# SMPS.net
KiCad netlist of a schematic drawn in Altium Designer
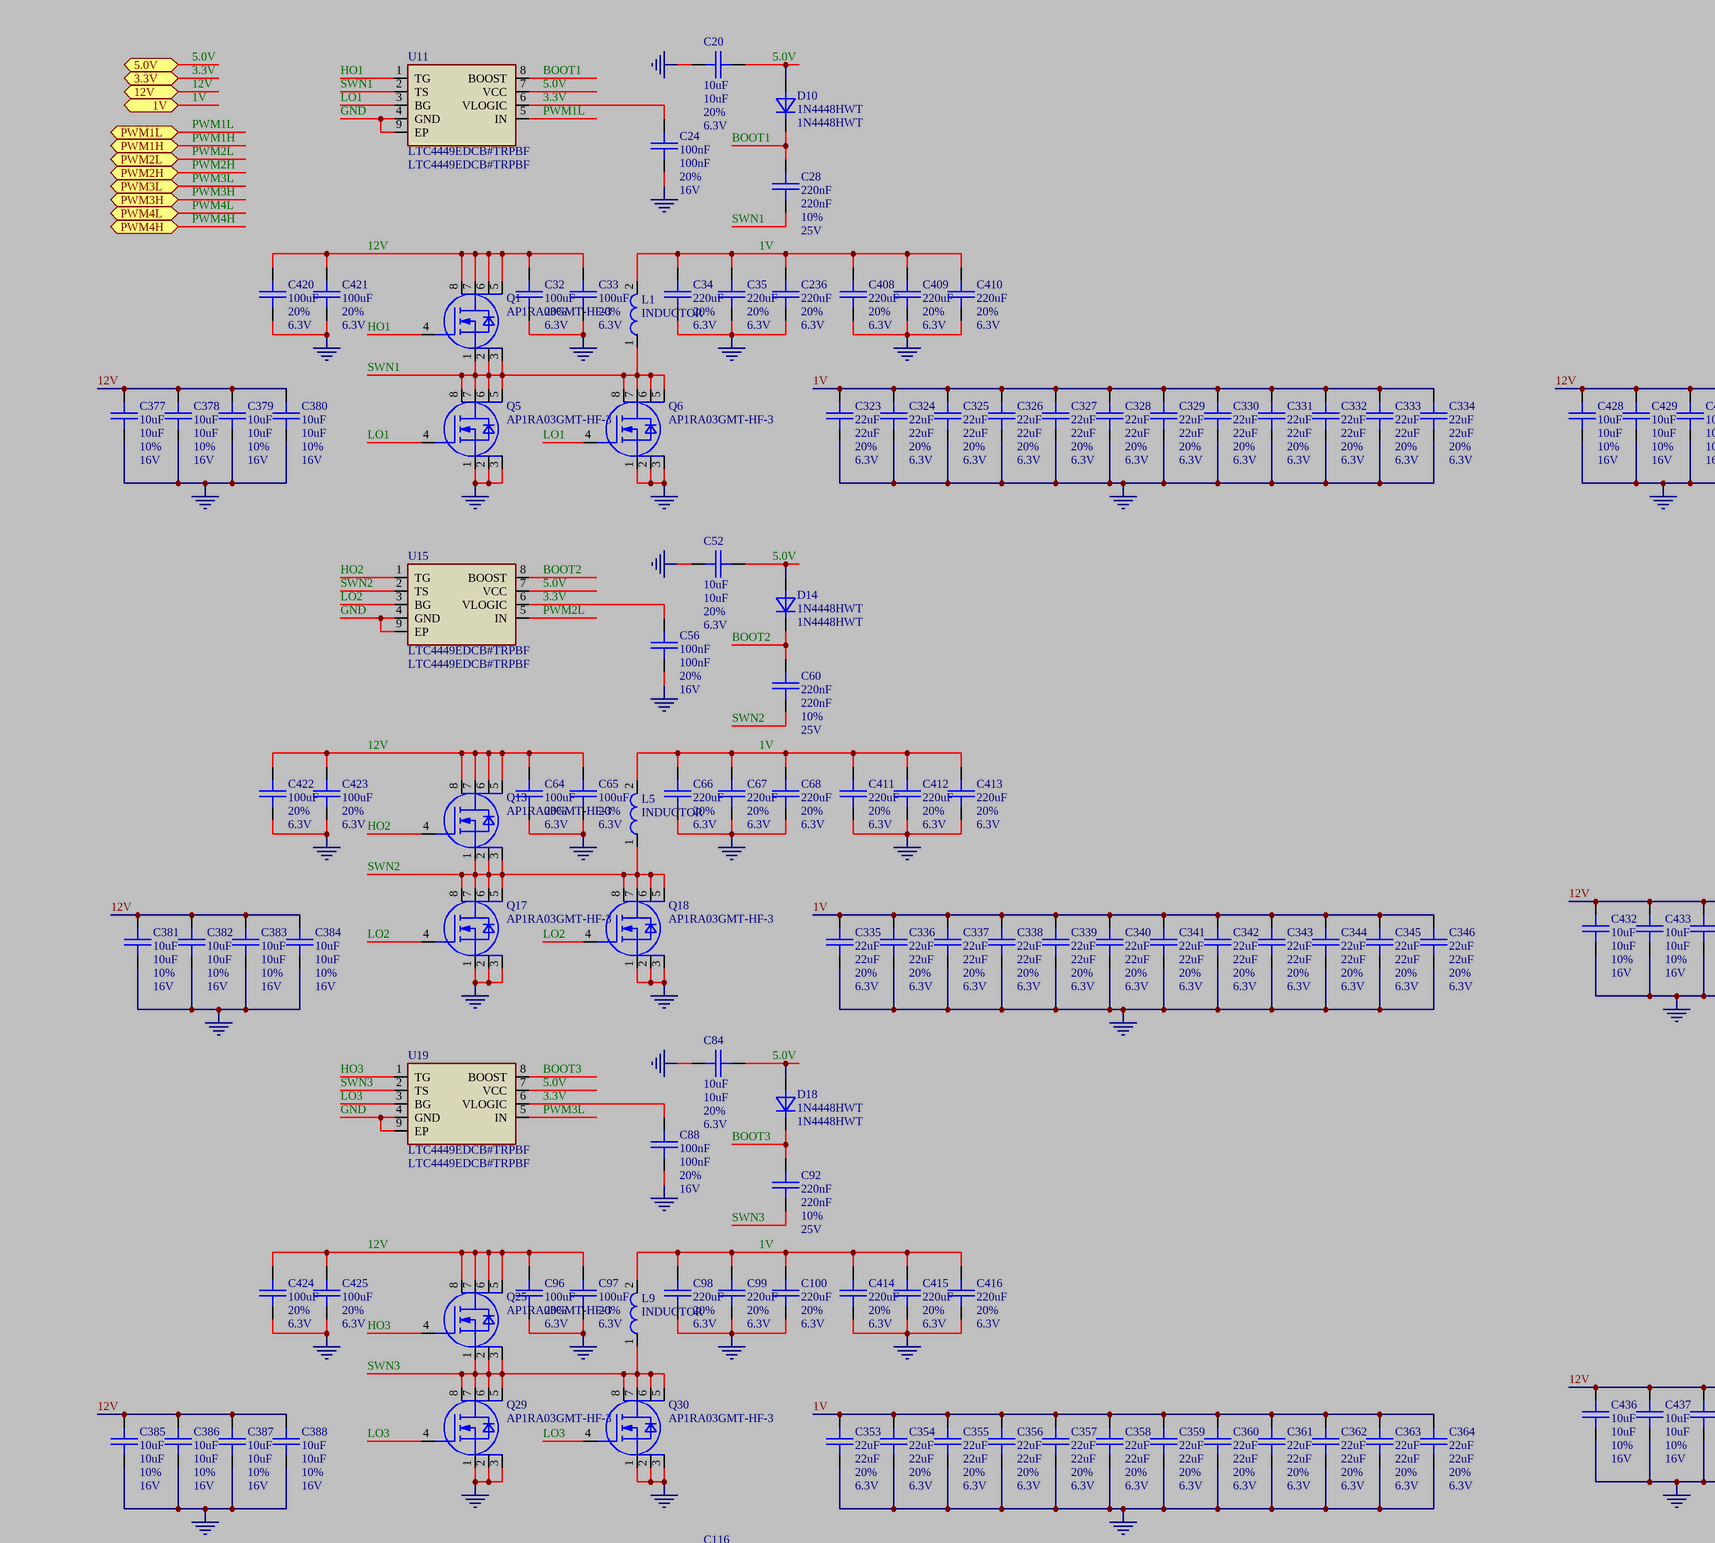
[diagram p0: SMPS.SchDoc, top left]
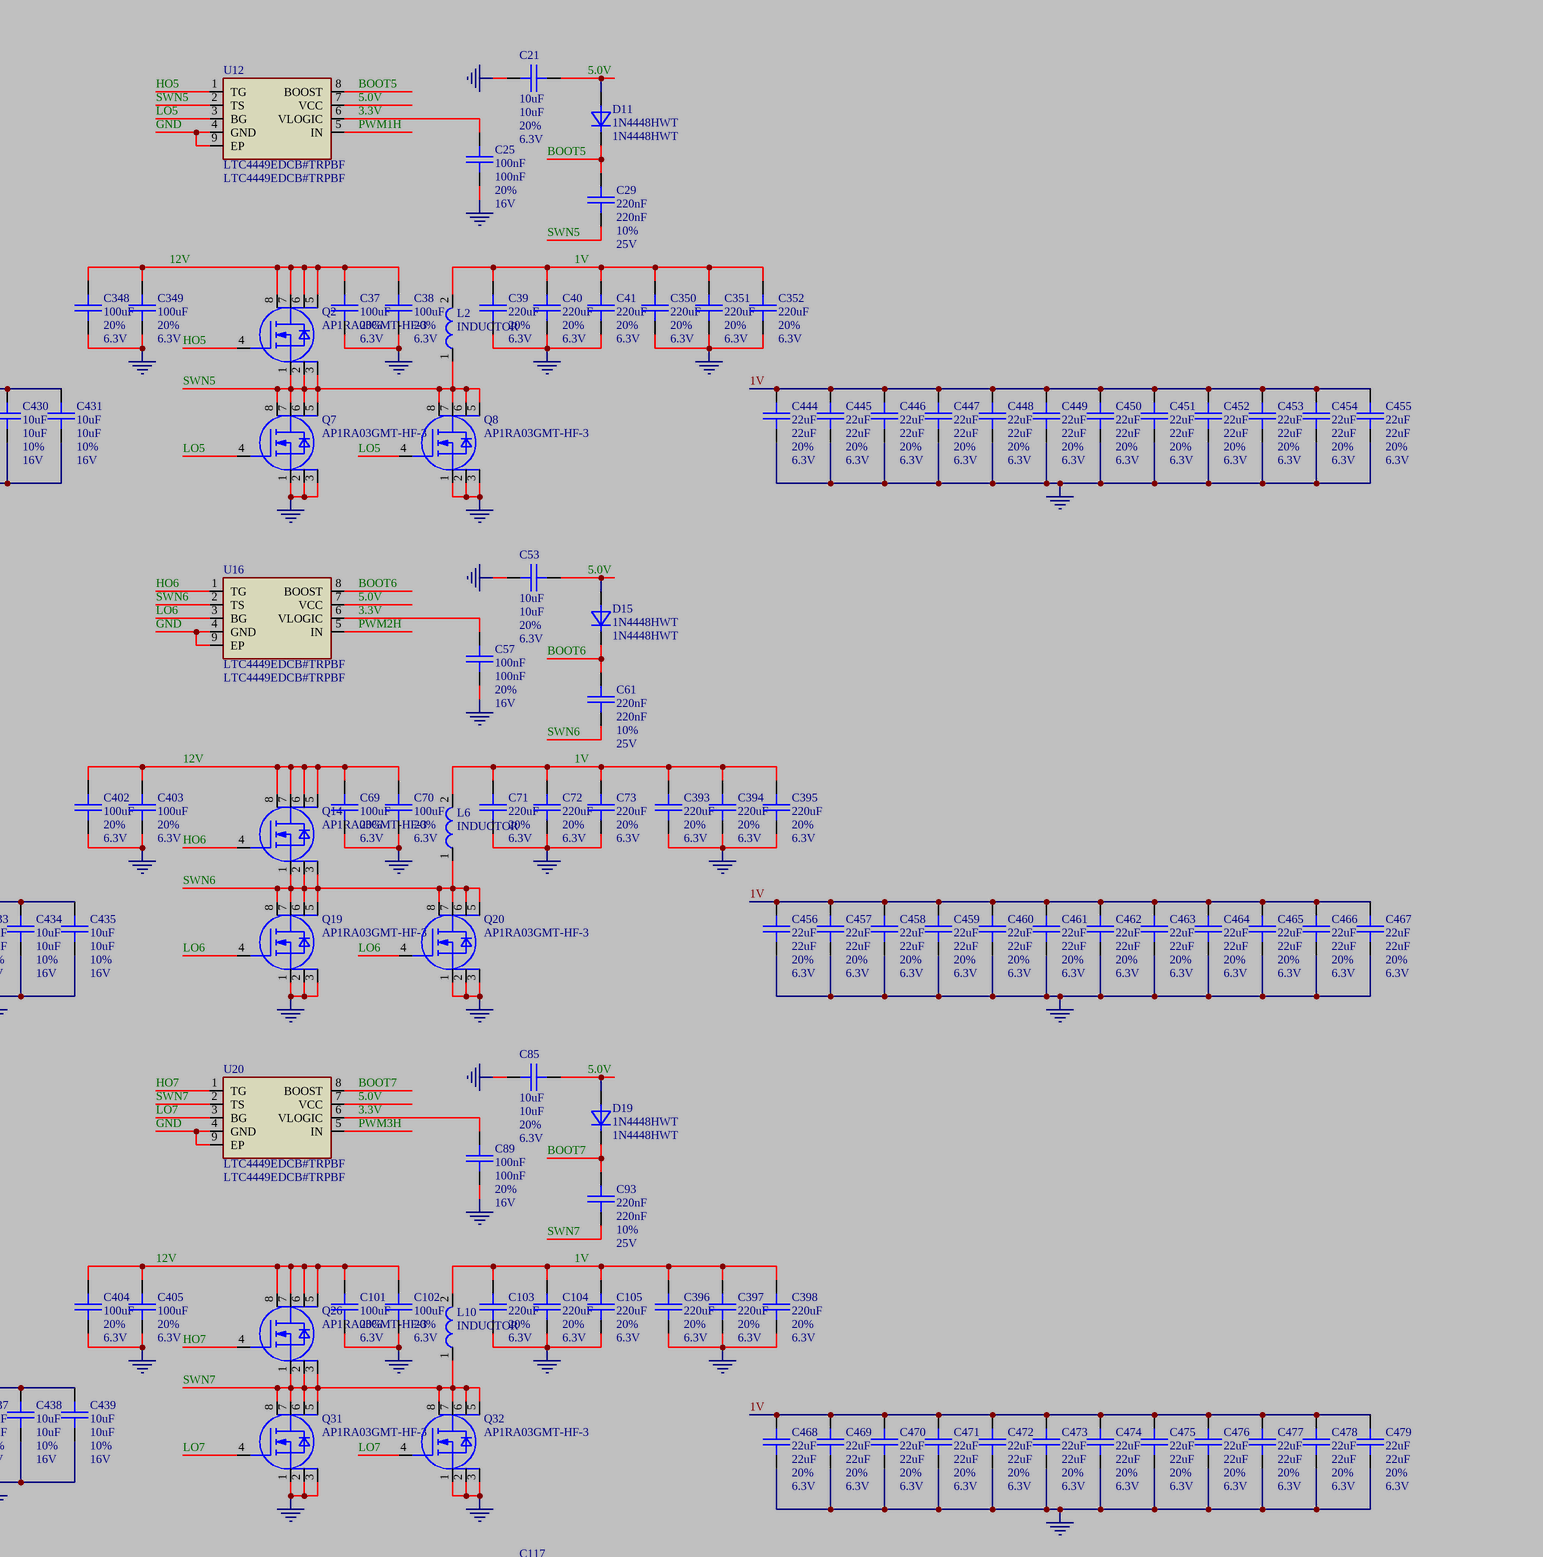
[diagram p1: SMPS.SchDoc, top right]
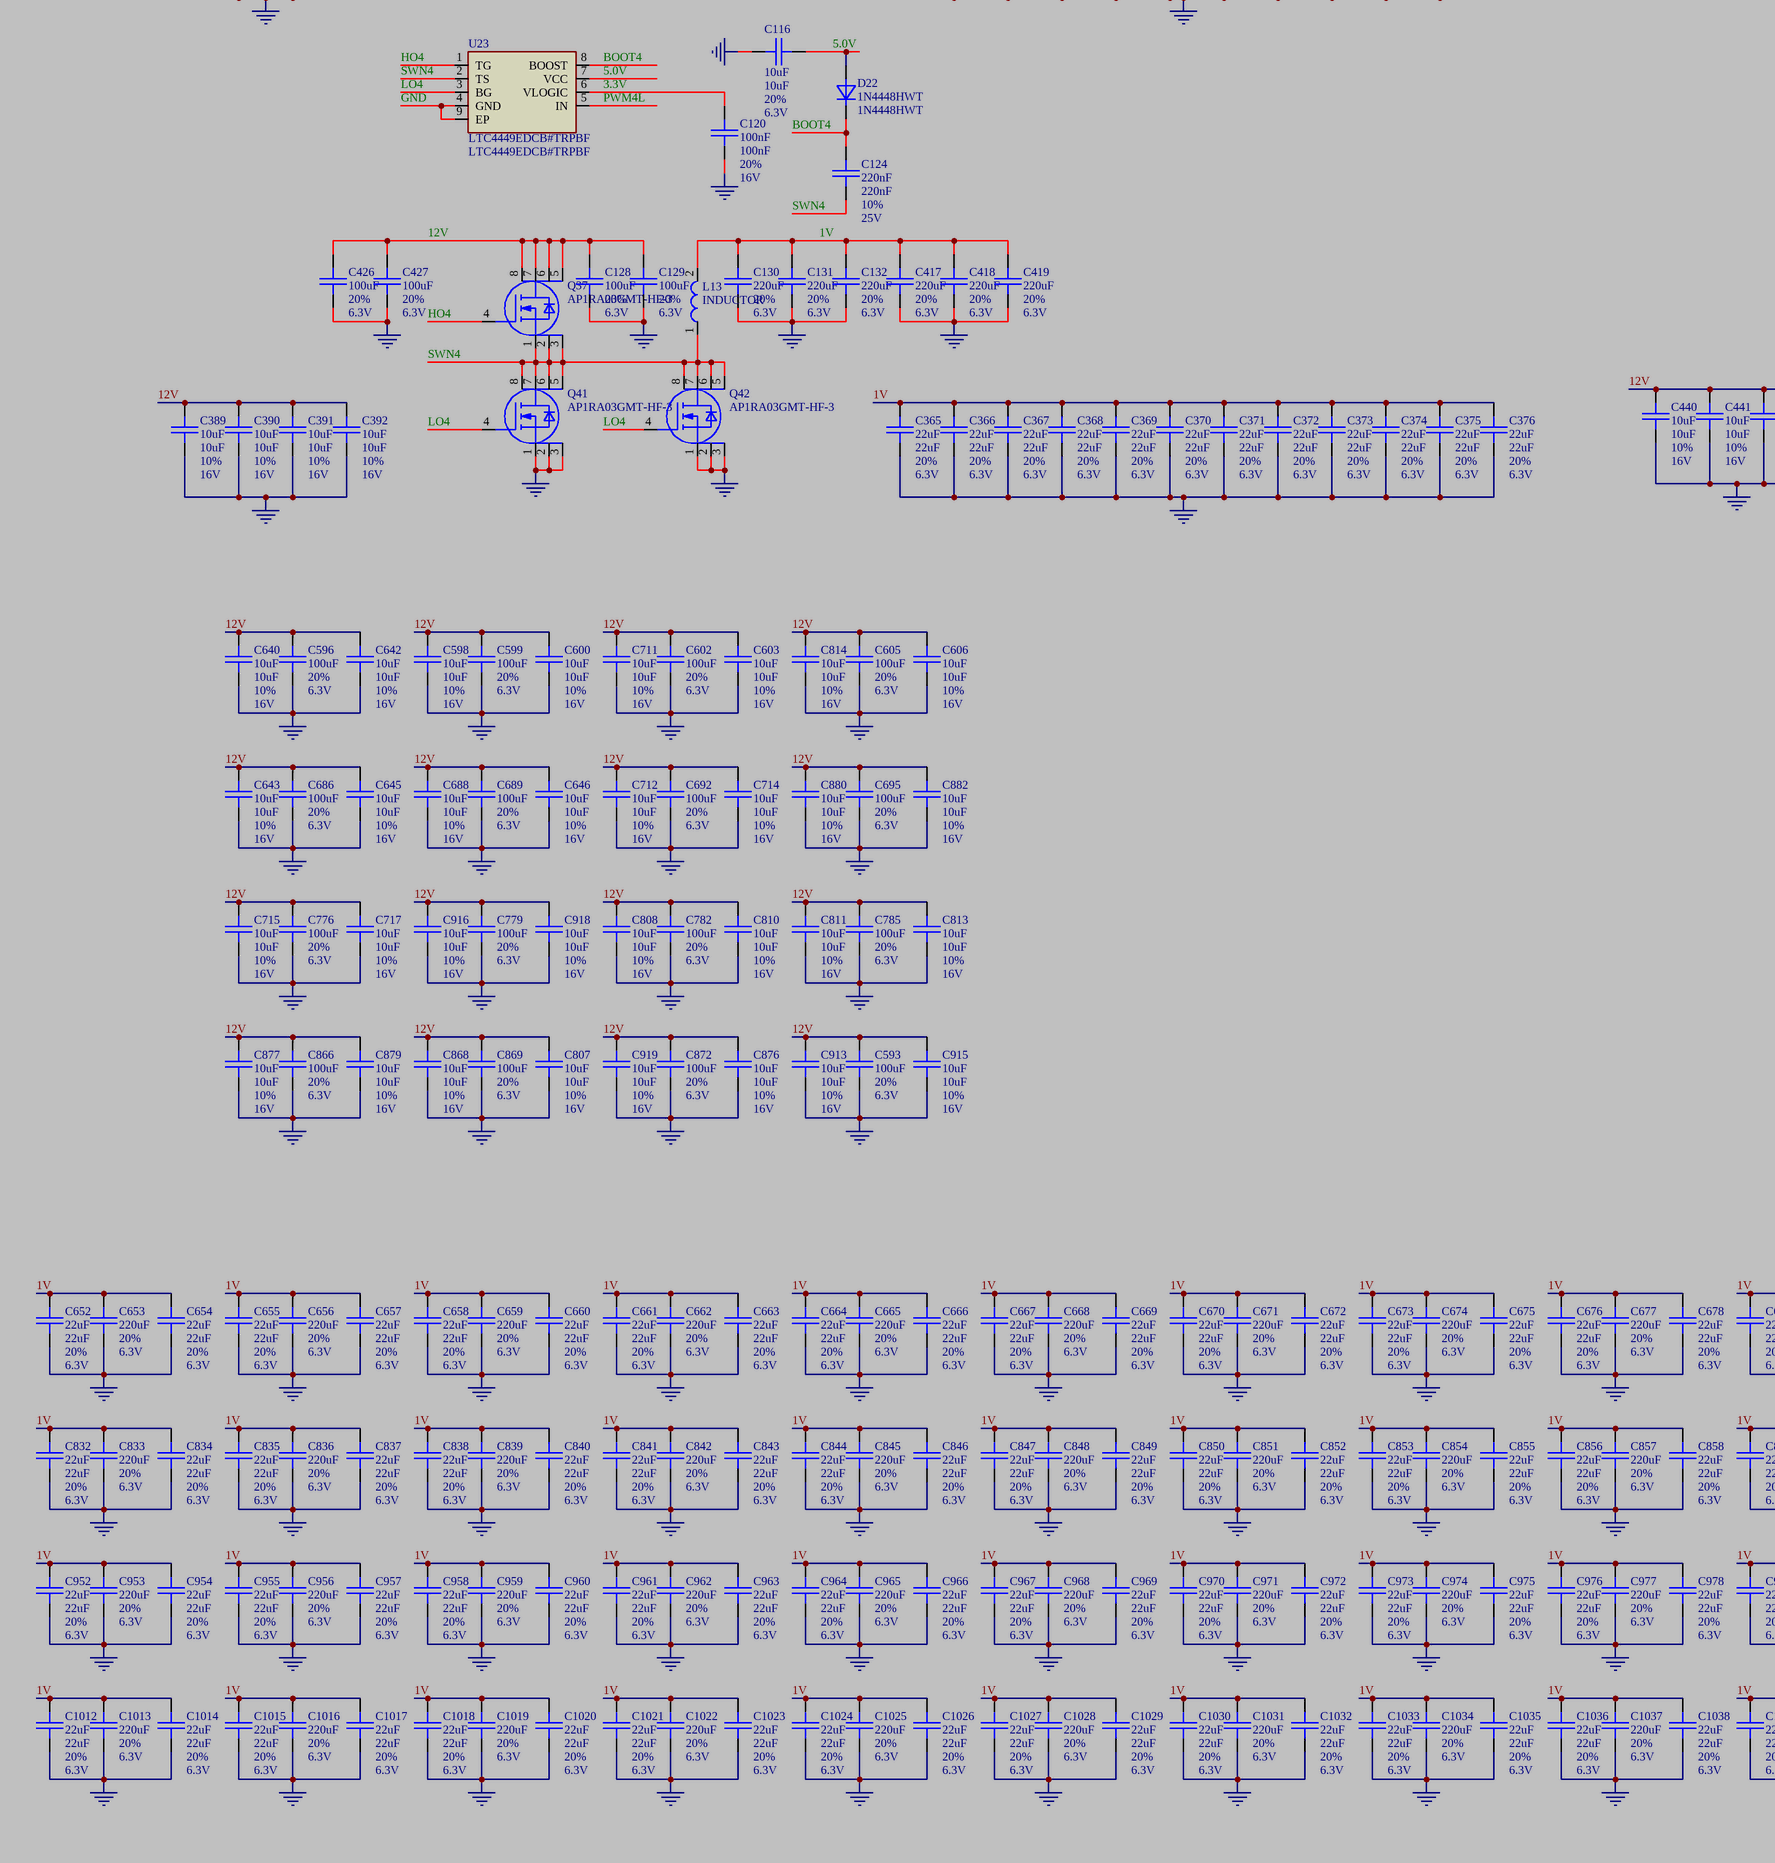
[diagram p2: SMPS.SchDoc, bottom left]
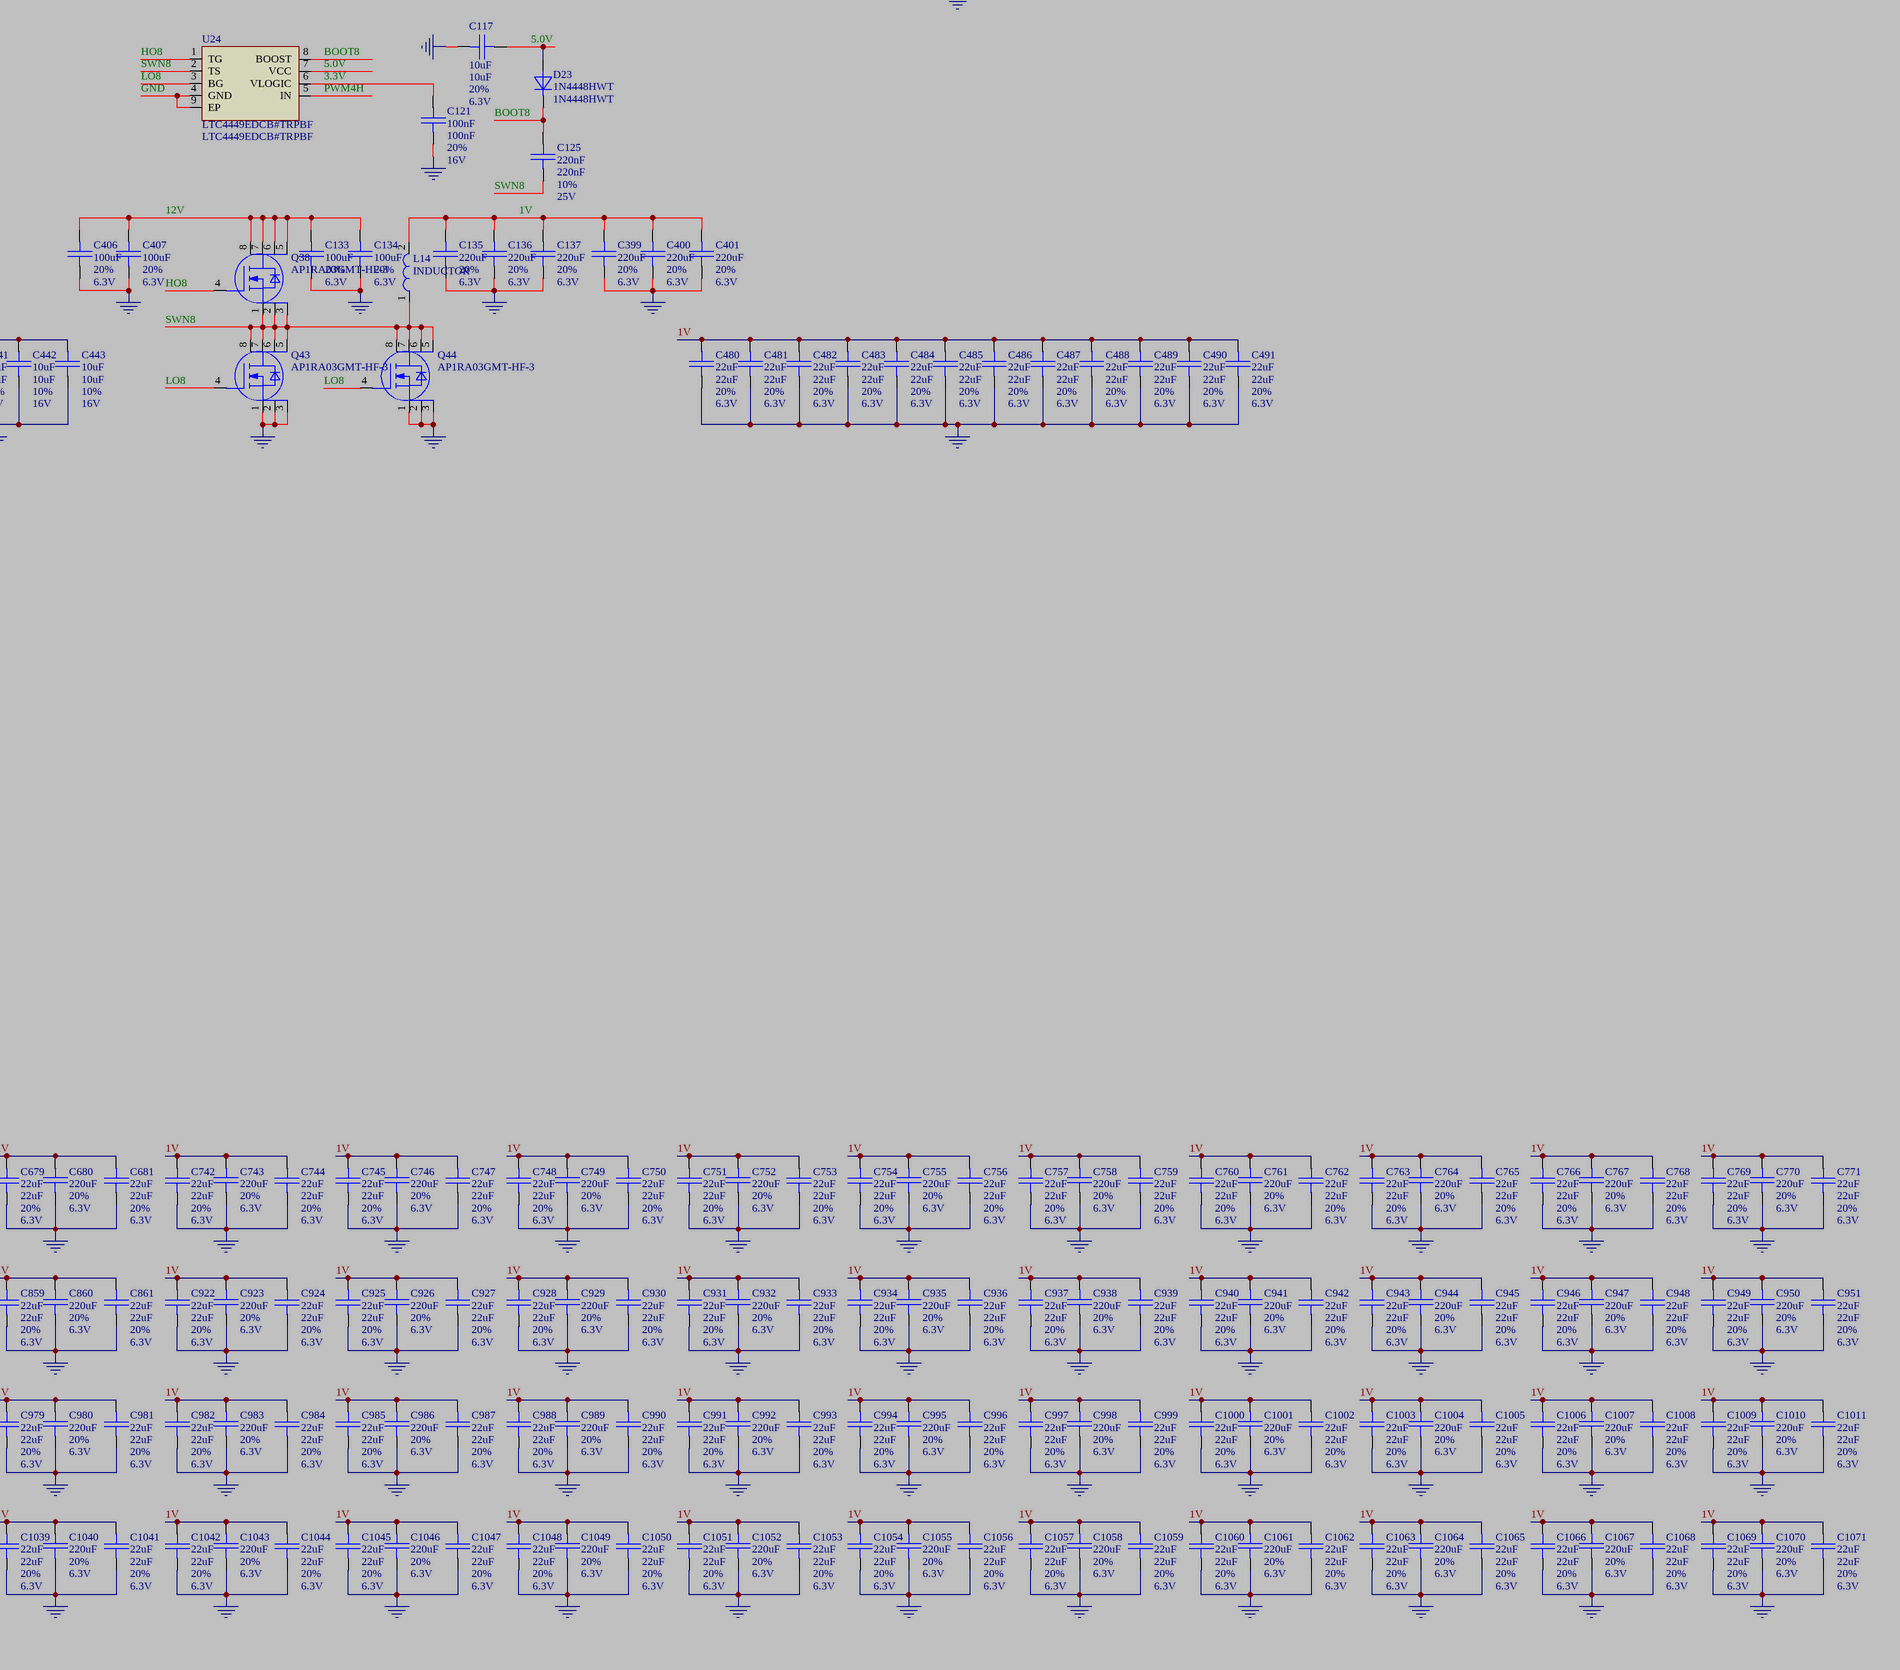
[diagram p3: SMPS.SchDoc, bottom right]

(export (version "E")
  (design (tool "Eeschema 10.0.6"))
  (components
    (comp (ref "C20")
      (value "10uF")
      (footprint "SMD_0603_CAPC1608X95N")
      (fields
        (field (name "DB_PART_NUMBER") "CAP000043646")
        (field (name "DB_VALUE") "10uF")
        (field (name "DB_TOLERANCE") "20%")
        (field (name "DB_VOLTAGE") "6.3V")
        (field (name "DB_MANUFACTURER_PART") "KEMET    C0603C106M9PAC")
        (field (name "DB_APPROVED_BY") "ISHIDDEN=T")
      )
      (libsource (lib "Database_Libs1") (part "C"))
    )
    (comp (ref "C21")
      (value "10uF")
      (footprint "SMD_0603_CAPC1608X95N")
      (fields
        (field (name "DB_PART_NUMBER") "CAP000043646")
        (field (name "DB_VALUE") "10uF")
        (field (name "DB_TOLERANCE") "20%")
        (field (name "DB_VOLTAGE") "6.3V")
        (field (name "DB_MANUFACTURER_PART") "KEMET    C0603C106M9PAC")
        (field (name "DB_APPROVED_BY") "ISHIDDEN=T")
      )
      (libsource (lib "Database_Libs1") (part "C"))
    )
    (comp (ref "C24")
      (value "100nF")
      (footprint "SMD_0402_CAPC1005X55N")
      (fields
        (field (name "DB_PART_NUMBER") "CAP000022751")
        (field (name "DB_VALUE") "100nF")
        (field (name "DB_TOLERANCE") "20%")
        (field (name "DB_VOLTAGE") "16V")
        (field (name "DB_MANUFACTURER_PART") "KEMET    C0402F104M4RAC")
        (field (name "DB_APPROVED_BY") "ISHIDDEN=T")
      )
      (libsource (lib "Database_Libs1") (part "C"))
    )
    (comp (ref "C25")
      (value "100nF")
      (footprint "SMD_0402_CAPC1005X55N")
      (fields
        (field (name "DB_PART_NUMBER") "CAP000022751")
        (field (name "DB_VALUE") "100nF")
        (field (name "DB_TOLERANCE") "20%")
        (field (name "DB_VOLTAGE") "16V")
        (field (name "DB_MANUFACTURER_PART") "KEMET    C0402F104M4RAC")
        (field (name "DB_APPROVED_BY") "ISHIDDEN=T")
      )
      (libsource (lib "Database_Libs1") (part "C"))
    )
    (comp (ref "C28")
      (value "220nF")
      (footprint "SMD_0603_CAPC1608X95N")
      (fields
        (field (name "DB_PART_NUMBER") "CAP000022968")
        (field (name "DB_VALUE") "220nF")
        (field (name "DB_TOLERANCE") "10%")
        (field (name "DB_VOLTAGE") "25V")
        (field (name "DB_MANUFACTURER_PART") "KEMET    C0603F224K3RAC")
        (field (name "DB_APPROVED_BY") "ISHIDDEN=T")
      )
      (libsource (lib "Database_Libs1") (part "C"))
    )
    (comp (ref "C29")
      (value "220nF")
      (footprint "SMD_0603_CAPC1608X95N")
      (fields
        (field (name "DB_PART_NUMBER") "CAP000022968")
        (field (name "DB_VALUE") "220nF")
        (field (name "DB_TOLERANCE") "10%")
        (field (name "DB_VOLTAGE") "25V")
        (field (name "DB_MANUFACTURER_PART") "KEMET    C0603F224K3RAC")
        (field (name "DB_APPROVED_BY") "ISHIDDEN=T")
      )
      (libsource (lib "Database_Libs1") (part "C"))
    )
    (comp (ref "C32")
      (value "100uF")
      (footprint "SMD_1210_CAPC3225X270N")
      (fields
        (field (name "DB_PART_NUMBER") "CAP000043701")
        (field (name "DB_VALUE") "100uF")
        (field (name "DB_TOLERANCE") "20%")
        (field (name "DB_VOLTAGE") "6.3V")
        (field (name "DB_MANUFACTURER_PART") "KEMET    C1210C107M9PAC")
        (field (name "DB_APPROVED_BY") "ISHIDDEN=T")
      )
      (libsource (lib "Database_Libs1") (part "C"))
    )
    (comp (ref "C33")
      (value "100uF")
      (footprint "SMD_1210_CAPC3225X270N")
      (fields
        (field (name "DB_PART_NUMBER") "CAP000043701")
        (field (name "DB_VALUE") "100uF")
        (field (name "DB_TOLERANCE") "20%")
        (field (name "DB_VOLTAGE") "6.3V")
        (field (name "DB_MANUFACTURER_PART") "KEMET    C1210C107M9PAC")
        (field (name "DB_APPROVED_BY") "ISHIDDEN=T")
      )
      (libsource (lib "Database_Libs1") (part "C"))
    )
    (comp (ref "C34")
      (value "220uF")
      (footprint "SMD_1210_CAPC3225X279N")
      (fields
        (field (name "DB_PART_NUMBER") "CAP000047355")
        (field (name "DB_VALUE") "220uF")
        (field (name "DB_TOLERANCE") "20%")
        (field (name "DB_VOLTAGE") "6.3V")
        (field (name "DB_MANUFACTURER_PART") "SAMSUNG    CL32A227MQVNNNE")
        (field (name "DB_APPROVED_BY") "VSN")
      )
      (libsource (lib "Database_Libs1") (part "C"))
    )
    (comp (ref "C35")
      (value "220uF")
      (footprint "SMD_1210_CAPC3225X279N")
      (fields
        (field (name "DB_PART_NUMBER") "CAP000047355")
        (field (name "DB_VALUE") "220uF")
        (field (name "DB_TOLERANCE") "20%")
        (field (name "DB_VOLTAGE") "6.3V")
        (field (name "DB_MANUFACTURER_PART") "SAMSUNG    CL32A227MQVNNNE")
        (field (name "DB_APPROVED_BY") "VSN")
      )
      (libsource (lib "Database_Libs1") (part "C"))
    )
    (comp (ref "C37")
      (value "100uF")
      (footprint "SMD_1210_CAPC3225X270N")
      (fields
        (field (name "DB_PART_NUMBER") "CAP000043701")
        (field (name "DB_VALUE") "100uF")
        (field (name "DB_TOLERANCE") "20%")
        (field (name "DB_VOLTAGE") "6.3V")
        (field (name "DB_MANUFACTURER_PART") "KEMET    C1210C107M9PAC")
        (field (name "DB_APPROVED_BY") "ISHIDDEN=T")
      )
      (libsource (lib "Database_Libs1") (part "C"))
    )
    (comp (ref "C38")
      (value "100uF")
      (footprint "SMD_1210_CAPC3225X270N")
      (fields
        (field (name "DB_PART_NUMBER") "CAP000043701")
        (field (name "DB_VALUE") "100uF")
        (field (name "DB_TOLERANCE") "20%")
        (field (name "DB_VOLTAGE") "6.3V")
        (field (name "DB_MANUFACTURER_PART") "KEMET    C1210C107M9PAC")
        (field (name "DB_APPROVED_BY") "ISHIDDEN=T")
      )
      (libsource (lib "Database_Libs1") (part "C"))
    )
    (comp (ref "C39")
      (value "220uF")
      (footprint "SMD_1210_CAPC3225X279N")
      (fields
        (field (name "DB_PART_NUMBER") "CAP000047355")
        (field (name "DB_VALUE") "220uF")
        (field (name "DB_TOLERANCE") "20%")
        (field (name "DB_VOLTAGE") "6.3V")
        (field (name "DB_MANUFACTURER_PART") "SAMSUNG    CL32A227MQVNNNE")
        (field (name "DB_APPROVED_BY") "VSN")
      )
      (libsource (lib "Database_Libs1") (part "C"))
    )
    (comp (ref "C40")
      (value "220uF")
      (footprint "SMD_1210_CAPC3225X279N")
      (fields
        (field (name "DB_PART_NUMBER") "CAP000047355")
        (field (name "DB_VALUE") "220uF")
        (field (name "DB_TOLERANCE") "20%")
        (field (name "DB_VOLTAGE") "6.3V")
        (field (name "DB_MANUFACTURER_PART") "SAMSUNG    CL32A227MQVNNNE")
        (field (name "DB_APPROVED_BY") "VSN")
      )
      (libsource (lib "Database_Libs1") (part "C"))
    )
    (comp (ref "C41")
      (value "220uF")
      (footprint "SMD_1210_CAPC3225X279N")
      (fields
        (field (name "DB_PART_NUMBER") "CAP000047355")
        (field (name "DB_VALUE") "220uF")
        (field (name "DB_TOLERANCE") "20%")
        (field (name "DB_VOLTAGE") "6.3V")
        (field (name "DB_MANUFACTURER_PART") "SAMSUNG    CL32A227MQVNNNE")
        (field (name "DB_APPROVED_BY") "VSN")
      )
      (libsource (lib "Database_Libs1") (part "C"))
    )
    (comp (ref "C52")
      (value "10uF")
      (footprint "SMD_0603_CAPC1608X95N")
      (fields
        (field (name "DB_PART_NUMBER") "CAP000043646")
        (field (name "DB_VALUE") "10uF")
        (field (name "DB_TOLERANCE") "20%")
        (field (name "DB_VOLTAGE") "6.3V")
        (field (name "DB_MANUFACTURER_PART") "KEMET    C0603C106M9PAC")
        (field (name "DB_APPROVED_BY") "ISHIDDEN=T")
      )
      (libsource (lib "Database_Libs1") (part "C"))
    )
    (comp (ref "C53")
      (value "10uF")
      (footprint "SMD_0603_CAPC1608X95N")
      (fields
        (field (name "DB_PART_NUMBER") "CAP000043646")
        (field (name "DB_VALUE") "10uF")
        (field (name "DB_TOLERANCE") "20%")
        (field (name "DB_VOLTAGE") "6.3V")
        (field (name "DB_MANUFACTURER_PART") "KEMET    C0603C106M9PAC")
        (field (name "DB_APPROVED_BY") "ISHIDDEN=T")
      )
      (libsource (lib "Database_Libs1") (part "C"))
    )
    (comp (ref "C56")
      (value "100nF")
      (footprint "SMD_0402_CAPC1005X55N")
      (fields
        (field (name "DB_PART_NUMBER") "CAP000022751")
        (field (name "DB_VALUE") "100nF")
        (field (name "DB_TOLERANCE") "20%")
        (field (name "DB_VOLTAGE") "16V")
        (field (name "DB_MANUFACTURER_PART") "KEMET    C0402F104M4RAC")
        (field (name "DB_APPROVED_BY") "ISHIDDEN=T")
      )
      (libsource (lib "Database_Libs1") (part "C"))
    )
    (comp (ref "C57")
      (value "100nF")
      (footprint "SMD_0402_CAPC1005X55N")
      (fields
        (field (name "DB_PART_NUMBER") "CAP000022751")
        (field (name "DB_VALUE") "100nF")
        (field (name "DB_TOLERANCE") "20%")
        (field (name "DB_VOLTAGE") "16V")
        (field (name "DB_MANUFACTURER_PART") "KEMET    C0402F104M4RAC")
        (field (name "DB_APPROVED_BY") "ISHIDDEN=T")
      )
      (libsource (lib "Database_Libs1") (part "C"))
    )
    (comp (ref "C60")
      (value "220nF")
      (footprint "SMD_0603_CAPC1608X95N")
      (fields
        (field (name "DB_PART_NUMBER") "CAP000022968")
        (field (name "DB_VALUE") "220nF")
        (field (name "DB_TOLERANCE") "10%")
        (field (name "DB_VOLTAGE") "25V")
        (field (name "DB_MANUFACTURER_PART") "KEMET    C0603F224K3RAC")
        (field (name "DB_APPROVED_BY") "ISHIDDEN=T")
      )
      (libsource (lib "Database_Libs1") (part "C"))
    )
    (comp (ref "C61")
      (value "220nF")
      (footprint "SMD_0603_CAPC1608X95N")
      (fields
        (field (name "DB_PART_NUMBER") "CAP000022968")
        (field (name "DB_VALUE") "220nF")
        (field (name "DB_TOLERANCE") "10%")
        (field (name "DB_VOLTAGE") "25V")
        (field (name "DB_MANUFACTURER_PART") "KEMET    C0603F224K3RAC")
        (field (name "DB_APPROVED_BY") "ISHIDDEN=T")
      )
      (libsource (lib "Database_Libs1") (part "C"))
    )
    (comp (ref "C64")
      (value "100uF")
      (footprint "SMD_1210_CAPC3225X270N")
      (fields
        (field (name "DB_PART_NUMBER") "CAP000043701")
        (field (name "DB_VALUE") "100uF")
        (field (name "DB_TOLERANCE") "20%")
        (field (name "DB_VOLTAGE") "6.3V")
        (field (name "DB_MANUFACTURER_PART") "KEMET    C1210C107M9PAC")
        (field (name "DB_APPROVED_BY") "ISHIDDEN=T")
      )
      (libsource (lib "Database_Libs1") (part "C"))
    )
    (comp (ref "C65")
      (value "100uF")
      (footprint "SMD_1210_CAPC3225X270N")
      (fields
        (field (name "DB_PART_NUMBER") "CAP000043701")
        (field (name "DB_VALUE") "100uF")
        (field (name "DB_TOLERANCE") "20%")
        (field (name "DB_VOLTAGE") "6.3V")
        (field (name "DB_MANUFACTURER_PART") "KEMET    C1210C107M9PAC")
        (field (name "DB_APPROVED_BY") "ISHIDDEN=T")
      )
      (libsource (lib "Database_Libs1") (part "C"))
    )
    (comp (ref "C66")
      (value "220uF")
      (footprint "SMD_1210_CAPC3225X279N")
      (fields
        (field (name "DB_PART_NUMBER") "CAP000047355")
        (field (name "DB_VALUE") "220uF")
        (field (name "DB_TOLERANCE") "20%")
        (field (name "DB_VOLTAGE") "6.3V")
        (field (name "DB_MANUFACTURER_PART") "SAMSUNG    CL32A227MQVNNNE")
        (field (name "DB_APPROVED_BY") "VSN")
      )
      (libsource (lib "Database_Libs1") (part "C"))
    )
    (comp (ref "C67")
      (value "220uF")
      (footprint "SMD_1210_CAPC3225X279N")
      (fields
        (field (name "DB_PART_NUMBER") "CAP000047355")
        (field (name "DB_VALUE") "220uF")
        (field (name "DB_TOLERANCE") "20%")
        (field (name "DB_VOLTAGE") "6.3V")
        (field (name "DB_MANUFACTURER_PART") "SAMSUNG    CL32A227MQVNNNE")
        (field (name "DB_APPROVED_BY") "VSN")
      )
      (libsource (lib "Database_Libs1") (part "C"))
    )
    (comp (ref "C68")
      (value "220uF")
      (footprint "SMD_1210_CAPC3225X279N")
      (fields
        (field (name "DB_PART_NUMBER") "CAP000047355")
        (field (name "DB_VALUE") "220uF")
        (field (name "DB_TOLERANCE") "20%")
        (field (name "DB_VOLTAGE") "6.3V")
        (field (name "DB_MANUFACTURER_PART") "SAMSUNG    CL32A227MQVNNNE")
        (field (name "DB_APPROVED_BY") "VSN")
      )
      (libsource (lib "Database_Libs1") (part "C"))
    )
    (comp (ref "C69")
      (value "100uF")
      (footprint "SMD_1210_CAPC3225X270N")
      (fields
        (field (name "DB_PART_NUMBER") "CAP000043701")
        (field (name "DB_VALUE") "100uF")
        (field (name "DB_TOLERANCE") "20%")
        (field (name "DB_VOLTAGE") "6.3V")
        (field (name "DB_MANUFACTURER_PART") "KEMET    C1210C107M9PAC")
        (field (name "DB_APPROVED_BY") "ISHIDDEN=T")
      )
      (libsource (lib "Database_Libs1") (part "C"))
    )
    (comp (ref "C70")
      (value "100uF")
      (footprint "SMD_1210_CAPC3225X270N")
      (fields
        (field (name "DB_PART_NUMBER") "CAP000043701")
        (field (name "DB_VALUE") "100uF")
        (field (name "DB_TOLERANCE") "20%")
        (field (name "DB_VOLTAGE") "6.3V")
        (field (name "DB_MANUFACTURER_PART") "KEMET    C1210C107M9PAC")
        (field (name "DB_APPROVED_BY") "ISHIDDEN=T")
      )
      (libsource (lib "Database_Libs1") (part "C"))
    )
    (comp (ref "C71")
      (value "220uF")
      (footprint "SMD_1210_CAPC3225X279N")
      (fields
        (field (name "DB_PART_NUMBER") "CAP000047355")
        (field (name "DB_VALUE") "220uF")
        (field (name "DB_TOLERANCE") "20%")
        (field (name "DB_VOLTAGE") "6.3V")
        (field (name "DB_MANUFACTURER_PART") "SAMSUNG    CL32A227MQVNNNE")
        (field (name "DB_APPROVED_BY") "VSN")
      )
      (libsource (lib "Database_Libs1") (part "C"))
    )
    (comp (ref "C72")
      (value "220uF")
      (footprint "SMD_1210_CAPC3225X279N")
      (fields
        (field (name "DB_PART_NUMBER") "CAP000047355")
        (field (name "DB_VALUE") "220uF")
        (field (name "DB_TOLERANCE") "20%")
        (field (name "DB_VOLTAGE") "6.3V")
        (field (name "DB_MANUFACTURER_PART") "SAMSUNG    CL32A227MQVNNNE")
        (field (name "DB_APPROVED_BY") "VSN")
      )
      (libsource (lib "Database_Libs1") (part "C"))
    )
    (comp (ref "C73")
      (value "220uF")
      (footprint "SMD_1210_CAPC3225X279N")
      (fields
        (field (name "DB_PART_NUMBER") "CAP000047355")
        (field (name "DB_VALUE") "220uF")
        (field (name "DB_TOLERANCE") "20%")
        (field (name "DB_VOLTAGE") "6.3V")
        (field (name "DB_MANUFACTURER_PART") "SAMSUNG    CL32A227MQVNNNE")
        (field (name "DB_APPROVED_BY") "VSN")
      )
      (libsource (lib "Database_Libs1") (part "C"))
    )
    (comp (ref "C84")
      (value "10uF")
      (footprint "SMD_0603_CAPC1608X95N")
      (fields
        (field (name "DB_PART_NUMBER") "CAP000043646")
        (field (name "DB_VALUE") "10uF")
        (field (name "DB_TOLERANCE") "20%")
        (field (name "DB_VOLTAGE") "6.3V")
        (field (name "DB_MANUFACTURER_PART") "KEMET    C0603C106M9PAC")
        (field (name "DB_APPROVED_BY") "ISHIDDEN=T")
      )
      (libsource (lib "Database_Libs1") (part "C"))
    )
    (comp (ref "C85")
      (value "10uF")
      (footprint "SMD_0603_CAPC1608X95N")
      (fields
        (field (name "DB_PART_NUMBER") "CAP000043646")
        (field (name "DB_VALUE") "10uF")
        (field (name "DB_TOLERANCE") "20%")
        (field (name "DB_VOLTAGE") "6.3V")
        (field (name "DB_MANUFACTURER_PART") "KEMET    C0603C106M9PAC")
        (field (name "DB_APPROVED_BY") "ISHIDDEN=T")
      )
      (libsource (lib "Database_Libs1") (part "C"))
    )
    (comp (ref "C88")
      (value "100nF")
      (footprint "SMD_0402_CAPC1005X55N")
      (fields
        (field (name "DB_PART_NUMBER") "CAP000022751")
        (field (name "DB_VALUE") "100nF")
        (field (name "DB_TOLERANCE") "20%")
        (field (name "DB_VOLTAGE") "16V")
        (field (name "DB_MANUFACTURER_PART") "KEMET    C0402F104M4RAC")
        (field (name "DB_APPROVED_BY") "ISHIDDEN=T")
      )
      (libsource (lib "Database_Libs1") (part "C"))
    )
    (comp (ref "C89")
      (value "100nF")
      (footprint "SMD_0402_CAPC1005X55N")
      (fields
        (field (name "DB_PART_NUMBER") "CAP000022751")
        (field (name "DB_VALUE") "100nF")
        (field (name "DB_TOLERANCE") "20%")
        (field (name "DB_VOLTAGE") "16V")
        (field (name "DB_MANUFACTURER_PART") "KEMET    C0402F104M4RAC")
        (field (name "DB_APPROVED_BY") "ISHIDDEN=T")
      )
      (libsource (lib "Database_Libs1") (part "C"))
    )
    (comp (ref "C92")
      (value "220nF")
      (footprint "SMD_0603_CAPC1608X95N")
      (fields
        (field (name "DB_PART_NUMBER") "CAP000022968")
        (field (name "DB_VALUE") "220nF")
        (field (name "DB_TOLERANCE") "10%")
        (field (name "DB_VOLTAGE") "25V")
        (field (name "DB_MANUFACTURER_PART") "KEMET    C0603F224K3RAC")
        (field (name "DB_APPROVED_BY") "ISHIDDEN=T")
      )
      (libsource (lib "Database_Libs1") (part "C"))
    )
    (comp (ref "C93")
      (value "220nF")
      (footprint "SMD_0603_CAPC1608X95N")
      (fields
        (field (name "DB_PART_NUMBER") "CAP000022968")
        (field (name "DB_VALUE") "220nF")
        (field (name "DB_TOLERANCE") "10%")
        (field (name "DB_VOLTAGE") "25V")
        (field (name "DB_MANUFACTURER_PART") "KEMET    C0603F224K3RAC")
        (field (name "DB_APPROVED_BY") "ISHIDDEN=T")
      )
      (libsource (lib "Database_Libs1") (part "C"))
    )
    (comp (ref "C96")
      (value "100uF")
      (footprint "SMD_1210_CAPC3225X270N")
      (fields
        (field (name "DB_PART_NUMBER") "CAP000043701")
        (field (name "DB_VALUE") "100uF")
        (field (name "DB_TOLERANCE") "20%")
        (field (name "DB_VOLTAGE") "6.3V")
        (field (name "DB_MANUFACTURER_PART") "KEMET    C1210C107M9PAC")
        (field (name "DB_APPROVED_BY") "ISHIDDEN=T")
      )
      (libsource (lib "Database_Libs1") (part "C"))
    )
    (comp (ref "C97")
      (value "100uF")
      (footprint "SMD_1210_CAPC3225X270N")
      (fields
        (field (name "DB_PART_NUMBER") "CAP000043701")
        (field (name "DB_VALUE") "100uF")
        (field (name "DB_TOLERANCE") "20%")
        (field (name "DB_VOLTAGE") "6.3V")
        (field (name "DB_MANUFACTURER_PART") "KEMET    C1210C107M9PAC")
        (field (name "DB_APPROVED_BY") "ISHIDDEN=T")
      )
      (libsource (lib "Database_Libs1") (part "C"))
    )
    (comp (ref "C98")
      (value "220uF")
      (footprint "SMD_1210_CAPC3225X279N")
      (fields
        (field (name "DB_PART_NUMBER") "CAP000047355")
        (field (name "DB_VALUE") "220uF")
        (field (name "DB_TOLERANCE") "20%")
        (field (name "DB_VOLTAGE") "6.3V")
        (field (name "DB_MANUFACTURER_PART") "SAMSUNG    CL32A227MQVNNNE")
        (field (name "DB_APPROVED_BY") "VSN")
      )
      (libsource (lib "Database_Libs1") (part "C"))
    )
    (comp (ref "C99")
      (value "220uF")
      (footprint "SMD_1210_CAPC3225X279N")
      (fields
        (field (name "DB_PART_NUMBER") "CAP000047355")
        (field (name "DB_VALUE") "220uF")
        (field (name "DB_TOLERANCE") "20%")
        (field (name "DB_VOLTAGE") "6.3V")
        (field (name "DB_MANUFACTURER_PART") "SAMSUNG    CL32A227MQVNNNE")
        (field (name "DB_APPROVED_BY") "VSN")
      )
      (libsource (lib "Database_Libs1") (part "C"))
    )
    (comp (ref "C100")
      (value "220uF")
      (footprint "SMD_1210_CAPC3225X279N")
      (fields
        (field (name "DB_PART_NUMBER") "CAP000047355")
        (field (name "DB_VALUE") "220uF")
        (field (name "DB_TOLERANCE") "20%")
        (field (name "DB_VOLTAGE") "6.3V")
        (field (name "DB_MANUFACTURER_PART") "SAMSUNG    CL32A227MQVNNNE")
        (field (name "DB_APPROVED_BY") "VSN")
      )
      (libsource (lib "Database_Libs1") (part "C"))
    )
    (comp (ref "C101")
      (value "100uF")
      (footprint "SMD_1210_CAPC3225X270N")
      (fields
        (field (name "DB_PART_NUMBER") "CAP000043701")
        (field (name "DB_VALUE") "100uF")
        (field (name "DB_TOLERANCE") "20%")
        (field (name "DB_VOLTAGE") "6.3V")
        (field (name "DB_MANUFACTURER_PART") "KEMET    C1210C107M9PAC")
        (field (name "DB_APPROVED_BY") "ISHIDDEN=T")
      )
      (libsource (lib "Database_Libs1") (part "C"))
    )
    (comp (ref "C102")
      (value "100uF")
      (footprint "SMD_1210_CAPC3225X270N")
      (fields
        (field (name "DB_PART_NUMBER") "CAP000043701")
        (field (name "DB_VALUE") "100uF")
        (field (name "DB_TOLERANCE") "20%")
        (field (name "DB_VOLTAGE") "6.3V")
        (field (name "DB_MANUFACTURER_PART") "KEMET    C1210C107M9PAC")
        (field (name "DB_APPROVED_BY") "ISHIDDEN=T")
      )
      (libsource (lib "Database_Libs1") (part "C"))
    )
    (comp (ref "C103")
      (value "220uF")
      (footprint "SMD_1210_CAPC3225X279N")
      (fields
        (field (name "DB_PART_NUMBER") "CAP000047355")
        (field (name "DB_VALUE") "220uF")
        (field (name "DB_TOLERANCE") "20%")
        (field (name "DB_VOLTAGE") "6.3V")
        (field (name "DB_MANUFACTURER_PART") "SAMSUNG    CL32A227MQVNNNE")
        (field (name "DB_APPROVED_BY") "VSN")
      )
      (libsource (lib "Database_Libs1") (part "C"))
    )
    (comp (ref "C104")
      (value "220uF")
      (footprint "SMD_1210_CAPC3225X279N")
      (fields
        (field (name "DB_PART_NUMBER") "CAP000047355")
        (field (name "DB_VALUE") "220uF")
        (field (name "DB_TOLERANCE") "20%")
        (field (name "DB_VOLTAGE") "6.3V")
        (field (name "DB_MANUFACTURER_PART") "SAMSUNG    CL32A227MQVNNNE")
        (field (name "DB_APPROVED_BY") "VSN")
      )
      (libsource (lib "Database_Libs1") (part "C"))
    )
    (comp (ref "C105")
      (value "220uF")
      (footprint "SMD_1210_CAPC3225X279N")
      (fields
        (field (name "DB_PART_NUMBER") "CAP000047355")
        (field (name "DB_VALUE") "220uF")
        (field (name "DB_TOLERANCE") "20%")
        (field (name "DB_VOLTAGE") "6.3V")
        (field (name "DB_MANUFACTURER_PART") "SAMSUNG    CL32A227MQVNNNE")
        (field (name "DB_APPROVED_BY") "VSN")
      )
      (libsource (lib "Database_Libs1") (part "C"))
    )
    (comp (ref "C116")
      (value "10uF")
      (footprint "SMD_0603_CAPC1608X95N")
      (fields
        (field (name "DB_PART_NUMBER") "CAP000043646")
        (field (name "DB_VALUE") "10uF")
        (field (name "DB_TOLERANCE") "20%")
        (field (name "DB_VOLTAGE") "6.3V")
        (field (name "DB_MANUFACTURER_PART") "KEMET    C0603C106M9PAC")
        (field (name "DB_APPROVED_BY") "ISHIDDEN=T")
      )
      (libsource (lib "Database_Libs1") (part "C"))
    )
    (comp (ref "C117")
      (value "10uF")
      (footprint "SMD_0603_CAPC1608X95N")
      (fields
        (field (name "DB_PART_NUMBER") "CAP000043646")
        (field (name "DB_VALUE") "10uF")
        (field (name "DB_TOLERANCE") "20%")
        (field (name "DB_VOLTAGE") "6.3V")
        (field (name "DB_MANUFACTURER_PART") "KEMET    C0603C106M9PAC")
        (field (name "DB_APPROVED_BY") "ISHIDDEN=T")
      )
      (libsource (lib "Database_Libs1") (part "C"))
    )
    (comp (ref "C120")
      (value "100nF")
      (footprint "SMD_0402_CAPC1005X55N")
      (fields
        (field (name "DB_PART_NUMBER") "CAP000022751")
        (field (name "DB_VALUE") "100nF")
        (field (name "DB_TOLERANCE") "20%")
        (field (name "DB_VOLTAGE") "16V")
        (field (name "DB_MANUFACTURER_PART") "KEMET    C0402F104M4RAC")
        (field (name "DB_APPROVED_BY") "ISHIDDEN=T")
      )
      (libsource (lib "Database_Libs1") (part "C"))
    )
    (comp (ref "C121")
      (value "100nF")
      (footprint "SMD_0402_CAPC1005X55N")
      (fields
        (field (name "DB_PART_NUMBER") "CAP000022751")
        (field (name "DB_VALUE") "100nF")
        (field (name "DB_TOLERANCE") "20%")
        (field (name "DB_VOLTAGE") "16V")
        (field (name "DB_MANUFACTURER_PART") "KEMET    C0402F104M4RAC")
        (field (name "DB_APPROVED_BY") "ISHIDDEN=T")
      )
      (libsource (lib "Database_Libs1") (part "C"))
    )
    (comp (ref "C124")
      (value "220nF")
      (footprint "SMD_0603_CAPC1608X95N")
      (fields
        (field (name "DB_PART_NUMBER") "CAP000022968")
        (field (name "DB_VALUE") "220nF")
        (field (name "DB_TOLERANCE") "10%")
        (field (name "DB_VOLTAGE") "25V")
        (field (name "DB_MANUFACTURER_PART") "KEMET    C0603F224K3RAC")
        (field (name "DB_APPROVED_BY") "ISHIDDEN=T")
      )
      (libsource (lib "Database_Libs1") (part "C"))
    )
    (comp (ref "C125")
      (value "220nF")
      (footprint "SMD_0603_CAPC1608X95N")
      (fields
        (field (name "DB_PART_NUMBER") "CAP000022968")
        (field (name "DB_VALUE") "220nF")
        (field (name "DB_TOLERANCE") "10%")
        (field (name "DB_VOLTAGE") "25V")
        (field (name "DB_MANUFACTURER_PART") "KEMET    C0603F224K3RAC")
        (field (name "DB_APPROVED_BY") "ISHIDDEN=T")
      )
      (libsource (lib "Database_Libs1") (part "C"))
    )
    (comp (ref "C128")
      (value "100uF")
      (footprint "SMD_1210_CAPC3225X270N")
      (fields
        (field (name "DB_PART_NUMBER") "CAP000043701")
        (field (name "DB_VALUE") "100uF")
        (field (name "DB_TOLERANCE") "20%")
        (field (name "DB_VOLTAGE") "6.3V")
        (field (name "DB_MANUFACTURER_PART") "KEMET    C1210C107M9PAC")
        (field (name "DB_APPROVED_BY") "ISHIDDEN=T")
      )
      (libsource (lib "Database_Libs1") (part "C"))
    )
    (comp (ref "C129")
      (value "100uF")
      (footprint "SMD_1210_CAPC3225X270N")
      (fields
        (field (name "DB_PART_NUMBER") "CAP000043701")
        (field (name "DB_VALUE") "100uF")
        (field (name "DB_TOLERANCE") "20%")
        (field (name "DB_VOLTAGE") "6.3V")
        (field (name "DB_MANUFACTURER_PART") "KEMET    C1210C107M9PAC")
        (field (name "DB_APPROVED_BY") "ISHIDDEN=T")
      )
      (libsource (lib "Database_Libs1") (part "C"))
    )
    (comp (ref "C130")
      (value "220uF")
      (footprint "SMD_1210_CAPC3225X279N")
      (fields
        (field (name "DB_PART_NUMBER") "CAP000047355")
        (field (name "DB_VALUE") "220uF")
        (field (name "DB_TOLERANCE") "20%")
        (field (name "DB_VOLTAGE") "6.3V")
        (field (name "DB_MANUFACTURER_PART") "SAMSUNG    CL32A227MQVNNNE")
        (field (name "DB_APPROVED_BY") "VSN")
      )
      (libsource (lib "Database_Libs1") (part "C"))
    )
    (comp (ref "C131")
      (value "220uF")
      (footprint "SMD_1210_CAPC3225X279N")
      (fields
        (field (name "DB_PART_NUMBER") "CAP000047355")
        (field (name "DB_VALUE") "220uF")
        (field (name "DB_TOLERANCE") "20%")
        (field (name "DB_VOLTAGE") "6.3V")
        (field (name "DB_MANUFACTURER_PART") "SAMSUNG    CL32A227MQVNNNE")
        (field (name "DB_APPROVED_BY") "VSN")
      )
      (libsource (lib "Database_Libs1") (part "C"))
    )
    (comp (ref "C132")
      (value "220uF")
      (footprint "SMD_1210_CAPC3225X279N")
      (fields
        (field (name "DB_PART_NUMBER") "CAP000047355")
        (field (name "DB_VALUE") "220uF")
        (field (name "DB_TOLERANCE") "20%")
        (field (name "DB_VOLTAGE") "6.3V")
        (field (name "DB_MANUFACTURER_PART") "SAMSUNG    CL32A227MQVNNNE")
        (field (name "DB_APPROVED_BY") "VSN")
      )
      (libsource (lib "Database_Libs1") (part "C"))
    )
    (comp (ref "C133")
      (value "100uF")
      (footprint "SMD_1210_CAPC3225X270N")
      (fields
        (field (name "DB_PART_NUMBER") "CAP000043701")
        (field (name "DB_VALUE") "100uF")
        (field (name "DB_TOLERANCE") "20%")
        (field (name "DB_VOLTAGE") "6.3V")
        (field (name "DB_MANUFACTURER_PART") "KEMET    C1210C107M9PAC")
        (field (name "DB_APPROVED_BY") "ISHIDDEN=T")
      )
      (libsource (lib "Database_Libs1") (part "C"))
    )
    (comp (ref "C134")
      (value "100uF")
      (footprint "SMD_1210_CAPC3225X270N")
      (fields
        (field (name "DB_PART_NUMBER") "CAP000043701")
        (field (name "DB_VALUE") "100uF")
        (field (name "DB_TOLERANCE") "20%")
        (field (name "DB_VOLTAGE") "6.3V")
        (field (name "DB_MANUFACTURER_PART") "KEMET    C1210C107M9PAC")
        (field (name "DB_APPROVED_BY") "ISHIDDEN=T")
      )
      (libsource (lib "Database_Libs1") (part "C"))
    )
    (comp (ref "C135")
      (value "220uF")
      (footprint "SMD_1210_CAPC3225X279N")
      (fields
        (field (name "DB_PART_NUMBER") "CAP000047355")
        (field (name "DB_VALUE") "220uF")
        (field (name "DB_TOLERANCE") "20%")
        (field (name "DB_VOLTAGE") "6.3V")
        (field (name "DB_MANUFACTURER_PART") "SAMSUNG    CL32A227MQVNNNE")
        (field (name "DB_APPROVED_BY") "VSN")
      )
      (libsource (lib "Database_Libs1") (part "C"))
    )
    (comp (ref "C136")
      (value "220uF")
      (footprint "SMD_1210_CAPC3225X279N")
      (fields
        (field (name "DB_PART_NUMBER") "CAP000047355")
        (field (name "DB_VALUE") "220uF")
        (field (name "DB_TOLERANCE") "20%")
        (field (name "DB_VOLTAGE") "6.3V")
        (field (name "DB_MANUFACTURER_PART") "SAMSUNG    CL32A227MQVNNNE")
        (field (name "DB_APPROVED_BY") "VSN")
      )
      (libsource (lib "Database_Libs1") (part "C"))
    )
    (comp (ref "C137")
      (value "220uF")
      (footprint "SMD_1210_CAPC3225X279N")
      (fields
        (field (name "DB_PART_NUMBER") "CAP000047355")
        (field (name "DB_VALUE") "220uF")
        (field (name "DB_TOLERANCE") "20%")
        (field (name "DB_VOLTAGE") "6.3V")
        (field (name "DB_MANUFACTURER_PART") "SAMSUNG    CL32A227MQVNNNE")
        (field (name "DB_APPROVED_BY") "VSN")
      )
      (libsource (lib "Database_Libs1") (part "C"))
    )
    (comp (ref "C236")
      (value "220uF")
      (footprint "SMD_1210_CAPC3225X279N")
      (fields
        (field (name "DB_PART_NUMBER") "CAP000047355")
        (field (name "DB_VALUE") "220uF")
        (field (name "DB_TOLERANCE") "20%")
        (field (name "DB_VOLTAGE") "6.3V")
        (field (name "DB_MANUFACTURER_PART") "SAMSUNG    CL32A227MQVNNNE")
        (field (name "DB_APPROVED_BY") "VSN")
      )
      (libsource (lib "Database_Libs1") (part "C"))
    )
    (comp (ref "C323")
      (value "22uF")
      (footprint "SMD_0805_CAPC2012X145N")
      (fields
        (field (name "DB_PART_NUMBER") "CAP000043686")
        (field (name "DB_VALUE") "22uF")
        (field (name "DB_TOLERANCE") "20%")
        (field (name "DB_VOLTAGE") "6.3V")
        (field (name "DB_MANUFACTURER_PART") "KEMET    C0805C226M9PAC")
        (field (name "DB_APPROVED_BY") "ISHIDDEN=T")
      )
      (libsource (lib "Database_Libs1") (part "C"))
    )
    (comp (ref "C324")
      (value "22uF")
      (footprint "SMD_0805_CAPC2012X145N")
      (fields
        (field (name "DB_PART_NUMBER") "CAP000043686")
        (field (name "DB_VALUE") "22uF")
        (field (name "DB_TOLERANCE") "20%")
        (field (name "DB_VOLTAGE") "6.3V")
        (field (name "DB_MANUFACTURER_PART") "KEMET    C0805C226M9PAC")
        (field (name "DB_APPROVED_BY") "ISHIDDEN=T")
      )
      (libsource (lib "Database_Libs1") (part "C"))
    )
    (comp (ref "C325")
      (value "22uF")
      (footprint "SMD_0805_CAPC2012X145N")
      (fields
        (field (name "DB_PART_NUMBER") "CAP000043686")
        (field (name "DB_VALUE") "22uF")
        (field (name "DB_TOLERANCE") "20%")
        (field (name "DB_VOLTAGE") "6.3V")
        (field (name "DB_MANUFACTURER_PART") "KEMET    C0805C226M9PAC")
        (field (name "DB_APPROVED_BY") "ISHIDDEN=T")
      )
      (libsource (lib "Database_Libs1") (part "C"))
    )
    (comp (ref "C326")
      (value "22uF")
      (footprint "SMD_0805_CAPC2012X145N")
      (fields
        (field (name "DB_PART_NUMBER") "CAP000043686")
        (field (name "DB_VALUE") "22uF")
        (field (name "DB_TOLERANCE") "20%")
        (field (name "DB_VOLTAGE") "6.3V")
        (field (name "DB_MANUFACTURER_PART") "KEMET    C0805C226M9PAC")
        (field (name "DB_APPROVED_BY") "ISHIDDEN=T")
      )
      (libsource (lib "Database_Libs1") (part "C"))
    )
    (comp (ref "C327")
      (value "22uF")
      (footprint "SMD_0805_CAPC2012X145N")
      (fields
        (field (name "DB_PART_NUMBER") "CAP000043686")
        (field (name "DB_VALUE") "22uF")
        (field (name "DB_TOLERANCE") "20%")
        (field (name "DB_VOLTAGE") "6.3V")
        (field (name "DB_MANUFACTURER_PART") "KEMET    C0805C226M9PAC")
        (field (name "DB_APPROVED_BY") "ISHIDDEN=T")
      )
      (libsource (lib "Database_Libs1") (part "C"))
    )
    (comp (ref "C328")
      (value "22uF")
      (footprint "SMD_0805_CAPC2012X145N")
      (fields
        (field (name "DB_PART_NUMBER") "CAP000043686")
        (field (name "DB_VALUE") "22uF")
        (field (name "DB_TOLERANCE") "20%")
        (field (name "DB_VOLTAGE") "6.3V")
        (field (name "DB_MANUFACTURER_PART") "KEMET    C0805C226M9PAC")
        (field (name "DB_APPROVED_BY") "ISHIDDEN=T")
      )
      (libsource (lib "Database_Libs1") (part "C"))
    )
    (comp (ref "C329")
      (value "22uF")
      (footprint "SMD_0805_CAPC2012X145N")
      (fields
        (field (name "DB_PART_NUMBER") "CAP000043686")
        (field (name "DB_VALUE") "22uF")
        (field (name "DB_TOLERANCE") "20%")
        (field (name "DB_VOLTAGE") "6.3V")
        (field (name "DB_MANUFACTURER_PART") "KEMET    C0805C226M9PAC")
        (field (name "DB_APPROVED_BY") "ISHIDDEN=T")
      )
      (libsource (lib "Database_Libs1") (part "C"))
    )
    (comp (ref "C330")
      (value "22uF")
      (footprint "SMD_0805_CAPC2012X145N")
      (fields
        (field (name "DB_PART_NUMBER") "CAP000043686")
        (field (name "DB_VALUE") "22uF")
        (field (name "DB_TOLERANCE") "20%")
        (field (name "DB_VOLTAGE") "6.3V")
        (field (name "DB_MANUFACTURER_PART") "KEMET    C0805C226M9PAC")
        (field (name "DB_APPROVED_BY") "ISHIDDEN=T")
      )
      (libsource (lib "Database_Libs1") (part "C"))
    )
    (comp (ref "C331")
      (value "22uF")
      (footprint "SMD_0805_CAPC2012X145N")
      (fields
        (field (name "DB_PART_NUMBER") "CAP000043686")
        (field (name "DB_VALUE") "22uF")
        (field (name "DB_TOLERANCE") "20%")
        (field (name "DB_VOLTAGE") "6.3V")
        (field (name "DB_MANUFACTURER_PART") "KEMET    C0805C226M9PAC")
        (field (name "DB_APPROVED_BY") "ISHIDDEN=T")
      )
      (libsource (lib "Database_Libs1") (part "C"))
    )
    (comp (ref "C332")
      (value "22uF")
      (footprint "SMD_0805_CAPC2012X145N")
      (fields
        (field (name "DB_PART_NUMBER") "CAP000043686")
        (field (name "DB_VALUE") "22uF")
        (field (name "DB_TOLERANCE") "20%")
        (field (name "DB_VOLTAGE") "6.3V")
        (field (name "DB_MANUFACTURER_PART") "KEMET    C0805C226M9PAC")
        (field (name "DB_APPROVED_BY") "ISHIDDEN=T")
      )
      (libsource (lib "Database_Libs1") (part "C"))
    )
    (comp (ref "C333")
      (value "22uF")
      (footprint "SMD_0805_CAPC2012X145N")
      (fields
        (field (name "DB_PART_NUMBER") "CAP000043686")
        (field (name "DB_VALUE") "22uF")
        (field (name "DB_TOLERANCE") "20%")
        (field (name "DB_VOLTAGE") "6.3V")
        (field (name "DB_MANUFACTURER_PART") "KEMET    C0805C226M9PAC")
        (field (name "DB_APPROVED_BY") "ISHIDDEN=T")
      )
      (libsource (lib "Database_Libs1") (part "C"))
    )
    (comp (ref "C334")
      (value "22uF")
      (footprint "SMD_0805_CAPC2012X145N")
      (fields
        (field (name "DB_PART_NUMBER") "CAP000043686")
        (field (name "DB_VALUE") "22uF")
        (field (name "DB_TOLERANCE") "20%")
        (field (name "DB_VOLTAGE") "6.3V")
        (field (name "DB_MANUFACTURER_PART") "KEMET    C0805C226M9PAC")
        (field (name "DB_APPROVED_BY") "ISHIDDEN=T")
      )
      (libsource (lib "Database_Libs1") (part "C"))
    )
    (comp (ref "C335")
      (value "22uF")
      (footprint "SMD_0805_CAPC2012X145N")
      (fields
        (field (name "DB_PART_NUMBER") "CAP000043686")
        (field (name "DB_VALUE") "22uF")
        (field (name "DB_TOLERANCE") "20%")
        (field (name "DB_VOLTAGE") "6.3V")
        (field (name "DB_MANUFACTURER_PART") "KEMET    C0805C226M9PAC")
        (field (name "DB_APPROVED_BY") "ISHIDDEN=T")
      )
      (libsource (lib "Database_Libs1") (part "C"))
    )
    (comp (ref "C336")
      (value "22uF")
      (footprint "SMD_0805_CAPC2012X145N")
      (fields
        (field (name "DB_PART_NUMBER") "CAP000043686")
        (field (name "DB_VALUE") "22uF")
        (field (name "DB_TOLERANCE") "20%")
        (field (name "DB_VOLTAGE") "6.3V")
        (field (name "DB_MANUFACTURER_PART") "KEMET    C0805C226M9PAC")
        (field (name "DB_APPROVED_BY") "ISHIDDEN=T")
      )
      (libsource (lib "Database_Libs1") (part "C"))
    )
    (comp (ref "C337")
      (value "22uF")
      (footprint "SMD_0805_CAPC2012X145N")
      (fields
        (field (name "DB_PART_NUMBER") "CAP000043686")
        (field (name "DB_VALUE") "22uF")
        (field (name "DB_TOLERANCE") "20%")
        (field (name "DB_VOLTAGE") "6.3V")
        (field (name "DB_MANUFACTURER_PART") "KEMET    C0805C226M9PAC")
        (field (name "DB_APPROVED_BY") "ISHIDDEN=T")
      )
      (libsource (lib "Database_Libs1") (part "C"))
    )
    (comp (ref "C338")
      (value "22uF")
      (footprint "SMD_0805_CAPC2012X145N")
      (fields
        (field (name "DB_PART_NUMBER") "CAP000043686")
        (field (name "DB_VALUE") "22uF")
        (field (name "DB_TOLERANCE") "20%")
        (field (name "DB_VOLTAGE") "6.3V")
        (field (name "DB_MANUFACTURER_PART") "KEMET    C0805C226M9PAC")
        (field (name "DB_APPROVED_BY") "ISHIDDEN=T")
      )
      (libsource (lib "Database_Libs1") (part "C"))
    )
    (comp (ref "C339")
      (value "22uF")
      (footprint "SMD_0805_CAPC2012X145N")
      (fields
        (field (name "DB_PART_NUMBER") "CAP000043686")
        (field (name "DB_VALUE") "22uF")
        (field (name "DB_TOLERANCE") "20%")
        (field (name "DB_VOLTAGE") "6.3V")
        (field (name "DB_MANUFACTURER_PART") "KEMET    C0805C226M9PAC")
        (field (name "DB_APPROVED_BY") "ISHIDDEN=T")
      )
      (libsource (lib "Database_Libs1") (part "C"))
    )
    (comp (ref "C340")
      (value "22uF")
      (footprint "SMD_0805_CAPC2012X145N")
      (fields
        (field (name "DB_PART_NUMBER") "CAP000043686")
        (field (name "DB_VALUE") "22uF")
        (field (name "DB_TOLERANCE") "20%")
        (field (name "DB_VOLTAGE") "6.3V")
        (field (name "DB_MANUFACTURER_PART") "KEMET    C0805C226M9PAC")
        (field (name "DB_APPROVED_BY") "ISHIDDEN=T")
      )
      (libsource (lib "Database_Libs1") (part "C"))
    )
    (comp (ref "C341")
      (value "22uF")
      (footprint "SMD_0805_CAPC2012X145N")
      (fields
        (field (name "DB_PART_NUMBER") "CAP000043686")
        (field (name "DB_VALUE") "22uF")
        (field (name "DB_TOLERANCE") "20%")
        (field (name "DB_VOLTAGE") "6.3V")
        (field (name "DB_MANUFACTURER_PART") "KEMET    C0805C226M9PAC")
        (field (name "DB_APPROVED_BY") "ISHIDDEN=T")
      )
      (libsource (lib "Database_Libs1") (part "C"))
    )
    (comp (ref "C342")
      (value "22uF")
      (footprint "SMD_0805_CAPC2012X145N")
      (fields
        (field (name "DB_PART_NUMBER") "CAP000043686")
        (field (name "DB_VALUE") "22uF")
        (field (name "DB_TOLERANCE") "20%")
        (field (name "DB_VOLTAGE") "6.3V")
        (field (name "DB_MANUFACTURER_PART") "KEMET    C0805C226M9PAC")
        (field (name "DB_APPROVED_BY") "ISHIDDEN=T")
      )
      (libsource (lib "Database_Libs1") (part "C"))
    )
    (comp (ref "C343")
      (value "22uF")
      (footprint "SMD_0805_CAPC2012X145N")
      (fields
        (field (name "DB_PART_NUMBER") "CAP000043686")
        (field (name "DB_VALUE") "22uF")
        (field (name "DB_TOLERANCE") "20%")
        (field (name "DB_VOLTAGE") "6.3V")
        (field (name "DB_MANUFACTURER_PART") "KEMET    C0805C226M9PAC")
        (field (name "DB_APPROVED_BY") "ISHIDDEN=T")
      )
      (libsource (lib "Database_Libs1") (part "C"))
    )
    (comp (ref "C344")
      (value "22uF")
      (footprint "SMD_0805_CAPC2012X145N")
      (fields
        (field (name "DB_PART_NUMBER") "CAP000043686")
        (field (name "DB_VALUE") "22uF")
        (field (name "DB_TOLERANCE") "20%")
        (field (name "DB_VOLTAGE") "6.3V")
        (field (name "DB_MANUFACTURER_PART") "KEMET    C0805C226M9PAC")
        (field (name "DB_APPROVED_BY") "ISHIDDEN=T")
      )
      (libsource (lib "Database_Libs1") (part "C"))
    )
    (comp (ref "C345")
      (value "22uF")
      (footprint "SMD_0805_CAPC2012X145N")
      (fields
        (field (name "DB_PART_NUMBER") "CAP000043686")
        (field (name "DB_VALUE") "22uF")
        (field (name "DB_TOLERANCE") "20%")
        (field (name "DB_VOLTAGE") "6.3V")
        (field (name "DB_MANUFACTURER_PART") "KEMET    C0805C226M9PAC")
        (field (name "DB_APPROVED_BY") "ISHIDDEN=T")
      )
      (libsource (lib "Database_Libs1") (part "C"))
    )
    (comp (ref "C346")
      (value "22uF")
      (footprint "SMD_0805_CAPC2012X145N")
      (fields
        (field (name "DB_PART_NUMBER") "CAP000043686")
        (field (name "DB_VALUE") "22uF")
        (field (name "DB_TOLERANCE") "20%")
        (field (name "DB_VOLTAGE") "6.3V")
        (field (name "DB_MANUFACTURER_PART") "KEMET    C0805C226M9PAC")
        (field (name "DB_APPROVED_BY") "ISHIDDEN=T")
      )
      (libsource (lib "Database_Libs1") (part "C"))
    )
    (comp (ref "C348")
      (value "100uF")
      (footprint "SMD_1210_CAPC3225X270N")
      (fields
        (field (name "DB_PART_NUMBER") "CAP000043701")
        (field (name "DB_VALUE") "100uF")
        (field (name "DB_TOLERANCE") "20%")
        (field (name "DB_VOLTAGE") "6.3V")
        (field (name "DB_MANUFACTURER_PART") "KEMET    C1210C107M9PAC")
        (field (name "DB_APPROVED_BY") "ISHIDDEN=T")
      )
      (libsource (lib "Database_Libs1") (part "C"))
    )
    (comp (ref "C349")
      (value "100uF")
      (footprint "SMD_1210_CAPC3225X270N")
      (fields
        (field (name "DB_PART_NUMBER") "CAP000043701")
        (field (name "DB_VALUE") "100uF")
        (field (name "DB_TOLERANCE") "20%")
        (field (name "DB_VOLTAGE") "6.3V")
        (field (name "DB_MANUFACTURER_PART") "KEMET    C1210C107M9PAC")
        (field (name "DB_APPROVED_BY") "ISHIDDEN=T")
      )
      (libsource (lib "Database_Libs1") (part "C"))
    )
    (comp (ref "C350")
      (value "220uF")
      (footprint "SMD_1210_CAPC3225X279N")
      (fields
        (field (name "DB_PART_NUMBER") "CAP000047355")
        (field (name "DB_VALUE") "220uF")
        (field (name "DB_TOLERANCE") "20%")
        (field (name "DB_VOLTAGE") "6.3V")
        (field (name "DB_MANUFACTURER_PART") "SAMSUNG    CL32A227MQVNNNE")
        (field (name "DB_APPROVED_BY") "VSN")
      )
      (libsource (lib "Database_Libs1") (part "C"))
    )
    (comp (ref "C351")
      (value "220uF")
      (footprint "SMD_1210_CAPC3225X279N")
      (fields
        (field (name "DB_PART_NUMBER") "CAP000047355")
        (field (name "DB_VALUE") "220uF")
        (field (name "DB_TOLERANCE") "20%")
        (field (name "DB_VOLTAGE") "6.3V")
        (field (name "DB_MANUFACTURER_PART") "SAMSUNG    CL32A227MQVNNNE")
        (field (name "DB_APPROVED_BY") "VSN")
      )
      (libsource (lib "Database_Libs1") (part "C"))
    )
    (comp (ref "C352")
      (value "220uF")
      (footprint "SMD_1210_CAPC3225X279N")
      (fields
        (field (name "DB_PART_NUMBER") "CAP000047355")
        (field (name "DB_VALUE") "220uF")
        (field (name "DB_TOLERANCE") "20%")
        (field (name "DB_VOLTAGE") "6.3V")
        (field (name "DB_MANUFACTURER_PART") "SAMSUNG    CL32A227MQVNNNE")
        (field (name "DB_APPROVED_BY") "VSN")
      )
      (libsource (lib "Database_Libs1") (part "C"))
    )
    (comp (ref "C353")
      (value "22uF")
      (footprint "SMD_0805_CAPC2012X145N")
      (fields
        (field (name "DB_PART_NUMBER") "CAP000043686")
        (field (name "DB_VALUE") "22uF")
        (field (name "DB_TOLERANCE") "20%")
        (field (name "DB_VOLTAGE") "6.3V")
        (field (name "DB_MANUFACTURER_PART") "KEMET    C0805C226M9PAC")
        (field (name "DB_APPROVED_BY") "ISHIDDEN=T")
      )
      (libsource (lib "Database_Libs1") (part "C"))
    )
    (comp (ref "C354")
      (value "22uF")
      (footprint "SMD_0805_CAPC2012X145N")
      (fields
        (field (name "DB_PART_NUMBER") "CAP000043686")
        (field (name "DB_VALUE") "22uF")
        (field (name "DB_TOLERANCE") "20%")
        (field (name "DB_VOLTAGE") "6.3V")
        (field (name "DB_MANUFACTURER_PART") "KEMET    C0805C226M9PAC")
        (field (name "DB_APPROVED_BY") "ISHIDDEN=T")
      )
      (libsource (lib "Database_Libs1") (part "C"))
    )
    (comp (ref "C355")
      (value "22uF")
      (footprint "SMD_0805_CAPC2012X145N")
      (fields
        (field (name "DB_PART_NUMBER") "CAP000043686")
        (field (name "DB_VALUE") "22uF")
        (field (name "DB_TOLERANCE") "20%")
        (field (name "DB_VOLTAGE") "6.3V")
        (field (name "DB_MANUFACTURER_PART") "KEMET    C0805C226M9PAC")
        (field (name "DB_APPROVED_BY") "ISHIDDEN=T")
      )
      (libsource (lib "Database_Libs1") (part "C"))
    )
    (comp (ref "C356")
      (value "22uF")
      (footprint "SMD_0805_CAPC2012X145N")
      (fields
        (field (name "DB_PART_NUMBER") "CAP000043686")
        (field (name "DB_VALUE") "22uF")
        (field (name "DB_TOLERANCE") "20%")
        (field (name "DB_VOLTAGE") "6.3V")
        (field (name "DB_MANUFACTURER_PART") "KEMET    C0805C226M9PAC")
        (field (name "DB_APPROVED_BY") "ISHIDDEN=T")
      )
      (libsource (lib "Database_Libs1") (part "C"))
    )
    (comp (ref "C357")
      (value "22uF")
      (footprint "SMD_0805_CAPC2012X145N")
      (fields
        (field (name "DB_PART_NUMBER") "CAP000043686")
        (field (name "DB_VALUE") "22uF")
        (field (name "DB_TOLERANCE") "20%")
        (field (name "DB_VOLTAGE") "6.3V")
        (field (name "DB_MANUFACTURER_PART") "KEMET    C0805C226M9PAC")
        (field (name "DB_APPROVED_BY") "ISHIDDEN=T")
      )
      (libsource (lib "Database_Libs1") (part "C"))
    )
    (comp (ref "C358")
      (value "22uF")
      (footprint "SMD_0805_CAPC2012X145N")
      (fields
        (field (name "DB_PART_NUMBER") "CAP000043686")
        (field (name "DB_VALUE") "22uF")
        (field (name "DB_TOLERANCE") "20%")
        (field (name "DB_VOLTAGE") "6.3V")
        (field (name "DB_MANUFACTURER_PART") "KEMET    C0805C226M9PAC")
        (field (name "DB_APPROVED_BY") "ISHIDDEN=T")
      )
      (libsource (lib "Database_Libs1") (part "C"))
    )
    (comp (ref "C359")
      (value "22uF")
      (footprint "SMD_0805_CAPC2012X145N")
      (fields
        (field (name "DB_PART_NUMBER") "CAP000043686")
        (field (name "DB_VALUE") "22uF")
        (field (name "DB_TOLERANCE") "20%")
        (field (name "DB_VOLTAGE") "6.3V")
        (field (name "DB_MANUFACTURER_PART") "KEMET    C0805C226M9PAC")
        (field (name "DB_APPROVED_BY") "ISHIDDEN=T")
      )
      (libsource (lib "Database_Libs1") (part "C"))
    )
    (comp (ref "C360")
      (value "22uF")
      (footprint "SMD_0805_CAPC2012X145N")
      (fields
        (field (name "DB_PART_NUMBER") "CAP000043686")
        (field (name "DB_VALUE") "22uF")
        (field (name "DB_TOLERANCE") "20%")
        (field (name "DB_VOLTAGE") "6.3V")
        (field (name "DB_MANUFACTURER_PART") "KEMET    C0805C226M9PAC")
        (field (name "DB_APPROVED_BY") "ISHIDDEN=T")
      )
      (libsource (lib "Database_Libs1") (part "C"))
    )
    (comp (ref "C361")
      (value "22uF")
      (footprint "SMD_0805_CAPC2012X145N")
      (fields
        (field (name "DB_PART_NUMBER") "CAP000043686")
        (field (name "DB_VALUE") "22uF")
        (field (name "DB_TOLERANCE") "20%")
        (field (name "DB_VOLTAGE") "6.3V")
        (field (name "DB_MANUFACTURER_PART") "KEMET    C0805C226M9PAC")
        (field (name "DB_APPROVED_BY") "ISHIDDEN=T")
      )
      (libsource (lib "Database_Libs1") (part "C"))
    )
    (comp (ref "C362")
      (value "22uF")
      (footprint "SMD_0805_CAPC2012X145N")
      (fields
        (field (name "DB_PART_NUMBER") "CAP000043686")
        (field (name "DB_VALUE") "22uF")
        (field (name "DB_TOLERANCE") "20%")
        (field (name "DB_VOLTAGE") "6.3V")
        (field (name "DB_MANUFACTURER_PART") "KEMET    C0805C226M9PAC")
        (field (name "DB_APPROVED_BY") "ISHIDDEN=T")
      )
      (libsource (lib "Database_Libs1") (part "C"))
    )
    (comp (ref "C363")
      (value "22uF")
      (footprint "SMD_0805_CAPC2012X145N")
      (fields
        (field (name "DB_PART_NUMBER") "CAP000043686")
        (field (name "DB_VALUE") "22uF")
        (field (name "DB_TOLERANCE") "20%")
        (field (name "DB_VOLTAGE") "6.3V")
        (field (name "DB_MANUFACTURER_PART") "KEMET    C0805C226M9PAC")
        (field (name "DB_APPROVED_BY") "ISHIDDEN=T")
      )
      (libsource (lib "Database_Libs1") (part "C"))
    )
    (comp (ref "C364")
      (value "22uF")
      (footprint "SMD_0805_CAPC2012X145N")
      (fields
        (field (name "DB_PART_NUMBER") "CAP000043686")
        (field (name "DB_VALUE") "22uF")
        (field (name "DB_TOLERANCE") "20%")
        (field (name "DB_VOLTAGE") "6.3V")
        (field (name "DB_MANUFACTURER_PART") "KEMET    C0805C226M9PAC")
        (field (name "DB_APPROVED_BY") "ISHIDDEN=T")
      )
      (libsource (lib "Database_Libs1") (part "C"))
    )
    (comp (ref "C365")
      (value "22uF")
      (footprint "SMD_0805_CAPC2012X145N")
      (fields
        (field (name "DB_PART_NUMBER") "CAP000043686")
        (field (name "DB_VALUE") "22uF")
        (field (name "DB_TOLERANCE") "20%")
        (field (name "DB_VOLTAGE") "6.3V")
        (field (name "DB_MANUFACTURER_PART") "KEMET    C0805C226M9PAC")
        (field (name "DB_APPROVED_BY") "ISHIDDEN=T")
      )
      (libsource (lib "Database_Libs1") (part "C"))
    )
    (comp (ref "C366")
      (value "22uF")
      (footprint "SMD_0805_CAPC2012X145N")
      (fields
        (field (name "DB_PART_NUMBER") "CAP000043686")
        (field (name "DB_VALUE") "22uF")
        (field (name "DB_TOLERANCE") "20%")
        (field (name "DB_VOLTAGE") "6.3V")
        (field (name "DB_MANUFACTURER_PART") "KEMET    C0805C226M9PAC")
        (field (name "DB_APPROVED_BY") "ISHIDDEN=T")
      )
      (libsource (lib "Database_Libs1") (part "C"))
    )
    (comp (ref "C367")
      (value "22uF")
      (footprint "SMD_0805_CAPC2012X145N")
      (fields
        (field (name "DB_PART_NUMBER") "CAP000043686")
        (field (name "DB_VALUE") "22uF")
        (field (name "DB_TOLERANCE") "20%")
        (field (name "DB_VOLTAGE") "6.3V")
        (field (name "DB_MANUFACTURER_PART") "KEMET    C0805C226M9PAC")
        (field (name "DB_APPROVED_BY") "ISHIDDEN=T")
      )
      (libsource (lib "Database_Libs1") (part "C"))
    )
    (comp (ref "C368")
      (value "22uF")
      (footprint "SMD_0805_CAPC2012X145N")
      (fields
        (field (name "DB_PART_NUMBER") "CAP000043686")
        (field (name "DB_VALUE") "22uF")
        (field (name "DB_TOLERANCE") "20%")
        (field (name "DB_VOLTAGE") "6.3V")
        (field (name "DB_MANUFACTURER_PART") "KEMET    C0805C226M9PAC")
        (field (name "DB_APPROVED_BY") "ISHIDDEN=T")
      )
      (libsource (lib "Database_Libs1") (part "C"))
    )
    (comp (ref "C369")
      (value "22uF")
      (footprint "SMD_0805_CAPC2012X145N")
      (fields
        (field (name "DB_PART_NUMBER") "CAP000043686")
        (field (name "DB_VALUE") "22uF")
        (field (name "DB_TOLERANCE") "20%")
        (field (name "DB_VOLTAGE") "6.3V")
        (field (name "DB_MANUFACTURER_PART") "KEMET    C0805C226M9PAC")
        (field (name "DB_APPROVED_BY") "ISHIDDEN=T")
      )
      (libsource (lib "Database_Libs1") (part "C"))
    )
    (comp (ref "C370")
      (value "22uF")
      (footprint "SMD_0805_CAPC2012X145N")
      (fields
        (field (name "DB_PART_NUMBER") "CAP000043686")
        (field (name "DB_VALUE") "22uF")
        (field (name "DB_TOLERANCE") "20%")
        (field (name "DB_VOLTAGE") "6.3V")
        (field (name "DB_MANUFACTURER_PART") "KEMET    C0805C226M9PAC")
        (field (name "DB_APPROVED_BY") "ISHIDDEN=T")
      )
      (libsource (lib "Database_Libs1") (part "C"))
    )
    (comp (ref "C371")
      (value "22uF")
      (footprint "SMD_0805_CAPC2012X145N")
      (fields
        (field (name "DB_PART_NUMBER") "CAP000043686")
        (field (name "DB_VALUE") "22uF")
        (field (name "DB_TOLERANCE") "20%")
        (field (name "DB_VOLTAGE") "6.3V")
        (field (name "DB_MANUFACTURER_PART") "KEMET    C0805C226M9PAC")
        (field (name "DB_APPROVED_BY") "ISHIDDEN=T")
      )
      (libsource (lib "Database_Libs1") (part "C"))
    )
    (comp (ref "C372")
      (value "22uF")
      (footprint "SMD_0805_CAPC2012X145N")
      (fields
        (field (name "DB_PART_NUMBER") "CAP000043686")
        (field (name "DB_VALUE") "22uF")
        (field (name "DB_TOLERANCE") "20%")
        (field (name "DB_VOLTAGE") "6.3V")
        (field (name "DB_MANUFACTURER_PART") "KEMET    C0805C226M9PAC")
        (field (name "DB_APPROVED_BY") "ISHIDDEN=T")
      )
      (libsource (lib "Database_Libs1") (part "C"))
    )
    (comp (ref "C373")
      (value "22uF")
      (footprint "SMD_0805_CAPC2012X145N")
      (fields
        (field (name "DB_PART_NUMBER") "CAP000043686")
        (field (name "DB_VALUE") "22uF")
        (field (name "DB_TOLERANCE") "20%")
        (field (name "DB_VOLTAGE") "6.3V")
        (field (name "DB_MANUFACTURER_PART") "KEMET    C0805C226M9PAC")
        (field (name "DB_APPROVED_BY") "ISHIDDEN=T")
      )
      (libsource (lib "Database_Libs1") (part "C"))
    )
    (comp (ref "C374")
      (value "22uF")
      (footprint "SMD_0805_CAPC2012X145N")
      (fields
        (field (name "DB_PART_NUMBER") "CAP000043686")
        (field (name "DB_VALUE") "22uF")
        (field (name "DB_TOLERANCE") "20%")
        (field (name "DB_VOLTAGE") "6.3V")
        (field (name "DB_MANUFACTURER_PART") "KEMET    C0805C226M9PAC")
        (field (name "DB_APPROVED_BY") "ISHIDDEN=T")
      )
      (libsource (lib "Database_Libs1") (part "C"))
    )
    (comp (ref "C375")
      (value "22uF")
      (footprint "SMD_0805_CAPC2012X145N")
      (fields
        (field (name "DB_PART_NUMBER") "CAP000043686")
        (field (name "DB_VALUE") "22uF")
        (field (name "DB_TOLERANCE") "20%")
        (field (name "DB_VOLTAGE") "6.3V")
        (field (name "DB_MANUFACTURER_PART") "KEMET    C0805C226M9PAC")
        (field (name "DB_APPROVED_BY") "ISHIDDEN=T")
      )
      (libsource (lib "Database_Libs1") (part "C"))
    )
    (comp (ref "C376")
      (value "22uF")
      (footprint "SMD_0805_CAPC2012X145N")
      (fields
        (field (name "DB_PART_NUMBER") "CAP000043686")
        (field (name "DB_VALUE") "22uF")
        (field (name "DB_TOLERANCE") "20%")
        (field (name "DB_VOLTAGE") "6.3V")
        (field (name "DB_MANUFACTURER_PART") "KEMET    C0805C226M9PAC")
        (field (name "DB_APPROVED_BY") "ISHIDDEN=T")
      )
      (libsource (lib "Database_Libs1") (part "C"))
    )
    (comp (ref "C377")
      (value "10uF")
      (footprint "SMD_0805_CAPC2012X145N")
      (fields
        (field (name "DB_PART_NUMBER") "CAP000043636")
        (field (name "DB_VALUE") "10uF")
        (field (name "DB_TOLERANCE") "10%")
        (field (name "DB_VOLTAGE") "16V")
        (field (name "DB_MANUFACTURER_PART") "KEMET    C0805C106K4PAC")
        (field (name "DB_APPROVED_BY") "ISHIDDEN=T")
      )
      (libsource (lib "Database_Libs1") (part "C"))
    )
    (comp (ref "C378")
      (value "10uF")
      (footprint "SMD_0805_CAPC2012X145N")
      (fields
        (field (name "DB_PART_NUMBER") "CAP000043636")
        (field (name "DB_VALUE") "10uF")
        (field (name "DB_TOLERANCE") "10%")
        (field (name "DB_VOLTAGE") "16V")
        (field (name "DB_MANUFACTURER_PART") "KEMET    C0805C106K4PAC")
        (field (name "DB_APPROVED_BY") "ISHIDDEN=T")
      )
      (libsource (lib "Database_Libs1") (part "C"))
    )
    (comp (ref "C379")
      (value "10uF")
      (footprint "SMD_0805_CAPC2012X145N")
      (fields
        (field (name "DB_PART_NUMBER") "CAP000043636")
        (field (name "DB_VALUE") "10uF")
        (field (name "DB_TOLERANCE") "10%")
        (field (name "DB_VOLTAGE") "16V")
        (field (name "DB_MANUFACTURER_PART") "KEMET    C0805C106K4PAC")
        (field (name "DB_APPROVED_BY") "ISHIDDEN=T")
      )
      (libsource (lib "Database_Libs1") (part "C"))
    )
    (comp (ref "C380")
      (value "10uF")
      (footprint "SMD_0805_CAPC2012X145N")
      (fields
        (field (name "DB_PART_NUMBER") "CAP000043636")
        (field (name "DB_VALUE") "10uF")
        (field (name "DB_TOLERANCE") "10%")
        (field (name "DB_VOLTAGE") "16V")
        (field (name "DB_MANUFACTURER_PART") "KEMET    C0805C106K4PAC")
        (field (name "DB_APPROVED_BY") "ISHIDDEN=T")
      )
      (libsource (lib "Database_Libs1") (part "C"))
    )
    (comp (ref "C381")
      (value "10uF")
      (footprint "SMD_0805_CAPC2012X145N")
      (fields
        (field (name "DB_PART_NUMBER") "CAP000043636")
        (field (name "DB_VALUE") "10uF")
        (field (name "DB_TOLERANCE") "10%")
        (field (name "DB_VOLTAGE") "16V")
        (field (name "DB_MANUFACTURER_PART") "KEMET    C0805C106K4PAC")
        (field (name "DB_APPROVED_BY") "ISHIDDEN=T")
      )
      (libsource (lib "Database_Libs1") (part "C"))
    )
    (comp (ref "C382")
      (value "10uF")
      (footprint "SMD_0805_CAPC2012X145N")
      (fields
        (field (name "DB_PART_NUMBER") "CAP000043636")
        (field (name "DB_VALUE") "10uF")
        (field (name "DB_TOLERANCE") "10%")
        (field (name "DB_VOLTAGE") "16V")
        (field (name "DB_MANUFACTURER_PART") "KEMET    C0805C106K4PAC")
        (field (name "DB_APPROVED_BY") "ISHIDDEN=T")
      )
      (libsource (lib "Database_Libs1") (part "C"))
    )
    (comp (ref "C383")
      (value "10uF")
      (footprint "SMD_0805_CAPC2012X145N")
      (fields
        (field (name "DB_PART_NUMBER") "CAP000043636")
        (field (name "DB_VALUE") "10uF")
        (field (name "DB_TOLERANCE") "10%")
        (field (name "DB_VOLTAGE") "16V")
        (field (name "DB_MANUFACTURER_PART") "KEMET    C0805C106K4PAC")
        (field (name "DB_APPROVED_BY") "ISHIDDEN=T")
      )
      (libsource (lib "Database_Libs1") (part "C"))
    )
    (comp (ref "C384")
      (value "10uF")
      (footprint "SMD_0805_CAPC2012X145N")
      (fields
        (field (name "DB_PART_NUMBER") "CAP000043636")
        (field (name "DB_VALUE") "10uF")
        (field (name "DB_TOLERANCE") "10%")
        (field (name "DB_VOLTAGE") "16V")
        (field (name "DB_MANUFACTURER_PART") "KEMET    C0805C106K4PAC")
        (field (name "DB_APPROVED_BY") "ISHIDDEN=T")
      )
      (libsource (lib "Database_Libs1") (part "C"))
    )
    (comp (ref "C385")
      (value "10uF")
      (footprint "SMD_0805_CAPC2012X145N")
      (fields
        (field (name "DB_PART_NUMBER") "CAP000043636")
        (field (name "DB_VALUE") "10uF")
        (field (name "DB_TOLERANCE") "10%")
        (field (name "DB_VOLTAGE") "16V")
        (field (name "DB_MANUFACTURER_PART") "KEMET    C0805C106K4PAC")
        (field (name "DB_APPROVED_BY") "ISHIDDEN=T")
      )
      (libsource (lib "Database_Libs1") (part "C"))
    )
    (comp (ref "C386")
      (value "10uF")
      (footprint "SMD_0805_CAPC2012X145N")
      (fields
        (field (name "DB_PART_NUMBER") "CAP000043636")
        (field (name "DB_VALUE") "10uF")
        (field (name "DB_TOLERANCE") "10%")
        (field (name "DB_VOLTAGE") "16V")
        (field (name "DB_MANUFACTURER_PART") "KEMET    C0805C106K4PAC")
        (field (name "DB_APPROVED_BY") "ISHIDDEN=T")
      )
      (libsource (lib "Database_Libs1") (part "C"))
    )
    (comp (ref "C387")
      (value "10uF")
      (footprint "SMD_0805_CAPC2012X145N")
      (fields
        (field (name "DB_PART_NUMBER") "CAP000043636")
        (field (name "DB_VALUE") "10uF")
        (field (name "DB_TOLERANCE") "10%")
        (field (name "DB_VOLTAGE") "16V")
        (field (name "DB_MANUFACTURER_PART") "KEMET    C0805C106K4PAC")
        (field (name "DB_APPROVED_BY") "ISHIDDEN=T")
      )
      (libsource (lib "Database_Libs1") (part "C"))
    )
    (comp (ref "C388")
      (value "10uF")
      (footprint "SMD_0805_CAPC2012X145N")
      (fields
        (field (name "DB_PART_NUMBER") "CAP000043636")
        (field (name "DB_VALUE") "10uF")
        (field (name "DB_TOLERANCE") "10%")
        (field (name "DB_VOLTAGE") "16V")
        (field (name "DB_MANUFACTURER_PART") "KEMET    C0805C106K4PAC")
        (field (name "DB_APPROVED_BY") "ISHIDDEN=T")
      )
      (libsource (lib "Database_Libs1") (part "C"))
    )
    (comp (ref "C389")
      (value "10uF")
      (footprint "SMD_0805_CAPC2012X145N")
      (fields
        (field (name "DB_PART_NUMBER") "CAP000043636")
        (field (name "DB_VALUE") "10uF")
        (field (name "DB_TOLERANCE") "10%")
        (field (name "DB_VOLTAGE") "16V")
        (field (name "DB_MANUFACTURER_PART") "KEMET    C0805C106K4PAC")
        (field (name "DB_APPROVED_BY") "ISHIDDEN=T")
      )
      (libsource (lib "Database_Libs1") (part "C"))
    )
    (comp (ref "C390")
      (value "10uF")
      (footprint "SMD_0805_CAPC2012X145N")
      (fields
        (field (name "DB_PART_NUMBER") "CAP000043636")
        (field (name "DB_VALUE") "10uF")
        (field (name "DB_TOLERANCE") "10%")
        (field (name "DB_VOLTAGE") "16V")
        (field (name "DB_MANUFACTURER_PART") "KEMET    C0805C106K4PAC")
        (field (name "DB_APPROVED_BY") "ISHIDDEN=T")
      )
      (libsource (lib "Database_Libs1") (part "C"))
    )
    (comp (ref "C391")
      (value "10uF")
      (footprint "SMD_0805_CAPC2012X145N")
      (fields
        (field (name "DB_PART_NUMBER") "CAP000043636")
        (field (name "DB_VALUE") "10uF")
        (field (name "DB_TOLERANCE") "10%")
        (field (name "DB_VOLTAGE") "16V")
        (field (name "DB_MANUFACTURER_PART") "KEMET    C0805C106K4PAC")
        (field (name "DB_APPROVED_BY") "ISHIDDEN=T")
      )
      (libsource (lib "Database_Libs1") (part "C"))
    )
    (comp (ref "C392")
      (value "10uF")
      (footprint "SMD_0805_CAPC2012X145N")
      (fields
        (field (name "DB_PART_NUMBER") "CAP000043636")
        (field (name "DB_VALUE") "10uF")
        (field (name "DB_TOLERANCE") "10%")
        (field (name "DB_VOLTAGE") "16V")
        (field (name "DB_MANUFACTURER_PART") "KEMET    C0805C106K4PAC")
        (field (name "DB_APPROVED_BY") "ISHIDDEN=T")
      )
      (libsource (lib "Database_Libs1") (part "C"))
    )
    (comp (ref "C393")
      (value "220uF")
      (footprint "SMD_1210_CAPC3225X279N")
      (fields
        (field (name "DB_PART_NUMBER") "CAP000047355")
        (field (name "DB_VALUE") "220uF")
        (field (name "DB_TOLERANCE") "20%")
        (field (name "DB_VOLTAGE") "6.3V")
        (field (name "DB_MANUFACTURER_PART") "SAMSUNG    CL32A227MQVNNNE")
        (field (name "DB_APPROVED_BY") "VSN")
      )
      (libsource (lib "Database_Libs1") (part "C"))
    )
    (comp (ref "C394")
      (value "220uF")
      (footprint "SMD_1210_CAPC3225X279N")
      (fields
        (field (name "DB_PART_NUMBER") "CAP000047355")
        (field (name "DB_VALUE") "220uF")
        (field (name "DB_TOLERANCE") "20%")
        (field (name "DB_VOLTAGE") "6.3V")
        (field (name "DB_MANUFACTURER_PART") "SAMSUNG    CL32A227MQVNNNE")
        (field (name "DB_APPROVED_BY") "VSN")
      )
      (libsource (lib "Database_Libs1") (part "C"))
    )
    (comp (ref "C395")
      (value "220uF")
      (footprint "SMD_1210_CAPC3225X279N")
      (fields
        (field (name "DB_PART_NUMBER") "CAP000047355")
        (field (name "DB_VALUE") "220uF")
        (field (name "DB_TOLERANCE") "20%")
        (field (name "DB_VOLTAGE") "6.3V")
        (field (name "DB_MANUFACTURER_PART") "SAMSUNG    CL32A227MQVNNNE")
        (field (name "DB_APPROVED_BY") "VSN")
      )
      (libsource (lib "Database_Libs1") (part "C"))
    )
    (comp (ref "C396")
      (value "220uF")
      (footprint "SMD_1210_CAPC3225X279N")
      (fields
        (field (name "DB_PART_NUMBER") "CAP000047355")
        (field (name "DB_VALUE") "220uF")
        (field (name "DB_TOLERANCE") "20%")
        (field (name "DB_VOLTAGE") "6.3V")
        (field (name "DB_MANUFACTURER_PART") "SAMSUNG    CL32A227MQVNNNE")
        (field (name "DB_APPROVED_BY") "VSN")
      )
      (libsource (lib "Database_Libs1") (part "C"))
    )
    (comp (ref "C397")
      (value "220uF")
      (footprint "SMD_1210_CAPC3225X279N")
      (fields
        (field (name "DB_PART_NUMBER") "CAP000047355")
        (field (name "DB_VALUE") "220uF")
        (field (name "DB_TOLERANCE") "20%")
        (field (name "DB_VOLTAGE") "6.3V")
        (field (name "DB_MANUFACTURER_PART") "SAMSUNG    CL32A227MQVNNNE")
        (field (name "DB_APPROVED_BY") "VSN")
      )
      (libsource (lib "Database_Libs1") (part "C"))
    )
    (comp (ref "C398")
      (value "220uF")
      (footprint "SMD_1210_CAPC3225X279N")
      (fields
        (field (name "DB_PART_NUMBER") "CAP000047355")
        (field (name "DB_VALUE") "220uF")
        (field (name "DB_TOLERANCE") "20%")
        (field (name "DB_VOLTAGE") "6.3V")
        (field (name "DB_MANUFACTURER_PART") "SAMSUNG    CL32A227MQVNNNE")
        (field (name "DB_APPROVED_BY") "VSN")
      )
      (libsource (lib "Database_Libs1") (part "C"))
    )
    (comp (ref "C399")
      (value "220uF")
      (footprint "SMD_1210_CAPC3225X279N")
      (fields
        (field (name "DB_PART_NUMBER") "CAP000047355")
        (field (name "DB_VALUE") "220uF")
        (field (name "DB_TOLERANCE") "20%")
        (field (name "DB_VOLTAGE") "6.3V")
        (field (name "DB_MANUFACTURER_PART") "SAMSUNG    CL32A227MQVNNNE")
        (field (name "DB_APPROVED_BY") "VSN")
      )
      (libsource (lib "Database_Libs1") (part "C"))
    )
    (comp (ref "C400")
      (value "220uF")
      (footprint "SMD_1210_CAPC3225X279N")
      (fields
        (field (name "DB_PART_NUMBER") "CAP000047355")
        (field (name "DB_VALUE") "220uF")
        (field (name "DB_TOLERANCE") "20%")
        (field (name "DB_VOLTAGE") "6.3V")
        (field (name "DB_MANUFACTURER_PART") "SAMSUNG    CL32A227MQVNNNE")
        (field (name "DB_APPROVED_BY") "VSN")
      )
      (libsource (lib "Database_Libs1") (part "C"))
    )
    (comp (ref "C401")
      (value "220uF")
      (footprint "SMD_1210_CAPC3225X279N")
      (fields
        (field (name "DB_PART_NUMBER") "CAP000047355")
        (field (name "DB_VALUE") "220uF")
        (field (name "DB_TOLERANCE") "20%")
        (field (name "DB_VOLTAGE") "6.3V")
        (field (name "DB_MANUFACTURER_PART") "SAMSUNG    CL32A227MQVNNNE")
        (field (name "DB_APPROVED_BY") "VSN")
      )
      (libsource (lib "Database_Libs1") (part "C"))
    )
    (comp (ref "C402")
      (value "100uF")
      (footprint "SMD_1210_CAPC3225X270N")
      (fields
        (field (name "DB_PART_NUMBER") "CAP000043701")
        (field (name "DB_VALUE") "100uF")
        (field (name "DB_TOLERANCE") "20%")
        (field (name "DB_VOLTAGE") "6.3V")
        (field (name "DB_MANUFACTURER_PART") "KEMET    C1210C107M9PAC")
        (field (name "DB_APPROVED_BY") "ISHIDDEN=T")
      )
      (libsource (lib "Database_Libs1") (part "C"))
    )
    (comp (ref "C403")
      (value "100uF")
      (footprint "SMD_1210_CAPC3225X270N")
      (fields
        (field (name "DB_PART_NUMBER") "CAP000043701")
        (field (name "DB_VALUE") "100uF")
        (field (name "DB_TOLERANCE") "20%")
        (field (name "DB_VOLTAGE") "6.3V")
        (field (name "DB_MANUFACTURER_PART") "KEMET    C1210C107M9PAC")
        (field (name "DB_APPROVED_BY") "ISHIDDEN=T")
      )
      (libsource (lib "Database_Libs1") (part "C"))
    )
    (comp (ref "C404")
      (value "100uF")
      (footprint "SMD_1210_CAPC3225X270N")
      (fields
        (field (name "DB_PART_NUMBER") "CAP000043701")
        (field (name "DB_VALUE") "100uF")
        (field (name "DB_TOLERANCE") "20%")
        (field (name "DB_VOLTAGE") "6.3V")
        (field (name "DB_MANUFACTURER_PART") "KEMET    C1210C107M9PAC")
        (field (name "DB_APPROVED_BY") "ISHIDDEN=T")
      )
      (libsource (lib "Database_Libs1") (part "C"))
    )
    (comp (ref "C405")
      (value "100uF")
      (footprint "SMD_1210_CAPC3225X270N")
      (fields
        (field (name "DB_PART_NUMBER") "CAP000043701")
        (field (name "DB_VALUE") "100uF")
        (field (name "DB_TOLERANCE") "20%")
        (field (name "DB_VOLTAGE") "6.3V")
        (field (name "DB_MANUFACTURER_PART") "KEMET    C1210C107M9PAC")
        (field (name "DB_APPROVED_BY") "ISHIDDEN=T")
      )
      (libsource (lib "Database_Libs1") (part "C"))
    )
    (comp (ref "C406")
      (value "100uF")
      (footprint "SMD_1210_CAPC3225X270N")
      (fields
        (field (name "DB_PART_NUMBER") "CAP000043701")
        (field (name "DB_VALUE") "100uF")
        (field (name "DB_TOLERANCE") "20%")
        (field (name "DB_VOLTAGE") "6.3V")
        (field (name "DB_MANUFACTURER_PART") "KEMET    C1210C107M9PAC")
        (field (name "DB_APPROVED_BY") "ISHIDDEN=T")
      )
      (libsource (lib "Database_Libs1") (part "C"))
    )
    (comp (ref "C407")
      (value "100uF")
      (footprint "SMD_1210_CAPC3225X270N")
      (fields
        (field (name "DB_PART_NUMBER") "CAP000043701")
        (field (name "DB_VALUE") "100uF")
        (field (name "DB_TOLERANCE") "20%")
        (field (name "DB_VOLTAGE") "6.3V")
        (field (name "DB_MANUFACTURER_PART") "KEMET    C1210C107M9PAC")
        (field (name "DB_APPROVED_BY") "ISHIDDEN=T")
      )
      (libsource (lib "Database_Libs1") (part "C"))
    )
    (comp (ref "C408")
      (value "220uF")
      (footprint "SMD_1210_CAPC3225X279N")
      (fields
        (field (name "DB_PART_NUMBER") "CAP000047355")
        (field (name "DB_VALUE") "220uF")
        (field (name "DB_TOLERANCE") "20%")
        (field (name "DB_VOLTAGE") "6.3V")
        (field (name "DB_MANUFACTURER_PART") "SAMSUNG    CL32A227MQVNNNE")
        (field (name "DB_APPROVED_BY") "VSN")
      )
      (libsource (lib "Database_Libs1") (part "C"))
    )
    (comp (ref "C409")
      (value "220uF")
      (footprint "SMD_1210_CAPC3225X279N")
      (fields
        (field (name "DB_PART_NUMBER") "CAP000047355")
        (field (name "DB_VALUE") "220uF")
        (field (name "DB_TOLERANCE") "20%")
        (field (name "DB_VOLTAGE") "6.3V")
        (field (name "DB_MANUFACTURER_PART") "SAMSUNG    CL32A227MQVNNNE")
        (field (name "DB_APPROVED_BY") "VSN")
      )
      (libsource (lib "Database_Libs1") (part "C"))
    )
    (comp (ref "C410")
      (value "220uF")
      (footprint "SMD_1210_CAPC3225X279N")
      (fields
        (field (name "DB_PART_NUMBER") "CAP000047355")
        (field (name "DB_VALUE") "220uF")
        (field (name "DB_TOLERANCE") "20%")
        (field (name "DB_VOLTAGE") "6.3V")
        (field (name "DB_MANUFACTURER_PART") "SAMSUNG    CL32A227MQVNNNE")
        (field (name "DB_APPROVED_BY") "VSN")
      )
      (libsource (lib "Database_Libs1") (part "C"))
    )
    (comp (ref "C411")
      (value "220uF")
      (footprint "SMD_1210_CAPC3225X279N")
      (fields
        (field (name "DB_PART_NUMBER") "CAP000047355")
        (field (name "DB_VALUE") "220uF")
        (field (name "DB_TOLERANCE") "20%")
        (field (name "DB_VOLTAGE") "6.3V")
        (field (name "DB_MANUFACTURER_PART") "SAMSUNG    CL32A227MQVNNNE")
        (field (name "DB_APPROVED_BY") "VSN")
      )
      (libsource (lib "Database_Libs1") (part "C"))
    )
    (comp (ref "C412")
      (value "220uF")
      (footprint "SMD_1210_CAPC3225X279N")
      (fields
        (field (name "DB_PART_NUMBER") "CAP000047355")
        (field (name "DB_VALUE") "220uF")
        (field (name "DB_TOLERANCE") "20%")
        (field (name "DB_VOLTAGE") "6.3V")
        (field (name "DB_MANUFACTURER_PART") "SAMSUNG    CL32A227MQVNNNE")
        (field (name "DB_APPROVED_BY") "VSN")
      )
      (libsource (lib "Database_Libs1") (part "C"))
    )
    (comp (ref "C413")
      (value "220uF")
      (footprint "SMD_1210_CAPC3225X279N")
      (fields
        (field (name "DB_PART_NUMBER") "CAP000047355")
        (field (name "DB_VALUE") "220uF")
        (field (name "DB_TOLERANCE") "20%")
        (field (name "DB_VOLTAGE") "6.3V")
        (field (name "DB_MANUFACTURER_PART") "SAMSUNG    CL32A227MQVNNNE")
        (field (name "DB_APPROVED_BY") "VSN")
      )
      (libsource (lib "Database_Libs1") (part "C"))
    )
    (comp (ref "C414")
      (value "220uF")
      (footprint "SMD_1210_CAPC3225X279N")
      (fields
        (field (name "DB_PART_NUMBER") "CAP000047355")
        (field (name "DB_VALUE") "220uF")
        (field (name "DB_TOLERANCE") "20%")
        (field (name "DB_VOLTAGE") "6.3V")
        (field (name "DB_MANUFACTURER_PART") "SAMSUNG    CL32A227MQVNNNE")
        (field (name "DB_APPROVED_BY") "VSN")
      )
      (libsource (lib "Database_Libs1") (part "C"))
    )
    (comp (ref "C415")
      (value "220uF")
      (footprint "SMD_1210_CAPC3225X279N")
      (fields
        (field (name "DB_PART_NUMBER") "CAP000047355")
        (field (name "DB_VALUE") "220uF")
        (field (name "DB_TOLERANCE") "20%")
        (field (name "DB_VOLTAGE") "6.3V")
        (field (name "DB_MANUFACTURER_PART") "SAMSUNG    CL32A227MQVNNNE")
        (field (name "DB_APPROVED_BY") "VSN")
      )
      (libsource (lib "Database_Libs1") (part "C"))
    )
    (comp (ref "C416")
      (value "220uF")
      (footprint "SMD_1210_CAPC3225X279N")
      (fields
        (field (name "DB_PART_NUMBER") "CAP000047355")
        (field (name "DB_VALUE") "220uF")
        (field (name "DB_TOLERANCE") "20%")
        (field (name "DB_VOLTAGE") "6.3V")
        (field (name "DB_MANUFACTURER_PART") "SAMSUNG    CL32A227MQVNNNE")
        (field (name "DB_APPROVED_BY") "VSN")
      )
      (libsource (lib "Database_Libs1") (part "C"))
    )
    (comp (ref "C417")
      (value "220uF")
      (footprint "SMD_1210_CAPC3225X279N")
      (fields
        (field (name "DB_PART_NUMBER") "CAP000047355")
        (field (name "DB_VALUE") "220uF")
        (field (name "DB_TOLERANCE") "20%")
        (field (name "DB_VOLTAGE") "6.3V")
        (field (name "DB_MANUFACTURER_PART") "SAMSUNG    CL32A227MQVNNNE")
        (field (name "DB_APPROVED_BY") "VSN")
      )
      (libsource (lib "Database_Libs1") (part "C"))
    )
    (comp (ref "C418")
      (value "220uF")
      (footprint "SMD_1210_CAPC3225X279N")
      (fields
        (field (name "DB_PART_NUMBER") "CAP000047355")
        (field (name "DB_VALUE") "220uF")
        (field (name "DB_TOLERANCE") "20%")
        (field (name "DB_VOLTAGE") "6.3V")
        (field (name "DB_MANUFACTURER_PART") "SAMSUNG    CL32A227MQVNNNE")
        (field (name "DB_APPROVED_BY") "VSN")
      )
      (libsource (lib "Database_Libs1") (part "C"))
    )
    (comp (ref "C419")
      (value "220uF")
      (footprint "SMD_1210_CAPC3225X279N")
      (fields
        (field (name "DB_PART_NUMBER") "CAP000047355")
        (field (name "DB_VALUE") "220uF")
        (field (name "DB_TOLERANCE") "20%")
        (field (name "DB_VOLTAGE") "6.3V")
        (field (name "DB_MANUFACTURER_PART") "SAMSUNG    CL32A227MQVNNNE")
        (field (name "DB_APPROVED_BY") "VSN")
      )
      (libsource (lib "Database_Libs1") (part "C"))
    )
    (comp (ref "C420")
      (value "100uF")
      (footprint "SMD_1210_CAPC3225X270N")
      (fields
        (field (name "DB_PART_NUMBER") "CAP000043701")
        (field (name "DB_VALUE") "100uF")
        (field (name "DB_TOLERANCE") "20%")
        (field (name "DB_VOLTAGE") "6.3V")
        (field (name "DB_MANUFACTURER_PART") "KEMET    C1210C107M9PAC")
        (field (name "DB_APPROVED_BY") "ISHIDDEN=T")
      )
      (libsource (lib "Database_Libs1") (part "C"))
    )
    (comp (ref "C421")
      (value "100uF")
      (footprint "SMD_1210_CAPC3225X270N")
      (fields
        (field (name "DB_PART_NUMBER") "CAP000043701")
        (field (name "DB_VALUE") "100uF")
        (field (name "DB_TOLERANCE") "20%")
        (field (name "DB_VOLTAGE") "6.3V")
        (field (name "DB_MANUFACTURER_PART") "KEMET    C1210C107M9PAC")
        (field (name "DB_APPROVED_BY") "ISHIDDEN=T")
      )
      (libsource (lib "Database_Libs1") (part "C"))
    )
    (comp (ref "C422")
      (value "100uF")
      (footprint "SMD_1210_CAPC3225X270N")
      (fields
        (field (name "DB_PART_NUMBER") "CAP000043701")
        (field (name "DB_VALUE") "100uF")
        (field (name "DB_TOLERANCE") "20%")
        (field (name "DB_VOLTAGE") "6.3V")
        (field (name "DB_MANUFACTURER_PART") "KEMET    C1210C107M9PAC")
        (field (name "DB_APPROVED_BY") "ISHIDDEN=T")
      )
      (libsource (lib "Database_Libs1") (part "C"))
    )
    (comp (ref "C423")
      (value "100uF")
      (footprint "SMD_1210_CAPC3225X270N")
      (fields
        (field (name "DB_PART_NUMBER") "CAP000043701")
        (field (name "DB_VALUE") "100uF")
        (field (name "DB_TOLERANCE") "20%")
        (field (name "DB_VOLTAGE") "6.3V")
        (field (name "DB_MANUFACTURER_PART") "KEMET    C1210C107M9PAC")
        (field (name "DB_APPROVED_BY") "ISHIDDEN=T")
      )
      (libsource (lib "Database_Libs1") (part "C"))
    )
    (comp (ref "C424")
      (value "100uF")
      (footprint "SMD_1210_CAPC3225X270N")
      (fields
        (field (name "DB_PART_NUMBER") "CAP000043701")
        (field (name "DB_VALUE") "100uF")
        (field (name "DB_TOLERANCE") "20%")
        (field (name "DB_VOLTAGE") "6.3V")
        (field (name "DB_MANUFACTURER_PART") "KEMET    C1210C107M9PAC")
        (field (name "DB_APPROVED_BY") "ISHIDDEN=T")
      )
      (libsource (lib "Database_Libs1") (part "C"))
    )
    (comp (ref "C425")
      (value "100uF")
      (footprint "SMD_1210_CAPC3225X270N")
      (fields
        (field (name "DB_PART_NUMBER") "CAP000043701")
        (field (name "DB_VALUE") "100uF")
        (field (name "DB_TOLERANCE") "20%")
        (field (name "DB_VOLTAGE") "6.3V")
        (field (name "DB_MANUFACTURER_PART") "KEMET    C1210C107M9PAC")
        (field (name "DB_APPROVED_BY") "ISHIDDEN=T")
      )
      (libsource (lib "Database_Libs1") (part "C"))
    )
    (comp (ref "C426")
      (value "100uF")
      (footprint "SMD_1210_CAPC3225X270N")
      (fields
        (field (name "DB_PART_NUMBER") "CAP000043701")
        (field (name "DB_VALUE") "100uF")
        (field (name "DB_TOLERANCE") "20%")
        (field (name "DB_VOLTAGE") "6.3V")
        (field (name "DB_MANUFACTURER_PART") "KEMET    C1210C107M9PAC")
        (field (name "DB_APPROVED_BY") "ISHIDDEN=T")
      )
      (libsource (lib "Database_Libs1") (part "C"))
    )
    (comp (ref "C427")
      (value "100uF")
      (footprint "SMD_1210_CAPC3225X270N")
      (fields
        (field (name "DB_PART_NUMBER") "CAP000043701")
        (field (name "DB_VALUE") "100uF")
        (field (name "DB_TOLERANCE") "20%")
        (field (name "DB_VOLTAGE") "6.3V")
        (field (name "DB_MANUFACTURER_PART") "KEMET    C1210C107M9PAC")
        (field (name "DB_APPROVED_BY") "ISHIDDEN=T")
      )
      (libsource (lib "Database_Libs1") (part "C"))
    )
    (comp (ref "C428")
      (value "10uF")
      (footprint "SMD_0805_CAPC2012X145N")
      (fields
        (field (name "DB_PART_NUMBER") "CAP000043636")
        (field (name "DB_VALUE") "10uF")
        (field (name "DB_TOLERANCE") "10%")
        (field (name "DB_VOLTAGE") "16V")
        (field (name "DB_MANUFACTURER_PART") "KEMET    C0805C106K4PAC")
        (field (name "DB_APPROVED_BY") "ISHIDDEN=T")
      )
      (libsource (lib "Database_Libs1") (part "C"))
    )
    (comp (ref "C429")
      (value "10uF")
      (footprint "SMD_0805_CAPC2012X145N")
      (fields
        (field (name "DB_PART_NUMBER") "CAP000043636")
        (field (name "DB_VALUE") "10uF")
        (field (name "DB_TOLERANCE") "10%")
        (field (name "DB_VOLTAGE") "16V")
        (field (name "DB_MANUFACTURER_PART") "KEMET    C0805C106K4PAC")
        (field (name "DB_APPROVED_BY") "ISHIDDEN=T")
      )
      (libsource (lib "Database_Libs1") (part "C"))
    )
    (comp (ref "C430")
      (value "10uF")
      (footprint "SMD_0805_CAPC2012X145N")
      (fields
        (field (name "DB_PART_NUMBER") "CAP000043636")
        (field (name "DB_VALUE") "10uF")
        (field (name "DB_TOLERANCE") "10%")
        (field (name "DB_VOLTAGE") "16V")
        (field (name "DB_MANUFACTURER_PART") "KEMET    C0805C106K4PAC")
        (field (name "DB_APPROVED_BY") "ISHIDDEN=T")
      )
      (libsource (lib "Database_Libs1") (part "C"))
    )
    (comp (ref "C431")
      (value "10uF")
      (footprint "SMD_0805_CAPC2012X145N")
      (fields
        (field (name "DB_PART_NUMBER") "CAP000043636")
        (field (name "DB_VALUE") "10uF")
        (field (name "DB_TOLERANCE") "10%")
        (field (name "DB_VOLTAGE") "16V")
        (field (name "DB_MANUFACTURER_PART") "KEMET    C0805C106K4PAC")
        (field (name "DB_APPROVED_BY") "ISHIDDEN=T")
      )
      (libsource (lib "Database_Libs1") (part "C"))
    )
    (comp (ref "C432")
      (value "10uF")
      (footprint "SMD_0805_CAPC2012X145N")
      (fields
        (field (name "DB_PART_NUMBER") "CAP000043636")
        (field (name "DB_VALUE") "10uF")
        (field (name "DB_TOLERANCE") "10%")
        (field (name "DB_VOLTAGE") "16V")
        (field (name "DB_MANUFACTURER_PART") "KEMET    C0805C106K4PAC")
        (field (name "DB_APPROVED_BY") "ISHIDDEN=T")
      )
      (libsource (lib "Database_Libs1") (part "C"))
    )
    (comp (ref "C433")
      (value "10uF")
      (footprint "SMD_0805_CAPC2012X145N")
      (fields
        (field (name "DB_PART_NUMBER") "CAP000043636")
        (field (name "DB_VALUE") "10uF")
        (field (name "DB_TOLERANCE") "10%")
        (field (name "DB_VOLTAGE") "16V")
        (field (name "DB_MANUFACTURER_PART") "KEMET    C0805C106K4PAC")
        (field (name "DB_APPROVED_BY") "ISHIDDEN=T")
      )
      (libsource (lib "Database_Libs1") (part "C"))
    )
    (comp (ref "C434")
      (value "10uF")
      (footprint "SMD_0805_CAPC2012X145N")
      (fields
        (field (name "DB_PART_NUMBER") "CAP000043636")
        (field (name "DB_VALUE") "10uF")
        (field (name "DB_TOLERANCE") "10%")
        (field (name "DB_VOLTAGE") "16V")
        (field (name "DB_MANUFACTURER_PART") "KEMET    C0805C106K4PAC")
        (field (name "DB_APPROVED_BY") "ISHIDDEN=T")
      )
      (libsource (lib "Database_Libs1") (part "C"))
    )
    (comp (ref "C435")
      (value "10uF")
      (footprint "SMD_0805_CAPC2012X145N")
      (fields
        (field (name "DB_PART_NUMBER") "CAP000043636")
        (field (name "DB_VALUE") "10uF")
        (field (name "DB_TOLERANCE") "10%")
        (field (name "DB_VOLTAGE") "16V")
        (field (name "DB_MANUFACTURER_PART") "KEMET    C0805C106K4PAC")
        (field (name "DB_APPROVED_BY") "ISHIDDEN=T")
      )
      (libsource (lib "Database_Libs1") (part "C"))
    )
    (comp (ref "C436")
      (value "10uF")
      (footprint "SMD_0805_CAPC2012X145N")
      (fields
        (field (name "DB_PART_NUMBER") "CAP000043636")
        (field (name "DB_VALUE") "10uF")
        (field (name "DB_TOLERANCE") "10%")
        (field (name "DB_VOLTAGE") "16V")
        (field (name "DB_MANUFACTURER_PART") "KEMET    C0805C106K4PAC")
        (field (name "DB_APPROVED_BY") "ISHIDDEN=T")
      )
      (libsource (lib "Database_Libs1") (part "C"))
    )
    (comp (ref "C437")
      (value "10uF")
      (footprint "SMD_0805_CAPC2012X145N")
      (fields
        (field (name "DB_PART_NUMBER") "CAP000043636")
        (field (name "DB_VALUE") "10uF")
        (field (name "DB_TOLERANCE") "10%")
        (field (name "DB_VOLTAGE") "16V")
        (field (name "DB_MANUFACTURER_PART") "KEMET    C0805C106K4PAC")
        (field (name "DB_APPROVED_BY") "ISHIDDEN=T")
      )
      (libsource (lib "Database_Libs1") (part "C"))
    )
    (comp (ref "C438")
      (value "10uF")
      (footprint "SMD_0805_CAPC2012X145N")
      (fields
        (field (name "DB_PART_NUMBER") "CAP000043636")
        (field (name "DB_VALUE") "10uF")
        (field (name "DB_TOLERANCE") "10%")
        (field (name "DB_VOLTAGE") "16V")
        (field (name "DB_MANUFACTURER_PART") "KEMET    C0805C106K4PAC")
        (field (name "DB_APPROVED_BY") "ISHIDDEN=T")
      )
      (libsource (lib "Database_Libs1") (part "C"))
    )
    (comp (ref "C439")
      (value "10uF")
      (footprint "SMD_0805_CAPC2012X145N")
      (fields
        (field (name "DB_PART_NUMBER") "CAP000043636")
        (field (name "DB_VALUE") "10uF")
        (field (name "DB_TOLERANCE") "10%")
        (field (name "DB_VOLTAGE") "16V")
        (field (name "DB_MANUFACTURER_PART") "KEMET    C0805C106K4PAC")
        (field (name "DB_APPROVED_BY") "ISHIDDEN=T")
      )
      (libsource (lib "Database_Libs1") (part "C"))
    )
    (comp (ref "C440")
      (value "10uF")
      (footprint "SMD_0805_CAPC2012X145N")
      (fields
        (field (name "DB_PART_NUMBER") "CAP000043636")
        (field (name "DB_VALUE") "10uF")
        (field (name "DB_TOLERANCE") "10%")
        (field (name "DB_VOLTAGE") "16V")
        (field (name "DB_MANUFACTURER_PART") "KEMET    C0805C106K4PAC")
        (field (name "DB_APPROVED_BY") "ISHIDDEN=T")
      )
      (libsource (lib "Database_Libs1") (part "C"))
    )
    (comp (ref "C441")
      (value "10uF")
      (footprint "SMD_0805_CAPC2012X145N")
      (fields
        (field (name "DB_PART_NUMBER") "CAP000043636")
        (field (name "DB_VALUE") "10uF")
        (field (name "DB_TOLERANCE") "10%")
        (field (name "DB_VOLTAGE") "16V")
        (field (name "DB_MANUFACTURER_PART") "KEMET    C0805C106K4PAC")
        (field (name "DB_APPROVED_BY") "ISHIDDEN=T")
      )
      (libsource (lib "Database_Libs1") (part "C"))
    )
    (comp (ref "C442")
      (value "10uF")
      (footprint "SMD_0805_CAPC2012X145N")
      (fields
        (field (name "DB_PART_NUMBER") "CAP000043636")
        (field (name "DB_VALUE") "10uF")
        (field (name "DB_TOLERANCE") "10%")
        (field (name "DB_VOLTAGE") "16V")
        (field (name "DB_MANUFACTURER_PART") "KEMET    C0805C106K4PAC")
        (field (name "DB_APPROVED_BY") "ISHIDDEN=T")
      )
      (libsource (lib "Database_Libs1") (part "C"))
    )
    (comp (ref "C443")
      (value "10uF")
      (footprint "SMD_0805_CAPC2012X145N")
      (fields
        (field (name "DB_PART_NUMBER") "CAP000043636")
        (field (name "DB_VALUE") "10uF")
        (field (name "DB_TOLERANCE") "10%")
        (field (name "DB_VOLTAGE") "16V")
        (field (name "DB_MANUFACTURER_PART") "KEMET    C0805C106K4PAC")
        (field (name "DB_APPROVED_BY") "ISHIDDEN=T")
      )
      (libsource (lib "Database_Libs1") (part "C"))
    )
    (comp (ref "C444")
      (value "22uF")
      (footprint "SMD_0805_CAPC2012X145N")
      (fields
        (field (name "DB_PART_NUMBER") "CAP000043686")
        (field (name "DB_VALUE") "22uF")
        (field (name "DB_TOLERANCE") "20%")
        (field (name "DB_VOLTAGE") "6.3V")
        (field (name "DB_MANUFACTURER_PART") "KEMET    C0805C226M9PAC")
        (field (name "DB_APPROVED_BY") "ISHIDDEN=T")
      )
      (libsource (lib "Database_Libs1") (part "C"))
    )
    (comp (ref "C445")
      (value "22uF")
      (footprint "SMD_0805_CAPC2012X145N")
      (fields
        (field (name "DB_PART_NUMBER") "CAP000043686")
        (field (name "DB_VALUE") "22uF")
        (field (name "DB_TOLERANCE") "20%")
        (field (name "DB_VOLTAGE") "6.3V")
        (field (name "DB_MANUFACTURER_PART") "KEMET    C0805C226M9PAC")
        (field (name "DB_APPROVED_BY") "ISHIDDEN=T")
      )
      (libsource (lib "Database_Libs1") (part "C"))
    )
    (comp (ref "C446")
      (value "22uF")
      (footprint "SMD_0805_CAPC2012X145N")
      (fields
        (field (name "DB_PART_NUMBER") "CAP000043686")
        (field (name "DB_VALUE") "22uF")
        (field (name "DB_TOLERANCE") "20%")
        (field (name "DB_VOLTAGE") "6.3V")
        (field (name "DB_MANUFACTURER_PART") "KEMET    C0805C226M9PAC")
        (field (name "DB_APPROVED_BY") "ISHIDDEN=T")
      )
      (libsource (lib "Database_Libs1") (part "C"))
    )
    (comp (ref "C447")
      (value "22uF")
      (footprint "SMD_0805_CAPC2012X145N")
      (fields
        (field (name "DB_PART_NUMBER") "CAP000043686")
        (field (name "DB_VALUE") "22uF")
        (field (name "DB_TOLERANCE") "20%")
        (field (name "DB_VOLTAGE") "6.3V")
        (field (name "DB_MANUFACTURER_PART") "KEMET    C0805C226M9PAC")
        (field (name "DB_APPROVED_BY") "ISHIDDEN=T")
      )
      (libsource (lib "Database_Libs1") (part "C"))
    )
    (comp (ref "C448")
      (value "22uF")
      (footprint "SMD_0805_CAPC2012X145N")
      (fields
        (field (name "DB_PART_NUMBER") "CAP000043686")
        (field (name "DB_VALUE") "22uF")
        (field (name "DB_TOLERANCE") "20%")
        (field (name "DB_VOLTAGE") "6.3V")
        (field (name "DB_MANUFACTURER_PART") "KEMET    C0805C226M9PAC")
        (field (name "DB_APPROVED_BY") "ISHIDDEN=T")
      )
      (libsource (lib "Database_Libs1") (part "C"))
    )
    (comp (ref "C449")
      (value "22uF")
      (footprint "SMD_0805_CAPC2012X145N")
      (fields
        (field (name "DB_PART_NUMBER") "CAP000043686")
        (field (name "DB_VALUE") "22uF")
        (field (name "DB_TOLERANCE") "20%")
        (field (name "DB_VOLTAGE") "6.3V")
        (field (name "DB_MANUFACTURER_PART") "KEMET    C0805C226M9PAC")
        (field (name "DB_APPROVED_BY") "ISHIDDEN=T")
      )
      (libsource (lib "Database_Libs1") (part "C"))
    )
    (comp (ref "C450")
      (value "22uF")
      (footprint "SMD_0805_CAPC2012X145N")
      (fields
        (field (name "DB_PART_NUMBER") "CAP000043686")
        (field (name "DB_VALUE") "22uF")
        (field (name "DB_TOLERANCE") "20%")
        (field (name "DB_VOLTAGE") "6.3V")
        (field (name "DB_MANUFACTURER_PART") "KEMET    C0805C226M9PAC")
        (field (name "DB_APPROVED_BY") "ISHIDDEN=T")
      )
      (libsource (lib "Database_Libs1") (part "C"))
    )
    (comp (ref "C451")
      (value "22uF")
      (footprint "SMD_0805_CAPC2012X145N")
      (fields
        (field (name "DB_PART_NUMBER") "CAP000043686")
        (field (name "DB_VALUE") "22uF")
        (field (name "DB_TOLERANCE") "20%")
        (field (name "DB_VOLTAGE") "6.3V")
        (field (name "DB_MANUFACTURER_PART") "KEMET    C0805C226M9PAC")
        (field (name "DB_APPROVED_BY") "ISHIDDEN=T")
      )
      (libsource (lib "Database_Libs1") (part "C"))
    )
    (comp (ref "C452")
      (value "22uF")
      (footprint "SMD_0805_CAPC2012X145N")
      (fields
        (field (name "DB_PART_NUMBER") "CAP000043686")
        (field (name "DB_VALUE") "22uF")
        (field (name "DB_TOLERANCE") "20%")
        (field (name "DB_VOLTAGE") "6.3V")
        (field (name "DB_MANUFACTURER_PART") "KEMET    C0805C226M9PAC")
        (field (name "DB_APPROVED_BY") "ISHIDDEN=T")
      )
      (libsource (lib "Database_Libs1") (part "C"))
    )
    (comp (ref "C453")
      (value "22uF")
      (footprint "SMD_0805_CAPC2012X145N")
      (fields
        (field (name "DB_PART_NUMBER") "CAP000043686")
        (field (name "DB_VALUE") "22uF")
        (field (name "DB_TOLERANCE") "20%")
        (field (name "DB_VOLTAGE") "6.3V")
        (field (name "DB_MANUFACTURER_PART") "KEMET    C0805C226M9PAC")
        (field (name "DB_APPROVED_BY") "ISHIDDEN=T")
      )
      (libsource (lib "Database_Libs1") (part "C"))
    )
    (comp (ref "C454")
      (value "22uF")
      (footprint "SMD_0805_CAPC2012X145N")
      (fields
        (field (name "DB_PART_NUMBER") "CAP000043686")
        (field (name "DB_VALUE") "22uF")
        (field (name "DB_TOLERANCE") "20%")
        (field (name "DB_VOLTAGE") "6.3V")
        (field (name "DB_MANUFACTURER_PART") "KEMET    C0805C226M9PAC")
        (field (name "DB_APPROVED_BY") "ISHIDDEN=T")
      )
      (libsource (lib "Database_Libs1") (part "C"))
    )
    (comp (ref "C455")
      (value "22uF")
      (footprint "SMD_0805_CAPC2012X145N")
      (fields
        (field (name "DB_PART_NUMBER") "CAP000043686")
        (field (name "DB_VALUE") "22uF")
        (field (name "DB_TOLERANCE") "20%")
        (field (name "DB_VOLTAGE") "6.3V")
        (field (name "DB_MANUFACTURER_PART") "KEMET    C0805C226M9PAC")
        (field (name "DB_APPROVED_BY") "ISHIDDEN=T")
      )
      (libsource (lib "Database_Libs1") (part "C"))
    )
    (comp (ref "C456")
      (value "22uF")
      (footprint "SMD_0805_CAPC2012X145N")
      (fields
        (field (name "DB_PART_NUMBER") "CAP000043686")
        (field (name "DB_VALUE") "22uF")
        (field (name "DB_TOLERANCE") "20%")
        (field (name "DB_VOLTAGE") "6.3V")
        (field (name "DB_MANUFACTURER_PART") "KEMET    C0805C226M9PAC")
        (field (name "DB_APPROVED_BY") "ISHIDDEN=T")
      )
      (libsource (lib "Database_Libs1") (part "C"))
    )
    (comp (ref "C457")
      (value "22uF")
      (footprint "SMD_0805_CAPC2012X145N")
      (fields
        (field (name "DB_PART_NUMBER") "CAP000043686")
        (field (name "DB_VALUE") "22uF")
        (field (name "DB_TOLERANCE") "20%")
        (field (name "DB_VOLTAGE") "6.3V")
        (field (name "DB_MANUFACTURER_PART") "KEMET    C0805C226M9PAC")
        (field (name "DB_APPROVED_BY") "ISHIDDEN=T")
      )
      (libsource (lib "Database_Libs1") (part "C"))
    )
    (comp (ref "C458")
      (value "22uF")
      (footprint "SMD_0805_CAPC2012X145N")
      (fields
        (field (name "DB_PART_NUMBER") "CAP000043686")
        (field (name "DB_VALUE") "22uF")
        (field (name "DB_TOLERANCE") "20%")
        (field (name "DB_VOLTAGE") "6.3V")
        (field (name "DB_MANUFACTURER_PART") "KEMET    C0805C226M9PAC")
        (field (name "DB_APPROVED_BY") "ISHIDDEN=T")
      )
      (libsource (lib "Database_Libs1") (part "C"))
    )
    (comp (ref "C459")
      (value "22uF")
      (footprint "SMD_0805_CAPC2012X145N")
      (fields
        (field (name "DB_PART_NUMBER") "CAP000043686")
        (field (name "DB_VALUE") "22uF")
        (field (name "DB_TOLERANCE") "20%")
        (field (name "DB_VOLTAGE") "6.3V")
        (field (name "DB_MANUFACTURER_PART") "KEMET    C0805C226M9PAC")
        (field (name "DB_APPROVED_BY") "ISHIDDEN=T")
      )
      (libsource (lib "Database_Libs1") (part "C"))
    )
    (comp (ref "C460")
      (value "22uF")
      (footprint "SMD_0805_CAPC2012X145N")
      (fields
        (field (name "DB_PART_NUMBER") "CAP000043686")
        (field (name "DB_VALUE") "22uF")
        (field (name "DB_TOLERANCE") "20%")
        (field (name "DB_VOLTAGE") "6.3V")
        (field (name "DB_MANUFACTURER_PART") "KEMET    C0805C226M9PAC")
        (field (name "DB_APPROVED_BY") "ISHIDDEN=T")
      )
      (libsource (lib "Database_Libs1") (part "C"))
    )
    (comp (ref "C461")
      (value "22uF")
      (footprint "SMD_0805_CAPC2012X145N")
      (fields
        (field (name "DB_PART_NUMBER") "CAP000043686")
        (field (name "DB_VALUE") "22uF")
        (field (name "DB_TOLERANCE") "20%")
        (field (name "DB_VOLTAGE") "6.3V")
        (field (name "DB_MANUFACTURER_PART") "KEMET    C0805C226M9PAC")
        (field (name "DB_APPROVED_BY") "ISHIDDEN=T")
      )
      (libsource (lib "Database_Libs1") (part "C"))
    )
    (comp (ref "C462")
      (value "22uF")
      (footprint "SMD_0805_CAPC2012X145N")
      (fields
        (field (name "DB_PART_NUMBER") "CAP000043686")
        (field (name "DB_VALUE") "22uF")
        (field (name "DB_TOLERANCE") "20%")
        (field (name "DB_VOLTAGE") "6.3V")
        (field (name "DB_MANUFACTURER_PART") "KEMET    C0805C226M9PAC")
        (field (name "DB_APPROVED_BY") "ISHIDDEN=T")
      )
      (libsource (lib "Database_Libs1") (part "C"))
    )
    (comp (ref "C463")
      (value "22uF")
      (footprint "SMD_0805_CAPC2012X145N")
      (fields
        (field (name "DB_PART_NUMBER") "CAP000043686")
        (field (name "DB_VALUE") "22uF")
        (field (name "DB_TOLERANCE") "20%")
        (field (name "DB_VOLTAGE") "6.3V")
        (field (name "DB_MANUFACTURER_PART") "KEMET    C0805C226M9PAC")
        (field (name "DB_APPROVED_BY") "ISHIDDEN=T")
      )
      (libsource (lib "Database_Libs1") (part "C"))
    )
    (comp (ref "C464")
      (value "22uF")
      (footprint "SMD_0805_CAPC2012X145N")
      (fields
        (field (name "DB_PART_NUMBER") "CAP000043686")
        (field (name "DB_VALUE") "22uF")
        (field (name "DB_TOLERANCE") "20%")
        (field (name "DB_VOLTAGE") "6.3V")
        (field (name "DB_MANUFACTURER_PART") "KEMET    C0805C226M9PAC")
        (field (name "DB_APPROVED_BY") "ISHIDDEN=T")
      )
      (libsource (lib "Database_Libs1") (part "C"))
    )
    (comp (ref "C465")
      (value "22uF")
      (footprint "SMD_0805_CAPC2012X145N")
      (fields
        (field (name "DB_PART_NUMBER") "CAP000043686")
        (field (name "DB_VALUE") "22uF")
        (field (name "DB_TOLERANCE") "20%")
        (field (name "DB_VOLTAGE") "6.3V")
        (field (name "DB_MANUFACTURER_PART") "KEMET    C0805C226M9PAC")
        (field (name "DB_APPROVED_BY") "ISHIDDEN=T")
      )
      (libsource (lib "Database_Libs1") (part "C"))
    )
    (comp (ref "C466")
      (value "22uF")
      (footprint "SMD_0805_CAPC2012X145N")
      (fields
        (field (name "DB_PART_NUMBER") "CAP000043686")
        (field (name "DB_VALUE") "22uF")
        (field (name "DB_TOLERANCE") "20%")
        (field (name "DB_VOLTAGE") "6.3V")
        (field (name "DB_MANUFACTURER_PART") "KEMET    C0805C226M9PAC")
        (field (name "DB_APPROVED_BY") "ISHIDDEN=T")
      )
      (libsource (lib "Database_Libs1") (part "C"))
    )
    (comp (ref "C467")
      (value "22uF")
      (footprint "SMD_0805_CAPC2012X145N")
      (fields
        (field (name "DB_PART_NUMBER") "CAP000043686")
        (field (name "DB_VALUE") "22uF")
        (field (name "DB_TOLERANCE") "20%")
        (field (name "DB_VOLTAGE") "6.3V")
        (field (name "DB_MANUFACTURER_PART") "KEMET    C0805C226M9PAC")
        (field (name "DB_APPROVED_BY") "ISHIDDEN=T")
      )
      (libsource (lib "Database_Libs1") (part "C"))
    )
    (comp (ref "C468")
      (value "22uF")
      (footprint "SMD_0805_CAPC2012X145N")
      (fields
        (field (name "DB_PART_NUMBER") "CAP000043686")
        (field (name "DB_VALUE") "22uF")
        (field (name "DB_TOLERANCE") "20%")
        (field (name "DB_VOLTAGE") "6.3V")
        (field (name "DB_MANUFACTURER_PART") "KEMET    C0805C226M9PAC")
        (field (name "DB_APPROVED_BY") "ISHIDDEN=T")
      )
      (libsource (lib "Database_Libs1") (part "C"))
    )
    (comp (ref "C469")
      (value "22uF")
      (footprint "SMD_0805_CAPC2012X145N")
      (fields
        (field (name "DB_PART_NUMBER") "CAP000043686")
        (field (name "DB_VALUE") "22uF")
        (field (name "DB_TOLERANCE") "20%")
        (field (name "DB_VOLTAGE") "6.3V")
        (field (name "DB_MANUFACTURER_PART") "KEMET    C0805C226M9PAC")
        (field (name "DB_APPROVED_BY") "ISHIDDEN=T")
      )
      (libsource (lib "Database_Libs1") (part "C"))
    )
    (comp (ref "C470")
      (value "22uF")
      (footprint "SMD_0805_CAPC2012X145N")
      (fields
        (field (name "DB_PART_NUMBER") "CAP000043686")
        (field (name "DB_VALUE") "22uF")
        (field (name "DB_TOLERANCE") "20%")
        (field (name "DB_VOLTAGE") "6.3V")
        (field (name "DB_MANUFACTURER_PART") "KEMET    C0805C226M9PAC")
        (field (name "DB_APPROVED_BY") "ISHIDDEN=T")
      )
      (libsource (lib "Database_Libs1") (part "C"))
    )
    (comp (ref "C471")
      (value "22uF")
      (footprint "SMD_0805_CAPC2012X145N")
      (fields
        (field (name "DB_PART_NUMBER") "CAP000043686")
        (field (name "DB_VALUE") "22uF")
        (field (name "DB_TOLERANCE") "20%")
        (field (name "DB_VOLTAGE") "6.3V")
        (field (name "DB_MANUFACTURER_PART") "KEMET    C0805C226M9PAC")
        (field (name "DB_APPROVED_BY") "ISHIDDEN=T")
      )
      (libsource (lib "Database_Libs1") (part "C"))
    )
    (comp (ref "C472")
      (value "22uF")
      (footprint "SMD_0805_CAPC2012X145N")
      (fields
        (field (name "DB_PART_NUMBER") "CAP000043686")
        (field (name "DB_VALUE") "22uF")
        (field (name "DB_TOLERANCE") "20%")
        (field (name "DB_VOLTAGE") "6.3V")
        (field (name "DB_MANUFACTURER_PART") "KEMET    C0805C226M9PAC")
        (field (name "DB_APPROVED_BY") "ISHIDDEN=T")
      )
      (libsource (lib "Database_Libs1") (part "C"))
    )
    (comp (ref "C473")
      (value "22uF")
      (footprint "SMD_0805_CAPC2012X145N")
      (fields
        (field (name "DB_PART_NUMBER") "CAP000043686")
        (field (name "DB_VALUE") "22uF")
        (field (name "DB_TOLERANCE") "20%")
        (field (name "DB_VOLTAGE") "6.3V")
        (field (name "DB_MANUFACTURER_PART") "KEMET    C0805C226M9PAC")
        (field (name "DB_APPROVED_BY") "ISHIDDEN=T")
      )
      (libsource (lib "Database_Libs1") (part "C"))
    )
    (comp (ref "C474")
      (value "22uF")
      (footprint "SMD_0805_CAPC2012X145N")
      (fields
        (field (name "DB_PART_NUMBER") "CAP000043686")
        (field (name "DB_VALUE") "22uF")
        (field (name "DB_TOLERANCE") "20%")
        (field (name "DB_VOLTAGE") "6.3V")
        (field (name "DB_MANUFACTURER_PART") "KEMET    C0805C226M9PAC")
        (field (name "DB_APPROVED_BY") "ISHIDDEN=T")
      )
      (libsource (lib "Database_Libs1") (part "C"))
    )
    (comp (ref "C475")
      (value "22uF")
      (footprint "SMD_0805_CAPC2012X145N")
      (fields
        (field (name "DB_PART_NUMBER") "CAP000043686")
        (field (name "DB_VALUE") "22uF")
        (field (name "DB_TOLERANCE") "20%")
        (field (name "DB_VOLTAGE") "6.3V")
        (field (name "DB_MANUFACTURER_PART") "KEMET    C0805C226M9PAC")
        (field (name "DB_APPROVED_BY") "ISHIDDEN=T")
      )
      (libsource (lib "Database_Libs1") (part "C"))
    )
    (comp (ref "C476")
      (value "22uF")
      (footprint "SMD_0805_CAPC2012X145N")
      (fields
        (field (name "DB_PART_NUMBER") "CAP000043686")
        (field (name "DB_VALUE") "22uF")
        (field (name "DB_TOLERANCE") "20%")
        (field (name "DB_VOLTAGE") "6.3V")
        (field (name "DB_MANUFACTURER_PART") "KEMET    C0805C226M9PAC")
        (field (name "DB_APPROVED_BY") "ISHIDDEN=T")
      )
      (libsource (lib "Database_Libs1") (part "C"))
    )
    (comp (ref "C477")
      (value "22uF")
      (footprint "SMD_0805_CAPC2012X145N")
      (fields
        (field (name "DB_PART_NUMBER") "CAP000043686")
        (field (name "DB_VALUE") "22uF")
        (field (name "DB_TOLERANCE") "20%")
        (field (name "DB_VOLTAGE") "6.3V")
        (field (name "DB_MANUFACTURER_PART") "KEMET    C0805C226M9PAC")
        (field (name "DB_APPROVED_BY") "ISHIDDEN=T")
      )
      (libsource (lib "Database_Libs1") (part "C"))
    )
    (comp (ref "C478")
      (value "22uF")
      (footprint "SMD_0805_CAPC2012X145N")
      (fields
        (field (name "DB_PART_NUMBER") "CAP000043686")
        (field (name "DB_VALUE") "22uF")
        (field (name "DB_TOLERANCE") "20%")
        (field (name "DB_VOLTAGE") "6.3V")
        (field (name "DB_MANUFACTURER_PART") "KEMET    C0805C226M9PAC")
        (field (name "DB_APPROVED_BY") "ISHIDDEN=T")
      )
      (libsource (lib "Database_Libs1") (part "C"))
    )
    (comp (ref "C479")
      (value "22uF")
      (footprint "SMD_0805_CAPC2012X145N")
      (fields
        (field (name "DB_PART_NUMBER") "CAP000043686")
        (field (name "DB_VALUE") "22uF")
        (field (name "DB_TOLERANCE") "20%")
        (field (name "DB_VOLTAGE") "6.3V")
        (field (name "DB_MANUFACTURER_PART") "KEMET    C0805C226M9PAC")
        (field (name "DB_APPROVED_BY") "ISHIDDEN=T")
      )
      (libsource (lib "Database_Libs1") (part "C"))
    )
    (comp (ref "C480")
      (value "22uF")
      (footprint "SMD_0805_CAPC2012X145N")
      (fields
        (field (name "DB_PART_NUMBER") "CAP000043686")
        (field (name "DB_VALUE") "22uF")
        (field (name "DB_TOLERANCE") "20%")
        (field (name "DB_VOLTAGE") "6.3V")
        (field (name "DB_MANUFACTURER_PART") "KEMET    C0805C226M9PAC")
        (field (name "DB_APPROVED_BY") "ISHIDDEN=T")
      )
      (libsource (lib "Database_Libs1") (part "C"))
    )
    (comp (ref "C481")
      (value "22uF")
      (footprint "SMD_0805_CAPC2012X145N")
      (fields
        (field (name "DB_PART_NUMBER") "CAP000043686")
        (field (name "DB_VALUE") "22uF")
        (field (name "DB_TOLERANCE") "20%")
        (field (name "DB_VOLTAGE") "6.3V")
        (field (name "DB_MANUFACTURER_PART") "KEMET    C0805C226M9PAC")
        (field (name "DB_APPROVED_BY") "ISHIDDEN=T")
      )
      (libsource (lib "Database_Libs1") (part "C"))
    )
    (comp (ref "C482")
      (value "22uF")
      (footprint "SMD_0805_CAPC2012X145N")
      (fields
        (field (name "DB_PART_NUMBER") "CAP000043686")
        (field (name "DB_VALUE") "22uF")
        (field (name "DB_TOLERANCE") "20%")
        (field (name "DB_VOLTAGE") "6.3V")
        (field (name "DB_MANUFACTURER_PART") "KEMET    C0805C226M9PAC")
        (field (name "DB_APPROVED_BY") "ISHIDDEN=T")
      )
      (libsource (lib "Database_Libs1") (part "C"))
    )
    (comp (ref "C483")
      (value "22uF")
      (footprint "SMD_0805_CAPC2012X145N")
      (fields
        (field (name "DB_PART_NUMBER") "CAP000043686")
        (field (name "DB_VALUE") "22uF")
        (field (name "DB_TOLERANCE") "20%")
        (field (name "DB_VOLTAGE") "6.3V")
        (field (name "DB_MANUFACTURER_PART") "KEMET    C0805C226M9PAC")
        (field (name "DB_APPROVED_BY") "ISHIDDEN=T")
      )
      (libsource (lib "Database_Libs1") (part "C"))
    )
    (comp (ref "C484")
      (value "22uF")
      (footprint "SMD_0805_CAPC2012X145N")
      (fields
        (field (name "DB_PART_NUMBER") "CAP000043686")
        (field (name "DB_VALUE") "22uF")
        (field (name "DB_TOLERANCE") "20%")
        (field (name "DB_VOLTAGE") "6.3V")
        (field (name "DB_MANUFACTURER_PART") "KEMET    C0805C226M9PAC")
        (field (name "DB_APPROVED_BY") "ISHIDDEN=T")
      )
      (libsource (lib "Database_Libs1") (part "C"))
    )
    (comp (ref "C485")
      (value "22uF")
      (footprint "SMD_0805_CAPC2012X145N")
      (fields
        (field (name "DB_PART_NUMBER") "CAP000043686")
        (field (name "DB_VALUE") "22uF")
        (field (name "DB_TOLERANCE") "20%")
        (field (name "DB_VOLTAGE") "6.3V")
        (field (name "DB_MANUFACTURER_PART") "KEMET    C0805C226M9PAC")
        (field (name "DB_APPROVED_BY") "ISHIDDEN=T")
      )
      (libsource (lib "Database_Libs1") (part "C"))
    )
    (comp (ref "C486")
      (value "22uF")
      (footprint "SMD_0805_CAPC2012X145N")
      (fields
        (field (name "DB_PART_NUMBER") "CAP000043686")
        (field (name "DB_VALUE") "22uF")
        (field (name "DB_TOLERANCE") "20%")
        (field (name "DB_VOLTAGE") "6.3V")
        (field (name "DB_MANUFACTURER_PART") "KEMET    C0805C226M9PAC")
        (field (name "DB_APPROVED_BY") "ISHIDDEN=T")
      )
      (libsource (lib "Database_Libs1") (part "C"))
    )
    (comp (ref "C487")
      (value "22uF")
      (footprint "SMD_0805_CAPC2012X145N")
      (fields
        (field (name "DB_PART_NUMBER") "CAP000043686")
        (field (name "DB_VALUE") "22uF")
        (field (name "DB_TOLERANCE") "20%")
        (field (name "DB_VOLTAGE") "6.3V")
        (field (name "DB_MANUFACTURER_PART") "KEMET    C0805C226M9PAC")
        (field (name "DB_APPROVED_BY") "ISHIDDEN=T")
      )
      (libsource (lib "Database_Libs1") (part "C"))
    )
    (comp (ref "C488")
      (value "22uF")
      (footprint "SMD_0805_CAPC2012X145N")
      (fields
        (field (name "DB_PART_NUMBER") "CAP000043686")
        (field (name "DB_VALUE") "22uF")
        (field (name "DB_TOLERANCE") "20%")
        (field (name "DB_VOLTAGE") "6.3V")
        (field (name "DB_MANUFACTURER_PART") "KEMET    C0805C226M9PAC")
        (field (name "DB_APPROVED_BY") "ISHIDDEN=T")
      )
      (libsource (lib "Database_Libs1") (part "C"))
    )
    (comp (ref "C489")
      (value "22uF")
      (footprint "SMD_0805_CAPC2012X145N")
      (fields
        (field (name "DB_PART_NUMBER") "CAP000043686")
        (field (name "DB_VALUE") "22uF")
        (field (name "DB_TOLERANCE") "20%")
        (field (name "DB_VOLTAGE") "6.3V")
        (field (name "DB_MANUFACTURER_PART") "KEMET    C0805C226M9PAC")
        (field (name "DB_APPROVED_BY") "ISHIDDEN=T")
      )
      (libsource (lib "Database_Libs1") (part "C"))
    )
    (comp (ref "C490")
      (value "22uF")
      (footprint "SMD_0805_CAPC2012X145N")
      (fields
        (field (name "DB_PART_NUMBER") "CAP000043686")
        (field (name "DB_VALUE") "22uF")
        (field (name "DB_TOLERANCE") "20%")
        (field (name "DB_VOLTAGE") "6.3V")
        (field (name "DB_MANUFACTURER_PART") "KEMET    C0805C226M9PAC")
        (field (name "DB_APPROVED_BY") "ISHIDDEN=T")
      )
      (libsource (lib "Database_Libs1") (part "C"))
    )
    (comp (ref "C491")
      (value "22uF")
      (footprint "SMD_0805_CAPC2012X145N")
      (fields
        (field (name "DB_PART_NUMBER") "CAP000043686")
        (field (name "DB_VALUE") "22uF")
        (field (name "DB_TOLERANCE") "20%")
        (field (name "DB_VOLTAGE") "6.3V")
        (field (name "DB_MANUFACTURER_PART") "KEMET    C0805C226M9PAC")
        (field (name "DB_APPROVED_BY") "ISHIDDEN=T")
      )
      (libsource (lib "Database_Libs1") (part "C"))
    )
    (comp (ref "C593")
      (value "100uF")
      (footprint "SMD_1210_CAPC3225X270N")
      (fields
        (field (name "DB_PART_NUMBER") "CAP000043701")
        (field (name "DB_VALUE") "100uF")
        (field (name "DB_TOLERANCE") "20%")
        (field (name "DB_VOLTAGE") "6.3V")
        (field (name "DB_MANUFACTURER_PART") "KEMET    C1210C107M9PAC")
        (field (name "DB_APPROVED_BY") "ISHIDDEN=T")
      )
      (libsource (lib "Database_Libs1") (part "C"))
    )
    (comp (ref "C596")
      (value "100uF")
      (footprint "SMD_1210_CAPC3225X270N")
      (fields
        (field (name "DB_PART_NUMBER") "CAP000043701")
        (field (name "DB_VALUE") "100uF")
        (field (name "DB_TOLERANCE") "20%")
        (field (name "DB_VOLTAGE") "6.3V")
        (field (name "DB_MANUFACTURER_PART") "KEMET    C1210C107M9PAC")
        (field (name "DB_APPROVED_BY") "ISHIDDEN=T")
      )
      (libsource (lib "Database_Libs1") (part "C"))
    )
    (comp (ref "C598")
      (value "10uF")
      (footprint "SMD_0805_CAPC2012X145N")
      (fields
        (field (name "DB_PART_NUMBER") "CAP000043636")
        (field (name "DB_VALUE") "10uF")
        (field (name "DB_TOLERANCE") "10%")
        (field (name "DB_VOLTAGE") "16V")
        (field (name "DB_MANUFACTURER_PART") "KEMET    C0805C106K4PAC")
        (field (name "DB_APPROVED_BY") "ISHIDDEN=T")
      )
      (libsource (lib "Database_Libs1") (part "C"))
    )
    (comp (ref "C599")
      (value "100uF")
      (footprint "SMD_1210_CAPC3225X270N")
      (fields
        (field (name "DB_PART_NUMBER") "CAP000043701")
        (field (name "DB_VALUE") "100uF")
        (field (name "DB_TOLERANCE") "20%")
        (field (name "DB_VOLTAGE") "6.3V")
        (field (name "DB_MANUFACTURER_PART") "KEMET    C1210C107M9PAC")
        (field (name "DB_APPROVED_BY") "ISHIDDEN=T")
      )
      (libsource (lib "Database_Libs1") (part "C"))
    )
    (comp (ref "C600")
      (value "10uF")
      (footprint "SMD_0805_CAPC2012X145N")
      (fields
        (field (name "DB_PART_NUMBER") "CAP000043636")
        (field (name "DB_VALUE") "10uF")
        (field (name "DB_TOLERANCE") "10%")
        (field (name "DB_VOLTAGE") "16V")
        (field (name "DB_MANUFACTURER_PART") "KEMET    C0805C106K4PAC")
        (field (name "DB_APPROVED_BY") "ISHIDDEN=T")
      )
      (libsource (lib "Database_Libs1") (part "C"))
    )
    (comp (ref "C602")
      (value "100uF")
      (footprint "SMD_1210_CAPC3225X270N")
      (fields
        (field (name "DB_PART_NUMBER") "CAP000043701")
        (field (name "DB_VALUE") "100uF")
        (field (name "DB_TOLERANCE") "20%")
        (field (name "DB_VOLTAGE") "6.3V")
        (field (name "DB_MANUFACTURER_PART") "KEMET    C1210C107M9PAC")
        (field (name "DB_APPROVED_BY") "ISHIDDEN=T")
      )
      (libsource (lib "Database_Libs1") (part "C"))
    )
    (comp (ref "C603")
      (value "10uF")
      (footprint "SMD_0805_CAPC2012X145N")
      (fields
        (field (name "DB_PART_NUMBER") "CAP000043636")
        (field (name "DB_VALUE") "10uF")
        (field (name "DB_TOLERANCE") "10%")
        (field (name "DB_VOLTAGE") "16V")
        (field (name "DB_MANUFACTURER_PART") "KEMET    C0805C106K4PAC")
        (field (name "DB_APPROVED_BY") "ISHIDDEN=T")
      )
      (libsource (lib "Database_Libs1") (part "C"))
    )
    (comp (ref "C605")
      (value "100uF")
      (footprint "SMD_1210_CAPC3225X270N")
      (fields
        (field (name "DB_PART_NUMBER") "CAP000043701")
        (field (name "DB_VALUE") "100uF")
        (field (name "DB_TOLERANCE") "20%")
        (field (name "DB_VOLTAGE") "6.3V")
        (field (name "DB_MANUFACTURER_PART") "KEMET    C1210C107M9PAC")
        (field (name "DB_APPROVED_BY") "ISHIDDEN=T")
      )
      (libsource (lib "Database_Libs1") (part "C"))
    )
    (comp (ref "C606")
      (value "10uF")
      (footprint "SMD_0805_CAPC2012X145N")
      (fields
        (field (name "DB_PART_NUMBER") "CAP000043636")
        (field (name "DB_VALUE") "10uF")
        (field (name "DB_TOLERANCE") "10%")
        (field (name "DB_VOLTAGE") "16V")
        (field (name "DB_MANUFACTURER_PART") "KEMET    C0805C106K4PAC")
        (field (name "DB_APPROVED_BY") "ISHIDDEN=T")
      )
      (libsource (lib "Database_Libs1") (part "C"))
    )
    (comp (ref "C640")
      (value "10uF")
      (footprint "SMD_0805_CAPC2012X145N")
      (fields
        (field (name "DB_PART_NUMBER") "CAP000043636")
        (field (name "DB_VALUE") "10uF")
        (field (name "DB_TOLERANCE") "10%")
        (field (name "DB_VOLTAGE") "16V")
        (field (name "DB_MANUFACTURER_PART") "KEMET    C0805C106K4PAC")
        (field (name "DB_APPROVED_BY") "ISHIDDEN=T")
      )
      (libsource (lib "Database_Libs1") (part "C"))
    )
    (comp (ref "C642")
      (value "10uF")
      (footprint "SMD_0805_CAPC2012X145N")
      (fields
        (field (name "DB_PART_NUMBER") "CAP000043636")
        (field (name "DB_VALUE") "10uF")
        (field (name "DB_TOLERANCE") "10%")
        (field (name "DB_VOLTAGE") "16V")
        (field (name "DB_MANUFACTURER_PART") "KEMET    C0805C106K4PAC")
        (field (name "DB_APPROVED_BY") "ISHIDDEN=T")
      )
      (libsource (lib "Database_Libs1") (part "C"))
    )
    (comp (ref "C643")
      (value "10uF")
      (footprint "SMD_0805_CAPC2012X145N")
      (fields
        (field (name "DB_PART_NUMBER") "CAP000043636")
        (field (name "DB_VALUE") "10uF")
        (field (name "DB_TOLERANCE") "10%")
        (field (name "DB_VOLTAGE") "16V")
        (field (name "DB_MANUFACTURER_PART") "KEMET    C0805C106K4PAC")
        (field (name "DB_APPROVED_BY") "ISHIDDEN=T")
      )
      (libsource (lib "Database_Libs1") (part "C"))
    )
    (comp (ref "C645")
      (value "10uF")
      (footprint "SMD_0805_CAPC2012X145N")
      (fields
        (field (name "DB_PART_NUMBER") "CAP000043636")
        (field (name "DB_VALUE") "10uF")
        (field (name "DB_TOLERANCE") "10%")
        (field (name "DB_VOLTAGE") "16V")
        (field (name "DB_MANUFACTURER_PART") "KEMET    C0805C106K4PAC")
        (field (name "DB_APPROVED_BY") "ISHIDDEN=T")
      )
      (libsource (lib "Database_Libs1") (part "C"))
    )
    (comp (ref "C646")
      (value "10uF")
      (footprint "SMD_0805_CAPC2012X145N")
      (fields
        (field (name "DB_PART_NUMBER") "CAP000043636")
        (field (name "DB_VALUE") "10uF")
        (field (name "DB_TOLERANCE") "10%")
        (field (name "DB_VOLTAGE") "16V")
        (field (name "DB_MANUFACTURER_PART") "KEMET    C0805C106K4PAC")
        (field (name "DB_APPROVED_BY") "ISHIDDEN=T")
      )
      (libsource (lib "Database_Libs1") (part "C"))
    )
    (comp (ref "C652")
      (value "22uF")
      (footprint "SMD_0805_CAPC2012X145N")
      (fields
        (field (name "DB_PART_NUMBER") "CAP000043686")
        (field (name "DB_VALUE") "22uF")
        (field (name "DB_TOLERANCE") "20%")
        (field (name "DB_VOLTAGE") "6.3V")
        (field (name "DB_MANUFACTURER_PART") "KEMET    C0805C226M9PAC")
        (field (name "DB_APPROVED_BY") "ISHIDDEN=T")
      )
      (libsource (lib "Database_Libs1") (part "C"))
    )
    (comp (ref "C653")
      (value "220uF")
      (footprint "SMD_1210_CAPC3225X279N")
      (fields
        (field (name "DB_PART_NUMBER") "CAP000047355")
        (field (name "DB_VALUE") "220uF")
        (field (name "DB_TOLERANCE") "20%")
        (field (name "DB_VOLTAGE") "6.3V")
        (field (name "DB_MANUFACTURER_PART") "SAMSUNG    CL32A227MQVNNNE")
        (field (name "DB_APPROVED_BY") "VSN")
      )
      (libsource (lib "Database_Libs1") (part "C"))
    )
    (comp (ref "C654")
      (value "22uF")
      (footprint "SMD_0805_CAPC2012X145N")
      (fields
        (field (name "DB_PART_NUMBER") "CAP000043686")
        (field (name "DB_VALUE") "22uF")
        (field (name "DB_TOLERANCE") "20%")
        (field (name "DB_VOLTAGE") "6.3V")
        (field (name "DB_MANUFACTURER_PART") "KEMET    C0805C226M9PAC")
        (field (name "DB_APPROVED_BY") "ISHIDDEN=T")
      )
      (libsource (lib "Database_Libs1") (part "C"))
    )
    (comp (ref "C655")
      (value "22uF")
      (footprint "SMD_0805_CAPC2012X145N")
      (fields
        (field (name "DB_PART_NUMBER") "CAP000043686")
        (field (name "DB_VALUE") "22uF")
        (field (name "DB_TOLERANCE") "20%")
        (field (name "DB_VOLTAGE") "6.3V")
        (field (name "DB_MANUFACTURER_PART") "KEMET    C0805C226M9PAC")
        (field (name "DB_APPROVED_BY") "ISHIDDEN=T")
      )
      (libsource (lib "Database_Libs1") (part "C"))
    )
    (comp (ref "C656")
      (value "220uF")
      (footprint "SMD_1210_CAPC3225X279N")
      (fields
        (field (name "DB_PART_NUMBER") "CAP000047355")
        (field (name "DB_VALUE") "220uF")
        (field (name "DB_TOLERANCE") "20%")
        (field (name "DB_VOLTAGE") "6.3V")
        (field (name "DB_MANUFACTURER_PART") "SAMSUNG    CL32A227MQVNNNE")
        (field (name "DB_APPROVED_BY") "VSN")
      )
      (libsource (lib "Database_Libs1") (part "C"))
    )
    (comp (ref "C657")
      (value "22uF")
      (footprint "SMD_0805_CAPC2012X145N")
      (fields
        (field (name "DB_PART_NUMBER") "CAP000043686")
        (field (name "DB_VALUE") "22uF")
        (field (name "DB_TOLERANCE") "20%")
        (field (name "DB_VOLTAGE") "6.3V")
        (field (name "DB_MANUFACTURER_PART") "KEMET    C0805C226M9PAC")
        (field (name "DB_APPROVED_BY") "ISHIDDEN=T")
      )
      (libsource (lib "Database_Libs1") (part "C"))
    )
    (comp (ref "C658")
      (value "22uF")
      (footprint "SMD_0805_CAPC2012X145N")
      (fields
        (field (name "DB_PART_NUMBER") "CAP000043686")
        (field (name "DB_VALUE") "22uF")
        (field (name "DB_TOLERANCE") "20%")
        (field (name "DB_VOLTAGE") "6.3V")
        (field (name "DB_MANUFACTURER_PART") "KEMET    C0805C226M9PAC")
        (field (name "DB_APPROVED_BY") "ISHIDDEN=T")
      )
      (libsource (lib "Database_Libs1") (part "C"))
    )
    (comp (ref "C659")
      (value "220uF")
      (footprint "SMD_1210_CAPC3225X279N")
      (fields
        (field (name "DB_PART_NUMBER") "CAP000047355")
        (field (name "DB_VALUE") "220uF")
        (field (name "DB_TOLERANCE") "20%")
        (field (name "DB_VOLTAGE") "6.3V")
        (field (name "DB_MANUFACTURER_PART") "SAMSUNG    CL32A227MQVNNNE")
        (field (name "DB_APPROVED_BY") "VSN")
      )
      (libsource (lib "Database_Libs1") (part "C"))
    )
    (comp (ref "C660")
      (value "22uF")
      (footprint "SMD_0805_CAPC2012X145N")
      (fields
        (field (name "DB_PART_NUMBER") "CAP000043686")
        (field (name "DB_VALUE") "22uF")
        (field (name "DB_TOLERANCE") "20%")
        (field (name "DB_VOLTAGE") "6.3V")
        (field (name "DB_MANUFACTURER_PART") "KEMET    C0805C226M9PAC")
        (field (name "DB_APPROVED_BY") "ISHIDDEN=T")
      )
      (libsource (lib "Database_Libs1") (part "C"))
    )
    (comp (ref "C661")
      (value "22uF")
      (footprint "SMD_0805_CAPC2012X145N")
      (fields
        (field (name "DB_PART_NUMBER") "CAP000043686")
        (field (name "DB_VALUE") "22uF")
        (field (name "DB_TOLERANCE") "20%")
        (field (name "DB_VOLTAGE") "6.3V")
        (field (name "DB_MANUFACTURER_PART") "KEMET    C0805C226M9PAC")
        (field (name "DB_APPROVED_BY") "ISHIDDEN=T")
      )
      (libsource (lib "Database_Libs1") (part "C"))
    )
    (comp (ref "C662")
      (value "220uF")
      (footprint "SMD_1210_CAPC3225X279N")
      (fields
        (field (name "DB_PART_NUMBER") "CAP000047355")
        (field (name "DB_VALUE") "220uF")
        (field (name "DB_TOLERANCE") "20%")
        (field (name "DB_VOLTAGE") "6.3V")
        (field (name "DB_MANUFACTURER_PART") "SAMSUNG    CL32A227MQVNNNE")
        (field (name "DB_APPROVED_BY") "VSN")
      )
      (libsource (lib "Database_Libs1") (part "C"))
    )
    (comp (ref "C663")
      (value "22uF")
      (footprint "SMD_0805_CAPC2012X145N")
      (fields
        (field (name "DB_PART_NUMBER") "CAP000043686")
        (field (name "DB_VALUE") "22uF")
        (field (name "DB_TOLERANCE") "20%")
        (field (name "DB_VOLTAGE") "6.3V")
        (field (name "DB_MANUFACTURER_PART") "KEMET    C0805C226M9PAC")
        (field (name "DB_APPROVED_BY") "ISHIDDEN=T")
      )
      (libsource (lib "Database_Libs1") (part "C"))
    )
    (comp (ref "C664")
      (value "22uF")
      (footprint "SMD_0805_CAPC2012X145N")
      (fields
        (field (name "DB_PART_NUMBER") "CAP000043686")
        (field (name "DB_VALUE") "22uF")
        (field (name "DB_TOLERANCE") "20%")
        (field (name "DB_VOLTAGE") "6.3V")
        (field (name "DB_MANUFACTURER_PART") "KEMET    C0805C226M9PAC")
        (field (name "DB_APPROVED_BY") "ISHIDDEN=T")
      )
      (libsource (lib "Database_Libs1") (part "C"))
    )
    (comp (ref "C665")
      (value "220uF")
      (footprint "SMD_1210_CAPC3225X279N")
      (fields
        (field (name "DB_PART_NUMBER") "CAP000047355")
        (field (name "DB_VALUE") "220uF")
        (field (name "DB_TOLERANCE") "20%")
        (field (name "DB_VOLTAGE") "6.3V")
        (field (name "DB_MANUFACTURER_PART") "SAMSUNG    CL32A227MQVNNNE")
        (field (name "DB_APPROVED_BY") "VSN")
      )
      (libsource (lib "Database_Libs1") (part "C"))
    )
    (comp (ref "C666")
      (value "22uF")
      (footprint "SMD_0805_CAPC2012X145N")
      (fields
        (field (name "DB_PART_NUMBER") "CAP000043686")
        (field (name "DB_VALUE") "22uF")
        (field (name "DB_TOLERANCE") "20%")
        (field (name "DB_VOLTAGE") "6.3V")
        (field (name "DB_MANUFACTURER_PART") "KEMET    C0805C226M9PAC")
        (field (name "DB_APPROVED_BY") "ISHIDDEN=T")
      )
      (libsource (lib "Database_Libs1") (part "C"))
    )
    (comp (ref "C667")
      (value "22uF")
      (footprint "SMD_0805_CAPC2012X145N")
      (fields
        (field (name "DB_PART_NUMBER") "CAP000043686")
        (field (name "DB_VALUE") "22uF")
        (field (name "DB_TOLERANCE") "20%")
        (field (name "DB_VOLTAGE") "6.3V")
        (field (name "DB_MANUFACTURER_PART") "KEMET    C0805C226M9PAC")
        (field (name "DB_APPROVED_BY") "ISHIDDEN=T")
      )
      (libsource (lib "Database_Libs1") (part "C"))
    )
    (comp (ref "C668")
      (value "220uF")
      (footprint "SMD_1210_CAPC3225X279N")
      (fields
        (field (name "DB_PART_NUMBER") "CAP000047355")
        (field (name "DB_VALUE") "220uF")
        (field (name "DB_TOLERANCE") "20%")
        (field (name "DB_VOLTAGE") "6.3V")
        (field (name "DB_MANUFACTURER_PART") "SAMSUNG    CL32A227MQVNNNE")
        (field (name "DB_APPROVED_BY") "VSN")
      )
      (libsource (lib "Database_Libs1") (part "C"))
    )
    (comp (ref "C669")
      (value "22uF")
      (footprint "SMD_0805_CAPC2012X145N")
      (fields
        (field (name "DB_PART_NUMBER") "CAP000043686")
        (field (name "DB_VALUE") "22uF")
        (field (name "DB_TOLERANCE") "20%")
        (field (name "DB_VOLTAGE") "6.3V")
        (field (name "DB_MANUFACTURER_PART") "KEMET    C0805C226M9PAC")
        (field (name "DB_APPROVED_BY") "ISHIDDEN=T")
      )
      (libsource (lib "Database_Libs1") (part "C"))
    )
    (comp (ref "C670")
      (value "22uF")
      (footprint "SMD_0805_CAPC2012X145N")
      (fields
        (field (name "DB_PART_NUMBER") "CAP000043686")
        (field (name "DB_VALUE") "22uF")
        (field (name "DB_TOLERANCE") "20%")
        (field (name "DB_VOLTAGE") "6.3V")
        (field (name "DB_MANUFACTURER_PART") "KEMET    C0805C226M9PAC")
        (field (name "DB_APPROVED_BY") "ISHIDDEN=T")
      )
      (libsource (lib "Database_Libs1") (part "C"))
    )
    (comp (ref "C671")
      (value "220uF")
      (footprint "SMD_1210_CAPC3225X279N")
      (fields
        (field (name "DB_PART_NUMBER") "CAP000047355")
        (field (name "DB_VALUE") "220uF")
        (field (name "DB_TOLERANCE") "20%")
        (field (name "DB_VOLTAGE") "6.3V")
        (field (name "DB_MANUFACTURER_PART") "SAMSUNG    CL32A227MQVNNNE")
        (field (name "DB_APPROVED_BY") "VSN")
      )
      (libsource (lib "Database_Libs1") (part "C"))
    )
    (comp (ref "C672")
      (value "22uF")
      (footprint "SMD_0805_CAPC2012X145N")
      (fields
        (field (name "DB_PART_NUMBER") "CAP000043686")
        (field (name "DB_VALUE") "22uF")
        (field (name "DB_TOLERANCE") "20%")
        (field (name "DB_VOLTAGE") "6.3V")
        (field (name "DB_MANUFACTURER_PART") "KEMET    C0805C226M9PAC")
        (field (name "DB_APPROVED_BY") "ISHIDDEN=T")
      )
      (libsource (lib "Database_Libs1") (part "C"))
    )
    (comp (ref "C673")
      (value "22uF")
      (footprint "SMD_0805_CAPC2012X145N")
      (fields
        (field (name "DB_PART_NUMBER") "CAP000043686")
        (field (name "DB_VALUE") "22uF")
        (field (name "DB_TOLERANCE") "20%")
        (field (name "DB_VOLTAGE") "6.3V")
        (field (name "DB_MANUFACTURER_PART") "KEMET    C0805C226M9PAC")
        (field (name "DB_APPROVED_BY") "ISHIDDEN=T")
      )
      (libsource (lib "Database_Libs1") (part "C"))
    )
    (comp (ref "C674")
      (value "220uF")
      (footprint "SMD_1210_CAPC3225X279N")
      (fields
        (field (name "DB_PART_NUMBER") "CAP000047355")
        (field (name "DB_VALUE") "220uF")
        (field (name "DB_TOLERANCE") "20%")
        (field (name "DB_VOLTAGE") "6.3V")
        (field (name "DB_MANUFACTURER_PART") "SAMSUNG    CL32A227MQVNNNE")
        (field (name "DB_APPROVED_BY") "VSN")
      )
      (libsource (lib "Database_Libs1") (part "C"))
    )
    (comp (ref "C675")
      (value "22uF")
      (footprint "SMD_0805_CAPC2012X145N")
      (fields
        (field (name "DB_PART_NUMBER") "CAP000043686")
        (field (name "DB_VALUE") "22uF")
        (field (name "DB_TOLERANCE") "20%")
        (field (name "DB_VOLTAGE") "6.3V")
        (field (name "DB_MANUFACTURER_PART") "KEMET    C0805C226M9PAC")
        (field (name "DB_APPROVED_BY") "ISHIDDEN=T")
      )
      (libsource (lib "Database_Libs1") (part "C"))
    )
    (comp (ref "C676")
      (value "22uF")
      (footprint "SMD_0805_CAPC2012X145N")
      (fields
        (field (name "DB_PART_NUMBER") "CAP000043686")
        (field (name "DB_VALUE") "22uF")
        (field (name "DB_TOLERANCE") "20%")
        (field (name "DB_VOLTAGE") "6.3V")
        (field (name "DB_MANUFACTURER_PART") "KEMET    C0805C226M9PAC")
        (field (name "DB_APPROVED_BY") "ISHIDDEN=T")
      )
      (libsource (lib "Database_Libs1") (part "C"))
    )
    (comp (ref "C677")
      (value "220uF")
      (footprint "SMD_1210_CAPC3225X279N")
      (fields
        (field (name "DB_PART_NUMBER") "CAP000047355")
        (field (name "DB_VALUE") "220uF")
        (field (name "DB_TOLERANCE") "20%")
        (field (name "DB_VOLTAGE") "6.3V")
        (field (name "DB_MANUFACTURER_PART") "SAMSUNG    CL32A227MQVNNNE")
        (field (name "DB_APPROVED_BY") "VSN")
      )
      (libsource (lib "Database_Libs1") (part "C"))
    )
    (comp (ref "C678")
      (value "22uF")
      (footprint "SMD_0805_CAPC2012X145N")
      (fields
        (field (name "DB_PART_NUMBER") "CAP000043686")
        (field (name "DB_VALUE") "22uF")
        (field (name "DB_TOLERANCE") "20%")
        (field (name "DB_VOLTAGE") "6.3V")
        (field (name "DB_MANUFACTURER_PART") "KEMET    C0805C226M9PAC")
        (field (name "DB_APPROVED_BY") "ISHIDDEN=T")
      )
      (libsource (lib "Database_Libs1") (part "C"))
    )
    (comp (ref "C679")
      (value "22uF")
      (footprint "SMD_0805_CAPC2012X145N")
      (fields
        (field (name "DB_PART_NUMBER") "CAP000043686")
        (field (name "DB_VALUE") "22uF")
        (field (name "DB_TOLERANCE") "20%")
        (field (name "DB_VOLTAGE") "6.3V")
        (field (name "DB_MANUFACTURER_PART") "KEMET    C0805C226M9PAC")
        (field (name "DB_APPROVED_BY") "ISHIDDEN=T")
      )
      (libsource (lib "Database_Libs1") (part "C"))
    )
    (comp (ref "C680")
      (value "220uF")
      (footprint "SMD_1210_CAPC3225X279N")
      (fields
        (field (name "DB_PART_NUMBER") "CAP000047355")
        (field (name "DB_VALUE") "220uF")
        (field (name "DB_TOLERANCE") "20%")
        (field (name "DB_VOLTAGE") "6.3V")
        (field (name "DB_MANUFACTURER_PART") "SAMSUNG    CL32A227MQVNNNE")
        (field (name "DB_APPROVED_BY") "VSN")
      )
      (libsource (lib "Database_Libs1") (part "C"))
    )
    (comp (ref "C681")
      (value "22uF")
      (footprint "SMD_0805_CAPC2012X145N")
      (fields
        (field (name "DB_PART_NUMBER") "CAP000043686")
        (field (name "DB_VALUE") "22uF")
        (field (name "DB_TOLERANCE") "20%")
        (field (name "DB_VOLTAGE") "6.3V")
        (field (name "DB_MANUFACTURER_PART") "KEMET    C0805C226M9PAC")
        (field (name "DB_APPROVED_BY") "ISHIDDEN=T")
      )
      (libsource (lib "Database_Libs1") (part "C"))
    )
    (comp (ref "C686")
      (value "100uF")
      (footprint "SMD_1210_CAPC3225X270N")
      (fields
        (field (name "DB_PART_NUMBER") "CAP000043701")
        (field (name "DB_VALUE") "100uF")
        (field (name "DB_TOLERANCE") "20%")
        (field (name "DB_VOLTAGE") "6.3V")
        (field (name "DB_MANUFACTURER_PART") "KEMET    C1210C107M9PAC")
        (field (name "DB_APPROVED_BY") "ISHIDDEN=T")
      )
      (libsource (lib "Database_Libs1") (part "C"))
    )
    (comp (ref "C688")
      (value "10uF")
      (footprint "SMD_0805_CAPC2012X145N")
      (fields
        (field (name "DB_PART_NUMBER") "CAP000043636")
        (field (name "DB_VALUE") "10uF")
        (field (name "DB_TOLERANCE") "10%")
        (field (name "DB_VOLTAGE") "16V")
        (field (name "DB_MANUFACTURER_PART") "KEMET    C0805C106K4PAC")
        (field (name "DB_APPROVED_BY") "ISHIDDEN=T")
      )
      (libsource (lib "Database_Libs1") (part "C"))
    )
    (comp (ref "C689")
      (value "100uF")
      (footprint "SMD_1210_CAPC3225X270N")
      (fields
        (field (name "DB_PART_NUMBER") "CAP000043701")
        (field (name "DB_VALUE") "100uF")
        (field (name "DB_TOLERANCE") "20%")
        (field (name "DB_VOLTAGE") "6.3V")
        (field (name "DB_MANUFACTURER_PART") "KEMET    C1210C107M9PAC")
        (field (name "DB_APPROVED_BY") "ISHIDDEN=T")
      )
      (libsource (lib "Database_Libs1") (part "C"))
    )
    (comp (ref "C692")
      (value "100uF")
      (footprint "SMD_1210_CAPC3225X270N")
      (fields
        (field (name "DB_PART_NUMBER") "CAP000043701")
        (field (name "DB_VALUE") "100uF")
        (field (name "DB_TOLERANCE") "20%")
        (field (name "DB_VOLTAGE") "6.3V")
        (field (name "DB_MANUFACTURER_PART") "KEMET    C1210C107M9PAC")
        (field (name "DB_APPROVED_BY") "ISHIDDEN=T")
      )
      (libsource (lib "Database_Libs1") (part "C"))
    )
    (comp (ref "C695")
      (value "100uF")
      (footprint "SMD_1210_CAPC3225X270N")
      (fields
        (field (name "DB_PART_NUMBER") "CAP000043701")
        (field (name "DB_VALUE") "100uF")
        (field (name "DB_TOLERANCE") "20%")
        (field (name "DB_VOLTAGE") "6.3V")
        (field (name "DB_MANUFACTURER_PART") "KEMET    C1210C107M9PAC")
        (field (name "DB_APPROVED_BY") "ISHIDDEN=T")
      )
      (libsource (lib "Database_Libs1") (part "C"))
    )
    (comp (ref "C711")
      (value "10uF")
      (footprint "SMD_0805_CAPC2012X145N")
      (fields
        (field (name "DB_PART_NUMBER") "CAP000043636")
        (field (name "DB_VALUE") "10uF")
        (field (name "DB_TOLERANCE") "10%")
        (field (name "DB_VOLTAGE") "16V")
        (field (name "DB_MANUFACTURER_PART") "KEMET    C0805C106K4PAC")
        (field (name "DB_APPROVED_BY") "ISHIDDEN=T")
      )
      (libsource (lib "Database_Libs1") (part "C"))
    )
    (comp (ref "C712")
      (value "10uF")
      (footprint "SMD_0805_CAPC2012X145N")
      (fields
        (field (name "DB_PART_NUMBER") "CAP000043636")
        (field (name "DB_VALUE") "10uF")
        (field (name "DB_TOLERANCE") "10%")
        (field (name "DB_VOLTAGE") "16V")
        (field (name "DB_MANUFACTURER_PART") "KEMET    C0805C106K4PAC")
        (field (name "DB_APPROVED_BY") "ISHIDDEN=T")
      )
      (libsource (lib "Database_Libs1") (part "C"))
    )
    (comp (ref "C714")
      (value "10uF")
      (footprint "SMD_0805_CAPC2012X145N")
      (fields
        (field (name "DB_PART_NUMBER") "CAP000043636")
        (field (name "DB_VALUE") "10uF")
        (field (name "DB_TOLERANCE") "10%")
        (field (name "DB_VOLTAGE") "16V")
        (field (name "DB_MANUFACTURER_PART") "KEMET    C0805C106K4PAC")
        (field (name "DB_APPROVED_BY") "ISHIDDEN=T")
      )
      (libsource (lib "Database_Libs1") (part "C"))
    )
    (comp (ref "C715")
      (value "10uF")
      (footprint "SMD_0805_CAPC2012X145N")
      (fields
        (field (name "DB_PART_NUMBER") "CAP000043636")
        (field (name "DB_VALUE") "10uF")
        (field (name "DB_TOLERANCE") "10%")
        (field (name "DB_VOLTAGE") "16V")
        (field (name "DB_MANUFACTURER_PART") "KEMET    C0805C106K4PAC")
        (field (name "DB_APPROVED_BY") "ISHIDDEN=T")
      )
      (libsource (lib "Database_Libs1") (part "C"))
    )
    (comp (ref "C717")
      (value "10uF")
      (footprint "SMD_0805_CAPC2012X145N")
      (fields
        (field (name "DB_PART_NUMBER") "CAP000043636")
        (field (name "DB_VALUE") "10uF")
        (field (name "DB_TOLERANCE") "10%")
        (field (name "DB_VOLTAGE") "16V")
        (field (name "DB_MANUFACTURER_PART") "KEMET    C0805C106K4PAC")
        (field (name "DB_APPROVED_BY") "ISHIDDEN=T")
      )
      (libsource (lib "Database_Libs1") (part "C"))
    )
    (comp (ref "C742")
      (value "22uF")
      (footprint "SMD_0805_CAPC2012X145N")
      (fields
        (field (name "DB_PART_NUMBER") "CAP000043686")
        (field (name "DB_VALUE") "22uF")
        (field (name "DB_TOLERANCE") "20%")
        (field (name "DB_VOLTAGE") "6.3V")
        (field (name "DB_MANUFACTURER_PART") "KEMET    C0805C226M9PAC")
        (field (name "DB_APPROVED_BY") "ISHIDDEN=T")
      )
      (libsource (lib "Database_Libs1") (part "C"))
    )
    (comp (ref "C743")
      (value "220uF")
      (footprint "SMD_1210_CAPC3225X279N")
      (fields
        (field (name "DB_PART_NUMBER") "CAP000047355")
        (field (name "DB_VALUE") "220uF")
        (field (name "DB_TOLERANCE") "20%")
        (field (name "DB_VOLTAGE") "6.3V")
        (field (name "DB_MANUFACTURER_PART") "SAMSUNG    CL32A227MQVNNNE")
        (field (name "DB_APPROVED_BY") "VSN")
      )
      (libsource (lib "Database_Libs1") (part "C"))
    )
    (comp (ref "C744")
      (value "22uF")
      (footprint "SMD_0805_CAPC2012X145N")
      (fields
        (field (name "DB_PART_NUMBER") "CAP000043686")
        (field (name "DB_VALUE") "22uF")
        (field (name "DB_TOLERANCE") "20%")
        (field (name "DB_VOLTAGE") "6.3V")
        (field (name "DB_MANUFACTURER_PART") "KEMET    C0805C226M9PAC")
        (field (name "DB_APPROVED_BY") "ISHIDDEN=T")
      )
      (libsource (lib "Database_Libs1") (part "C"))
    )
    (comp (ref "C745")
      (value "22uF")
      (footprint "SMD_0805_CAPC2012X145N")
      (fields
        (field (name "DB_PART_NUMBER") "CAP000043686")
        (field (name "DB_VALUE") "22uF")
        (field (name "DB_TOLERANCE") "20%")
        (field (name "DB_VOLTAGE") "6.3V")
        (field (name "DB_MANUFACTURER_PART") "KEMET    C0805C226M9PAC")
        (field (name "DB_APPROVED_BY") "ISHIDDEN=T")
      )
      (libsource (lib "Database_Libs1") (part "C"))
    )
    (comp (ref "C746")
      (value "220uF")
      (footprint "SMD_1210_CAPC3225X279N")
      (fields
        (field (name "DB_PART_NUMBER") "CAP000047355")
        (field (name "DB_VALUE") "220uF")
        (field (name "DB_TOLERANCE") "20%")
        (field (name "DB_VOLTAGE") "6.3V")
        (field (name "DB_MANUFACTURER_PART") "SAMSUNG    CL32A227MQVNNNE")
        (field (name "DB_APPROVED_BY") "VSN")
      )
      (libsource (lib "Database_Libs1") (part "C"))
    )
    (comp (ref "C747")
      (value "22uF")
      (footprint "SMD_0805_CAPC2012X145N")
      (fields
        (field (name "DB_PART_NUMBER") "CAP000043686")
        (field (name "DB_VALUE") "22uF")
        (field (name "DB_TOLERANCE") "20%")
        (field (name "DB_VOLTAGE") "6.3V")
        (field (name "DB_MANUFACTURER_PART") "KEMET    C0805C226M9PAC")
        (field (name "DB_APPROVED_BY") "ISHIDDEN=T")
      )
      (libsource (lib "Database_Libs1") (part "C"))
    )
    (comp (ref "C748")
      (value "22uF")
      (footprint "SMD_0805_CAPC2012X145N")
      (fields
        (field (name "DB_PART_NUMBER") "CAP000043686")
        (field (name "DB_VALUE") "22uF")
        (field (name "DB_TOLERANCE") "20%")
        (field (name "DB_VOLTAGE") "6.3V")
        (field (name "DB_MANUFACTURER_PART") "KEMET    C0805C226M9PAC")
        (field (name "DB_APPROVED_BY") "ISHIDDEN=T")
      )
      (libsource (lib "Database_Libs1") (part "C"))
    )
    (comp (ref "C749")
      (value "220uF")
      (footprint "SMD_1210_CAPC3225X279N")
      (fields
        (field (name "DB_PART_NUMBER") "CAP000047355")
        (field (name "DB_VALUE") "220uF")
        (field (name "DB_TOLERANCE") "20%")
        (field (name "DB_VOLTAGE") "6.3V")
        (field (name "DB_MANUFACTURER_PART") "SAMSUNG    CL32A227MQVNNNE")
        (field (name "DB_APPROVED_BY") "VSN")
      )
      (libsource (lib "Database_Libs1") (part "C"))
    )
    (comp (ref "C750")
      (value "22uF")
      (footprint "SMD_0805_CAPC2012X145N")
      (fields
        (field (name "DB_PART_NUMBER") "CAP000043686")
        (field (name "DB_VALUE") "22uF")
        (field (name "DB_TOLERANCE") "20%")
        (field (name "DB_VOLTAGE") "6.3V")
        (field (name "DB_MANUFACTURER_PART") "KEMET    C0805C226M9PAC")
        (field (name "DB_APPROVED_BY") "ISHIDDEN=T")
      )
      (libsource (lib "Database_Libs1") (part "C"))
    )
    (comp (ref "C751")
      (value "22uF")
      (footprint "SMD_0805_CAPC2012X145N")
      (fields
        (field (name "DB_PART_NUMBER") "CAP000043686")
        (field (name "DB_VALUE") "22uF")
        (field (name "DB_TOLERANCE") "20%")
        (field (name "DB_VOLTAGE") "6.3V")
        (field (name "DB_MANUFACTURER_PART") "KEMET    C0805C226M9PAC")
        (field (name "DB_APPROVED_BY") "ISHIDDEN=T")
      )
      (libsource (lib "Database_Libs1") (part "C"))
    )
    (comp (ref "C752")
      (value "220uF")
      (footprint "SMD_1210_CAPC3225X279N")
      (fields
        (field (name "DB_PART_NUMBER") "CAP000047355")
        (field (name "DB_VALUE") "220uF")
        (field (name "DB_TOLERANCE") "20%")
        (field (name "DB_VOLTAGE") "6.3V")
        (field (name "DB_MANUFACTURER_PART") "SAMSUNG    CL32A227MQVNNNE")
        (field (name "DB_APPROVED_BY") "VSN")
      )
      (libsource (lib "Database_Libs1") (part "C"))
    )
    (comp (ref "C753")
      (value "22uF")
      (footprint "SMD_0805_CAPC2012X145N")
      (fields
        (field (name "DB_PART_NUMBER") "CAP000043686")
        (field (name "DB_VALUE") "22uF")
        (field (name "DB_TOLERANCE") "20%")
        (field (name "DB_VOLTAGE") "6.3V")
        (field (name "DB_MANUFACTURER_PART") "KEMET    C0805C226M9PAC")
        (field (name "DB_APPROVED_BY") "ISHIDDEN=T")
      )
      (libsource (lib "Database_Libs1") (part "C"))
    )
    (comp (ref "C754")
      (value "22uF")
      (footprint "SMD_0805_CAPC2012X145N")
      (fields
        (field (name "DB_PART_NUMBER") "CAP000043686")
        (field (name "DB_VALUE") "22uF")
        (field (name "DB_TOLERANCE") "20%")
        (field (name "DB_VOLTAGE") "6.3V")
        (field (name "DB_MANUFACTURER_PART") "KEMET    C0805C226M9PAC")
        (field (name "DB_APPROVED_BY") "ISHIDDEN=T")
      )
      (libsource (lib "Database_Libs1") (part "C"))
    )
    (comp (ref "C755")
      (value "220uF")
      (footprint "SMD_1210_CAPC3225X279N")
      (fields
        (field (name "DB_PART_NUMBER") "CAP000047355")
        (field (name "DB_VALUE") "220uF")
        (field (name "DB_TOLERANCE") "20%")
        (field (name "DB_VOLTAGE") "6.3V")
        (field (name "DB_MANUFACTURER_PART") "SAMSUNG    CL32A227MQVNNNE")
        (field (name "DB_APPROVED_BY") "VSN")
      )
      (libsource (lib "Database_Libs1") (part "C"))
    )
    (comp (ref "C756")
      (value "22uF")
      (footprint "SMD_0805_CAPC2012X145N")
      (fields
        (field (name "DB_PART_NUMBER") "CAP000043686")
        (field (name "DB_VALUE") "22uF")
        (field (name "DB_TOLERANCE") "20%")
        (field (name "DB_VOLTAGE") "6.3V")
        (field (name "DB_MANUFACTURER_PART") "KEMET    C0805C226M9PAC")
        (field (name "DB_APPROVED_BY") "ISHIDDEN=T")
      )
      (libsource (lib "Database_Libs1") (part "C"))
    )
    (comp (ref "C757")
      (value "22uF")
      (footprint "SMD_0805_CAPC2012X145N")
      (fields
        (field (name "DB_PART_NUMBER") "CAP000043686")
        (field (name "DB_VALUE") "22uF")
        (field (name "DB_TOLERANCE") "20%")
        (field (name "DB_VOLTAGE") "6.3V")
        (field (name "DB_MANUFACTURER_PART") "KEMET    C0805C226M9PAC")
        (field (name "DB_APPROVED_BY") "ISHIDDEN=T")
      )
      (libsource (lib "Database_Libs1") (part "C"))
    )
    (comp (ref "C758")
      (value "220uF")
      (footprint "SMD_1210_CAPC3225X279N")
      (fields
        (field (name "DB_PART_NUMBER") "CAP000047355")
        (field (name "DB_VALUE") "220uF")
        (field (name "DB_TOLERANCE") "20%")
        (field (name "DB_VOLTAGE") "6.3V")
        (field (name "DB_MANUFACTURER_PART") "SAMSUNG    CL32A227MQVNNNE")
        (field (name "DB_APPROVED_BY") "VSN")
      )
      (libsource (lib "Database_Libs1") (part "C"))
    )
    (comp (ref "C759")
      (value "22uF")
      (footprint "SMD_0805_CAPC2012X145N")
      (fields
        (field (name "DB_PART_NUMBER") "CAP000043686")
        (field (name "DB_VALUE") "22uF")
        (field (name "DB_TOLERANCE") "20%")
        (field (name "DB_VOLTAGE") "6.3V")
        (field (name "DB_MANUFACTURER_PART") "KEMET    C0805C226M9PAC")
        (field (name "DB_APPROVED_BY") "ISHIDDEN=T")
      )
      (libsource (lib "Database_Libs1") (part "C"))
    )
    (comp (ref "C760")
      (value "22uF")
      (footprint "SMD_0805_CAPC2012X145N")
      (fields
        (field (name "DB_PART_NUMBER") "CAP000043686")
        (field (name "DB_VALUE") "22uF")
        (field (name "DB_TOLERANCE") "20%")
        (field (name "DB_VOLTAGE") "6.3V")
        (field (name "DB_MANUFACTURER_PART") "KEMET    C0805C226M9PAC")
        (field (name "DB_APPROVED_BY") "ISHIDDEN=T")
      )
      (libsource (lib "Database_Libs1") (part "C"))
    )
    (comp (ref "C761")
      (value "220uF")
      (footprint "SMD_1210_CAPC3225X279N")
      (fields
        (field (name "DB_PART_NUMBER") "CAP000047355")
        (field (name "DB_VALUE") "220uF")
        (field (name "DB_TOLERANCE") "20%")
        (field (name "DB_VOLTAGE") "6.3V")
        (field (name "DB_MANUFACTURER_PART") "SAMSUNG    CL32A227MQVNNNE")
        (field (name "DB_APPROVED_BY") "VSN")
      )
      (libsource (lib "Database_Libs1") (part "C"))
    )
    (comp (ref "C762")
      (value "22uF")
      (footprint "SMD_0805_CAPC2012X145N")
      (fields
        (field (name "DB_PART_NUMBER") "CAP000043686")
        (field (name "DB_VALUE") "22uF")
        (field (name "DB_TOLERANCE") "20%")
        (field (name "DB_VOLTAGE") "6.3V")
        (field (name "DB_MANUFACTURER_PART") "KEMET    C0805C226M9PAC")
        (field (name "DB_APPROVED_BY") "ISHIDDEN=T")
      )
      (libsource (lib "Database_Libs1") (part "C"))
    )
    (comp (ref "C763")
      (value "22uF")
      (footprint "SMD_0805_CAPC2012X145N")
      (fields
        (field (name "DB_PART_NUMBER") "CAP000043686")
        (field (name "DB_VALUE") "22uF")
        (field (name "DB_TOLERANCE") "20%")
        (field (name "DB_VOLTAGE") "6.3V")
        (field (name "DB_MANUFACTURER_PART") "KEMET    C0805C226M9PAC")
        (field (name "DB_APPROVED_BY") "ISHIDDEN=T")
      )
      (libsource (lib "Database_Libs1") (part "C"))
    )
    (comp (ref "C764")
      (value "220uF")
      (footprint "SMD_1210_CAPC3225X279N")
      (fields
        (field (name "DB_PART_NUMBER") "CAP000047355")
        (field (name "DB_VALUE") "220uF")
        (field (name "DB_TOLERANCE") "20%")
        (field (name "DB_VOLTAGE") "6.3V")
        (field (name "DB_MANUFACTURER_PART") "SAMSUNG    CL32A227MQVNNNE")
        (field (name "DB_APPROVED_BY") "VSN")
      )
      (libsource (lib "Database_Libs1") (part "C"))
    )
    (comp (ref "C765")
      (value "22uF")
      (footprint "SMD_0805_CAPC2012X145N")
      (fields
        (field (name "DB_PART_NUMBER") "CAP000043686")
        (field (name "DB_VALUE") "22uF")
        (field (name "DB_TOLERANCE") "20%")
        (field (name "DB_VOLTAGE") "6.3V")
        (field (name "DB_MANUFACTURER_PART") "KEMET    C0805C226M9PAC")
        (field (name "DB_APPROVED_BY") "ISHIDDEN=T")
      )
      (libsource (lib "Database_Libs1") (part "C"))
    )
    (comp (ref "C766")
      (value "22uF")
      (footprint "SMD_0805_CAPC2012X145N")
      (fields
        (field (name "DB_PART_NUMBER") "CAP000043686")
        (field (name "DB_VALUE") "22uF")
        (field (name "DB_TOLERANCE") "20%")
        (field (name "DB_VOLTAGE") "6.3V")
        (field (name "DB_MANUFACTURER_PART") "KEMET    C0805C226M9PAC")
        (field (name "DB_APPROVED_BY") "ISHIDDEN=T")
      )
      (libsource (lib "Database_Libs1") (part "C"))
    )
    (comp (ref "C767")
      (value "220uF")
      (footprint "SMD_1210_CAPC3225X279N")
      (fields
        (field (name "DB_PART_NUMBER") "CAP000047355")
        (field (name "DB_VALUE") "220uF")
        (field (name "DB_TOLERANCE") "20%")
        (field (name "DB_VOLTAGE") "6.3V")
        (field (name "DB_MANUFACTURER_PART") "SAMSUNG    CL32A227MQVNNNE")
        (field (name "DB_APPROVED_BY") "VSN")
      )
      (libsource (lib "Database_Libs1") (part "C"))
    )
    (comp (ref "C768")
      (value "22uF")
      (footprint "SMD_0805_CAPC2012X145N")
      (fields
        (field (name "DB_PART_NUMBER") "CAP000043686")
        (field (name "DB_VALUE") "22uF")
        (field (name "DB_TOLERANCE") "20%")
        (field (name "DB_VOLTAGE") "6.3V")
        (field (name "DB_MANUFACTURER_PART") "KEMET    C0805C226M9PAC")
        (field (name "DB_APPROVED_BY") "ISHIDDEN=T")
      )
      (libsource (lib "Database_Libs1") (part "C"))
    )
    (comp (ref "C769")
      (value "22uF")
      (footprint "SMD_0805_CAPC2012X145N")
      (fields
        (field (name "DB_PART_NUMBER") "CAP000043686")
        (field (name "DB_VALUE") "22uF")
        (field (name "DB_TOLERANCE") "20%")
        (field (name "DB_VOLTAGE") "6.3V")
        (field (name "DB_MANUFACTURER_PART") "KEMET    C0805C226M9PAC")
        (field (name "DB_APPROVED_BY") "ISHIDDEN=T")
      )
      (libsource (lib "Database_Libs1") (part "C"))
    )
    (comp (ref "C770")
      (value "220uF")
      (footprint "SMD_1210_CAPC3225X279N")
      (fields
        (field (name "DB_PART_NUMBER") "CAP000047355")
        (field (name "DB_VALUE") "220uF")
        (field (name "DB_TOLERANCE") "20%")
        (field (name "DB_VOLTAGE") "6.3V")
        (field (name "DB_MANUFACTURER_PART") "SAMSUNG    CL32A227MQVNNNE")
        (field (name "DB_APPROVED_BY") "VSN")
      )
      (libsource (lib "Database_Libs1") (part "C"))
    )
    (comp (ref "C771")
      (value "22uF")
      (footprint "SMD_0805_CAPC2012X145N")
      (fields
        (field (name "DB_PART_NUMBER") "CAP000043686")
        (field (name "DB_VALUE") "22uF")
        (field (name "DB_TOLERANCE") "20%")
        (field (name "DB_VOLTAGE") "6.3V")
        (field (name "DB_MANUFACTURER_PART") "KEMET    C0805C226M9PAC")
        (field (name "DB_APPROVED_BY") "ISHIDDEN=T")
      )
      (libsource (lib "Database_Libs1") (part "C"))
    )
    (comp (ref "C776")
      (value "100uF")
      (footprint "SMD_1210_CAPC3225X270N")
      (fields
        (field (name "DB_PART_NUMBER") "CAP000043701")
        (field (name "DB_VALUE") "100uF")
        (field (name "DB_TOLERANCE") "20%")
        (field (name "DB_VOLTAGE") "6.3V")
        (field (name "DB_MANUFACTURER_PART") "KEMET    C1210C107M9PAC")
        (field (name "DB_APPROVED_BY") "ISHIDDEN=T")
      )
      (libsource (lib "Database_Libs1") (part "C"))
    )
    (comp (ref "C779")
      (value "100uF")
      (footprint "SMD_1210_CAPC3225X270N")
      (fields
        (field (name "DB_PART_NUMBER") "CAP000043701")
        (field (name "DB_VALUE") "100uF")
        (field (name "DB_TOLERANCE") "20%")
        (field (name "DB_VOLTAGE") "6.3V")
        (field (name "DB_MANUFACTURER_PART") "KEMET    C1210C107M9PAC")
        (field (name "DB_APPROVED_BY") "ISHIDDEN=T")
      )
      (libsource (lib "Database_Libs1") (part "C"))
    )
    (comp (ref "C782")
      (value "100uF")
      (footprint "SMD_1210_CAPC3225X270N")
      (fields
        (field (name "DB_PART_NUMBER") "CAP000043701")
        (field (name "DB_VALUE") "100uF")
        (field (name "DB_TOLERANCE") "20%")
        (field (name "DB_VOLTAGE") "6.3V")
        (field (name "DB_MANUFACTURER_PART") "KEMET    C1210C107M9PAC")
        (field (name "DB_APPROVED_BY") "ISHIDDEN=T")
      )
      (libsource (lib "Database_Libs1") (part "C"))
    )
    (comp (ref "C785")
      (value "100uF")
      (footprint "SMD_1210_CAPC3225X270N")
      (fields
        (field (name "DB_PART_NUMBER") "CAP000043701")
        (field (name "DB_VALUE") "100uF")
        (field (name "DB_TOLERANCE") "20%")
        (field (name "DB_VOLTAGE") "6.3V")
        (field (name "DB_MANUFACTURER_PART") "KEMET    C1210C107M9PAC")
        (field (name "DB_APPROVED_BY") "ISHIDDEN=T")
      )
      (libsource (lib "Database_Libs1") (part "C"))
    )
    (comp (ref "C807")
      (value "10uF")
      (footprint "SMD_0805_CAPC2012X145N")
      (fields
        (field (name "DB_PART_NUMBER") "CAP000043636")
        (field (name "DB_VALUE") "10uF")
        (field (name "DB_TOLERANCE") "10%")
        (field (name "DB_VOLTAGE") "16V")
        (field (name "DB_MANUFACTURER_PART") "KEMET    C0805C106K4PAC")
        (field (name "DB_APPROVED_BY") "ISHIDDEN=T")
      )
      (libsource (lib "Database_Libs1") (part "C"))
    )
    (comp (ref "C808")
      (value "10uF")
      (footprint "SMD_0805_CAPC2012X145N")
      (fields
        (field (name "DB_PART_NUMBER") "CAP000043636")
        (field (name "DB_VALUE") "10uF")
        (field (name "DB_TOLERANCE") "10%")
        (field (name "DB_VOLTAGE") "16V")
        (field (name "DB_MANUFACTURER_PART") "KEMET    C0805C106K4PAC")
        (field (name "DB_APPROVED_BY") "ISHIDDEN=T")
      )
      (libsource (lib "Database_Libs1") (part "C"))
    )
    (comp (ref "C810")
      (value "10uF")
      (footprint "SMD_0805_CAPC2012X145N")
      (fields
        (field (name "DB_PART_NUMBER") "CAP000043636")
        (field (name "DB_VALUE") "10uF")
        (field (name "DB_TOLERANCE") "10%")
        (field (name "DB_VOLTAGE") "16V")
        (field (name "DB_MANUFACTURER_PART") "KEMET    C0805C106K4PAC")
        (field (name "DB_APPROVED_BY") "ISHIDDEN=T")
      )
      (libsource (lib "Database_Libs1") (part "C"))
    )
    (comp (ref "C811")
      (value "10uF")
      (footprint "SMD_0805_CAPC2012X145N")
      (fields
        (field (name "DB_PART_NUMBER") "CAP000043636")
        (field (name "DB_VALUE") "10uF")
        (field (name "DB_TOLERANCE") "10%")
        (field (name "DB_VOLTAGE") "16V")
        (field (name "DB_MANUFACTURER_PART") "KEMET    C0805C106K4PAC")
        (field (name "DB_APPROVED_BY") "ISHIDDEN=T")
      )
      (libsource (lib "Database_Libs1") (part "C"))
    )
    (comp (ref "C813")
      (value "10uF")
      (footprint "SMD_0805_CAPC2012X145N")
      (fields
        (field (name "DB_PART_NUMBER") "CAP000043636")
        (field (name "DB_VALUE") "10uF")
        (field (name "DB_TOLERANCE") "10%")
        (field (name "DB_VOLTAGE") "16V")
        (field (name "DB_MANUFACTURER_PART") "KEMET    C0805C106K4PAC")
        (field (name "DB_APPROVED_BY") "ISHIDDEN=T")
      )
      (libsource (lib "Database_Libs1") (part "C"))
    )
    (comp (ref "C814")
      (value "10uF")
      (footprint "SMD_0805_CAPC2012X145N")
      (fields
        (field (name "DB_PART_NUMBER") "CAP000043636")
        (field (name "DB_VALUE") "10uF")
        (field (name "DB_TOLERANCE") "10%")
        (field (name "DB_VOLTAGE") "16V")
        (field (name "DB_MANUFACTURER_PART") "KEMET    C0805C106K4PAC")
        (field (name "DB_APPROVED_BY") "ISHIDDEN=T")
      )
      (libsource (lib "Database_Libs1") (part "C"))
    )
    (comp (ref "C832")
      (value "22uF")
      (footprint "SMD_0805_CAPC2012X145N")
      (fields
        (field (name "DB_PART_NUMBER") "CAP000043686")
        (field (name "DB_VALUE") "22uF")
        (field (name "DB_TOLERANCE") "20%")
        (field (name "DB_VOLTAGE") "6.3V")
        (field (name "DB_MANUFACTURER_PART") "KEMET    C0805C226M9PAC")
        (field (name "DB_APPROVED_BY") "ISHIDDEN=T")
      )
      (libsource (lib "Database_Libs1") (part "C"))
    )
    (comp (ref "C833")
      (value "220uF")
      (footprint "SMD_1210_CAPC3225X279N")
      (fields
        (field (name "DB_PART_NUMBER") "CAP000047355")
        (field (name "DB_VALUE") "220uF")
        (field (name "DB_TOLERANCE") "20%")
        (field (name "DB_VOLTAGE") "6.3V")
        (field (name "DB_MANUFACTURER_PART") "SAMSUNG    CL32A227MQVNNNE")
        (field (name "DB_APPROVED_BY") "VSN")
      )
      (libsource (lib "Database_Libs1") (part "C"))
    )
    (comp (ref "C834")
      (value "22uF")
      (footprint "SMD_0805_CAPC2012X145N")
      (fields
        (field (name "DB_PART_NUMBER") "CAP000043686")
        (field (name "DB_VALUE") "22uF")
        (field (name "DB_TOLERANCE") "20%")
        (field (name "DB_VOLTAGE") "6.3V")
        (field (name "DB_MANUFACTURER_PART") "KEMET    C0805C226M9PAC")
        (field (name "DB_APPROVED_BY") "ISHIDDEN=T")
      )
      (libsource (lib "Database_Libs1") (part "C"))
    )
    (comp (ref "C835")
      (value "22uF")
      (footprint "SMD_0805_CAPC2012X145N")
      (fields
        (field (name "DB_PART_NUMBER") "CAP000043686")
        (field (name "DB_VALUE") "22uF")
        (field (name "DB_TOLERANCE") "20%")
        (field (name "DB_VOLTAGE") "6.3V")
        (field (name "DB_MANUFACTURER_PART") "KEMET    C0805C226M9PAC")
        (field (name "DB_APPROVED_BY") "ISHIDDEN=T")
      )
      (libsource (lib "Database_Libs1") (part "C"))
    )
    (comp (ref "C836")
      (value "220uF")
      (footprint "SMD_1210_CAPC3225X279N")
      (fields
        (field (name "DB_PART_NUMBER") "CAP000047355")
        (field (name "DB_VALUE") "220uF")
        (field (name "DB_TOLERANCE") "20%")
        (field (name "DB_VOLTAGE") "6.3V")
        (field (name "DB_MANUFACTURER_PART") "SAMSUNG    CL32A227MQVNNNE")
        (field (name "DB_APPROVED_BY") "VSN")
      )
      (libsource (lib "Database_Libs1") (part "C"))
    )
    (comp (ref "C837")
      (value "22uF")
      (footprint "SMD_0805_CAPC2012X145N")
      (fields
        (field (name "DB_PART_NUMBER") "CAP000043686")
        (field (name "DB_VALUE") "22uF")
        (field (name "DB_TOLERANCE") "20%")
        (field (name "DB_VOLTAGE") "6.3V")
        (field (name "DB_MANUFACTURER_PART") "KEMET    C0805C226M9PAC")
        (field (name "DB_APPROVED_BY") "ISHIDDEN=T")
      )
      (libsource (lib "Database_Libs1") (part "C"))
    )
    (comp (ref "C838")
      (value "22uF")
      (footprint "SMD_0805_CAPC2012X145N")
      (fields
        (field (name "DB_PART_NUMBER") "CAP000043686")
        (field (name "DB_VALUE") "22uF")
        (field (name "DB_TOLERANCE") "20%")
        (field (name "DB_VOLTAGE") "6.3V")
        (field (name "DB_MANUFACTURER_PART") "KEMET    C0805C226M9PAC")
        (field (name "DB_APPROVED_BY") "ISHIDDEN=T")
      )
      (libsource (lib "Database_Libs1") (part "C"))
    )
    (comp (ref "C839")
      (value "220uF")
      (footprint "SMD_1210_CAPC3225X279N")
      (fields
        (field (name "DB_PART_NUMBER") "CAP000047355")
        (field (name "DB_VALUE") "220uF")
        (field (name "DB_TOLERANCE") "20%")
        (field (name "DB_VOLTAGE") "6.3V")
        (field (name "DB_MANUFACTURER_PART") "SAMSUNG    CL32A227MQVNNNE")
        (field (name "DB_APPROVED_BY") "VSN")
      )
      (libsource (lib "Database_Libs1") (part "C"))
    )
    (comp (ref "C840")
      (value "22uF")
      (footprint "SMD_0805_CAPC2012X145N")
      (fields
        (field (name "DB_PART_NUMBER") "CAP000043686")
        (field (name "DB_VALUE") "22uF")
        (field (name "DB_TOLERANCE") "20%")
        (field (name "DB_VOLTAGE") "6.3V")
        (field (name "DB_MANUFACTURER_PART") "KEMET    C0805C226M9PAC")
        (field (name "DB_APPROVED_BY") "ISHIDDEN=T")
      )
      (libsource (lib "Database_Libs1") (part "C"))
    )
    (comp (ref "C841")
      (value "22uF")
      (footprint "SMD_0805_CAPC2012X145N")
      (fields
        (field (name "DB_PART_NUMBER") "CAP000043686")
        (field (name "DB_VALUE") "22uF")
        (field (name "DB_TOLERANCE") "20%")
        (field (name "DB_VOLTAGE") "6.3V")
        (field (name "DB_MANUFACTURER_PART") "KEMET    C0805C226M9PAC")
        (field (name "DB_APPROVED_BY") "ISHIDDEN=T")
      )
      (libsource (lib "Database_Libs1") (part "C"))
    )
    (comp (ref "C842")
      (value "220uF")
      (footprint "SMD_1210_CAPC3225X279N")
      (fields
        (field (name "DB_PART_NUMBER") "CAP000047355")
        (field (name "DB_VALUE") "220uF")
        (field (name "DB_TOLERANCE") "20%")
        (field (name "DB_VOLTAGE") "6.3V")
        (field (name "DB_MANUFACTURER_PART") "SAMSUNG    CL32A227MQVNNNE")
        (field (name "DB_APPROVED_BY") "VSN")
      )
      (libsource (lib "Database_Libs1") (part "C"))
    )
    (comp (ref "C843")
      (value "22uF")
      (footprint "SMD_0805_CAPC2012X145N")
      (fields
        (field (name "DB_PART_NUMBER") "CAP000043686")
        (field (name "DB_VALUE") "22uF")
        (field (name "DB_TOLERANCE") "20%")
        (field (name "DB_VOLTAGE") "6.3V")
        (field (name "DB_MANUFACTURER_PART") "KEMET    C0805C226M9PAC")
        (field (name "DB_APPROVED_BY") "ISHIDDEN=T")
      )
      (libsource (lib "Database_Libs1") (part "C"))
    )
    (comp (ref "C844")
      (value "22uF")
      (footprint "SMD_0805_CAPC2012X145N")
      (fields
        (field (name "DB_PART_NUMBER") "CAP000043686")
        (field (name "DB_VALUE") "22uF")
        (field (name "DB_TOLERANCE") "20%")
        (field (name "DB_VOLTAGE") "6.3V")
        (field (name "DB_MANUFACTURER_PART") "KEMET    C0805C226M9PAC")
        (field (name "DB_APPROVED_BY") "ISHIDDEN=T")
      )
      (libsource (lib "Database_Libs1") (part "C"))
    )
    (comp (ref "C845")
      (value "220uF")
      (footprint "SMD_1210_CAPC3225X279N")
      (fields
        (field (name "DB_PART_NUMBER") "CAP000047355")
        (field (name "DB_VALUE") "220uF")
        (field (name "DB_TOLERANCE") "20%")
        (field (name "DB_VOLTAGE") "6.3V")
        (field (name "DB_MANUFACTURER_PART") "SAMSUNG    CL32A227MQVNNNE")
        (field (name "DB_APPROVED_BY") "VSN")
      )
      (libsource (lib "Database_Libs1") (part "C"))
    )
    (comp (ref "C846")
      (value "22uF")
      (footprint "SMD_0805_CAPC2012X145N")
      (fields
        (field (name "DB_PART_NUMBER") "CAP000043686")
        (field (name "DB_VALUE") "22uF")
        (field (name "DB_TOLERANCE") "20%")
        (field (name "DB_VOLTAGE") "6.3V")
        (field (name "DB_MANUFACTURER_PART") "KEMET    C0805C226M9PAC")
        (field (name "DB_APPROVED_BY") "ISHIDDEN=T")
      )
      (libsource (lib "Database_Libs1") (part "C"))
    )
    (comp (ref "C847")
      (value "22uF")
      (footprint "SMD_0805_CAPC2012X145N")
      (fields
        (field (name "DB_PART_NUMBER") "CAP000043686")
        (field (name "DB_VALUE") "22uF")
        (field (name "DB_TOLERANCE") "20%")
        (field (name "DB_VOLTAGE") "6.3V")
        (field (name "DB_MANUFACTURER_PART") "KEMET    C0805C226M9PAC")
        (field (name "DB_APPROVED_BY") "ISHIDDEN=T")
      )
      (libsource (lib "Database_Libs1") (part "C"))
    )
    (comp (ref "C848")
      (value "220uF")
      (footprint "SMD_1210_CAPC3225X279N")
      (fields
        (field (name "DB_PART_NUMBER") "CAP000047355")
        (field (name "DB_VALUE") "220uF")
        (field (name "DB_TOLERANCE") "20%")
        (field (name "DB_VOLTAGE") "6.3V")
        (field (name "DB_MANUFACTURER_PART") "SAMSUNG    CL32A227MQVNNNE")
        (field (name "DB_APPROVED_BY") "VSN")
      )
      (libsource (lib "Database_Libs1") (part "C"))
    )
    (comp (ref "C849")
      (value "22uF")
      (footprint "SMD_0805_CAPC2012X145N")
      (fields
        (field (name "DB_PART_NUMBER") "CAP000043686")
        (field (name "DB_VALUE") "22uF")
        (field (name "DB_TOLERANCE") "20%")
        (field (name "DB_VOLTAGE") "6.3V")
        (field (name "DB_MANUFACTURER_PART") "KEMET    C0805C226M9PAC")
        (field (name "DB_APPROVED_BY") "ISHIDDEN=T")
      )
      (libsource (lib "Database_Libs1") (part "C"))
    )
    (comp (ref "C850")
      (value "22uF")
      (footprint "SMD_0805_CAPC2012X145N")
      (fields
        (field (name "DB_PART_NUMBER") "CAP000043686")
        (field (name "DB_VALUE") "22uF")
        (field (name "DB_TOLERANCE") "20%")
        (field (name "DB_VOLTAGE") "6.3V")
        (field (name "DB_MANUFACTURER_PART") "KEMET    C0805C226M9PAC")
        (field (name "DB_APPROVED_BY") "ISHIDDEN=T")
      )
      (libsource (lib "Database_Libs1") (part "C"))
    )
    (comp (ref "C851")
      (value "220uF")
      (footprint "SMD_1210_CAPC3225X279N")
      (fields
        (field (name "DB_PART_NUMBER") "CAP000047355")
        (field (name "DB_VALUE") "220uF")
        (field (name "DB_TOLERANCE") "20%")
        (field (name "DB_VOLTAGE") "6.3V")
        (field (name "DB_MANUFACTURER_PART") "SAMSUNG    CL32A227MQVNNNE")
        (field (name "DB_APPROVED_BY") "VSN")
      )
      (libsource (lib "Database_Libs1") (part "C"))
    )
    (comp (ref "C852")
      (value "22uF")
      (footprint "SMD_0805_CAPC2012X145N")
      (fields
        (field (name "DB_PART_NUMBER") "CAP000043686")
        (field (name "DB_VALUE") "22uF")
        (field (name "DB_TOLERANCE") "20%")
        (field (name "DB_VOLTAGE") "6.3V")
        (field (name "DB_MANUFACTURER_PART") "KEMET    C0805C226M9PAC")
        (field (name "DB_APPROVED_BY") "ISHIDDEN=T")
      )
      (libsource (lib "Database_Libs1") (part "C"))
    )
    (comp (ref "C853")
      (value "22uF")
      (footprint "SMD_0805_CAPC2012X145N")
      (fields
        (field (name "DB_PART_NUMBER") "CAP000043686")
        (field (name "DB_VALUE") "22uF")
        (field (name "DB_TOLERANCE") "20%")
        (field (name "DB_VOLTAGE") "6.3V")
        (field (name "DB_MANUFACTURER_PART") "KEMET    C0805C226M9PAC")
        (field (name "DB_APPROVED_BY") "ISHIDDEN=T")
      )
      (libsource (lib "Database_Libs1") (part "C"))
    )
    (comp (ref "C854")
      (value "220uF")
      (footprint "SMD_1210_CAPC3225X279N")
      (fields
        (field (name "DB_PART_NUMBER") "CAP000047355")
        (field (name "DB_VALUE") "220uF")
        (field (name "DB_TOLERANCE") "20%")
        (field (name "DB_VOLTAGE") "6.3V")
        (field (name "DB_MANUFACTURER_PART") "SAMSUNG    CL32A227MQVNNNE")
        (field (name "DB_APPROVED_BY") "VSN")
      )
      (libsource (lib "Database_Libs1") (part "C"))
    )
    (comp (ref "C855")
      (value "22uF")
      (footprint "SMD_0805_CAPC2012X145N")
      (fields
        (field (name "DB_PART_NUMBER") "CAP000043686")
        (field (name "DB_VALUE") "22uF")
        (field (name "DB_TOLERANCE") "20%")
        (field (name "DB_VOLTAGE") "6.3V")
        (field (name "DB_MANUFACTURER_PART") "KEMET    C0805C226M9PAC")
        (field (name "DB_APPROVED_BY") "ISHIDDEN=T")
      )
      (libsource (lib "Database_Libs1") (part "C"))
    )
    (comp (ref "C856")
      (value "22uF")
      (footprint "SMD_0805_CAPC2012X145N")
      (fields
        (field (name "DB_PART_NUMBER") "CAP000043686")
        (field (name "DB_VALUE") "22uF")
        (field (name "DB_TOLERANCE") "20%")
        (field (name "DB_VOLTAGE") "6.3V")
        (field (name "DB_MANUFACTURER_PART") "KEMET    C0805C226M9PAC")
        (field (name "DB_APPROVED_BY") "ISHIDDEN=T")
      )
      (libsource (lib "Database_Libs1") (part "C"))
    )
    (comp (ref "C857")
      (value "220uF")
      (footprint "SMD_1210_CAPC3225X279N")
      (fields
        (field (name "DB_PART_NUMBER") "CAP000047355")
        (field (name "DB_VALUE") "220uF")
        (field (name "DB_TOLERANCE") "20%")
        (field (name "DB_VOLTAGE") "6.3V")
        (field (name "DB_MANUFACTURER_PART") "SAMSUNG    CL32A227MQVNNNE")
        (field (name "DB_APPROVED_BY") "VSN")
      )
      (libsource (lib "Database_Libs1") (part "C"))
    )
    (comp (ref "C858")
      (value "22uF")
      (footprint "SMD_0805_CAPC2012X145N")
      (fields
        (field (name "DB_PART_NUMBER") "CAP000043686")
        (field (name "DB_VALUE") "22uF")
        (field (name "DB_TOLERANCE") "20%")
        (field (name "DB_VOLTAGE") "6.3V")
        (field (name "DB_MANUFACTURER_PART") "KEMET    C0805C226M9PAC")
        (field (name "DB_APPROVED_BY") "ISHIDDEN=T")
      )
      (libsource (lib "Database_Libs1") (part "C"))
    )
    (comp (ref "C859")
      (value "22uF")
      (footprint "SMD_0805_CAPC2012X145N")
      (fields
        (field (name "DB_PART_NUMBER") "CAP000043686")
        (field (name "DB_VALUE") "22uF")
        (field (name "DB_TOLERANCE") "20%")
        (field (name "DB_VOLTAGE") "6.3V")
        (field (name "DB_MANUFACTURER_PART") "KEMET    C0805C226M9PAC")
        (field (name "DB_APPROVED_BY") "ISHIDDEN=T")
      )
      (libsource (lib "Database_Libs1") (part "C"))
    )
    (comp (ref "C860")
      (value "220uF")
      (footprint "SMD_1210_CAPC3225X279N")
      (fields
        (field (name "DB_PART_NUMBER") "CAP000047355")
        (field (name "DB_VALUE") "220uF")
        (field (name "DB_TOLERANCE") "20%")
        (field (name "DB_VOLTAGE") "6.3V")
        (field (name "DB_MANUFACTURER_PART") "SAMSUNG    CL32A227MQVNNNE")
        (field (name "DB_APPROVED_BY") "VSN")
      )
      (libsource (lib "Database_Libs1") (part "C"))
    )
    (comp (ref "C861")
      (value "22uF")
      (footprint "SMD_0805_CAPC2012X145N")
      (fields
        (field (name "DB_PART_NUMBER") "CAP000043686")
        (field (name "DB_VALUE") "22uF")
        (field (name "DB_TOLERANCE") "20%")
        (field (name "DB_VOLTAGE") "6.3V")
        (field (name "DB_MANUFACTURER_PART") "KEMET    C0805C226M9PAC")
        (field (name "DB_APPROVED_BY") "ISHIDDEN=T")
      )
      (libsource (lib "Database_Libs1") (part "C"))
    )
    (comp (ref "C866")
      (value "100uF")
      (footprint "SMD_1210_CAPC3225X270N")
      (fields
        (field (name "DB_PART_NUMBER") "CAP000043701")
        (field (name "DB_VALUE") "100uF")
        (field (name "DB_TOLERANCE") "20%")
        (field (name "DB_VOLTAGE") "6.3V")
        (field (name "DB_MANUFACTURER_PART") "KEMET    C1210C107M9PAC")
        (field (name "DB_APPROVED_BY") "ISHIDDEN=T")
      )
      (libsource (lib "Database_Libs1") (part "C"))
    )
    (comp (ref "C868")
      (value "10uF")
      (footprint "SMD_0805_CAPC2012X145N")
      (fields
        (field (name "DB_PART_NUMBER") "CAP000043636")
        (field (name "DB_VALUE") "10uF")
        (field (name "DB_TOLERANCE") "10%")
        (field (name "DB_VOLTAGE") "16V")
        (field (name "DB_MANUFACTURER_PART") "KEMET    C0805C106K4PAC")
        (field (name "DB_APPROVED_BY") "ISHIDDEN=T")
      )
      (libsource (lib "Database_Libs1") (part "C"))
    )
    (comp (ref "C869")
      (value "100uF")
      (footprint "SMD_1210_CAPC3225X270N")
      (fields
        (field (name "DB_PART_NUMBER") "CAP000043701")
        (field (name "DB_VALUE") "100uF")
        (field (name "DB_TOLERANCE") "20%")
        (field (name "DB_VOLTAGE") "6.3V")
        (field (name "DB_MANUFACTURER_PART") "KEMET    C1210C107M9PAC")
        (field (name "DB_APPROVED_BY") "ISHIDDEN=T")
      )
      (libsource (lib "Database_Libs1") (part "C"))
    )
    (comp (ref "C872")
      (value "100uF")
      (footprint "SMD_1210_CAPC3225X270N")
      (fields
        (field (name "DB_PART_NUMBER") "CAP000043701")
        (field (name "DB_VALUE") "100uF")
        (field (name "DB_TOLERANCE") "20%")
        (field (name "DB_VOLTAGE") "6.3V")
        (field (name "DB_MANUFACTURER_PART") "KEMET    C1210C107M9PAC")
        (field (name "DB_APPROVED_BY") "ISHIDDEN=T")
      )
      (libsource (lib "Database_Libs1") (part "C"))
    )
    (comp (ref "C876")
      (value "10uF")
      (footprint "SMD_0805_CAPC2012X145N")
      (fields
        (field (name "DB_PART_NUMBER") "CAP000043636")
        (field (name "DB_VALUE") "10uF")
        (field (name "DB_TOLERANCE") "10%")
        (field (name "DB_VOLTAGE") "16V")
        (field (name "DB_MANUFACTURER_PART") "KEMET    C0805C106K4PAC")
        (field (name "DB_APPROVED_BY") "ISHIDDEN=T")
      )
      (libsource (lib "Database_Libs1") (part "C"))
    )
    (comp (ref "C877")
      (value "10uF")
      (footprint "SMD_0805_CAPC2012X145N")
      (fields
        (field (name "DB_PART_NUMBER") "CAP000043636")
        (field (name "DB_VALUE") "10uF")
        (field (name "DB_TOLERANCE") "10%")
        (field (name "DB_VOLTAGE") "16V")
        (field (name "DB_MANUFACTURER_PART") "KEMET    C0805C106K4PAC")
        (field (name "DB_APPROVED_BY") "ISHIDDEN=T")
      )
      (libsource (lib "Database_Libs1") (part "C"))
    )
    (comp (ref "C879")
      (value "10uF")
      (footprint "SMD_0805_CAPC2012X145N")
      (fields
        (field (name "DB_PART_NUMBER") "CAP000043636")
        (field (name "DB_VALUE") "10uF")
        (field (name "DB_TOLERANCE") "10%")
        (field (name "DB_VOLTAGE") "16V")
        (field (name "DB_MANUFACTURER_PART") "KEMET    C0805C106K4PAC")
        (field (name "DB_APPROVED_BY") "ISHIDDEN=T")
      )
      (libsource (lib "Database_Libs1") (part "C"))
    )
    (comp (ref "C880")
      (value "10uF")
      (footprint "SMD_0805_CAPC2012X145N")
      (fields
        (field (name "DB_PART_NUMBER") "CAP000043636")
        (field (name "DB_VALUE") "10uF")
        (field (name "DB_TOLERANCE") "10%")
        (field (name "DB_VOLTAGE") "16V")
        (field (name "DB_MANUFACTURER_PART") "KEMET    C0805C106K4PAC")
        (field (name "DB_APPROVED_BY") "ISHIDDEN=T")
      )
      (libsource (lib "Database_Libs1") (part "C"))
    )
    (comp (ref "C882")
      (value "10uF")
      (footprint "SMD_0805_CAPC2012X145N")
      (fields
        (field (name "DB_PART_NUMBER") "CAP000043636")
        (field (name "DB_VALUE") "10uF")
        (field (name "DB_TOLERANCE") "10%")
        (field (name "DB_VOLTAGE") "16V")
        (field (name "DB_MANUFACTURER_PART") "KEMET    C0805C106K4PAC")
        (field (name "DB_APPROVED_BY") "ISHIDDEN=T")
      )
      (libsource (lib "Database_Libs1") (part "C"))
    )
    (comp (ref "C913")
      (value "10uF")
      (footprint "SMD_0805_CAPC2012X145N")
      (fields
        (field (name "DB_PART_NUMBER") "CAP000043636")
        (field (name "DB_VALUE") "10uF")
        (field (name "DB_TOLERANCE") "10%")
        (field (name "DB_VOLTAGE") "16V")
        (field (name "DB_MANUFACTURER_PART") "KEMET    C0805C106K4PAC")
        (field (name "DB_APPROVED_BY") "ISHIDDEN=T")
      )
      (libsource (lib "Database_Libs1") (part "C"))
    )
    (comp (ref "C915")
      (value "10uF")
      (footprint "SMD_0805_CAPC2012X145N")
      (fields
        (field (name "DB_PART_NUMBER") "CAP000043636")
        (field (name "DB_VALUE") "10uF")
        (field (name "DB_TOLERANCE") "10%")
        (field (name "DB_VOLTAGE") "16V")
        (field (name "DB_MANUFACTURER_PART") "KEMET    C0805C106K4PAC")
        (field (name "DB_APPROVED_BY") "ISHIDDEN=T")
      )
      (libsource (lib "Database_Libs1") (part "C"))
    )
    (comp (ref "C916")
      (value "10uF")
      (footprint "SMD_0805_CAPC2012X145N")
      (fields
        (field (name "DB_PART_NUMBER") "CAP000043636")
        (field (name "DB_VALUE") "10uF")
        (field (name "DB_TOLERANCE") "10%")
        (field (name "DB_VOLTAGE") "16V")
        (field (name "DB_MANUFACTURER_PART") "KEMET    C0805C106K4PAC")
        (field (name "DB_APPROVED_BY") "ISHIDDEN=T")
      )
      (libsource (lib "Database_Libs1") (part "C"))
    )
    (comp (ref "C918")
      (value "10uF")
      (footprint "SMD_0805_CAPC2012X145N")
      (fields
        (field (name "DB_PART_NUMBER") "CAP000043636")
        (field (name "DB_VALUE") "10uF")
        (field (name "DB_TOLERANCE") "10%")
        (field (name "DB_VOLTAGE") "16V")
        (field (name "DB_MANUFACTURER_PART") "KEMET    C0805C106K4PAC")
        (field (name "DB_APPROVED_BY") "ISHIDDEN=T")
      )
      (libsource (lib "Database_Libs1") (part "C"))
    )
    (comp (ref "C919")
      (value "10uF")
      (footprint "SMD_0805_CAPC2012X145N")
      (fields
        (field (name "DB_PART_NUMBER") "CAP000043636")
        (field (name "DB_VALUE") "10uF")
        (field (name "DB_TOLERANCE") "10%")
        (field (name "DB_VOLTAGE") "16V")
        (field (name "DB_MANUFACTURER_PART") "KEMET    C0805C106K4PAC")
        (field (name "DB_APPROVED_BY") "ISHIDDEN=T")
      )
      (libsource (lib "Database_Libs1") (part "C"))
    )
    (comp (ref "C922")
      (value "22uF")
      (footprint "SMD_0805_CAPC2012X145N")
      (fields
        (field (name "DB_PART_NUMBER") "CAP000043686")
        (field (name "DB_VALUE") "22uF")
        (field (name "DB_TOLERANCE") "20%")
        (field (name "DB_VOLTAGE") "6.3V")
        (field (name "DB_MANUFACTURER_PART") "KEMET    C0805C226M9PAC")
        (field (name "DB_APPROVED_BY") "ISHIDDEN=T")
      )
      (libsource (lib "Database_Libs1") (part "C"))
    )
    (comp (ref "C923")
      (value "220uF")
      (footprint "SMD_1210_CAPC3225X279N")
      (fields
        (field (name "DB_PART_NUMBER") "CAP000047355")
        (field (name "DB_VALUE") "220uF")
        (field (name "DB_TOLERANCE") "20%")
        (field (name "DB_VOLTAGE") "6.3V")
        (field (name "DB_MANUFACTURER_PART") "SAMSUNG    CL32A227MQVNNNE")
        (field (name "DB_APPROVED_BY") "VSN")
      )
      (libsource (lib "Database_Libs1") (part "C"))
    )
    (comp (ref "C924")
      (value "22uF")
      (footprint "SMD_0805_CAPC2012X145N")
      (fields
        (field (name "DB_PART_NUMBER") "CAP000043686")
        (field (name "DB_VALUE") "22uF")
        (field (name "DB_TOLERANCE") "20%")
        (field (name "DB_VOLTAGE") "6.3V")
        (field (name "DB_MANUFACTURER_PART") "KEMET    C0805C226M9PAC")
        (field (name "DB_APPROVED_BY") "ISHIDDEN=T")
      )
      (libsource (lib "Database_Libs1") (part "C"))
    )
    (comp (ref "C925")
      (value "22uF")
      (footprint "SMD_0805_CAPC2012X145N")
      (fields
        (field (name "DB_PART_NUMBER") "CAP000043686")
        (field (name "DB_VALUE") "22uF")
        (field (name "DB_TOLERANCE") "20%")
        (field (name "DB_VOLTAGE") "6.3V")
        (field (name "DB_MANUFACTURER_PART") "KEMET    C0805C226M9PAC")
        (field (name "DB_APPROVED_BY") "ISHIDDEN=T")
      )
      (libsource (lib "Database_Libs1") (part "C"))
    )
    (comp (ref "C926")
      (value "220uF")
      (footprint "SMD_1210_CAPC3225X279N")
      (fields
        (field (name "DB_PART_NUMBER") "CAP000047355")
        (field (name "DB_VALUE") "220uF")
        (field (name "DB_TOLERANCE") "20%")
        (field (name "DB_VOLTAGE") "6.3V")
        (field (name "DB_MANUFACTURER_PART") "SAMSUNG    CL32A227MQVNNNE")
        (field (name "DB_APPROVED_BY") "VSN")
      )
      (libsource (lib "Database_Libs1") (part "C"))
    )
    (comp (ref "C927")
      (value "22uF")
      (footprint "SMD_0805_CAPC2012X145N")
      (fields
        (field (name "DB_PART_NUMBER") "CAP000043686")
        (field (name "DB_VALUE") "22uF")
        (field (name "DB_TOLERANCE") "20%")
        (field (name "DB_VOLTAGE") "6.3V")
        (field (name "DB_MANUFACTURER_PART") "KEMET    C0805C226M9PAC")
        (field (name "DB_APPROVED_BY") "ISHIDDEN=T")
      )
      (libsource (lib "Database_Libs1") (part "C"))
    )
    (comp (ref "C928")
      (value "22uF")
      (footprint "SMD_0805_CAPC2012X145N")
      (fields
        (field (name "DB_PART_NUMBER") "CAP000043686")
        (field (name "DB_VALUE") "22uF")
        (field (name "DB_TOLERANCE") "20%")
        (field (name "DB_VOLTAGE") "6.3V")
        (field (name "DB_MANUFACTURER_PART") "KEMET    C0805C226M9PAC")
        (field (name "DB_APPROVED_BY") "ISHIDDEN=T")
      )
      (libsource (lib "Database_Libs1") (part "C"))
    )
    (comp (ref "C929")
      (value "220uF")
      (footprint "SMD_1210_CAPC3225X279N")
      (fields
        (field (name "DB_PART_NUMBER") "CAP000047355")
        (field (name "DB_VALUE") "220uF")
        (field (name "DB_TOLERANCE") "20%")
        (field (name "DB_VOLTAGE") "6.3V")
        (field (name "DB_MANUFACTURER_PART") "SAMSUNG    CL32A227MQVNNNE")
        (field (name "DB_APPROVED_BY") "VSN")
      )
      (libsource (lib "Database_Libs1") (part "C"))
    )
    (comp (ref "C930")
      (value "22uF")
      (footprint "SMD_0805_CAPC2012X145N")
      (fields
        (field (name "DB_PART_NUMBER") "CAP000043686")
        (field (name "DB_VALUE") "22uF")
        (field (name "DB_TOLERANCE") "20%")
        (field (name "DB_VOLTAGE") "6.3V")
        (field (name "DB_MANUFACTURER_PART") "KEMET    C0805C226M9PAC")
        (field (name "DB_APPROVED_BY") "ISHIDDEN=T")
      )
      (libsource (lib "Database_Libs1") (part "C"))
    )
    (comp (ref "C931")
      (value "22uF")
      (footprint "SMD_0805_CAPC2012X145N")
      (fields
        (field (name "DB_PART_NUMBER") "CAP000043686")
        (field (name "DB_VALUE") "22uF")
        (field (name "DB_TOLERANCE") "20%")
        (field (name "DB_VOLTAGE") "6.3V")
        (field (name "DB_MANUFACTURER_PART") "KEMET    C0805C226M9PAC")
        (field (name "DB_APPROVED_BY") "ISHIDDEN=T")
      )
      (libsource (lib "Database_Libs1") (part "C"))
    )
    (comp (ref "C932")
      (value "220uF")
      (footprint "SMD_1210_CAPC3225X279N")
      (fields
        (field (name "DB_PART_NUMBER") "CAP000047355")
        (field (name "DB_VALUE") "220uF")
        (field (name "DB_TOLERANCE") "20%")
        (field (name "DB_VOLTAGE") "6.3V")
        (field (name "DB_MANUFACTURER_PART") "SAMSUNG    CL32A227MQVNNNE")
        (field (name "DB_APPROVED_BY") "VSN")
      )
      (libsource (lib "Database_Libs1") (part "C"))
    )
    (comp (ref "C933")
      (value "22uF")
      (footprint "SMD_0805_CAPC2012X145N")
      (fields
        (field (name "DB_PART_NUMBER") "CAP000043686")
        (field (name "DB_VALUE") "22uF")
        (field (name "DB_TOLERANCE") "20%")
        (field (name "DB_VOLTAGE") "6.3V")
        (field (name "DB_MANUFACTURER_PART") "KEMET    C0805C226M9PAC")
        (field (name "DB_APPROVED_BY") "ISHIDDEN=T")
      )
      (libsource (lib "Database_Libs1") (part "C"))
    )
    (comp (ref "C934")
      (value "22uF")
      (footprint "SMD_0805_CAPC2012X145N")
      (fields
        (field (name "DB_PART_NUMBER") "CAP000043686")
        (field (name "DB_VALUE") "22uF")
        (field (name "DB_TOLERANCE") "20%")
        (field (name "DB_VOLTAGE") "6.3V")
        (field (name "DB_MANUFACTURER_PART") "KEMET    C0805C226M9PAC")
        (field (name "DB_APPROVED_BY") "ISHIDDEN=T")
      )
      (libsource (lib "Database_Libs1") (part "C"))
    )
    (comp (ref "C935")
      (value "220uF")
      (footprint "SMD_1210_CAPC3225X279N")
      (fields
        (field (name "DB_PART_NUMBER") "CAP000047355")
        (field (name "DB_VALUE") "220uF")
        (field (name "DB_TOLERANCE") "20%")
        (field (name "DB_VOLTAGE") "6.3V")
        (field (name "DB_MANUFACTURER_PART") "SAMSUNG    CL32A227MQVNNNE")
        (field (name "DB_APPROVED_BY") "VSN")
      )
      (libsource (lib "Database_Libs1") (part "C"))
    )
    (comp (ref "C936")
      (value "22uF")
      (footprint "SMD_0805_CAPC2012X145N")
      (fields
        (field (name "DB_PART_NUMBER") "CAP000043686")
        (field (name "DB_VALUE") "22uF")
        (field (name "DB_TOLERANCE") "20%")
        (field (name "DB_VOLTAGE") "6.3V")
        (field (name "DB_MANUFACTURER_PART") "KEMET    C0805C226M9PAC")
        (field (name "DB_APPROVED_BY") "ISHIDDEN=T")
      )
      (libsource (lib "Database_Libs1") (part "C"))
    )
    (comp (ref "C937")
      (value "22uF")
      (footprint "SMD_0805_CAPC2012X145N")
      (fields
        (field (name "DB_PART_NUMBER") "CAP000043686")
        (field (name "DB_VALUE") "22uF")
        (field (name "DB_TOLERANCE") "20%")
        (field (name "DB_VOLTAGE") "6.3V")
        (field (name "DB_MANUFACTURER_PART") "KEMET    C0805C226M9PAC")
        (field (name "DB_APPROVED_BY") "ISHIDDEN=T")
      )
      (libsource (lib "Database_Libs1") (part "C"))
    )
    (comp (ref "C938")
      (value "220uF")
      (footprint "SMD_1210_CAPC3225X279N")
      (fields
        (field (name "DB_PART_NUMBER") "CAP000047355")
        (field (name "DB_VALUE") "220uF")
        (field (name "DB_TOLERANCE") "20%")
        (field (name "DB_VOLTAGE") "6.3V")
        (field (name "DB_MANUFACTURER_PART") "SAMSUNG    CL32A227MQVNNNE")
        (field (name "DB_APPROVED_BY") "VSN")
      )
      (libsource (lib "Database_Libs1") (part "C"))
    )
    (comp (ref "C939")
      (value "22uF")
      (footprint "SMD_0805_CAPC2012X145N")
      (fields
        (field (name "DB_PART_NUMBER") "CAP000043686")
        (field (name "DB_VALUE") "22uF")
        (field (name "DB_TOLERANCE") "20%")
        (field (name "DB_VOLTAGE") "6.3V")
        (field (name "DB_MANUFACTURER_PART") "KEMET    C0805C226M9PAC")
        (field (name "DB_APPROVED_BY") "ISHIDDEN=T")
      )
      (libsource (lib "Database_Libs1") (part "C"))
    )
    (comp (ref "C940")
      (value "22uF")
      (footprint "SMD_0805_CAPC2012X145N")
      (fields
        (field (name "DB_PART_NUMBER") "CAP000043686")
        (field (name "DB_VALUE") "22uF")
        (field (name "DB_TOLERANCE") "20%")
        (field (name "DB_VOLTAGE") "6.3V")
        (field (name "DB_MANUFACTURER_PART") "KEMET    C0805C226M9PAC")
        (field (name "DB_APPROVED_BY") "ISHIDDEN=T")
      )
      (libsource (lib "Database_Libs1") (part "C"))
    )
    (comp (ref "C941")
      (value "220uF")
      (footprint "SMD_1210_CAPC3225X279N")
      (fields
        (field (name "DB_PART_NUMBER") "CAP000047355")
        (field (name "DB_VALUE") "220uF")
        (field (name "DB_TOLERANCE") "20%")
        (field (name "DB_VOLTAGE") "6.3V")
        (field (name "DB_MANUFACTURER_PART") "SAMSUNG    CL32A227MQVNNNE")
        (field (name "DB_APPROVED_BY") "VSN")
      )
      (libsource (lib "Database_Libs1") (part "C"))
    )
    (comp (ref "C942")
      (value "22uF")
      (footprint "SMD_0805_CAPC2012X145N")
      (fields
        (field (name "DB_PART_NUMBER") "CAP000043686")
        (field (name "DB_VALUE") "22uF")
        (field (name "DB_TOLERANCE") "20%")
        (field (name "DB_VOLTAGE") "6.3V")
        (field (name "DB_MANUFACTURER_PART") "KEMET    C0805C226M9PAC")
        (field (name "DB_APPROVED_BY") "ISHIDDEN=T")
      )
      (libsource (lib "Database_Libs1") (part "C"))
    )
    (comp (ref "C943")
      (value "22uF")
      (footprint "SMD_0805_CAPC2012X145N")
      (fields
        (field (name "DB_PART_NUMBER") "CAP000043686")
        (field (name "DB_VALUE") "22uF")
        (field (name "DB_TOLERANCE") "20%")
        (field (name "DB_VOLTAGE") "6.3V")
        (field (name "DB_MANUFACTURER_PART") "KEMET    C0805C226M9PAC")
        (field (name "DB_APPROVED_BY") "ISHIDDEN=T")
      )
      (libsource (lib "Database_Libs1") (part "C"))
    )
    (comp (ref "C944")
      (value "220uF")
      (footprint "SMD_1210_CAPC3225X279N")
      (fields
        (field (name "DB_PART_NUMBER") "CAP000047355")
        (field (name "DB_VALUE") "220uF")
        (field (name "DB_TOLERANCE") "20%")
        (field (name "DB_VOLTAGE") "6.3V")
        (field (name "DB_MANUFACTURER_PART") "SAMSUNG    CL32A227MQVNNNE")
        (field (name "DB_APPROVED_BY") "VSN")
      )
      (libsource (lib "Database_Libs1") (part "C"))
    )
    (comp (ref "C945")
      (value "22uF")
      (footprint "SMD_0805_CAPC2012X145N")
      (fields
        (field (name "DB_PART_NUMBER") "CAP000043686")
        (field (name "DB_VALUE") "22uF")
        (field (name "DB_TOLERANCE") "20%")
        (field (name "DB_VOLTAGE") "6.3V")
        (field (name "DB_MANUFACTURER_PART") "KEMET    C0805C226M9PAC")
        (field (name "DB_APPROVED_BY") "ISHIDDEN=T")
      )
      (libsource (lib "Database_Libs1") (part "C"))
    )
    (comp (ref "C946")
      (value "22uF")
      (footprint "SMD_0805_CAPC2012X145N")
      (fields
        (field (name "DB_PART_NUMBER") "CAP000043686")
        (field (name "DB_VALUE") "22uF")
        (field (name "DB_TOLERANCE") "20%")
        (field (name "DB_VOLTAGE") "6.3V")
        (field (name "DB_MANUFACTURER_PART") "KEMET    C0805C226M9PAC")
        (field (name "DB_APPROVED_BY") "ISHIDDEN=T")
      )
      (libsource (lib "Database_Libs1") (part "C"))
    )
    (comp (ref "C947")
      (value "220uF")
      (footprint "SMD_1210_CAPC3225X279N")
      (fields
        (field (name "DB_PART_NUMBER") "CAP000047355")
        (field (name "DB_VALUE") "220uF")
        (field (name "DB_TOLERANCE") "20%")
        (field (name "DB_VOLTAGE") "6.3V")
        (field (name "DB_MANUFACTURER_PART") "SAMSUNG    CL32A227MQVNNNE")
        (field (name "DB_APPROVED_BY") "VSN")
      )
      (libsource (lib "Database_Libs1") (part "C"))
    )
    (comp (ref "C948")
      (value "22uF")
      (footprint "SMD_0805_CAPC2012X145N")
      (fields
        (field (name "DB_PART_NUMBER") "CAP000043686")
        (field (name "DB_VALUE") "22uF")
        (field (name "DB_TOLERANCE") "20%")
        (field (name "DB_VOLTAGE") "6.3V")
        (field (name "DB_MANUFACTURER_PART") "KEMET    C0805C226M9PAC")
        (field (name "DB_APPROVED_BY") "ISHIDDEN=T")
      )
      (libsource (lib "Database_Libs1") (part "C"))
    )
    (comp (ref "C949")
      (value "22uF")
      (footprint "SMD_0805_CAPC2012X145N")
      (fields
        (field (name "DB_PART_NUMBER") "CAP000043686")
        (field (name "DB_VALUE") "22uF")
        (field (name "DB_TOLERANCE") "20%")
        (field (name "DB_VOLTAGE") "6.3V")
        (field (name "DB_MANUFACTURER_PART") "KEMET    C0805C226M9PAC")
        (field (name "DB_APPROVED_BY") "ISHIDDEN=T")
      )
      (libsource (lib "Database_Libs1") (part "C"))
    )
    (comp (ref "C950")
      (value "220uF")
      (footprint "SMD_1210_CAPC3225X279N")
      (fields
        (field (name "DB_PART_NUMBER") "CAP000047355")
        (field (name "DB_VALUE") "220uF")
        (field (name "DB_TOLERANCE") "20%")
        (field (name "DB_VOLTAGE") "6.3V")
        (field (name "DB_MANUFACTURER_PART") "SAMSUNG    CL32A227MQVNNNE")
        (field (name "DB_APPROVED_BY") "VSN")
      )
      (libsource (lib "Database_Libs1") (part "C"))
    )
    (comp (ref "C951")
      (value "22uF")
      (footprint "SMD_0805_CAPC2012X145N")
      (fields
        (field (name "DB_PART_NUMBER") "CAP000043686")
        (field (name "DB_VALUE") "22uF")
        (field (name "DB_TOLERANCE") "20%")
        (field (name "DB_VOLTAGE") "6.3V")
        (field (name "DB_MANUFACTURER_PART") "KEMET    C0805C226M9PAC")
        (field (name "DB_APPROVED_BY") "ISHIDDEN=T")
      )
      (libsource (lib "Database_Libs1") (part "C"))
    )
    (comp (ref "C952")
      (value "22uF")
      (footprint "SMD_0805_CAPC2012X145N")
      (fields
        (field (name "DB_PART_NUMBER") "CAP000043686")
        (field (name "DB_VALUE") "22uF")
        (field (name "DB_TOLERANCE") "20%")
        (field (name "DB_VOLTAGE") "6.3V")
        (field (name "DB_MANUFACTURER_PART") "KEMET    C0805C226M9PAC")
        (field (name "DB_APPROVED_BY") "ISHIDDEN=T")
      )
      (libsource (lib "Database_Libs1") (part "C"))
    )
    (comp (ref "C953")
      (value "220uF")
      (footprint "SMD_1210_CAPC3225X279N")
      (fields
        (field (name "DB_PART_NUMBER") "CAP000047355")
        (field (name "DB_VALUE") "220uF")
        (field (name "DB_TOLERANCE") "20%")
        (field (name "DB_VOLTAGE") "6.3V")
        (field (name "DB_MANUFACTURER_PART") "SAMSUNG    CL32A227MQVNNNE")
        (field (name "DB_APPROVED_BY") "VSN")
      )
      (libsource (lib "Database_Libs1") (part "C"))
    )
    (comp (ref "C954")
      (value "22uF")
      (footprint "SMD_0805_CAPC2012X145N")
      (fields
        (field (name "DB_PART_NUMBER") "CAP000043686")
        (field (name "DB_VALUE") "22uF")
        (field (name "DB_TOLERANCE") "20%")
        (field (name "DB_VOLTAGE") "6.3V")
        (field (name "DB_MANUFACTURER_PART") "KEMET    C0805C226M9PAC")
        (field (name "DB_APPROVED_BY") "ISHIDDEN=T")
      )
      (libsource (lib "Database_Libs1") (part "C"))
    )
    (comp (ref "C955")
      (value "22uF")
      (footprint "SMD_0805_CAPC2012X145N")
      (fields
        (field (name "DB_PART_NUMBER") "CAP000043686")
        (field (name "DB_VALUE") "22uF")
        (field (name "DB_TOLERANCE") "20%")
        (field (name "DB_VOLTAGE") "6.3V")
        (field (name "DB_MANUFACTURER_PART") "KEMET    C0805C226M9PAC")
        (field (name "DB_APPROVED_BY") "ISHIDDEN=T")
      )
      (libsource (lib "Database_Libs1") (part "C"))
    )
    (comp (ref "C956")
      (value "220uF")
      (footprint "SMD_1210_CAPC3225X279N")
      (fields
        (field (name "DB_PART_NUMBER") "CAP000047355")
        (field (name "DB_VALUE") "220uF")
        (field (name "DB_TOLERANCE") "20%")
        (field (name "DB_VOLTAGE") "6.3V")
        (field (name "DB_MANUFACTURER_PART") "SAMSUNG    CL32A227MQVNNNE")
        (field (name "DB_APPROVED_BY") "VSN")
      )
      (libsource (lib "Database_Libs1") (part "C"))
    )
    (comp (ref "C957")
      (value "22uF")
      (footprint "SMD_0805_CAPC2012X145N")
      (fields
        (field (name "DB_PART_NUMBER") "CAP000043686")
        (field (name "DB_VALUE") "22uF")
        (field (name "DB_TOLERANCE") "20%")
        (field (name "DB_VOLTAGE") "6.3V")
        (field (name "DB_MANUFACTURER_PART") "KEMET    C0805C226M9PAC")
        (field (name "DB_APPROVED_BY") "ISHIDDEN=T")
      )
      (libsource (lib "Database_Libs1") (part "C"))
    )
    (comp (ref "C958")
      (value "22uF")
      (footprint "SMD_0805_CAPC2012X145N")
      (fields
        (field (name "DB_PART_NUMBER") "CAP000043686")
        (field (name "DB_VALUE") "22uF")
        (field (name "DB_TOLERANCE") "20%")
        (field (name "DB_VOLTAGE") "6.3V")
        (field (name "DB_MANUFACTURER_PART") "KEMET    C0805C226M9PAC")
        (field (name "DB_APPROVED_BY") "ISHIDDEN=T")
      )
      (libsource (lib "Database_Libs1") (part "C"))
    )
    (comp (ref "C959")
      (value "220uF")
      (footprint "SMD_1210_CAPC3225X279N")
      (fields
        (field (name "DB_PART_NUMBER") "CAP000047355")
        (field (name "DB_VALUE") "220uF")
        (field (name "DB_TOLERANCE") "20%")
        (field (name "DB_VOLTAGE") "6.3V")
        (field (name "DB_MANUFACTURER_PART") "SAMSUNG    CL32A227MQVNNNE")
        (field (name "DB_APPROVED_BY") "VSN")
      )
      (libsource (lib "Database_Libs1") (part "C"))
    )
    (comp (ref "C960")
      (value "22uF")
      (footprint "SMD_0805_CAPC2012X145N")
      (fields
        (field (name "DB_PART_NUMBER") "CAP000043686")
        (field (name "DB_VALUE") "22uF")
        (field (name "DB_TOLERANCE") "20%")
        (field (name "DB_VOLTAGE") "6.3V")
        (field (name "DB_MANUFACTURER_PART") "KEMET    C0805C226M9PAC")
        (field (name "DB_APPROVED_BY") "ISHIDDEN=T")
      )
      (libsource (lib "Database_Libs1") (part "C"))
    )
    (comp (ref "C961")
      (value "22uF")
      (footprint "SMD_0805_CAPC2012X145N")
      (fields
        (field (name "DB_PART_NUMBER") "CAP000043686")
        (field (name "DB_VALUE") "22uF")
        (field (name "DB_TOLERANCE") "20%")
        (field (name "DB_VOLTAGE") "6.3V")
        (field (name "DB_MANUFACTURER_PART") "KEMET    C0805C226M9PAC")
        (field (name "DB_APPROVED_BY") "ISHIDDEN=T")
      )
      (libsource (lib "Database_Libs1") (part "C"))
    )
    (comp (ref "C962")
      (value "220uF")
      (footprint "SMD_1210_CAPC3225X279N")
      (fields
        (field (name "DB_PART_NUMBER") "CAP000047355")
        (field (name "DB_VALUE") "220uF")
        (field (name "DB_TOLERANCE") "20%")
        (field (name "DB_VOLTAGE") "6.3V")
        (field (name "DB_MANUFACTURER_PART") "SAMSUNG    CL32A227MQVNNNE")
        (field (name "DB_APPROVED_BY") "VSN")
      )
      (libsource (lib "Database_Libs1") (part "C"))
    )
    (comp (ref "C963")
      (value "22uF")
      (footprint "SMD_0805_CAPC2012X145N")
      (fields
        (field (name "DB_PART_NUMBER") "CAP000043686")
        (field (name "DB_VALUE") "22uF")
        (field (name "DB_TOLERANCE") "20%")
        (field (name "DB_VOLTAGE") "6.3V")
        (field (name "DB_MANUFACTURER_PART") "KEMET    C0805C226M9PAC")
        (field (name "DB_APPROVED_BY") "ISHIDDEN=T")
      )
      (libsource (lib "Database_Libs1") (part "C"))
    )
    (comp (ref "C964")
      (value "22uF")
      (footprint "SMD_0805_CAPC2012X145N")
      (fields
        (field (name "DB_PART_NUMBER") "CAP000043686")
        (field (name "DB_VALUE") "22uF")
        (field (name "DB_TOLERANCE") "20%")
        (field (name "DB_VOLTAGE") "6.3V")
        (field (name "DB_MANUFACTURER_PART") "KEMET    C0805C226M9PAC")
        (field (name "DB_APPROVED_BY") "ISHIDDEN=T")
      )
      (libsource (lib "Database_Libs1") (part "C"))
    )
    (comp (ref "C965")
      (value "220uF")
      (footprint "SMD_1210_CAPC3225X279N")
      (fields
        (field (name "DB_PART_NUMBER") "CAP000047355")
        (field (name "DB_VALUE") "220uF")
        (field (name "DB_TOLERANCE") "20%")
        (field (name "DB_VOLTAGE") "6.3V")
        (field (name "DB_MANUFACTURER_PART") "SAMSUNG    CL32A227MQVNNNE")
        (field (name "DB_APPROVED_BY") "VSN")
      )
      (libsource (lib "Database_Libs1") (part "C"))
    )
    (comp (ref "C966")
      (value "22uF")
      (footprint "SMD_0805_CAPC2012X145N")
      (fields
        (field (name "DB_PART_NUMBER") "CAP000043686")
        (field (name "DB_VALUE") "22uF")
        (field (name "DB_TOLERANCE") "20%")
        (field (name "DB_VOLTAGE") "6.3V")
        (field (name "DB_MANUFACTURER_PART") "KEMET    C0805C226M9PAC")
        (field (name "DB_APPROVED_BY") "ISHIDDEN=T")
      )
      (libsource (lib "Database_Libs1") (part "C"))
    )
    (comp (ref "C967")
      (value "22uF")
      (footprint "SMD_0805_CAPC2012X145N")
      (fields
        (field (name "DB_PART_NUMBER") "CAP000043686")
        (field (name "DB_VALUE") "22uF")
        (field (name "DB_TOLERANCE") "20%")
        (field (name "DB_VOLTAGE") "6.3V")
        (field (name "DB_MANUFACTURER_PART") "KEMET    C0805C226M9PAC")
        (field (name "DB_APPROVED_BY") "ISHIDDEN=T")
      )
      (libsource (lib "Database_Libs1") (part "C"))
    )
    (comp (ref "C968")
      (value "220uF")
      (footprint "SMD_1210_CAPC3225X279N")
      (fields
        (field (name "DB_PART_NUMBER") "CAP000047355")
        (field (name "DB_VALUE") "220uF")
        (field (name "DB_TOLERANCE") "20%")
        (field (name "DB_VOLTAGE") "6.3V")
        (field (name "DB_MANUFACTURER_PART") "SAMSUNG    CL32A227MQVNNNE")
        (field (name "DB_APPROVED_BY") "VSN")
      )
      (libsource (lib "Database_Libs1") (part "C"))
    )
    (comp (ref "C969")
      (value "22uF")
      (footprint "SMD_0805_CAPC2012X145N")
      (fields
        (field (name "DB_PART_NUMBER") "CAP000043686")
        (field (name "DB_VALUE") "22uF")
        (field (name "DB_TOLERANCE") "20%")
        (field (name "DB_VOLTAGE") "6.3V")
        (field (name "DB_MANUFACTURER_PART") "KEMET    C0805C226M9PAC")
        (field (name "DB_APPROVED_BY") "ISHIDDEN=T")
      )
      (libsource (lib "Database_Libs1") (part "C"))
    )
    (comp (ref "C970")
      (value "22uF")
      (footprint "SMD_0805_CAPC2012X145N")
      (fields
        (field (name "DB_PART_NUMBER") "CAP000043686")
        (field (name "DB_VALUE") "22uF")
        (field (name "DB_TOLERANCE") "20%")
        (field (name "DB_VOLTAGE") "6.3V")
        (field (name "DB_MANUFACTURER_PART") "KEMET    C0805C226M9PAC")
        (field (name "DB_APPROVED_BY") "ISHIDDEN=T")
      )
      (libsource (lib "Database_Libs1") (part "C"))
    )
    (comp (ref "C971")
      (value "220uF")
      (footprint "SMD_1210_CAPC3225X279N")
      (fields
        (field (name "DB_PART_NUMBER") "CAP000047355")
        (field (name "DB_VALUE") "220uF")
        (field (name "DB_TOLERANCE") "20%")
        (field (name "DB_VOLTAGE") "6.3V")
        (field (name "DB_MANUFACTURER_PART") "SAMSUNG    CL32A227MQVNNNE")
        (field (name "DB_APPROVED_BY") "VSN")
      )
      (libsource (lib "Database_Libs1") (part "C"))
    )
    (comp (ref "C972")
      (value "22uF")
      (footprint "SMD_0805_CAPC2012X145N")
      (fields
        (field (name "DB_PART_NUMBER") "CAP000043686")
        (field (name "DB_VALUE") "22uF")
        (field (name "DB_TOLERANCE") "20%")
        (field (name "DB_VOLTAGE") "6.3V")
        (field (name "DB_MANUFACTURER_PART") "KEMET    C0805C226M9PAC")
        (field (name "DB_APPROVED_BY") "ISHIDDEN=T")
      )
      (libsource (lib "Database_Libs1") (part "C"))
    )
    (comp (ref "C973")
      (value "22uF")
      (footprint "SMD_0805_CAPC2012X145N")
      (fields
        (field (name "DB_PART_NUMBER") "CAP000043686")
        (field (name "DB_VALUE") "22uF")
        (field (name "DB_TOLERANCE") "20%")
        (field (name "DB_VOLTAGE") "6.3V")
        (field (name "DB_MANUFACTURER_PART") "KEMET    C0805C226M9PAC")
        (field (name "DB_APPROVED_BY") "ISHIDDEN=T")
      )
      (libsource (lib "Database_Libs1") (part "C"))
    )
    (comp (ref "C974")
      (value "220uF")
      (footprint "SMD_1210_CAPC3225X279N")
      (fields
        (field (name "DB_PART_NUMBER") "CAP000047355")
        (field (name "DB_VALUE") "220uF")
        (field (name "DB_TOLERANCE") "20%")
        (field (name "DB_VOLTAGE") "6.3V")
        (field (name "DB_MANUFACTURER_PART") "SAMSUNG    CL32A227MQVNNNE")
        (field (name "DB_APPROVED_BY") "VSN")
      )
      (libsource (lib "Database_Libs1") (part "C"))
    )
    (comp (ref "C975")
      (value "22uF")
      (footprint "SMD_0805_CAPC2012X145N")
      (fields
        (field (name "DB_PART_NUMBER") "CAP000043686")
        (field (name "DB_VALUE") "22uF")
        (field (name "DB_TOLERANCE") "20%")
        (field (name "DB_VOLTAGE") "6.3V")
        (field (name "DB_MANUFACTURER_PART") "KEMET    C0805C226M9PAC")
        (field (name "DB_APPROVED_BY") "ISHIDDEN=T")
      )
      (libsource (lib "Database_Libs1") (part "C"))
    )
    (comp (ref "C976")
      (value "22uF")
      (footprint "SMD_0805_CAPC2012X145N")
      (fields
        (field (name "DB_PART_NUMBER") "CAP000043686")
        (field (name "DB_VALUE") "22uF")
        (field (name "DB_TOLERANCE") "20%")
        (field (name "DB_VOLTAGE") "6.3V")
        (field (name "DB_MANUFACTURER_PART") "KEMET    C0805C226M9PAC")
        (field (name "DB_APPROVED_BY") "ISHIDDEN=T")
      )
      (libsource (lib "Database_Libs1") (part "C"))
    )
    (comp (ref "C977")
      (value "220uF")
      (footprint "SMD_1210_CAPC3225X279N")
      (fields
        (field (name "DB_PART_NUMBER") "CAP000047355")
        (field (name "DB_VALUE") "220uF")
        (field (name "DB_TOLERANCE") "20%")
        (field (name "DB_VOLTAGE") "6.3V")
        (field (name "DB_MANUFACTURER_PART") "SAMSUNG    CL32A227MQVNNNE")
        (field (name "DB_APPROVED_BY") "VSN")
      )
      (libsource (lib "Database_Libs1") (part "C"))
    )
    (comp (ref "C978")
      (value "22uF")
      (footprint "SMD_0805_CAPC2012X145N")
      (fields
        (field (name "DB_PART_NUMBER") "CAP000043686")
        (field (name "DB_VALUE") "22uF")
        (field (name "DB_TOLERANCE") "20%")
        (field (name "DB_VOLTAGE") "6.3V")
        (field (name "DB_MANUFACTURER_PART") "KEMET    C0805C226M9PAC")
        (field (name "DB_APPROVED_BY") "ISHIDDEN=T")
      )
      (libsource (lib "Database_Libs1") (part "C"))
    )
    (comp (ref "C979")
      (value "22uF")
      (footprint "SMD_0805_CAPC2012X145N")
      (fields
        (field (name "DB_PART_NUMBER") "CAP000043686")
        (field (name "DB_VALUE") "22uF")
        (field (name "DB_TOLERANCE") "20%")
        (field (name "DB_VOLTAGE") "6.3V")
        (field (name "DB_MANUFACTURER_PART") "KEMET    C0805C226M9PAC")
        (field (name "DB_APPROVED_BY") "ISHIDDEN=T")
      )
      (libsource (lib "Database_Libs1") (part "C"))
    )
    (comp (ref "C980")
      (value "220uF")
      (footprint "SMD_1210_CAPC3225X279N")
      (fields
        (field (name "DB_PART_NUMBER") "CAP000047355")
        (field (name "DB_VALUE") "220uF")
        (field (name "DB_TOLERANCE") "20%")
        (field (name "DB_VOLTAGE") "6.3V")
        (field (name "DB_MANUFACTURER_PART") "SAMSUNG    CL32A227MQVNNNE")
        (field (name "DB_APPROVED_BY") "VSN")
      )
      (libsource (lib "Database_Libs1") (part "C"))
    )
    (comp (ref "C981")
      (value "22uF")
      (footprint "SMD_0805_CAPC2012X145N")
      (fields
        (field (name "DB_PART_NUMBER") "CAP000043686")
        (field (name "DB_VALUE") "22uF")
        (field (name "DB_TOLERANCE") "20%")
        (field (name "DB_VOLTAGE") "6.3V")
        (field (name "DB_MANUFACTURER_PART") "KEMET    C0805C226M9PAC")
        (field (name "DB_APPROVED_BY") "ISHIDDEN=T")
      )
      (libsource (lib "Database_Libs1") (part "C"))
    )
    (comp (ref "C982")
      (value "22uF")
      (footprint "SMD_0805_CAPC2012X145N")
      (fields
        (field (name "DB_PART_NUMBER") "CAP000043686")
        (field (name "DB_VALUE") "22uF")
        (field (name "DB_TOLERANCE") "20%")
        (field (name "DB_VOLTAGE") "6.3V")
        (field (name "DB_MANUFACTURER_PART") "KEMET    C0805C226M9PAC")
        (field (name "DB_APPROVED_BY") "ISHIDDEN=T")
      )
      (libsource (lib "Database_Libs1") (part "C"))
    )
    (comp (ref "C983")
      (value "220uF")
      (footprint "SMD_1210_CAPC3225X279N")
      (fields
        (field (name "DB_PART_NUMBER") "CAP000047355")
        (field (name "DB_VALUE") "220uF")
        (field (name "DB_TOLERANCE") "20%")
        (field (name "DB_VOLTAGE") "6.3V")
        (field (name "DB_MANUFACTURER_PART") "SAMSUNG    CL32A227MQVNNNE")
        (field (name "DB_APPROVED_BY") "VSN")
      )
      (libsource (lib "Database_Libs1") (part "C"))
    )
    (comp (ref "C984")
      (value "22uF")
      (footprint "SMD_0805_CAPC2012X145N")
      (fields
        (field (name "DB_PART_NUMBER") "CAP000043686")
        (field (name "DB_VALUE") "22uF")
        (field (name "DB_TOLERANCE") "20%")
        (field (name "DB_VOLTAGE") "6.3V")
        (field (name "DB_MANUFACTURER_PART") "KEMET    C0805C226M9PAC")
        (field (name "DB_APPROVED_BY") "ISHIDDEN=T")
      )
      (libsource (lib "Database_Libs1") (part "C"))
    )
    (comp (ref "C985")
      (value "22uF")
      (footprint "SMD_0805_CAPC2012X145N")
      (fields
        (field (name "DB_PART_NUMBER") "CAP000043686")
        (field (name "DB_VALUE") "22uF")
        (field (name "DB_TOLERANCE") "20%")
        (field (name "DB_VOLTAGE") "6.3V")
        (field (name "DB_MANUFACTURER_PART") "KEMET    C0805C226M9PAC")
        (field (name "DB_APPROVED_BY") "ISHIDDEN=T")
      )
      (libsource (lib "Database_Libs1") (part "C"))
    )
    (comp (ref "C986")
      (value "220uF")
      (footprint "SMD_1210_CAPC3225X279N")
      (fields
        (field (name "DB_PART_NUMBER") "CAP000047355")
        (field (name "DB_VALUE") "220uF")
        (field (name "DB_TOLERANCE") "20%")
        (field (name "DB_VOLTAGE") "6.3V")
        (field (name "DB_MANUFACTURER_PART") "SAMSUNG    CL32A227MQVNNNE")
        (field (name "DB_APPROVED_BY") "VSN")
      )
      (libsource (lib "Database_Libs1") (part "C"))
    )
    (comp (ref "C987")
      (value "22uF")
      (footprint "SMD_0805_CAPC2012X145N")
      (fields
        (field (name "DB_PART_NUMBER") "CAP000043686")
        (field (name "DB_VALUE") "22uF")
        (field (name "DB_TOLERANCE") "20%")
        (field (name "DB_VOLTAGE") "6.3V")
        (field (name "DB_MANUFACTURER_PART") "KEMET    C0805C226M9PAC")
        (field (name "DB_APPROVED_BY") "ISHIDDEN=T")
      )
      (libsource (lib "Database_Libs1") (part "C"))
    )
    (comp (ref "C988")
      (value "22uF")
      (footprint "SMD_0805_CAPC2012X145N")
      (fields
        (field (name "DB_PART_NUMBER") "CAP000043686")
        (field (name "DB_VALUE") "22uF")
        (field (name "DB_TOLERANCE") "20%")
        (field (name "DB_VOLTAGE") "6.3V")
        (field (name "DB_MANUFACTURER_PART") "KEMET    C0805C226M9PAC")
        (field (name "DB_APPROVED_BY") "ISHIDDEN=T")
      )
      (libsource (lib "Database_Libs1") (part "C"))
    )
    (comp (ref "C989")
      (value "220uF")
      (footprint "SMD_1210_CAPC3225X279N")
      (fields
        (field (name "DB_PART_NUMBER") "CAP000047355")
        (field (name "DB_VALUE") "220uF")
        (field (name "DB_TOLERANCE") "20%")
        (field (name "DB_VOLTAGE") "6.3V")
        (field (name "DB_MANUFACTURER_PART") "SAMSUNG    CL32A227MQVNNNE")
        (field (name "DB_APPROVED_BY") "VSN")
      )
      (libsource (lib "Database_Libs1") (part "C"))
    )
    (comp (ref "C990")
      (value "22uF")
      (footprint "SMD_0805_CAPC2012X145N")
      (fields
        (field (name "DB_PART_NUMBER") "CAP000043686")
        (field (name "DB_VALUE") "22uF")
        (field (name "DB_TOLERANCE") "20%")
        (field (name "DB_VOLTAGE") "6.3V")
        (field (name "DB_MANUFACTURER_PART") "KEMET    C0805C226M9PAC")
        (field (name "DB_APPROVED_BY") "ISHIDDEN=T")
      )
      (libsource (lib "Database_Libs1") (part "C"))
    )
    (comp (ref "C991")
      (value "22uF")
      (footprint "SMD_0805_CAPC2012X145N")
      (fields
        (field (name "DB_PART_NUMBER") "CAP000043686")
        (field (name "DB_VALUE") "22uF")
        (field (name "DB_TOLERANCE") "20%")
        (field (name "DB_VOLTAGE") "6.3V")
        (field (name "DB_MANUFACTURER_PART") "KEMET    C0805C226M9PAC")
        (field (name "DB_APPROVED_BY") "ISHIDDEN=T")
      )
      (libsource (lib "Database_Libs1") (part "C"))
    )
    (comp (ref "C992")
      (value "220uF")
      (footprint "SMD_1210_CAPC3225X279N")
      (fields
        (field (name "DB_PART_NUMBER") "CAP000047355")
        (field (name "DB_VALUE") "220uF")
        (field (name "DB_TOLERANCE") "20%")
        (field (name "DB_VOLTAGE") "6.3V")
        (field (name "DB_MANUFACTURER_PART") "SAMSUNG    CL32A227MQVNNNE")
        (field (name "DB_APPROVED_BY") "VSN")
      )
      (libsource (lib "Database_Libs1") (part "C"))
    )
    (comp (ref "C993")
      (value "22uF")
      (footprint "SMD_0805_CAPC2012X145N")
      (fields
        (field (name "DB_PART_NUMBER") "CAP000043686")
        (field (name "DB_VALUE") "22uF")
        (field (name "DB_TOLERANCE") "20%")
        (field (name "DB_VOLTAGE") "6.3V")
        (field (name "DB_MANUFACTURER_PART") "KEMET    C0805C226M9PAC")
        (field (name "DB_APPROVED_BY") "ISHIDDEN=T")
      )
      (libsource (lib "Database_Libs1") (part "C"))
    )
    (comp (ref "C994")
      (value "22uF")
      (footprint "SMD_0805_CAPC2012X145N")
      (fields
        (field (name "DB_PART_NUMBER") "CAP000043686")
        (field (name "DB_VALUE") "22uF")
        (field (name "DB_TOLERANCE") "20%")
        (field (name "DB_VOLTAGE") "6.3V")
        (field (name "DB_MANUFACTURER_PART") "KEMET    C0805C226M9PAC")
        (field (name "DB_APPROVED_BY") "ISHIDDEN=T")
      )
      (libsource (lib "Database_Libs1") (part "C"))
    )
    (comp (ref "C995")
      (value "220uF")
      (footprint "SMD_1210_CAPC3225X279N")
      (fields
        (field (name "DB_PART_NUMBER") "CAP000047355")
        (field (name "DB_VALUE") "220uF")
        (field (name "DB_TOLERANCE") "20%")
        (field (name "DB_VOLTAGE") "6.3V")
        (field (name "DB_MANUFACTURER_PART") "SAMSUNG    CL32A227MQVNNNE")
        (field (name "DB_APPROVED_BY") "VSN")
      )
      (libsource (lib "Database_Libs1") (part "C"))
    )
    (comp (ref "C996")
      (value "22uF")
      (footprint "SMD_0805_CAPC2012X145N")
      (fields
        (field (name "DB_PART_NUMBER") "CAP000043686")
        (field (name "DB_VALUE") "22uF")
        (field (name "DB_TOLERANCE") "20%")
        (field (name "DB_VOLTAGE") "6.3V")
        (field (name "DB_MANUFACTURER_PART") "KEMET    C0805C226M9PAC")
        (field (name "DB_APPROVED_BY") "ISHIDDEN=T")
      )
      (libsource (lib "Database_Libs1") (part "C"))
    )
    (comp (ref "C997")
      (value "22uF")
      (footprint "SMD_0805_CAPC2012X145N")
      (fields
        (field (name "DB_PART_NUMBER") "CAP000043686")
        (field (name "DB_VALUE") "22uF")
        (field (name "DB_TOLERANCE") "20%")
        (field (name "DB_VOLTAGE") "6.3V")
        (field (name "DB_MANUFACTURER_PART") "KEMET    C0805C226M9PAC")
        (field (name "DB_APPROVED_BY") "ISHIDDEN=T")
      )
      (libsource (lib "Database_Libs1") (part "C"))
    )
    (comp (ref "C998")
      (value "220uF")
      (footprint "SMD_1210_CAPC3225X279N")
      (fields
        (field (name "DB_PART_NUMBER") "CAP000047355")
        (field (name "DB_VALUE") "220uF")
        (field (name "DB_TOLERANCE") "20%")
        (field (name "DB_VOLTAGE") "6.3V")
        (field (name "DB_MANUFACTURER_PART") "SAMSUNG    CL32A227MQVNNNE")
        (field (name "DB_APPROVED_BY") "VSN")
      )
      (libsource (lib "Database_Libs1") (part "C"))
    )
    (comp (ref "C999")
      (value "22uF")
      (footprint "SMD_0805_CAPC2012X145N")
      (fields
        (field (name "DB_PART_NUMBER") "CAP000043686")
        (field (name "DB_VALUE") "22uF")
        (field (name "DB_TOLERANCE") "20%")
        (field (name "DB_VOLTAGE") "6.3V")
        (field (name "DB_MANUFACTURER_PART") "KEMET    C0805C226M9PAC")
        (field (name "DB_APPROVED_BY") "ISHIDDEN=T")
      )
      (libsource (lib "Database_Libs1") (part "C"))
    )
    (comp (ref "C1000")
      (value "22uF")
      (footprint "SMD_0805_CAPC2012X145N")
      (fields
        (field (name "DB_PART_NUMBER") "CAP000043686")
        (field (name "DB_VALUE") "22uF")
        (field (name "DB_TOLERANCE") "20%")
        (field (name "DB_VOLTAGE") "6.3V")
        (field (name "DB_MANUFACTURER_PART") "KEMET    C0805C226M9PAC")
        (field (name "DB_APPROVED_BY") "ISHIDDEN=T")
      )
      (libsource (lib "Database_Libs1") (part "C"))
    )
    (comp (ref "C1001")
      (value "220uF")
      (footprint "SMD_1210_CAPC3225X279N")
      (fields
        (field (name "DB_PART_NUMBER") "CAP000047355")
        (field (name "DB_VALUE") "220uF")
        (field (name "DB_TOLERANCE") "20%")
        (field (name "DB_VOLTAGE") "6.3V")
        (field (name "DB_MANUFACTURER_PART") "SAMSUNG    CL32A227MQVNNNE")
        (field (name "DB_APPROVED_BY") "VSN")
      )
      (libsource (lib "Database_Libs1") (part "C"))
    )
    (comp (ref "C1002")
      (value "22uF")
      (footprint "SMD_0805_CAPC2012X145N")
      (fields
        (field (name "DB_PART_NUMBER") "CAP000043686")
        (field (name "DB_VALUE") "22uF")
        (field (name "DB_TOLERANCE") "20%")
        (field (name "DB_VOLTAGE") "6.3V")
        (field (name "DB_MANUFACTURER_PART") "KEMET    C0805C226M9PAC")
        (field (name "DB_APPROVED_BY") "ISHIDDEN=T")
      )
      (libsource (lib "Database_Libs1") (part "C"))
    )
    (comp (ref "C1003")
      (value "22uF")
      (footprint "SMD_0805_CAPC2012X145N")
      (fields
        (field (name "DB_PART_NUMBER") "CAP000043686")
        (field (name "DB_VALUE") "22uF")
        (field (name "DB_TOLERANCE") "20%")
        (field (name "DB_VOLTAGE") "6.3V")
        (field (name "DB_MANUFACTURER_PART") "KEMET    C0805C226M9PAC")
        (field (name "DB_APPROVED_BY") "ISHIDDEN=T")
      )
      (libsource (lib "Database_Libs1") (part "C"))
    )
    (comp (ref "C1004")
      (value "220uF")
      (footprint "SMD_1210_CAPC3225X279N")
      (fields
        (field (name "DB_PART_NUMBER") "CAP000047355")
        (field (name "DB_VALUE") "220uF")
        (field (name "DB_TOLERANCE") "20%")
        (field (name "DB_VOLTAGE") "6.3V")
        (field (name "DB_MANUFACTURER_PART") "SAMSUNG    CL32A227MQVNNNE")
        (field (name "DB_APPROVED_BY") "VSN")
      )
      (libsource (lib "Database_Libs1") (part "C"))
    )
    (comp (ref "C1005")
      (value "22uF")
      (footprint "SMD_0805_CAPC2012X145N")
      (fields
        (field (name "DB_PART_NUMBER") "CAP000043686")
        (field (name "DB_VALUE") "22uF")
        (field (name "DB_TOLERANCE") "20%")
        (field (name "DB_VOLTAGE") "6.3V")
        (field (name "DB_MANUFACTURER_PART") "KEMET    C0805C226M9PAC")
        (field (name "DB_APPROVED_BY") "ISHIDDEN=T")
      )
      (libsource (lib "Database_Libs1") (part "C"))
    )
    (comp (ref "C1006")
      (value "22uF")
      (footprint "SMD_0805_CAPC2012X145N")
      (fields
        (field (name "DB_PART_NUMBER") "CAP000043686")
        (field (name "DB_VALUE") "22uF")
        (field (name "DB_TOLERANCE") "20%")
        (field (name "DB_VOLTAGE") "6.3V")
        (field (name "DB_MANUFACTURER_PART") "KEMET    C0805C226M9PAC")
        (field (name "DB_APPROVED_BY") "ISHIDDEN=T")
      )
      (libsource (lib "Database_Libs1") (part "C"))
    )
    (comp (ref "C1007")
      (value "220uF")
      (footprint "SMD_1210_CAPC3225X279N")
      (fields
        (field (name "DB_PART_NUMBER") "CAP000047355")
        (field (name "DB_VALUE") "220uF")
        (field (name "DB_TOLERANCE") "20%")
        (field (name "DB_VOLTAGE") "6.3V")
        (field (name "DB_MANUFACTURER_PART") "SAMSUNG    CL32A227MQVNNNE")
        (field (name "DB_APPROVED_BY") "VSN")
      )
      (libsource (lib "Database_Libs1") (part "C"))
    )
    (comp (ref "C1008")
      (value "22uF")
      (footprint "SMD_0805_CAPC2012X145N")
      (fields
        (field (name "DB_PART_NUMBER") "CAP000043686")
        (field (name "DB_VALUE") "22uF")
        (field (name "DB_TOLERANCE") "20%")
        (field (name "DB_VOLTAGE") "6.3V")
        (field (name "DB_MANUFACTURER_PART") "KEMET    C0805C226M9PAC")
        (field (name "DB_APPROVED_BY") "ISHIDDEN=T")
      )
      (libsource (lib "Database_Libs1") (part "C"))
    )
    (comp (ref "C1009")
      (value "22uF")
      (footprint "SMD_0805_CAPC2012X145N")
      (fields
        (field (name "DB_PART_NUMBER") "CAP000043686")
        (field (name "DB_VALUE") "22uF")
        (field (name "DB_TOLERANCE") "20%")
        (field (name "DB_VOLTAGE") "6.3V")
        (field (name "DB_MANUFACTURER_PART") "KEMET    C0805C226M9PAC")
        (field (name "DB_APPROVED_BY") "ISHIDDEN=T")
      )
      (libsource (lib "Database_Libs1") (part "C"))
    )
    (comp (ref "C1010")
      (value "220uF")
      (footprint "SMD_1210_CAPC3225X279N")
      (fields
        (field (name "DB_PART_NUMBER") "CAP000047355")
        (field (name "DB_VALUE") "220uF")
        (field (name "DB_TOLERANCE") "20%")
        (field (name "DB_VOLTAGE") "6.3V")
        (field (name "DB_MANUFACTURER_PART") "SAMSUNG    CL32A227MQVNNNE")
        (field (name "DB_APPROVED_BY") "VSN")
      )
      (libsource (lib "Database_Libs1") (part "C"))
    )
    (comp (ref "C1011")
      (value "22uF")
      (footprint "SMD_0805_CAPC2012X145N")
      (fields
        (field (name "DB_PART_NUMBER") "CAP000043686")
        (field (name "DB_VALUE") "22uF")
        (field (name "DB_TOLERANCE") "20%")
        (field (name "DB_VOLTAGE") "6.3V")
        (field (name "DB_MANUFACTURER_PART") "KEMET    C0805C226M9PAC")
        (field (name "DB_APPROVED_BY") "ISHIDDEN=T")
      )
      (libsource (lib "Database_Libs1") (part "C"))
    )
    (comp (ref "C1012")
      (value "22uF")
      (footprint "SMD_0805_CAPC2012X145N")
      (fields
        (field (name "DB_PART_NUMBER") "CAP000043686")
        (field (name "DB_VALUE") "22uF")
        (field (name "DB_TOLERANCE") "20%")
        (field (name "DB_VOLTAGE") "6.3V")
        (field (name "DB_MANUFACTURER_PART") "KEMET    C0805C226M9PAC")
        (field (name "DB_APPROVED_BY") "ISHIDDEN=T")
      )
      (libsource (lib "Database_Libs1") (part "C"))
    )
    (comp (ref "C1013")
      (value "220uF")
      (footprint "SMD_1210_CAPC3225X279N")
      (fields
        (field (name "DB_PART_NUMBER") "CAP000047355")
        (field (name "DB_VALUE") "220uF")
        (field (name "DB_TOLERANCE") "20%")
        (field (name "DB_VOLTAGE") "6.3V")
        (field (name "DB_MANUFACTURER_PART") "SAMSUNG    CL32A227MQVNNNE")
        (field (name "DB_APPROVED_BY") "VSN")
      )
      (libsource (lib "Database_Libs1") (part "C"))
    )
    (comp (ref "C1014")
      (value "22uF")
      (footprint "SMD_0805_CAPC2012X145N")
      (fields
        (field (name "DB_PART_NUMBER") "CAP000043686")
        (field (name "DB_VALUE") "22uF")
        (field (name "DB_TOLERANCE") "20%")
        (field (name "DB_VOLTAGE") "6.3V")
        (field (name "DB_MANUFACTURER_PART") "KEMET    C0805C226M9PAC")
        (field (name "DB_APPROVED_BY") "ISHIDDEN=T")
      )
      (libsource (lib "Database_Libs1") (part "C"))
    )
    (comp (ref "C1015")
      (value "22uF")
      (footprint "SMD_0805_CAPC2012X145N")
      (fields
        (field (name "DB_PART_NUMBER") "CAP000043686")
        (field (name "DB_VALUE") "22uF")
        (field (name "DB_TOLERANCE") "20%")
        (field (name "DB_VOLTAGE") "6.3V")
        (field (name "DB_MANUFACTURER_PART") "KEMET    C0805C226M9PAC")
        (field (name "DB_APPROVED_BY") "ISHIDDEN=T")
      )
      (libsource (lib "Database_Libs1") (part "C"))
    )
    (comp (ref "C1016")
      (value "220uF")
      (footprint "SMD_1210_CAPC3225X279N")
      (fields
        (field (name "DB_PART_NUMBER") "CAP000047355")
        (field (name "DB_VALUE") "220uF")
        (field (name "DB_TOLERANCE") "20%")
        (field (name "DB_VOLTAGE") "6.3V")
        (field (name "DB_MANUFACTURER_PART") "SAMSUNG    CL32A227MQVNNNE")
        (field (name "DB_APPROVED_BY") "VSN")
      )
      (libsource (lib "Database_Libs1") (part "C"))
    )
    (comp (ref "C1017")
      (value "22uF")
      (footprint "SMD_0805_CAPC2012X145N")
      (fields
        (field (name "DB_PART_NUMBER") "CAP000043686")
        (field (name "DB_VALUE") "22uF")
        (field (name "DB_TOLERANCE") "20%")
        (field (name "DB_VOLTAGE") "6.3V")
        (field (name "DB_MANUFACTURER_PART") "KEMET    C0805C226M9PAC")
        (field (name "DB_APPROVED_BY") "ISHIDDEN=T")
      )
      (libsource (lib "Database_Libs1") (part "C"))
    )
    (comp (ref "C1018")
      (value "22uF")
      (footprint "SMD_0805_CAPC2012X145N")
      (fields
        (field (name "DB_PART_NUMBER") "CAP000043686")
        (field (name "DB_VALUE") "22uF")
        (field (name "DB_TOLERANCE") "20%")
        (field (name "DB_VOLTAGE") "6.3V")
        (field (name "DB_MANUFACTURER_PART") "KEMET    C0805C226M9PAC")
        (field (name "DB_APPROVED_BY") "ISHIDDEN=T")
      )
      (libsource (lib "Database_Libs1") (part "C"))
    )
    (comp (ref "C1019")
      (value "220uF")
      (footprint "SMD_1210_CAPC3225X279N")
      (fields
        (field (name "DB_PART_NUMBER") "CAP000047355")
        (field (name "DB_VALUE") "220uF")
        (field (name "DB_TOLERANCE") "20%")
        (field (name "DB_VOLTAGE") "6.3V")
        (field (name "DB_MANUFACTURER_PART") "SAMSUNG    CL32A227MQVNNNE")
        (field (name "DB_APPROVED_BY") "VSN")
      )
      (libsource (lib "Database_Libs1") (part "C"))
    )
    (comp (ref "C1020")
      (value "22uF")
      (footprint "SMD_0805_CAPC2012X145N")
      (fields
        (field (name "DB_PART_NUMBER") "CAP000043686")
        (field (name "DB_VALUE") "22uF")
        (field (name "DB_TOLERANCE") "20%")
        (field (name "DB_VOLTAGE") "6.3V")
        (field (name "DB_MANUFACTURER_PART") "KEMET    C0805C226M9PAC")
        (field (name "DB_APPROVED_BY") "ISHIDDEN=T")
      )
      (libsource (lib "Database_Libs1") (part "C"))
    )
    (comp (ref "C1021")
      (value "22uF")
      (footprint "SMD_0805_CAPC2012X145N")
      (fields
        (field (name "DB_PART_NUMBER") "CAP000043686")
        (field (name "DB_VALUE") "22uF")
        (field (name "DB_TOLERANCE") "20%")
        (field (name "DB_VOLTAGE") "6.3V")
        (field (name "DB_MANUFACTURER_PART") "KEMET    C0805C226M9PAC")
        (field (name "DB_APPROVED_BY") "ISHIDDEN=T")
      )
      (libsource (lib "Database_Libs1") (part "C"))
    )
    (comp (ref "C1022")
      (value "220uF")
      (footprint "SMD_1210_CAPC3225X279N")
      (fields
        (field (name "DB_PART_NUMBER") "CAP000047355")
        (field (name "DB_VALUE") "220uF")
        (field (name "DB_TOLERANCE") "20%")
        (field (name "DB_VOLTAGE") "6.3V")
        (field (name "DB_MANUFACTURER_PART") "SAMSUNG    CL32A227MQVNNNE")
        (field (name "DB_APPROVED_BY") "VSN")
      )
      (libsource (lib "Database_Libs1") (part "C"))
    )
    (comp (ref "C1023")
      (value "22uF")
      (footprint "SMD_0805_CAPC2012X145N")
      (fields
        (field (name "DB_PART_NUMBER") "CAP000043686")
        (field (name "DB_VALUE") "22uF")
        (field (name "DB_TOLERANCE") "20%")
        (field (name "DB_VOLTAGE") "6.3V")
        (field (name "DB_MANUFACTURER_PART") "KEMET    C0805C226M9PAC")
        (field (name "DB_APPROVED_BY") "ISHIDDEN=T")
      )
      (libsource (lib "Database_Libs1") (part "C"))
    )
    (comp (ref "C1024")
      (value "22uF")
      (footprint "SMD_0805_CAPC2012X145N")
      (fields
        (field (name "DB_PART_NUMBER") "CAP000043686")
        (field (name "DB_VALUE") "22uF")
        (field (name "DB_TOLERANCE") "20%")
        (field (name "DB_VOLTAGE") "6.3V")
        (field (name "DB_MANUFACTURER_PART") "KEMET    C0805C226M9PAC")
        (field (name "DB_APPROVED_BY") "ISHIDDEN=T")
      )
      (libsource (lib "Database_Libs1") (part "C"))
    )
    (comp (ref "C1025")
      (value "220uF")
      (footprint "SMD_1210_CAPC3225X279N")
      (fields
        (field (name "DB_PART_NUMBER") "CAP000047355")
        (field (name "DB_VALUE") "220uF")
        (field (name "DB_TOLERANCE") "20%")
        (field (name "DB_VOLTAGE") "6.3V")
        (field (name "DB_MANUFACTURER_PART") "SAMSUNG    CL32A227MQVNNNE")
        (field (name "DB_APPROVED_BY") "VSN")
      )
      (libsource (lib "Database_Libs1") (part "C"))
    )
    (comp (ref "C1026")
      (value "22uF")
      (footprint "SMD_0805_CAPC2012X145N")
      (fields
        (field (name "DB_PART_NUMBER") "CAP000043686")
        (field (name "DB_VALUE") "22uF")
        (field (name "DB_TOLERANCE") "20%")
        (field (name "DB_VOLTAGE") "6.3V")
        (field (name "DB_MANUFACTURER_PART") "KEMET    C0805C226M9PAC")
        (field (name "DB_APPROVED_BY") "ISHIDDEN=T")
      )
      (libsource (lib "Database_Libs1") (part "C"))
    )
    (comp (ref "C1027")
      (value "22uF")
      (footprint "SMD_0805_CAPC2012X145N")
      (fields
        (field (name "DB_PART_NUMBER") "CAP000043686")
        (field (name "DB_VALUE") "22uF")
        (field (name "DB_TOLERANCE") "20%")
        (field (name "DB_VOLTAGE") "6.3V")
        (field (name "DB_MANUFACTURER_PART") "KEMET    C0805C226M9PAC")
        (field (name "DB_APPROVED_BY") "ISHIDDEN=T")
      )
      (libsource (lib "Database_Libs1") (part "C"))
    )
    (comp (ref "C1028")
      (value "220uF")
      (footprint "SMD_1210_CAPC3225X279N")
      (fields
        (field (name "DB_PART_NUMBER") "CAP000047355")
        (field (name "DB_VALUE") "220uF")
        (field (name "DB_TOLERANCE") "20%")
        (field (name "DB_VOLTAGE") "6.3V")
        (field (name "DB_MANUFACTURER_PART") "SAMSUNG    CL32A227MQVNNNE")
        (field (name "DB_APPROVED_BY") "VSN")
      )
      (libsource (lib "Database_Libs1") (part "C"))
    )
    (comp (ref "C1029")
      (value "22uF")
      (footprint "SMD_0805_CAPC2012X145N")
      (fields
        (field (name "DB_PART_NUMBER") "CAP000043686")
        (field (name "DB_VALUE") "22uF")
        (field (name "DB_TOLERANCE") "20%")
        (field (name "DB_VOLTAGE") "6.3V")
        (field (name "DB_MANUFACTURER_PART") "KEMET    C0805C226M9PAC")
        (field (name "DB_APPROVED_BY") "ISHIDDEN=T")
      )
      (libsource (lib "Database_Libs1") (part "C"))
    )
    (comp (ref "C1030")
      (value "22uF")
      (footprint "SMD_0805_CAPC2012X145N")
      (fields
        (field (name "DB_PART_NUMBER") "CAP000043686")
        (field (name "DB_VALUE") "22uF")
        (field (name "DB_TOLERANCE") "20%")
        (field (name "DB_VOLTAGE") "6.3V")
        (field (name "DB_MANUFACTURER_PART") "KEMET    C0805C226M9PAC")
        (field (name "DB_APPROVED_BY") "ISHIDDEN=T")
      )
      (libsource (lib "Database_Libs1") (part "C"))
    )
    (comp (ref "C1031")
      (value "220uF")
      (footprint "SMD_1210_CAPC3225X279N")
      (fields
        (field (name "DB_PART_NUMBER") "CAP000047355")
        (field (name "DB_VALUE") "220uF")
        (field (name "DB_TOLERANCE") "20%")
        (field (name "DB_VOLTAGE") "6.3V")
        (field (name "DB_MANUFACTURER_PART") "SAMSUNG    CL32A227MQVNNNE")
        (field (name "DB_APPROVED_BY") "VSN")
      )
      (libsource (lib "Database_Libs1") (part "C"))
    )
    (comp (ref "C1032")
      (value "22uF")
      (footprint "SMD_0805_CAPC2012X145N")
      (fields
        (field (name "DB_PART_NUMBER") "CAP000043686")
        (field (name "DB_VALUE") "22uF")
        (field (name "DB_TOLERANCE") "20%")
        (field (name "DB_VOLTAGE") "6.3V")
        (field (name "DB_MANUFACTURER_PART") "KEMET    C0805C226M9PAC")
        (field (name "DB_APPROVED_BY") "ISHIDDEN=T")
      )
      (libsource (lib "Database_Libs1") (part "C"))
    )
    (comp (ref "C1033")
      (value "22uF")
      (footprint "SMD_0805_CAPC2012X145N")
      (fields
        (field (name "DB_PART_NUMBER") "CAP000043686")
        (field (name "DB_VALUE") "22uF")
        (field (name "DB_TOLERANCE") "20%")
        (field (name "DB_VOLTAGE") "6.3V")
        (field (name "DB_MANUFACTURER_PART") "KEMET    C0805C226M9PAC")
        (field (name "DB_APPROVED_BY") "ISHIDDEN=T")
      )
      (libsource (lib "Database_Libs1") (part "C"))
    )
    (comp (ref "C1034")
      (value "220uF")
      (footprint "SMD_1210_CAPC3225X279N")
      (fields
        (field (name "DB_PART_NUMBER") "CAP000047355")
        (field (name "DB_VALUE") "220uF")
        (field (name "DB_TOLERANCE") "20%")
        (field (name "DB_VOLTAGE") "6.3V")
        (field (name "DB_MANUFACTURER_PART") "SAMSUNG    CL32A227MQVNNNE")
        (field (name "DB_APPROVED_BY") "VSN")
      )
      (libsource (lib "Database_Libs1") (part "C"))
    )
    (comp (ref "C1035")
      (value "22uF")
      (footprint "SMD_0805_CAPC2012X145N")
      (fields
        (field (name "DB_PART_NUMBER") "CAP000043686")
        (field (name "DB_VALUE") "22uF")
        (field (name "DB_TOLERANCE") "20%")
        (field (name "DB_VOLTAGE") "6.3V")
        (field (name "DB_MANUFACTURER_PART") "KEMET    C0805C226M9PAC")
        (field (name "DB_APPROVED_BY") "ISHIDDEN=T")
      )
      (libsource (lib "Database_Libs1") (part "C"))
    )
    (comp (ref "C1036")
      (value "22uF")
      (footprint "SMD_0805_CAPC2012X145N")
      (fields
        (field (name "DB_PART_NUMBER") "CAP000043686")
        (field (name "DB_VALUE") "22uF")
        (field (name "DB_TOLERANCE") "20%")
        (field (name "DB_VOLTAGE") "6.3V")
        (field (name "DB_MANUFACTURER_PART") "KEMET    C0805C226M9PAC")
        (field (name "DB_APPROVED_BY") "ISHIDDEN=T")
      )
      (libsource (lib "Database_Libs1") (part "C"))
    )
    (comp (ref "C1037")
      (value "220uF")
      (footprint "SMD_1210_CAPC3225X279N")
      (fields
        (field (name "DB_PART_NUMBER") "CAP000047355")
        (field (name "DB_VALUE") "220uF")
        (field (name "DB_TOLERANCE") "20%")
        (field (name "DB_VOLTAGE") "6.3V")
        (field (name "DB_MANUFACTURER_PART") "SAMSUNG    CL32A227MQVNNNE")
        (field (name "DB_APPROVED_BY") "VSN")
      )
      (libsource (lib "Database_Libs1") (part "C"))
    )
    (comp (ref "C1038")
      (value "22uF")
      (footprint "SMD_0805_CAPC2012X145N")
      (fields
        (field (name "DB_PART_NUMBER") "CAP000043686")
        (field (name "DB_VALUE") "22uF")
        (field (name "DB_TOLERANCE") "20%")
        (field (name "DB_VOLTAGE") "6.3V")
        (field (name "DB_MANUFACTURER_PART") "KEMET    C0805C226M9PAC")
        (field (name "DB_APPROVED_BY") "ISHIDDEN=T")
      )
      (libsource (lib "Database_Libs1") (part "C"))
    )
    (comp (ref "C1039")
      (value "22uF")
      (footprint "SMD_0805_CAPC2012X145N")
      (fields
        (field (name "DB_PART_NUMBER") "CAP000043686")
        (field (name "DB_VALUE") "22uF")
        (field (name "DB_TOLERANCE") "20%")
        (field (name "DB_VOLTAGE") "6.3V")
        (field (name "DB_MANUFACTURER_PART") "KEMET    C0805C226M9PAC")
        (field (name "DB_APPROVED_BY") "ISHIDDEN=T")
      )
      (libsource (lib "Database_Libs1") (part "C"))
    )
    (comp (ref "C1040")
      (value "220uF")
      (footprint "SMD_1210_CAPC3225X279N")
      (fields
        (field (name "DB_PART_NUMBER") "CAP000047355")
        (field (name "DB_VALUE") "220uF")
        (field (name "DB_TOLERANCE") "20%")
        (field (name "DB_VOLTAGE") "6.3V")
        (field (name "DB_MANUFACTURER_PART") "SAMSUNG    CL32A227MQVNNNE")
        (field (name "DB_APPROVED_BY") "VSN")
      )
      (libsource (lib "Database_Libs1") (part "C"))
    )
    (comp (ref "C1041")
      (value "22uF")
      (footprint "SMD_0805_CAPC2012X145N")
      (fields
        (field (name "DB_PART_NUMBER") "CAP000043686")
        (field (name "DB_VALUE") "22uF")
        (field (name "DB_TOLERANCE") "20%")
        (field (name "DB_VOLTAGE") "6.3V")
        (field (name "DB_MANUFACTURER_PART") "KEMET    C0805C226M9PAC")
        (field (name "DB_APPROVED_BY") "ISHIDDEN=T")
      )
      (libsource (lib "Database_Libs1") (part "C"))
    )
    (comp (ref "C1042")
      (value "22uF")
      (footprint "SMD_0805_CAPC2012X145N")
      (fields
        (field (name "DB_PART_NUMBER") "CAP000043686")
        (field (name "DB_VALUE") "22uF")
        (field (name "DB_TOLERANCE") "20%")
        (field (name "DB_VOLTAGE") "6.3V")
        (field (name "DB_MANUFACTURER_PART") "KEMET    C0805C226M9PAC")
        (field (name "DB_APPROVED_BY") "ISHIDDEN=T")
      )
      (libsource (lib "Database_Libs1") (part "C"))
    )
    (comp (ref "C1043")
      (value "220uF")
      (footprint "SMD_1210_CAPC3225X279N")
      (fields
        (field (name "DB_PART_NUMBER") "CAP000047355")
        (field (name "DB_VALUE") "220uF")
        (field (name "DB_TOLERANCE") "20%")
        (field (name "DB_VOLTAGE") "6.3V")
        (field (name "DB_MANUFACTURER_PART") "SAMSUNG    CL32A227MQVNNNE")
        (field (name "DB_APPROVED_BY") "VSN")
      )
      (libsource (lib "Database_Libs1") (part "C"))
    )
    (comp (ref "C1044")
      (value "22uF")
      (footprint "SMD_0805_CAPC2012X145N")
      (fields
        (field (name "DB_PART_NUMBER") "CAP000043686")
        (field (name "DB_VALUE") "22uF")
        (field (name "DB_TOLERANCE") "20%")
        (field (name "DB_VOLTAGE") "6.3V")
        (field (name "DB_MANUFACTURER_PART") "KEMET    C0805C226M9PAC")
        (field (name "DB_APPROVED_BY") "ISHIDDEN=T")
      )
      (libsource (lib "Database_Libs1") (part "C"))
    )
    (comp (ref "C1045")
      (value "22uF")
      (footprint "SMD_0805_CAPC2012X145N")
      (fields
        (field (name "DB_PART_NUMBER") "CAP000043686")
        (field (name "DB_VALUE") "22uF")
        (field (name "DB_TOLERANCE") "20%")
        (field (name "DB_VOLTAGE") "6.3V")
        (field (name "DB_MANUFACTURER_PART") "KEMET    C0805C226M9PAC")
        (field (name "DB_APPROVED_BY") "ISHIDDEN=T")
      )
      (libsource (lib "Database_Libs1") (part "C"))
    )
    (comp (ref "C1046")
      (value "220uF")
      (footprint "SMD_1210_CAPC3225X279N")
      (fields
        (field (name "DB_PART_NUMBER") "CAP000047355")
        (field (name "DB_VALUE") "220uF")
        (field (name "DB_TOLERANCE") "20%")
        (field (name "DB_VOLTAGE") "6.3V")
        (field (name "DB_MANUFACTURER_PART") "SAMSUNG    CL32A227MQVNNNE")
        (field (name "DB_APPROVED_BY") "VSN")
      )
      (libsource (lib "Database_Libs1") (part "C"))
    )
    (comp (ref "C1047")
      (value "22uF")
      (footprint "SMD_0805_CAPC2012X145N")
      (fields
        (field (name "DB_PART_NUMBER") "CAP000043686")
        (field (name "DB_VALUE") "22uF")
        (field (name "DB_TOLERANCE") "20%")
        (field (name "DB_VOLTAGE") "6.3V")
        (field (name "DB_MANUFACTURER_PART") "KEMET    C0805C226M9PAC")
        (field (name "DB_APPROVED_BY") "ISHIDDEN=T")
      )
      (libsource (lib "Database_Libs1") (part "C"))
    )
    (comp (ref "C1048")
      (value "22uF")
      (footprint "SMD_0805_CAPC2012X145N")
      (fields
        (field (name "DB_PART_NUMBER") "CAP000043686")
        (field (name "DB_VALUE") "22uF")
        (field (name "DB_TOLERANCE") "20%")
        (field (name "DB_VOLTAGE") "6.3V")
        (field (name "DB_MANUFACTURER_PART") "KEMET    C0805C226M9PAC")
        (field (name "DB_APPROVED_BY") "ISHIDDEN=T")
      )
      (libsource (lib "Database_Libs1") (part "C"))
    )
    (comp (ref "C1049")
      (value "220uF")
      (footprint "SMD_1210_CAPC3225X279N")
      (fields
        (field (name "DB_PART_NUMBER") "CAP000047355")
        (field (name "DB_VALUE") "220uF")
        (field (name "DB_TOLERANCE") "20%")
        (field (name "DB_VOLTAGE") "6.3V")
        (field (name "DB_MANUFACTURER_PART") "SAMSUNG    CL32A227MQVNNNE")
        (field (name "DB_APPROVED_BY") "VSN")
      )
      (libsource (lib "Database_Libs1") (part "C"))
    )
    (comp (ref "C1050")
      (value "22uF")
      (footprint "SMD_0805_CAPC2012X145N")
      (fields
        (field (name "DB_PART_NUMBER") "CAP000043686")
        (field (name "DB_VALUE") "22uF")
        (field (name "DB_TOLERANCE") "20%")
        (field (name "DB_VOLTAGE") "6.3V")
        (field (name "DB_MANUFACTURER_PART") "KEMET    C0805C226M9PAC")
        (field (name "DB_APPROVED_BY") "ISHIDDEN=T")
      )
      (libsource (lib "Database_Libs1") (part "C"))
    )
    (comp (ref "C1051")
      (value "22uF")
      (footprint "SMD_0805_CAPC2012X145N")
      (fields
        (field (name "DB_PART_NUMBER") "CAP000043686")
        (field (name "DB_VALUE") "22uF")
        (field (name "DB_TOLERANCE") "20%")
        (field (name "DB_VOLTAGE") "6.3V")
        (field (name "DB_MANUFACTURER_PART") "KEMET    C0805C226M9PAC")
        (field (name "DB_APPROVED_BY") "ISHIDDEN=T")
      )
      (libsource (lib "Database_Libs1") (part "C"))
    )
    (comp (ref "C1052")
      (value "220uF")
      (footprint "SMD_1210_CAPC3225X279N")
      (fields
        (field (name "DB_PART_NUMBER") "CAP000047355")
        (field (name "DB_VALUE") "220uF")
        (field (name "DB_TOLERANCE") "20%")
        (field (name "DB_VOLTAGE") "6.3V")
        (field (name "DB_MANUFACTURER_PART") "SAMSUNG    CL32A227MQVNNNE")
        (field (name "DB_APPROVED_BY") "VSN")
      )
      (libsource (lib "Database_Libs1") (part "C"))
    )
    (comp (ref "C1053")
      (value "22uF")
      (footprint "SMD_0805_CAPC2012X145N")
      (fields
        (field (name "DB_PART_NUMBER") "CAP000043686")
        (field (name "DB_VALUE") "22uF")
        (field (name "DB_TOLERANCE") "20%")
        (field (name "DB_VOLTAGE") "6.3V")
        (field (name "DB_MANUFACTURER_PART") "KEMET    C0805C226M9PAC")
        (field (name "DB_APPROVED_BY") "ISHIDDEN=T")
      )
      (libsource (lib "Database_Libs1") (part "C"))
    )
    (comp (ref "C1054")
      (value "22uF")
      (footprint "SMD_0805_CAPC2012X145N")
      (fields
        (field (name "DB_PART_NUMBER") "CAP000043686")
        (field (name "DB_VALUE") "22uF")
        (field (name "DB_TOLERANCE") "20%")
        (field (name "DB_VOLTAGE") "6.3V")
        (field (name "DB_MANUFACTURER_PART") "KEMET    C0805C226M9PAC")
        (field (name "DB_APPROVED_BY") "ISHIDDEN=T")
      )
      (libsource (lib "Database_Libs1") (part "C"))
    )
    (comp (ref "C1055")
      (value "220uF")
      (footprint "SMD_1210_CAPC3225X279N")
      (fields
        (field (name "DB_PART_NUMBER") "CAP000047355")
        (field (name "DB_VALUE") "220uF")
        (field (name "DB_TOLERANCE") "20%")
        (field (name "DB_VOLTAGE") "6.3V")
        (field (name "DB_MANUFACTURER_PART") "SAMSUNG    CL32A227MQVNNNE")
        (field (name "DB_APPROVED_BY") "VSN")
      )
      (libsource (lib "Database_Libs1") (part "C"))
    )
    (comp (ref "C1056")
      (value "22uF")
      (footprint "SMD_0805_CAPC2012X145N")
      (fields
        (field (name "DB_PART_NUMBER") "CAP000043686")
        (field (name "DB_VALUE") "22uF")
        (field (name "DB_TOLERANCE") "20%")
        (field (name "DB_VOLTAGE") "6.3V")
        (field (name "DB_MANUFACTURER_PART") "KEMET    C0805C226M9PAC")
        (field (name "DB_APPROVED_BY") "ISHIDDEN=T")
      )
      (libsource (lib "Database_Libs1") (part "C"))
    )
    (comp (ref "C1057")
      (value "22uF")
      (footprint "SMD_0805_CAPC2012X145N")
      (fields
        (field (name "DB_PART_NUMBER") "CAP000043686")
        (field (name "DB_VALUE") "22uF")
        (field (name "DB_TOLERANCE") "20%")
        (field (name "DB_VOLTAGE") "6.3V")
        (field (name "DB_MANUFACTURER_PART") "KEMET    C0805C226M9PAC")
        (field (name "DB_APPROVED_BY") "ISHIDDEN=T")
      )
      (libsource (lib "Database_Libs1") (part "C"))
    )
    (comp (ref "C1058")
      (value "220uF")
      (footprint "SMD_1210_CAPC3225X279N")
      (fields
        (field (name "DB_PART_NUMBER") "CAP000047355")
        (field (name "DB_VALUE") "220uF")
        (field (name "DB_TOLERANCE") "20%")
        (field (name "DB_VOLTAGE") "6.3V")
        (field (name "DB_MANUFACTURER_PART") "SAMSUNG    CL32A227MQVNNNE")
        (field (name "DB_APPROVED_BY") "VSN")
      )
      (libsource (lib "Database_Libs1") (part "C"))
    )
    (comp (ref "C1059")
      (value "22uF")
      (footprint "SMD_0805_CAPC2012X145N")
      (fields
        (field (name "DB_PART_NUMBER") "CAP000043686")
        (field (name "DB_VALUE") "22uF")
        (field (name "DB_TOLERANCE") "20%")
        (field (name "DB_VOLTAGE") "6.3V")
        (field (name "DB_MANUFACTURER_PART") "KEMET    C0805C226M9PAC")
        (field (name "DB_APPROVED_BY") "ISHIDDEN=T")
      )
      (libsource (lib "Database_Libs1") (part "C"))
    )
    (comp (ref "C1060")
      (value "22uF")
      (footprint "SMD_0805_CAPC2012X145N")
      (fields
        (field (name "DB_PART_NUMBER") "CAP000043686")
        (field (name "DB_VALUE") "22uF")
        (field (name "DB_TOLERANCE") "20%")
        (field (name "DB_VOLTAGE") "6.3V")
        (field (name "DB_MANUFACTURER_PART") "KEMET    C0805C226M9PAC")
        (field (name "DB_APPROVED_BY") "ISHIDDEN=T")
      )
      (libsource (lib "Database_Libs1") (part "C"))
    )
    (comp (ref "C1061")
      (value "220uF")
      (footprint "SMD_1210_CAPC3225X279N")
      (fields
        (field (name "DB_PART_NUMBER") "CAP000047355")
        (field (name "DB_VALUE") "220uF")
        (field (name "DB_TOLERANCE") "20%")
        (field (name "DB_VOLTAGE") "6.3V")
        (field (name "DB_MANUFACTURER_PART") "SAMSUNG    CL32A227MQVNNNE")
        (field (name "DB_APPROVED_BY") "VSN")
      )
      (libsource (lib "Database_Libs1") (part "C"))
    )
    (comp (ref "C1062")
      (value "22uF")
      (footprint "SMD_0805_CAPC2012X145N")
      (fields
        (field (name "DB_PART_NUMBER") "CAP000043686")
        (field (name "DB_VALUE") "22uF")
        (field (name "DB_TOLERANCE") "20%")
        (field (name "DB_VOLTAGE") "6.3V")
        (field (name "DB_MANUFACTURER_PART") "KEMET    C0805C226M9PAC")
        (field (name "DB_APPROVED_BY") "ISHIDDEN=T")
      )
      (libsource (lib "Database_Libs1") (part "C"))
    )
    (comp (ref "C1063")
      (value "22uF")
      (footprint "SMD_0805_CAPC2012X145N")
      (fields
        (field (name "DB_PART_NUMBER") "CAP000043686")
        (field (name "DB_VALUE") "22uF")
        (field (name "DB_TOLERANCE") "20%")
        (field (name "DB_VOLTAGE") "6.3V")
        (field (name "DB_MANUFACTURER_PART") "KEMET    C0805C226M9PAC")
        (field (name "DB_APPROVED_BY") "ISHIDDEN=T")
      )
      (libsource (lib "Database_Libs1") (part "C"))
    )
    (comp (ref "C1064")
      (value "220uF")
      (footprint "SMD_1210_CAPC3225X279N")
      (fields
        (field (name "DB_PART_NUMBER") "CAP000047355")
        (field (name "DB_VALUE") "220uF")
        (field (name "DB_TOLERANCE") "20%")
        (field (name "DB_VOLTAGE") "6.3V")
        (field (name "DB_MANUFACTURER_PART") "SAMSUNG    CL32A227MQVNNNE")
        (field (name "DB_APPROVED_BY") "VSN")
      )
      (libsource (lib "Database_Libs1") (part "C"))
    )
    (comp (ref "C1065")
      (value "22uF")
      (footprint "SMD_0805_CAPC2012X145N")
      (fields
        (field (name "DB_PART_NUMBER") "CAP000043686")
        (field (name "DB_VALUE") "22uF")
        (field (name "DB_TOLERANCE") "20%")
        (field (name "DB_VOLTAGE") "6.3V")
        (field (name "DB_MANUFACTURER_PART") "KEMET    C0805C226M9PAC")
        (field (name "DB_APPROVED_BY") "ISHIDDEN=T")
      )
      (libsource (lib "Database_Libs1") (part "C"))
    )
    (comp (ref "C1066")
      (value "22uF")
      (footprint "SMD_0805_CAPC2012X145N")
      (fields
        (field (name "DB_PART_NUMBER") "CAP000043686")
        (field (name "DB_VALUE") "22uF")
        (field (name "DB_TOLERANCE") "20%")
        (field (name "DB_VOLTAGE") "6.3V")
        (field (name "DB_MANUFACTURER_PART") "KEMET    C0805C226M9PAC")
        (field (name "DB_APPROVED_BY") "ISHIDDEN=T")
      )
      (libsource (lib "Database_Libs1") (part "C"))
    )
    (comp (ref "C1067")
      (value "220uF")
      (footprint "SMD_1210_CAPC3225X279N")
      (fields
        (field (name "DB_PART_NUMBER") "CAP000047355")
        (field (name "DB_VALUE") "220uF")
        (field (name "DB_TOLERANCE") "20%")
        (field (name "DB_VOLTAGE") "6.3V")
        (field (name "DB_MANUFACTURER_PART") "SAMSUNG    CL32A227MQVNNNE")
        (field (name "DB_APPROVED_BY") "VSN")
      )
      (libsource (lib "Database_Libs1") (part "C"))
    )
    (comp (ref "C1068")
      (value "22uF")
      (footprint "SMD_0805_CAPC2012X145N")
      (fields
        (field (name "DB_PART_NUMBER") "CAP000043686")
        (field (name "DB_VALUE") "22uF")
        (field (name "DB_TOLERANCE") "20%")
        (field (name "DB_VOLTAGE") "6.3V")
        (field (name "DB_MANUFACTURER_PART") "KEMET    C0805C226M9PAC")
        (field (name "DB_APPROVED_BY") "ISHIDDEN=T")
      )
      (libsource (lib "Database_Libs1") (part "C"))
    )
    (comp (ref "C1069")
      (value "22uF")
      (footprint "SMD_0805_CAPC2012X145N")
      (fields
        (field (name "DB_PART_NUMBER") "CAP000043686")
        (field (name "DB_VALUE") "22uF")
        (field (name "DB_TOLERANCE") "20%")
        (field (name "DB_VOLTAGE") "6.3V")
        (field (name "DB_MANUFACTURER_PART") "KEMET    C0805C226M9PAC")
        (field (name "DB_APPROVED_BY") "ISHIDDEN=T")
      )
      (libsource (lib "Database_Libs1") (part "C"))
    )
    (comp (ref "C1070")
      (value "220uF")
      (footprint "SMD_1210_CAPC3225X279N")
      (fields
        (field (name "DB_PART_NUMBER") "CAP000047355")
        (field (name "DB_VALUE") "220uF")
        (field (name "DB_TOLERANCE") "20%")
        (field (name "DB_VOLTAGE") "6.3V")
        (field (name "DB_MANUFACTURER_PART") "SAMSUNG    CL32A227MQVNNNE")
        (field (name "DB_APPROVED_BY") "VSN")
      )
      (libsource (lib "Database_Libs1") (part "C"))
    )
    (comp (ref "C1071")
      (value "22uF")
      (footprint "SMD_0805_CAPC2012X145N")
      (fields
        (field (name "DB_PART_NUMBER") "CAP000043686")
        (field (name "DB_VALUE") "22uF")
        (field (name "DB_TOLERANCE") "20%")
        (field (name "DB_VOLTAGE") "6.3V")
        (field (name "DB_MANUFACTURER_PART") "KEMET    C0805C226M9PAC")
        (field (name "DB_APPROVED_BY") "ISHIDDEN=T")
      )
      (libsource (lib "Database_Libs1") (part "C"))
    )
    (comp (ref "D10")
      (value "1N4448HWT")
      (footprint "SMD_SOD523_SOD1608X65N")
      (fields
        (field (name "DB_PART_NUMBER") "DDE000001203")
        (field (name "DB_VALUE") "1N4448HWT")
        (field (name "DB_MANUFACTURER_PART") "Diodes        1N4448HWT")
        (field (name "DB_APPROVED_BY") "ISHIDDEN=T")
      )
      (libsource (lib "Database_Libs1") (part "D"))
    )
    (comp (ref "D11")
      (value "1N4448HWT")
      (footprint "SMD_SOD523_SOD1608X65N")
      (fields
        (field (name "DB_PART_NUMBER") "DDE000001203")
        (field (name "DB_VALUE") "1N4448HWT")
        (field (name "DB_MANUFACTURER_PART") "Diodes        1N4448HWT")
        (field (name "DB_APPROVED_BY") "ISHIDDEN=T")
      )
      (libsource (lib "Database_Libs1") (part "D"))
    )
    (comp (ref "D14")
      (value "1N4448HWT")
      (footprint "SMD_SOD523_SOD1608X65N")
      (fields
        (field (name "DB_PART_NUMBER") "DDE000001203")
        (field (name "DB_VALUE") "1N4448HWT")
        (field (name "DB_MANUFACTURER_PART") "Diodes        1N4448HWT")
        (field (name "DB_APPROVED_BY") "ISHIDDEN=T")
      )
      (libsource (lib "Database_Libs1") (part "D"))
    )
    (comp (ref "D15")
      (value "1N4448HWT")
      (footprint "SMD_SOD523_SOD1608X65N")
      (fields
        (field (name "DB_PART_NUMBER") "DDE000001203")
        (field (name "DB_VALUE") "1N4448HWT")
        (field (name "DB_MANUFACTURER_PART") "Diodes        1N4448HWT")
        (field (name "DB_APPROVED_BY") "ISHIDDEN=T")
      )
      (libsource (lib "Database_Libs1") (part "D"))
    )
    (comp (ref "D18")
      (value "1N4448HWT")
      (footprint "SMD_SOD523_SOD1608X65N")
      (fields
        (field (name "DB_PART_NUMBER") "DDE000001203")
        (field (name "DB_VALUE") "1N4448HWT")
        (field (name "DB_MANUFACTURER_PART") "Diodes        1N4448HWT")
        (field (name "DB_APPROVED_BY") "ISHIDDEN=T")
      )
      (libsource (lib "Database_Libs1") (part "D"))
    )
    (comp (ref "D19")
      (value "1N4448HWT")
      (footprint "SMD_SOD523_SOD1608X65N")
      (fields
        (field (name "DB_PART_NUMBER") "DDE000001203")
        (field (name "DB_VALUE") "1N4448HWT")
        (field (name "DB_MANUFACTURER_PART") "Diodes        1N4448HWT")
        (field (name "DB_APPROVED_BY") "ISHIDDEN=T")
      )
      (libsource (lib "Database_Libs1") (part "D"))
    )
    (comp (ref "D22")
      (value "1N4448HWT")
      (footprint "SMD_SOD523_SOD1608X65N")
      (fields
        (field (name "DB_PART_NUMBER") "DDE000001203")
        (field (name "DB_VALUE") "1N4448HWT")
        (field (name "DB_MANUFACTURER_PART") "Diodes        1N4448HWT")
        (field (name "DB_APPROVED_BY") "ISHIDDEN=T")
      )
      (libsource (lib "Database_Libs1") (part "D"))
    )
    (comp (ref "D23")
      (value "1N4448HWT")
      (footprint "SMD_SOD523_SOD1608X65N")
      (fields
        (field (name "DB_PART_NUMBER") "DDE000001203")
        (field (name "DB_VALUE") "1N4448HWT")
        (field (name "DB_MANUFACTURER_PART") "Diodes        1N4448HWT")
        (field (name "DB_APPROVED_BY") "ISHIDDEN=T")
      )
      (libsource (lib "Database_Libs1") (part "D"))
    )
    (comp (ref "L1")
      (value "INDUCTOR")
      (footprint "SMT_INDM135130X800N")
      (libsource (lib "EPIQ_DND_CIS_Library") (part "L"))
    )
    (comp (ref "L2")
      (value "INDUCTOR")
      (footprint "SMT_INDM135130X800N")
      (libsource (lib "EPIQ_DND_CIS_Library") (part "L"))
    )
    (comp (ref "L5")
      (value "INDUCTOR")
      (footprint "SMT_INDM135130X800N")
      (libsource (lib "EPIQ_DND_CIS_Library") (part "L"))
    )
    (comp (ref "L6")
      (value "INDUCTOR")
      (footprint "SMT_INDM135130X800N")
      (libsource (lib "EPIQ_DND_CIS_Library") (part "L"))
    )
    (comp (ref "L9")
      (value "INDUCTOR")
      (footprint "SMT_INDM135130X800N")
      (libsource (lib "EPIQ_DND_CIS_Library") (part "L"))
    )
    (comp (ref "L10")
      (value "INDUCTOR")
      (footprint "SMT_INDM135130X800N")
      (libsource (lib "EPIQ_DND_CIS_Library") (part "L"))
    )
    (comp (ref "L13")
      (value "INDUCTOR")
      (footprint "SMT_INDM135130X800N")
      (libsource (lib "EPIQ_DND_CIS_Library") (part "L"))
    )
    (comp (ref "L14")
      (value "INDUCTOR")
      (footprint "SMT_INDM135130X800N")
      (libsource (lib "EPIQ_DND_CIS_Library") (part "L"))
    )
    (comp (ref "Q1")
      (value "AP1RA03GMT-HF-3")
      (footprint "SMD_SOIC127P600X110-9AN")
      (fields
        (field (name "DB_PART_NUMBER") "TRA000001604")
        (field (name "DB_VALUE") "AP1RA03GMT-HF-3")
        (field (name "DB_MANUFACTURER_PART") "ADVANCED POWER ELECTRONICS CORP      AP1RA03GMT-HF-3")
        (field (name "DB_APPROVED_BY") "VSN")
      )
      (libsource (lib "Database_Libs1") (part "MOS_N_D1_S1S2S3G4D5D6D7D8"))
    )
    (comp (ref "Q2")
      (value "AP1RA03GMT-HF-3")
      (footprint "SMD_SOIC127P600X110-9AN")
      (fields
        (field (name "DB_PART_NUMBER") "TRA000001604")
        (field (name "DB_VALUE") "AP1RA03GMT-HF-3")
        (field (name "DB_MANUFACTURER_PART") "ADVANCED POWER ELECTRONICS CORP      AP1RA03GMT-HF-3")
        (field (name "DB_APPROVED_BY") "VSN")
      )
      (libsource (lib "Database_Libs1") (part "MOS_N_D1_S1S2S3G4D5D6D7D8"))
    )
    (comp (ref "Q5")
      (value "AP1RA03GMT-HF-3")
      (footprint "SMD_SOIC127P600X110-9AN")
      (fields
        (field (name "DB_PART_NUMBER") "TRA000001604")
        (field (name "DB_VALUE") "AP1RA03GMT-HF-3")
        (field (name "DB_MANUFACTURER_PART") "ADVANCED POWER ELECTRONICS CORP      AP1RA03GMT-HF-3")
        (field (name "DB_APPROVED_BY") "VSN")
      )
      (libsource (lib "Database_Libs1") (part "MOS_N_D1_S1S2S3G4D5D6D7D8"))
    )
    (comp (ref "Q6")
      (value "AP1RA03GMT-HF-3")
      (footprint "SMD_SOIC127P600X110-9AN")
      (fields
        (field (name "DB_PART_NUMBER") "TRA000001604")
        (field (name "DB_VALUE") "AP1RA03GMT-HF-3")
        (field (name "DB_MANUFACTURER_PART") "ADVANCED POWER ELECTRONICS CORP      AP1RA03GMT-HF-3")
        (field (name "DB_APPROVED_BY") "VSN")
      )
      (libsource (lib "Database_Libs1") (part "MOS_N_D1_S1S2S3G4D5D6D7D8"))
    )
    (comp (ref "Q7")
      (value "AP1RA03GMT-HF-3")
      (footprint "SMD_SOIC127P600X110-9AN")
      (fields
        (field (name "DB_PART_NUMBER") "TRA000001604")
        (field (name "DB_VALUE") "AP1RA03GMT-HF-3")
        (field (name "DB_MANUFACTURER_PART") "ADVANCED POWER ELECTRONICS CORP      AP1RA03GMT-HF-3")
        (field (name "DB_APPROVED_BY") "VSN")
      )
      (libsource (lib "Database_Libs1") (part "MOS_N_D1_S1S2S3G4D5D6D7D8"))
    )
    (comp (ref "Q8")
      (value "AP1RA03GMT-HF-3")
      (footprint "SMD_SOIC127P600X110-9AN")
      (fields
        (field (name "DB_PART_NUMBER") "TRA000001604")
        (field (name "DB_VALUE") "AP1RA03GMT-HF-3")
        (field (name "DB_MANUFACTURER_PART") "ADVANCED POWER ELECTRONICS CORP      AP1RA03GMT-HF-3")
        (field (name "DB_APPROVED_BY") "VSN")
      )
      (libsource (lib "Database_Libs1") (part "MOS_N_D1_S1S2S3G4D5D6D7D8"))
    )
    (comp (ref "Q13")
      (value "AP1RA03GMT-HF-3")
      (footprint "SMD_SOIC127P600X110-9AN")
      (fields
        (field (name "DB_PART_NUMBER") "TRA000001604")
        (field (name "DB_VALUE") "AP1RA03GMT-HF-3")
        (field (name "DB_MANUFACTURER_PART") "ADVANCED POWER ELECTRONICS CORP      AP1RA03GMT-HF-3")
        (field (name "DB_APPROVED_BY") "VSN")
      )
      (libsource (lib "Database_Libs1") (part "MOS_N_D1_S1S2S3G4D5D6D7D8"))
    )
    (comp (ref "Q14")
      (value "AP1RA03GMT-HF-3")
      (footprint "SMD_SOIC127P600X110-9AN")
      (fields
        (field (name "DB_PART_NUMBER") "TRA000001604")
        (field (name "DB_VALUE") "AP1RA03GMT-HF-3")
        (field (name "DB_MANUFACTURER_PART") "ADVANCED POWER ELECTRONICS CORP      AP1RA03GMT-HF-3")
        (field (name "DB_APPROVED_BY") "VSN")
      )
      (libsource (lib "Database_Libs1") (part "MOS_N_D1_S1S2S3G4D5D6D7D8"))
    )
    (comp (ref "Q17")
      (value "AP1RA03GMT-HF-3")
      (footprint "SMD_SOIC127P600X110-9AN")
      (fields
        (field (name "DB_PART_NUMBER") "TRA000001604")
        (field (name "DB_VALUE") "AP1RA03GMT-HF-3")
        (field (name "DB_MANUFACTURER_PART") "ADVANCED POWER ELECTRONICS CORP      AP1RA03GMT-HF-3")
        (field (name "DB_APPROVED_BY") "VSN")
      )
      (libsource (lib "Database_Libs1") (part "MOS_N_D1_S1S2S3G4D5D6D7D8"))
    )
    (comp (ref "Q18")
      (value "AP1RA03GMT-HF-3")
      (footprint "SMD_SOIC127P600X110-9AN")
      (fields
        (field (name "DB_PART_NUMBER") "TRA000001604")
        (field (name "DB_VALUE") "AP1RA03GMT-HF-3")
        (field (name "DB_MANUFACTURER_PART") "ADVANCED POWER ELECTRONICS CORP      AP1RA03GMT-HF-3")
        (field (name "DB_APPROVED_BY") "VSN")
      )
      (libsource (lib "Database_Libs1") (part "MOS_N_D1_S1S2S3G4D5D6D7D8"))
    )
    (comp (ref "Q19")
      (value "AP1RA03GMT-HF-3")
      (footprint "SMD_SOIC127P600X110-9AN")
      (fields
        (field (name "DB_PART_NUMBER") "TRA000001604")
        (field (name "DB_VALUE") "AP1RA03GMT-HF-3")
        (field (name "DB_MANUFACTURER_PART") "ADVANCED POWER ELECTRONICS CORP      AP1RA03GMT-HF-3")
        (field (name "DB_APPROVED_BY") "VSN")
      )
      (libsource (lib "Database_Libs1") (part "MOS_N_D1_S1S2S3G4D5D6D7D8"))
    )
    (comp (ref "Q20")
      (value "AP1RA03GMT-HF-3")
      (footprint "SMD_SOIC127P600X110-9AN")
      (fields
        (field (name "DB_PART_NUMBER") "TRA000001604")
        (field (name "DB_VALUE") "AP1RA03GMT-HF-3")
        (field (name "DB_MANUFACTURER_PART") "ADVANCED POWER ELECTRONICS CORP      AP1RA03GMT-HF-3")
        (field (name "DB_APPROVED_BY") "VSN")
      )
      (libsource (lib "Database_Libs1") (part "MOS_N_D1_S1S2S3G4D5D6D7D8"))
    )
    (comp (ref "Q25")
      (value "AP1RA03GMT-HF-3")
      (footprint "SMD_SOIC127P600X110-9AN")
      (fields
        (field (name "DB_PART_NUMBER") "TRA000001604")
        (field (name "DB_VALUE") "AP1RA03GMT-HF-3")
        (field (name "DB_MANUFACTURER_PART") "ADVANCED POWER ELECTRONICS CORP      AP1RA03GMT-HF-3")
        (field (name "DB_APPROVED_BY") "VSN")
      )
      (libsource (lib "Database_Libs1") (part "MOS_N_D1_S1S2S3G4D5D6D7D8"))
    )
    (comp (ref "Q26")
      (value "AP1RA03GMT-HF-3")
      (footprint "SMD_SOIC127P600X110-9AN")
      (fields
        (field (name "DB_PART_NUMBER") "TRA000001604")
        (field (name "DB_VALUE") "AP1RA03GMT-HF-3")
        (field (name "DB_MANUFACTURER_PART") "ADVANCED POWER ELECTRONICS CORP      AP1RA03GMT-HF-3")
        (field (name "DB_APPROVED_BY") "VSN")
      )
      (libsource (lib "Database_Libs1") (part "MOS_N_D1_S1S2S3G4D5D6D7D8"))
    )
    (comp (ref "Q29")
      (value "AP1RA03GMT-HF-3")
      (footprint "SMD_SOIC127P600X110-9AN")
      (fields
        (field (name "DB_PART_NUMBER") "TRA000001604")
        (field (name "DB_VALUE") "AP1RA03GMT-HF-3")
        (field (name "DB_MANUFACTURER_PART") "ADVANCED POWER ELECTRONICS CORP      AP1RA03GMT-HF-3")
        (field (name "DB_APPROVED_BY") "VSN")
      )
      (libsource (lib "Database_Libs1") (part "MOS_N_D1_S1S2S3G4D5D6D7D8"))
    )
    (comp (ref "Q30")
      (value "AP1RA03GMT-HF-3")
      (footprint "SMD_SOIC127P600X110-9AN")
      (fields
        (field (name "DB_PART_NUMBER") "TRA000001604")
        (field (name "DB_VALUE") "AP1RA03GMT-HF-3")
        (field (name "DB_MANUFACTURER_PART") "ADVANCED POWER ELECTRONICS CORP      AP1RA03GMT-HF-3")
        (field (name "DB_APPROVED_BY") "VSN")
      )
      (libsource (lib "Database_Libs1") (part "MOS_N_D1_S1S2S3G4D5D6D7D8"))
    )
    (comp (ref "Q31")
      (value "AP1RA03GMT-HF-3")
      (footprint "SMD_SOIC127P600X110-9AN")
      (fields
        (field (name "DB_PART_NUMBER") "TRA000001604")
        (field (name "DB_VALUE") "AP1RA03GMT-HF-3")
        (field (name "DB_MANUFACTURER_PART") "ADVANCED POWER ELECTRONICS CORP      AP1RA03GMT-HF-3")
        (field (name "DB_APPROVED_BY") "VSN")
      )
      (libsource (lib "Database_Libs1") (part "MOS_N_D1_S1S2S3G4D5D6D7D8"))
    )
    (comp (ref "Q32")
      (value "AP1RA03GMT-HF-3")
      (footprint "SMD_SOIC127P600X110-9AN")
      (fields
        (field (name "DB_PART_NUMBER") "TRA000001604")
        (field (name "DB_VALUE") "AP1RA03GMT-HF-3")
        (field (name "DB_MANUFACTURER_PART") "ADVANCED POWER ELECTRONICS CORP      AP1RA03GMT-HF-3")
        (field (name "DB_APPROVED_BY") "VSN")
      )
      (libsource (lib "Database_Libs1") (part "MOS_N_D1_S1S2S3G4D5D6D7D8"))
    )
    (comp (ref "Q37")
      (value "AP1RA03GMT-HF-3")
      (footprint "SMD_SOIC127P600X110-9AN")
      (fields
        (field (name "DB_PART_NUMBER") "TRA000001604")
        (field (name "DB_VALUE") "AP1RA03GMT-HF-3")
        (field (name "DB_MANUFACTURER_PART") "ADVANCED POWER ELECTRONICS CORP      AP1RA03GMT-HF-3")
        (field (name "DB_APPROVED_BY") "VSN")
      )
      (libsource (lib "Database_Libs1") (part "MOS_N_D1_S1S2S3G4D5D6D7D8"))
    )
    (comp (ref "Q38")
      (value "AP1RA03GMT-HF-3")
      (footprint "SMD_SOIC127P600X110-9AN")
      (fields
        (field (name "DB_PART_NUMBER") "TRA000001604")
        (field (name "DB_VALUE") "AP1RA03GMT-HF-3")
        (field (name "DB_MANUFACTURER_PART") "ADVANCED POWER ELECTRONICS CORP      AP1RA03GMT-HF-3")
        (field (name "DB_APPROVED_BY") "VSN")
      )
      (libsource (lib "Database_Libs1") (part "MOS_N_D1_S1S2S3G4D5D6D7D8"))
    )
    (comp (ref "Q41")
      (value "AP1RA03GMT-HF-3")
      (footprint "SMD_SOIC127P600X110-9AN")
      (fields
        (field (name "DB_PART_NUMBER") "TRA000001604")
        (field (name "DB_VALUE") "AP1RA03GMT-HF-3")
        (field (name "DB_MANUFACTURER_PART") "ADVANCED POWER ELECTRONICS CORP      AP1RA03GMT-HF-3")
        (field (name "DB_APPROVED_BY") "VSN")
      )
      (libsource (lib "Database_Libs1") (part "MOS_N_D1_S1S2S3G4D5D6D7D8"))
    )
    (comp (ref "Q42")
      (value "AP1RA03GMT-HF-3")
      (footprint "SMD_SOIC127P600X110-9AN")
      (fields
        (field (name "DB_PART_NUMBER") "TRA000001604")
        (field (name "DB_VALUE") "AP1RA03GMT-HF-3")
        (field (name "DB_MANUFACTURER_PART") "ADVANCED POWER ELECTRONICS CORP      AP1RA03GMT-HF-3")
        (field (name "DB_APPROVED_BY") "VSN")
      )
      (libsource (lib "Database_Libs1") (part "MOS_N_D1_S1S2S3G4D5D6D7D8"))
    )
    (comp (ref "Q43")
      (value "AP1RA03GMT-HF-3")
      (footprint "SMD_SOIC127P600X110-9AN")
      (fields
        (field (name "DB_PART_NUMBER") "TRA000001604")
        (field (name "DB_VALUE") "AP1RA03GMT-HF-3")
        (field (name "DB_MANUFACTURER_PART") "ADVANCED POWER ELECTRONICS CORP      AP1RA03GMT-HF-3")
        (field (name "DB_APPROVED_BY") "VSN")
      )
      (libsource (lib "Database_Libs1") (part "MOS_N_D1_S1S2S3G4D5D6D7D8"))
    )
    (comp (ref "Q44")
      (value "AP1RA03GMT-HF-3")
      (footprint "SMD_SOIC127P600X110-9AN")
      (fields
        (field (name "DB_PART_NUMBER") "TRA000001604")
        (field (name "DB_VALUE") "AP1RA03GMT-HF-3")
        (field (name "DB_MANUFACTURER_PART") "ADVANCED POWER ELECTRONICS CORP      AP1RA03GMT-HF-3")
        (field (name "DB_APPROVED_BY") "VSN")
      )
      (libsource (lib "Database_Libs1") (part "MOS_N_D1_S1S2S3G4D5D6D7D8"))
    )
    (comp (ref "U11")
      (value "LTC4449EDCB#TRPBF")
      (footprint "SMD_SON45P300X200X80-9N")
      (fields
        (field (name "DB_PART_NUMBER") "DRV000000079")
        (field (name "DB_VALUE") "LTC4449EDCB#TRPBF")
        (field (name "DB_MANUFACTURER_PART") "LINEAR       LTC4449EDCB#TRPBF")
        (field (name "DB_APPROVED_BY") "VSN")
      )
      (libsource (lib "Database_Libs1") (part "IC_LTC4449"))
    )
    (comp (ref "U12")
      (value "LTC4449EDCB#TRPBF")
      (footprint "SMD_SON45P300X200X80-9N")
      (fields
        (field (name "DB_PART_NUMBER") "DRV000000079")
        (field (name "DB_VALUE") "LTC4449EDCB#TRPBF")
        (field (name "DB_MANUFACTURER_PART") "LINEAR       LTC4449EDCB#TRPBF")
        (field (name "DB_APPROVED_BY") "VSN")
      )
      (libsource (lib "Database_Libs1") (part "IC_LTC4449"))
    )
    (comp (ref "U15")
      (value "LTC4449EDCB#TRPBF")
      (footprint "SMD_SON45P300X200X80-9N")
      (fields
        (field (name "DB_PART_NUMBER") "DRV000000079")
        (field (name "DB_VALUE") "LTC4449EDCB#TRPBF")
        (field (name "DB_MANUFACTURER_PART") "LINEAR       LTC4449EDCB#TRPBF")
        (field (name "DB_APPROVED_BY") "VSN")
      )
      (libsource (lib "Database_Libs1") (part "IC_LTC4449"))
    )
    (comp (ref "U16")
      (value "LTC4449EDCB#TRPBF")
      (footprint "SMD_SON45P300X200X80-9N")
      (fields
        (field (name "DB_PART_NUMBER") "DRV000000079")
        (field (name "DB_VALUE") "LTC4449EDCB#TRPBF")
        (field (name "DB_MANUFACTURER_PART") "LINEAR       LTC4449EDCB#TRPBF")
        (field (name "DB_APPROVED_BY") "VSN")
      )
      (libsource (lib "Database_Libs1") (part "IC_LTC4449"))
    )
    (comp (ref "U19")
      (value "LTC4449EDCB#TRPBF")
      (footprint "SMD_SON45P300X200X80-9N")
      (fields
        (field (name "DB_PART_NUMBER") "DRV000000079")
        (field (name "DB_VALUE") "LTC4449EDCB#TRPBF")
        (field (name "DB_MANUFACTURER_PART") "LINEAR       LTC4449EDCB#TRPBF")
        (field (name "DB_APPROVED_BY") "VSN")
      )
      (libsource (lib "Database_Libs1") (part "IC_LTC4449"))
    )
    (comp (ref "U20")
      (value "LTC4449EDCB#TRPBF")
      (footprint "SMD_SON45P300X200X80-9N")
      (fields
        (field (name "DB_PART_NUMBER") "DRV000000079")
        (field (name "DB_VALUE") "LTC4449EDCB#TRPBF")
        (field (name "DB_MANUFACTURER_PART") "LINEAR       LTC4449EDCB#TRPBF")
        (field (name "DB_APPROVED_BY") "VSN")
      )
      (libsource (lib "Database_Libs1") (part "IC_LTC4449"))
    )
    (comp (ref "U23")
      (value "LTC4449EDCB#TRPBF")
      (footprint "SMD_SON45P300X200X80-9N")
      (fields
        (field (name "DB_PART_NUMBER") "DRV000000079")
        (field (name "DB_VALUE") "LTC4449EDCB#TRPBF")
        (field (name "DB_MANUFACTURER_PART") "LINEAR       LTC4449EDCB#TRPBF")
        (field (name "DB_APPROVED_BY") "VSN")
      )
      (libsource (lib "Database_Libs1") (part "IC_LTC4449"))
    )
    (comp (ref "U24")
      (value "LTC4449EDCB#TRPBF")
      (footprint "SMD_SON45P300X200X80-9N")
      (fields
        (field (name "DB_PART_NUMBER") "DRV000000079")
        (field (name "DB_VALUE") "LTC4449EDCB#TRPBF")
        (field (name "DB_MANUFACTURER_PART") "LINEAR       LTC4449EDCB#TRPBF")
        (field (name "DB_APPROVED_BY") "VSN")
      )
      (libsource (lib "Database_Libs1") (part "IC_LTC4449"))
    )
  )
  (nets
    (net (code "1") (name "/1V") (class "Default")
      (node (ref "C100") (pin "2") (pinfunction "2_2") (pintype "passive"))
      (node (ref "C1000") (pin "1") (pinfunction "1_1") (pintype "passive"))
      (node (ref "C1001") (pin "2") (pinfunction "2_2") (pintype "passive"))
      (node (ref "C1002") (pin "1") (pinfunction "1_1") (pintype "passive"))
      (node (ref "C1003") (pin "1") (pinfunction "1_1") (pintype "passive"))
      (node (ref "C1004") (pin "2") (pinfunction "2_2") (pintype "passive"))
      (node (ref "C1005") (pin "1") (pinfunction "1_1") (pintype "passive"))
      (node (ref "C1006") (pin "1") (pinfunction "1_1") (pintype "passive"))
      (node (ref "C1007") (pin "2") (pinfunction "2_2") (pintype "passive"))
      (node (ref "C1008") (pin "1") (pinfunction "1_1") (pintype "passive"))
      (node (ref "C1009") (pin "1") (pinfunction "1_1") (pintype "passive"))
      (node (ref "C1010") (pin "2") (pinfunction "2_2") (pintype "passive"))
      (node (ref "C1011") (pin "1") (pinfunction "1_1") (pintype "passive"))
      (node (ref "C1012") (pin "1") (pinfunction "1_1") (pintype "passive"))
      (node (ref "C1013") (pin "2") (pinfunction "2_2") (pintype "passive"))
      (node (ref "C1014") (pin "1") (pinfunction "1_1") (pintype "passive"))
      (node (ref "C1015") (pin "1") (pinfunction "1_1") (pintype "passive"))
      (node (ref "C1016") (pin "2") (pinfunction "2_2") (pintype "passive"))
      (node (ref "C1017") (pin "1") (pinfunction "1_1") (pintype "passive"))
      (node (ref "C1018") (pin "1") (pinfunction "1_1") (pintype "passive"))
      (node (ref "C1019") (pin "2") (pinfunction "2_2") (pintype "passive"))
      (node (ref "C1020") (pin "1") (pinfunction "1_1") (pintype "passive"))
      (node (ref "C1021") (pin "1") (pinfunction "1_1") (pintype "passive"))
      (node (ref "C1022") (pin "2") (pinfunction "2_2") (pintype "passive"))
      (node (ref "C1023") (pin "1") (pinfunction "1_1") (pintype "passive"))
      (node (ref "C1024") (pin "1") (pinfunction "1_1") (pintype "passive"))
      (node (ref "C1025") (pin "2") (pinfunction "2_2") (pintype "passive"))
      (node (ref "C1026") (pin "1") (pinfunction "1_1") (pintype "passive"))
      (node (ref "C1027") (pin "1") (pinfunction "1_1") (pintype "passive"))
      (node (ref "C1028") (pin "2") (pinfunction "2_2") (pintype "passive"))
      (node (ref "C1029") (pin "1") (pinfunction "1_1") (pintype "passive"))
      (node (ref "C103") (pin "2") (pinfunction "2_2") (pintype "passive"))
      (node (ref "C1030") (pin "1") (pinfunction "1_1") (pintype "passive"))
      (node (ref "C1031") (pin "2") (pinfunction "2_2") (pintype "passive"))
      (node (ref "C1032") (pin "1") (pinfunction "1_1") (pintype "passive"))
      (node (ref "C1033") (pin "1") (pinfunction "1_1") (pintype "passive"))
      (node (ref "C1034") (pin "2") (pinfunction "2_2") (pintype "passive"))
      (node (ref "C1035") (pin "1") (pinfunction "1_1") (pintype "passive"))
      (node (ref "C1036") (pin "1") (pinfunction "1_1") (pintype "passive"))
      (node (ref "C1037") (pin "2") (pinfunction "2_2") (pintype "passive"))
      (node (ref "C1038") (pin "1") (pinfunction "1_1") (pintype "passive"))
      (node (ref "C1039") (pin "1") (pinfunction "1_1") (pintype "passive"))
      (node (ref "C104") (pin "2") (pinfunction "2_2") (pintype "passive"))
      (node (ref "C1040") (pin "2") (pinfunction "2_2") (pintype "passive"))
      (node (ref "C1041") (pin "1") (pinfunction "1_1") (pintype "passive"))
      (node (ref "C1042") (pin "1") (pinfunction "1_1") (pintype "passive"))
      (node (ref "C1043") (pin "2") (pinfunction "2_2") (pintype "passive"))
      (node (ref "C1044") (pin "1") (pinfunction "1_1") (pintype "passive"))
      (node (ref "C1045") (pin "1") (pinfunction "1_1") (pintype "passive"))
      (node (ref "C1046") (pin "2") (pinfunction "2_2") (pintype "passive"))
      (node (ref "C1047") (pin "1") (pinfunction "1_1") (pintype "passive"))
      (node (ref "C1048") (pin "1") (pinfunction "1_1") (pintype "passive"))
      (node (ref "C1049") (pin "2") (pinfunction "2_2") (pintype "passive"))
      (node (ref "C105") (pin "2") (pinfunction "2_2") (pintype "passive"))
      (node (ref "C1050") (pin "1") (pinfunction "1_1") (pintype "passive"))
      (node (ref "C1051") (pin "1") (pinfunction "1_1") (pintype "passive"))
      (node (ref "C1052") (pin "2") (pinfunction "2_2") (pintype "passive"))
      (node (ref "C1053") (pin "1") (pinfunction "1_1") (pintype "passive"))
      (node (ref "C1054") (pin "1") (pinfunction "1_1") (pintype "passive"))
      (node (ref "C1055") (pin "2") (pinfunction "2_2") (pintype "passive"))
      (node (ref "C1056") (pin "1") (pinfunction "1_1") (pintype "passive"))
      (node (ref "C1057") (pin "1") (pinfunction "1_1") (pintype "passive"))
      (node (ref "C1058") (pin "2") (pinfunction "2_2") (pintype "passive"))
      (node (ref "C1059") (pin "1") (pinfunction "1_1") (pintype "passive"))
      (node (ref "C1060") (pin "1") (pinfunction "1_1") (pintype "passive"))
      (node (ref "C1061") (pin "2") (pinfunction "2_2") (pintype "passive"))
      (node (ref "C1062") (pin "1") (pinfunction "1_1") (pintype "passive"))
      (node (ref "C1063") (pin "1") (pinfunction "1_1") (pintype "passive"))
      (node (ref "C1064") (pin "2") (pinfunction "2_2") (pintype "passive"))
      (node (ref "C1065") (pin "1") (pinfunction "1_1") (pintype "passive"))
      (node (ref "C1066") (pin "1") (pinfunction "1_1") (pintype "passive"))
      (node (ref "C1067") (pin "2") (pinfunction "2_2") (pintype "passive"))
      (node (ref "C1068") (pin "1") (pinfunction "1_1") (pintype "passive"))
      (node (ref "C1069") (pin "1") (pinfunction "1_1") (pintype "passive"))
      (node (ref "C1070") (pin "2") (pinfunction "2_2") (pintype "passive"))
      (node (ref "C1071") (pin "1") (pinfunction "1_1") (pintype "passive"))
      (node (ref "C130") (pin "2") (pinfunction "2_2") (pintype "passive"))
      (node (ref "C131") (pin "2") (pinfunction "2_2") (pintype "passive"))
      (node (ref "C132") (pin "2") (pinfunction "2_2") (pintype "passive"))
      (node (ref "C135") (pin "2") (pinfunction "2_2") (pintype "passive"))
      (node (ref "C136") (pin "2") (pinfunction "2_2") (pintype "passive"))
      (node (ref "C137") (pin "2") (pinfunction "2_2") (pintype "passive"))
      (node (ref "C236") (pin "2") (pinfunction "2_2") (pintype "passive"))
      (node (ref "C323") (pin "1") (pinfunction "1_1") (pintype "passive"))
      (node (ref "C324") (pin "1") (pinfunction "1_1") (pintype "passive"))
      (node (ref "C325") (pin "1") (pinfunction "1_1") (pintype "passive"))
      (node (ref "C326") (pin "1") (pinfunction "1_1") (pintype "passive"))
      (node (ref "C327") (pin "1") (pinfunction "1_1") (pintype "passive"))
      (node (ref "C328") (pin "1") (pinfunction "1_1") (pintype "passive"))
      (node (ref "C329") (pin "1") (pinfunction "1_1") (pintype "passive"))
      (node (ref "C330") (pin "1") (pinfunction "1_1") (pintype "passive"))
      (node (ref "C331") (pin "1") (pinfunction "1_1") (pintype "passive"))
      (node (ref "C332") (pin "1") (pinfunction "1_1") (pintype "passive"))
      (node (ref "C333") (pin "1") (pinfunction "1_1") (pintype "passive"))
      (node (ref "C334") (pin "1") (pinfunction "1_1") (pintype "passive"))
      (node (ref "C335") (pin "1") (pinfunction "1_1") (pintype "passive"))
      (node (ref "C336") (pin "1") (pinfunction "1_1") (pintype "passive"))
      (node (ref "C337") (pin "1") (pinfunction "1_1") (pintype "passive"))
      (node (ref "C338") (pin "1") (pinfunction "1_1") (pintype "passive"))
      (node (ref "C339") (pin "1") (pinfunction "1_1") (pintype "passive"))
      (node (ref "C34") (pin "2") (pinfunction "2_2") (pintype "passive"))
      (node (ref "C340") (pin "1") (pinfunction "1_1") (pintype "passive"))
      (node (ref "C341") (pin "1") (pinfunction "1_1") (pintype "passive"))
      (node (ref "C342") (pin "1") (pinfunction "1_1") (pintype "passive"))
      (node (ref "C343") (pin "1") (pinfunction "1_1") (pintype "passive"))
      (node (ref "C344") (pin "1") (pinfunction "1_1") (pintype "passive"))
      (node (ref "C345") (pin "1") (pinfunction "1_1") (pintype "passive"))
      (node (ref "C346") (pin "1") (pinfunction "1_1") (pintype "passive"))
      (node (ref "C35") (pin "2") (pinfunction "2_2") (pintype "passive"))
      (node (ref "C350") (pin "2") (pinfunction "2_2") (pintype "passive"))
      (node (ref "C351") (pin "2") (pinfunction "2_2") (pintype "passive"))
      (node (ref "C352") (pin "2") (pinfunction "2_2") (pintype "passive"))
      (node (ref "C353") (pin "1") (pinfunction "1_1") (pintype "passive"))
      (node (ref "C354") (pin "1") (pinfunction "1_1") (pintype "passive"))
      (node (ref "C355") (pin "1") (pinfunction "1_1") (pintype "passive"))
      (node (ref "C356") (pin "1") (pinfunction "1_1") (pintype "passive"))
      (node (ref "C357") (pin "1") (pinfunction "1_1") (pintype "passive"))
      (node (ref "C358") (pin "1") (pinfunction "1_1") (pintype "passive"))
      (node (ref "C359") (pin "1") (pinfunction "1_1") (pintype "passive"))
      (node (ref "C360") (pin "1") (pinfunction "1_1") (pintype "passive"))
      (node (ref "C361") (pin "1") (pinfunction "1_1") (pintype "passive"))
      (node (ref "C362") (pin "1") (pinfunction "1_1") (pintype "passive"))
      (node (ref "C363") (pin "1") (pinfunction "1_1") (pintype "passive"))
      (node (ref "C364") (pin "1") (pinfunction "1_1") (pintype "passive"))
      (node (ref "C365") (pin "1") (pinfunction "1_1") (pintype "passive"))
      (node (ref "C366") (pin "1") (pinfunction "1_1") (pintype "passive"))
      (node (ref "C367") (pin "1") (pinfunction "1_1") (pintype "passive"))
      (node (ref "C368") (pin "1") (pinfunction "1_1") (pintype "passive"))
      (node (ref "C369") (pin "1") (pinfunction "1_1") (pintype "passive"))
      (node (ref "C370") (pin "1") (pinfunction "1_1") (pintype "passive"))
      (node (ref "C371") (pin "1") (pinfunction "1_1") (pintype "passive"))
      (node (ref "C372") (pin "1") (pinfunction "1_1") (pintype "passive"))
      (node (ref "C373") (pin "1") (pinfunction "1_1") (pintype "passive"))
      (node (ref "C374") (pin "1") (pinfunction "1_1") (pintype "passive"))
      (node (ref "C375") (pin "1") (pinfunction "1_1") (pintype "passive"))
      (node (ref "C376") (pin "1") (pinfunction "1_1") (pintype "passive"))
      (node (ref "C39") (pin "2") (pinfunction "2_2") (pintype "passive"))
      (node (ref "C393") (pin "2") (pinfunction "2_2") (pintype "passive"))
      (node (ref "C394") (pin "2") (pinfunction "2_2") (pintype "passive"))
      (node (ref "C395") (pin "2") (pinfunction "2_2") (pintype "passive"))
      (node (ref "C396") (pin "2") (pinfunction "2_2") (pintype "passive"))
      (node (ref "C397") (pin "2") (pinfunction "2_2") (pintype "passive"))
      (node (ref "C398") (pin "2") (pinfunction "2_2") (pintype "passive"))
      (node (ref "C399") (pin "2") (pinfunction "2_2") (pintype "passive"))
      (node (ref "C40") (pin "2") (pinfunction "2_2") (pintype "passive"))
      (node (ref "C400") (pin "2") (pinfunction "2_2") (pintype "passive"))
      (node (ref "C401") (pin "2") (pinfunction "2_2") (pintype "passive"))
      (node (ref "C408") (pin "2") (pinfunction "2_2") (pintype "passive"))
      (node (ref "C409") (pin "2") (pinfunction "2_2") (pintype "passive"))
      (node (ref "C41") (pin "2") (pinfunction "2_2") (pintype "passive"))
      (node (ref "C410") (pin "2") (pinfunction "2_2") (pintype "passive"))
      (node (ref "C411") (pin "2") (pinfunction "2_2") (pintype "passive"))
      (node (ref "C412") (pin "2") (pinfunction "2_2") (pintype "passive"))
      (node (ref "C413") (pin "2") (pinfunction "2_2") (pintype "passive"))
      (node (ref "C414") (pin "2") (pinfunction "2_2") (pintype "passive"))
      (node (ref "C415") (pin "2") (pinfunction "2_2") (pintype "passive"))
      (node (ref "C416") (pin "2") (pinfunction "2_2") (pintype "passive"))
      (node (ref "C417") (pin "2") (pinfunction "2_2") (pintype "passive"))
      (node (ref "C418") (pin "2") (pinfunction "2_2") (pintype "passive"))
      (node (ref "C419") (pin "2") (pinfunction "2_2") (pintype "passive"))
      (node (ref "C444") (pin "1") (pinfunction "1_1") (pintype "passive"))
      (node (ref "C445") (pin "1") (pinfunction "1_1") (pintype "passive"))
      (node (ref "C446") (pin "1") (pinfunction "1_1") (pintype "passive"))
      (node (ref "C447") (pin "1") (pinfunction "1_1") (pintype "passive"))
      (node (ref "C448") (pin "1") (pinfunction "1_1") (pintype "passive"))
      (node (ref "C449") (pin "1") (pinfunction "1_1") (pintype "passive"))
      (node (ref "C450") (pin "1") (pinfunction "1_1") (pintype "passive"))
      (node (ref "C451") (pin "1") (pinfunction "1_1") (pintype "passive"))
      (node (ref "C452") (pin "1") (pinfunction "1_1") (pintype "passive"))
      (node (ref "C453") (pin "1") (pinfunction "1_1") (pintype "passive"))
      (node (ref "C454") (pin "1") (pinfunction "1_1") (pintype "passive"))
      (node (ref "C455") (pin "1") (pinfunction "1_1") (pintype "passive"))
      (node (ref "C456") (pin "1") (pinfunction "1_1") (pintype "passive"))
      (node (ref "C457") (pin "1") (pinfunction "1_1") (pintype "passive"))
      (node (ref "C458") (pin "1") (pinfunction "1_1") (pintype "passive"))
      (node (ref "C459") (pin "1") (pinfunction "1_1") (pintype "passive"))
      (node (ref "C460") (pin "1") (pinfunction "1_1") (pintype "passive"))
      (node (ref "C461") (pin "1") (pinfunction "1_1") (pintype "passive"))
      (node (ref "C462") (pin "1") (pinfunction "1_1") (pintype "passive"))
      (node (ref "C463") (pin "1") (pinfunction "1_1") (pintype "passive"))
      (node (ref "C464") (pin "1") (pinfunction "1_1") (pintype "passive"))
      (node (ref "C465") (pin "1") (pinfunction "1_1") (pintype "passive"))
      (node (ref "C466") (pin "1") (pinfunction "1_1") (pintype "passive"))
      (node (ref "C467") (pin "1") (pinfunction "1_1") (pintype "passive"))
      (node (ref "C468") (pin "1") (pinfunction "1_1") (pintype "passive"))
      (node (ref "C469") (pin "1") (pinfunction "1_1") (pintype "passive"))
      (node (ref "C470") (pin "1") (pinfunction "1_1") (pintype "passive"))
      (node (ref "C471") (pin "1") (pinfunction "1_1") (pintype "passive"))
      (node (ref "C472") (pin "1") (pinfunction "1_1") (pintype "passive"))
      (node (ref "C473") (pin "1") (pinfunction "1_1") (pintype "passive"))
      (node (ref "C474") (pin "1") (pinfunction "1_1") (pintype "passive"))
      (node (ref "C475") (pin "1") (pinfunction "1_1") (pintype "passive"))
      (node (ref "C476") (pin "1") (pinfunction "1_1") (pintype "passive"))
      (node (ref "C477") (pin "1") (pinfunction "1_1") (pintype "passive"))
      (node (ref "C478") (pin "1") (pinfunction "1_1") (pintype "passive"))
      (node (ref "C479") (pin "1") (pinfunction "1_1") (pintype "passive"))
      (node (ref "C480") (pin "1") (pinfunction "1_1") (pintype "passive"))
      (node (ref "C481") (pin "1") (pinfunction "1_1") (pintype "passive"))
      (node (ref "C482") (pin "1") (pinfunction "1_1") (pintype "passive"))
      (node (ref "C483") (pin "1") (pinfunction "1_1") (pintype "passive"))
      (node (ref "C484") (pin "1") (pinfunction "1_1") (pintype "passive"))
      (node (ref "C485") (pin "1") (pinfunction "1_1") (pintype "passive"))
      (node (ref "C486") (pin "1") (pinfunction "1_1") (pintype "passive"))
      (node (ref "C487") (pin "1") (pinfunction "1_1") (pintype "passive"))
      (node (ref "C488") (pin "1") (pinfunction "1_1") (pintype "passive"))
      (node (ref "C489") (pin "1") (pinfunction "1_1") (pintype "passive"))
      (node (ref "C490") (pin "1") (pinfunction "1_1") (pintype "passive"))
      (node (ref "C491") (pin "1") (pinfunction "1_1") (pintype "passive"))
      (node (ref "C652") (pin "1") (pinfunction "1_1") (pintype "passive"))
      (node (ref "C653") (pin "2") (pinfunction "2_2") (pintype "passive"))
      (node (ref "C654") (pin "1") (pinfunction "1_1") (pintype "passive"))
      (node (ref "C655") (pin "1") (pinfunction "1_1") (pintype "passive"))
      (node (ref "C656") (pin "2") (pinfunction "2_2") (pintype "passive"))
      (node (ref "C657") (pin "1") (pinfunction "1_1") (pintype "passive"))
      (node (ref "C658") (pin "1") (pinfunction "1_1") (pintype "passive"))
      (node (ref "C659") (pin "2") (pinfunction "2_2") (pintype "passive"))
      (node (ref "C66") (pin "2") (pinfunction "2_2") (pintype "passive"))
      (node (ref "C660") (pin "1") (pinfunction "1_1") (pintype "passive"))
      (node (ref "C661") (pin "1") (pinfunction "1_1") (pintype "passive"))
      (node (ref "C662") (pin "2") (pinfunction "2_2") (pintype "passive"))
      (node (ref "C663") (pin "1") (pinfunction "1_1") (pintype "passive"))
      (node (ref "C664") (pin "1") (pinfunction "1_1") (pintype "passive"))
      (node (ref "C665") (pin "2") (pinfunction "2_2") (pintype "passive"))
      (node (ref "C666") (pin "1") (pinfunction "1_1") (pintype "passive"))
      (node (ref "C667") (pin "1") (pinfunction "1_1") (pintype "passive"))
      (node (ref "C668") (pin "2") (pinfunction "2_2") (pintype "passive"))
      (node (ref "C669") (pin "1") (pinfunction "1_1") (pintype "passive"))
      (node (ref "C67") (pin "2") (pinfunction "2_2") (pintype "passive"))
      (node (ref "C670") (pin "1") (pinfunction "1_1") (pintype "passive"))
      (node (ref "C671") (pin "2") (pinfunction "2_2") (pintype "passive"))
      (node (ref "C672") (pin "1") (pinfunction "1_1") (pintype "passive"))
      (node (ref "C673") (pin "1") (pinfunction "1_1") (pintype "passive"))
      (node (ref "C674") (pin "2") (pinfunction "2_2") (pintype "passive"))
      (node (ref "C675") (pin "1") (pinfunction "1_1") (pintype "passive"))
      (node (ref "C676") (pin "1") (pinfunction "1_1") (pintype "passive"))
      (node (ref "C677") (pin "2") (pinfunction "2_2") (pintype "passive"))
      (node (ref "C678") (pin "1") (pinfunction "1_1") (pintype "passive"))
      (node (ref "C679") (pin "1") (pinfunction "1_1") (pintype "passive"))
      (node (ref "C68") (pin "2") (pinfunction "2_2") (pintype "passive"))
      (node (ref "C680") (pin "2") (pinfunction "2_2") (pintype "passive"))
      (node (ref "C681") (pin "1") (pinfunction "1_1") (pintype "passive"))
      (node (ref "C71") (pin "2") (pinfunction "2_2") (pintype "passive"))
      (node (ref "C72") (pin "2") (pinfunction "2_2") (pintype "passive"))
      (node (ref "C73") (pin "2") (pinfunction "2_2") (pintype "passive"))
      (node (ref "C742") (pin "1") (pinfunction "1_1") (pintype "passive"))
      (node (ref "C743") (pin "2") (pinfunction "2_2") (pintype "passive"))
      (node (ref "C744") (pin "1") (pinfunction "1_1") (pintype "passive"))
      (node (ref "C745") (pin "1") (pinfunction "1_1") (pintype "passive"))
      (node (ref "C746") (pin "2") (pinfunction "2_2") (pintype "passive"))
      (node (ref "C747") (pin "1") (pinfunction "1_1") (pintype "passive"))
      (node (ref "C748") (pin "1") (pinfunction "1_1") (pintype "passive"))
      (node (ref "C749") (pin "2") (pinfunction "2_2") (pintype "passive"))
      (node (ref "C750") (pin "1") (pinfunction "1_1") (pintype "passive"))
      (node (ref "C751") (pin "1") (pinfunction "1_1") (pintype "passive"))
      (node (ref "C752") (pin "2") (pinfunction "2_2") (pintype "passive"))
      (node (ref "C753") (pin "1") (pinfunction "1_1") (pintype "passive"))
      (node (ref "C754") (pin "1") (pinfunction "1_1") (pintype "passive"))
      (node (ref "C755") (pin "2") (pinfunction "2_2") (pintype "passive"))
      (node (ref "C756") (pin "1") (pinfunction "1_1") (pintype "passive"))
      (node (ref "C757") (pin "1") (pinfunction "1_1") (pintype "passive"))
      (node (ref "C758") (pin "2") (pinfunction "2_2") (pintype "passive"))
      (node (ref "C759") (pin "1") (pinfunction "1_1") (pintype "passive"))
      (node (ref "C760") (pin "1") (pinfunction "1_1") (pintype "passive"))
      (node (ref "C761") (pin "2") (pinfunction "2_2") (pintype "passive"))
      (node (ref "C762") (pin "1") (pinfunction "1_1") (pintype "passive"))
      (node (ref "C763") (pin "1") (pinfunction "1_1") (pintype "passive"))
      (node (ref "C764") (pin "2") (pinfunction "2_2") (pintype "passive"))
      (node (ref "C765") (pin "1") (pinfunction "1_1") (pintype "passive"))
      (node (ref "C766") (pin "1") (pinfunction "1_1") (pintype "passive"))
      (node (ref "C767") (pin "2") (pinfunction "2_2") (pintype "passive"))
      (node (ref "C768") (pin "1") (pinfunction "1_1") (pintype "passive"))
      (node (ref "C769") (pin "1") (pinfunction "1_1") (pintype "passive"))
      (node (ref "C770") (pin "2") (pinfunction "2_2") (pintype "passive"))
      (node (ref "C771") (pin "1") (pinfunction "1_1") (pintype "passive"))
      (node (ref "C832") (pin "1") (pinfunction "1_1") (pintype "passive"))
      (node (ref "C833") (pin "2") (pinfunction "2_2") (pintype "passive"))
      (node (ref "C834") (pin "1") (pinfunction "1_1") (pintype "passive"))
      (node (ref "C835") (pin "1") (pinfunction "1_1") (pintype "passive"))
      (node (ref "C836") (pin "2") (pinfunction "2_2") (pintype "passive"))
      (node (ref "C837") (pin "1") (pinfunction "1_1") (pintype "passive"))
      (node (ref "C838") (pin "1") (pinfunction "1_1") (pintype "passive"))
      (node (ref "C839") (pin "2") (pinfunction "2_2") (pintype "passive"))
      (node (ref "C840") (pin "1") (pinfunction "1_1") (pintype "passive"))
      (node (ref "C841") (pin "1") (pinfunction "1_1") (pintype "passive"))
      (node (ref "C842") (pin "2") (pinfunction "2_2") (pintype "passive"))
      (node (ref "C843") (pin "1") (pinfunction "1_1") (pintype "passive"))
      (node (ref "C844") (pin "1") (pinfunction "1_1") (pintype "passive"))
      (node (ref "C845") (pin "2") (pinfunction "2_2") (pintype "passive"))
      (node (ref "C846") (pin "1") (pinfunction "1_1") (pintype "passive"))
      (node (ref "C847") (pin "1") (pinfunction "1_1") (pintype "passive"))
      (node (ref "C848") (pin "2") (pinfunction "2_2") (pintype "passive"))
      (node (ref "C849") (pin "1") (pinfunction "1_1") (pintype "passive"))
      (node (ref "C850") (pin "1") (pinfunction "1_1") (pintype "passive"))
      (node (ref "C851") (pin "2") (pinfunction "2_2") (pintype "passive"))
      (node (ref "C852") (pin "1") (pinfunction "1_1") (pintype "passive"))
      (node (ref "C853") (pin "1") (pinfunction "1_1") (pintype "passive"))
      (node (ref "C854") (pin "2") (pinfunction "2_2") (pintype "passive"))
      (node (ref "C855") (pin "1") (pinfunction "1_1") (pintype "passive"))
      (node (ref "C856") (pin "1") (pinfunction "1_1") (pintype "passive"))
      (node (ref "C857") (pin "2") (pinfunction "2_2") (pintype "passive"))
      (node (ref "C858") (pin "1") (pinfunction "1_1") (pintype "passive"))
      (node (ref "C859") (pin "1") (pinfunction "1_1") (pintype "passive"))
      (node (ref "C860") (pin "2") (pinfunction "2_2") (pintype "passive"))
      (node (ref "C861") (pin "1") (pinfunction "1_1") (pintype "passive"))
      (node (ref "C922") (pin "1") (pinfunction "1_1") (pintype "passive"))
      (node (ref "C923") (pin "2") (pinfunction "2_2") (pintype "passive"))
      (node (ref "C924") (pin "1") (pinfunction "1_1") (pintype "passive"))
      (node (ref "C925") (pin "1") (pinfunction "1_1") (pintype "passive"))
      (node (ref "C926") (pin "2") (pinfunction "2_2") (pintype "passive"))
      (node (ref "C927") (pin "1") (pinfunction "1_1") (pintype "passive"))
      (node (ref "C928") (pin "1") (pinfunction "1_1") (pintype "passive"))
      (node (ref "C929") (pin "2") (pinfunction "2_2") (pintype "passive"))
      (node (ref "C930") (pin "1") (pinfunction "1_1") (pintype "passive"))
      (node (ref "C931") (pin "1") (pinfunction "1_1") (pintype "passive"))
      (node (ref "C932") (pin "2") (pinfunction "2_2") (pintype "passive"))
      (node (ref "C933") (pin "1") (pinfunction "1_1") (pintype "passive"))
      (node (ref "C934") (pin "1") (pinfunction "1_1") (pintype "passive"))
      (node (ref "C935") (pin "2") (pinfunction "2_2") (pintype "passive"))
      (node (ref "C936") (pin "1") (pinfunction "1_1") (pintype "passive"))
      (node (ref "C937") (pin "1") (pinfunction "1_1") (pintype "passive"))
      (node (ref "C938") (pin "2") (pinfunction "2_2") (pintype "passive"))
      (node (ref "C939") (pin "1") (pinfunction "1_1") (pintype "passive"))
      (node (ref "C940") (pin "1") (pinfunction "1_1") (pintype "passive"))
      (node (ref "C941") (pin "2") (pinfunction "2_2") (pintype "passive"))
      (node (ref "C942") (pin "1") (pinfunction "1_1") (pintype "passive"))
      (node (ref "C943") (pin "1") (pinfunction "1_1") (pintype "passive"))
      (node (ref "C944") (pin "2") (pinfunction "2_2") (pintype "passive"))
      (node (ref "C945") (pin "1") (pinfunction "1_1") (pintype "passive"))
      (node (ref "C946") (pin "1") (pinfunction "1_1") (pintype "passive"))
      (node (ref "C947") (pin "2") (pinfunction "2_2") (pintype "passive"))
      (node (ref "C948") (pin "1") (pinfunction "1_1") (pintype "passive"))
      (node (ref "C949") (pin "1") (pinfunction "1_1") (pintype "passive"))
      (node (ref "C950") (pin "2") (pinfunction "2_2") (pintype "passive"))
      (node (ref "C951") (pin "1") (pinfunction "1_1") (pintype "passive"))
      (node (ref "C952") (pin "1") (pinfunction "1_1") (pintype "passive"))
      (node (ref "C953") (pin "2") (pinfunction "2_2") (pintype "passive"))
      (node (ref "C954") (pin "1") (pinfunction "1_1") (pintype "passive"))
      (node (ref "C955") (pin "1") (pinfunction "1_1") (pintype "passive"))
      (node (ref "C956") (pin "2") (pinfunction "2_2") (pintype "passive"))
      (node (ref "C957") (pin "1") (pinfunction "1_1") (pintype "passive"))
      (node (ref "C958") (pin "1") (pinfunction "1_1") (pintype "passive"))
      (node (ref "C959") (pin "2") (pinfunction "2_2") (pintype "passive"))
      (node (ref "C960") (pin "1") (pinfunction "1_1") (pintype "passive"))
      (node (ref "C961") (pin "1") (pinfunction "1_1") (pintype "passive"))
      (node (ref "C962") (pin "2") (pinfunction "2_2") (pintype "passive"))
      (node (ref "C963") (pin "1") (pinfunction "1_1") (pintype "passive"))
      (node (ref "C964") (pin "1") (pinfunction "1_1") (pintype "passive"))
      (node (ref "C965") (pin "2") (pinfunction "2_2") (pintype "passive"))
      (node (ref "C966") (pin "1") (pinfunction "1_1") (pintype "passive"))
      (node (ref "C967") (pin "1") (pinfunction "1_1") (pintype "passive"))
      (node (ref "C968") (pin "2") (pinfunction "2_2") (pintype "passive"))
      (node (ref "C969") (pin "1") (pinfunction "1_1") (pintype "passive"))
      (node (ref "C970") (pin "1") (pinfunction "1_1") (pintype "passive"))
      (node (ref "C971") (pin "2") (pinfunction "2_2") (pintype "passive"))
      (node (ref "C972") (pin "1") (pinfunction "1_1") (pintype "passive"))
      (node (ref "C973") (pin "1") (pinfunction "1_1") (pintype "passive"))
      (node (ref "C974") (pin "2") (pinfunction "2_2") (pintype "passive"))
      (node (ref "C975") (pin "1") (pinfunction "1_1") (pintype "passive"))
      (node (ref "C976") (pin "1") (pinfunction "1_1") (pintype "passive"))
      (node (ref "C977") (pin "2") (pinfunction "2_2") (pintype "passive"))
      (node (ref "C978") (pin "1") (pinfunction "1_1") (pintype "passive"))
      (node (ref "C979") (pin "1") (pinfunction "1_1") (pintype "passive"))
      (node (ref "C98") (pin "2") (pinfunction "2_2") (pintype "passive"))
      (node (ref "C980") (pin "2") (pinfunction "2_2") (pintype "passive"))
      (node (ref "C981") (pin "1") (pinfunction "1_1") (pintype "passive"))
      (node (ref "C982") (pin "1") (pinfunction "1_1") (pintype "passive"))
      (node (ref "C983") (pin "2") (pinfunction "2_2") (pintype "passive"))
      (node (ref "C984") (pin "1") (pinfunction "1_1") (pintype "passive"))
      (node (ref "C985") (pin "1") (pinfunction "1_1") (pintype "passive"))
      (node (ref "C986") (pin "2") (pinfunction "2_2") (pintype "passive"))
      (node (ref "C987") (pin "1") (pinfunction "1_1") (pintype "passive"))
      (node (ref "C988") (pin "1") (pinfunction "1_1") (pintype "passive"))
      (node (ref "C989") (pin "2") (pinfunction "2_2") (pintype "passive"))
      (node (ref "C99") (pin "2") (pinfunction "2_2") (pintype "passive"))
      (node (ref "C990") (pin "1") (pinfunction "1_1") (pintype "passive"))
      (node (ref "C991") (pin "1") (pinfunction "1_1") (pintype "passive"))
      (node (ref "C992") (pin "2") (pinfunction "2_2") (pintype "passive"))
      (node (ref "C993") (pin "1") (pinfunction "1_1") (pintype "passive"))
      (node (ref "C994") (pin "1") (pinfunction "1_1") (pintype "passive"))
      (node (ref "C995") (pin "2") (pinfunction "2_2") (pintype "passive"))
      (node (ref "C996") (pin "1") (pinfunction "1_1") (pintype "passive"))
      (node (ref "C997") (pin "1") (pinfunction "1_1") (pintype "passive"))
      (node (ref "C998") (pin "2") (pinfunction "2_2") (pintype "passive"))
      (node (ref "C999") (pin "1") (pinfunction "1_1") (pintype "passive"))
      (node (ref "L1") (pin "2") (pinfunction "2_2") (pintype "passive"))
      (node (ref "L10") (pin "2") (pinfunction "2_2") (pintype "passive"))
      (node (ref "L13") (pin "2") (pinfunction "2_2") (pintype "passive"))
      (node (ref "L14") (pin "2") (pinfunction "2_2") (pintype "passive"))
      (node (ref "L2") (pin "2") (pinfunction "2_2") (pintype "passive"))
      (node (ref "L5") (pin "2") (pinfunction "2_2") (pintype "passive"))
      (node (ref "L6") (pin "2") (pinfunction "2_2") (pintype "passive"))
      (node (ref "L9") (pin "2") (pinfunction "2_2") (pintype "passive"))
    )
    (net (code "2") (name "/3.3V") (class "Default")
      (node (ref "C120") (pin "1") (pinfunction "1_1") (pintype "passive"))
      (node (ref "C121") (pin "1") (pinfunction "1_1") (pintype "passive"))
      (node (ref "C24") (pin "1") (pinfunction "1_1") (pintype "passive"))
      (node (ref "C25") (pin "1") (pinfunction "1_1") (pintype "passive"))
      (node (ref "C56") (pin "1") (pinfunction "1_1") (pintype "passive"))
      (node (ref "C57") (pin "1") (pinfunction "1_1") (pintype "passive"))
      (node (ref "C88") (pin "1") (pinfunction "1_1") (pintype "passive"))
      (node (ref "C89") (pin "1") (pinfunction "1_1") (pintype "passive"))
      (node (ref "U11") (pin "6") (pinfunction "VLOGIC_6") (pintype "passive"))
      (node (ref "U12") (pin "6") (pinfunction "VLOGIC_6") (pintype "passive"))
      (node (ref "U15") (pin "6") (pinfunction "VLOGIC_6") (pintype "passive"))
      (node (ref "U16") (pin "6") (pinfunction "VLOGIC_6") (pintype "passive"))
      (node (ref "U19") (pin "6") (pinfunction "VLOGIC_6") (pintype "passive"))
      (node (ref "U20") (pin "6") (pinfunction "VLOGIC_6") (pintype "passive"))
      (node (ref "U23") (pin "6") (pinfunction "VLOGIC_6") (pintype "passive"))
      (node (ref "U24") (pin "6") (pinfunction "VLOGIC_6") (pintype "passive"))
    )
    (net (code "3") (name "/5.0V") (class "Default")
      (node (ref "C116") (pin "2") (pinfunction "2_2") (pintype "passive"))
      (node (ref "C117") (pin "2") (pinfunction "2_2") (pintype "passive"))
      (node (ref "C20") (pin "2") (pinfunction "2_2") (pintype "passive"))
      (node (ref "C21") (pin "2") (pinfunction "2_2") (pintype "passive"))
      (node (ref "C52") (pin "2") (pinfunction "2_2") (pintype "passive"))
      (node (ref "C53") (pin "2") (pinfunction "2_2") (pintype "passive"))
      (node (ref "C84") (pin "2") (pinfunction "2_2") (pintype "passive"))
      (node (ref "C85") (pin "2") (pinfunction "2_2") (pintype "passive"))
      (node (ref "D10") (pin "2") (pinfunction "A_2") (pintype "passive"))
      (node (ref "D11") (pin "2") (pinfunction "A_2") (pintype "passive"))
      (node (ref "D14") (pin "2") (pinfunction "A_2") (pintype "passive"))
      (node (ref "D15") (pin "2") (pinfunction "A_2") (pintype "passive"))
      (node (ref "D18") (pin "2") (pinfunction "A_2") (pintype "passive"))
      (node (ref "D19") (pin "2") (pinfunction "A_2") (pintype "passive"))
      (node (ref "D22") (pin "2") (pinfunction "A_2") (pintype "passive"))
      (node (ref "D23") (pin "2") (pinfunction "A_2") (pintype "passive"))
      (node (ref "U11") (pin "7") (pinfunction "VCC_7") (pintype "passive"))
      (node (ref "U12") (pin "7") (pinfunction "VCC_7") (pintype "passive"))
      (node (ref "U15") (pin "7") (pinfunction "VCC_7") (pintype "passive"))
      (node (ref "U16") (pin "7") (pinfunction "VCC_7") (pintype "passive"))
      (node (ref "U19") (pin "7") (pinfunction "VCC_7") (pintype "passive"))
      (node (ref "U20") (pin "7") (pinfunction "VCC_7") (pintype "passive"))
      (node (ref "U23") (pin "7") (pinfunction "VCC_7") (pintype "passive"))
      (node (ref "U24") (pin "7") (pinfunction "VCC_7") (pintype "passive"))
    )
    (net (code "4") (name "/12V") (class "Default")
      (node (ref "C101") (pin "2") (pinfunction "2_2") (pintype "passive"))
      (node (ref "C102") (pin "2") (pinfunction "2_2") (pintype "passive"))
      (node (ref "C128") (pin "2") (pinfunction "2_2") (pintype "passive"))
      (node (ref "C129") (pin "2") (pinfunction "2_2") (pintype "passive"))
      (node (ref "C133") (pin "2") (pinfunction "2_2") (pintype "passive"))
      (node (ref "C134") (pin "2") (pinfunction "2_2") (pintype "passive"))
      (node (ref "C32") (pin "2") (pinfunction "2_2") (pintype "passive"))
      (node (ref "C33") (pin "2") (pinfunction "2_2") (pintype "passive"))
      (node (ref "C348") (pin "2") (pinfunction "2_2") (pintype "passive"))
      (node (ref "C349") (pin "2") (pinfunction "2_2") (pintype "passive"))
      (node (ref "C37") (pin "2") (pinfunction "2_2") (pintype "passive"))
      (node (ref "C377") (pin "1") (pinfunction "1_1") (pintype "passive"))
      (node (ref "C378") (pin "1") (pinfunction "1_1") (pintype "passive"))
      (node (ref "C379") (pin "1") (pinfunction "1_1") (pintype "passive"))
      (node (ref "C38") (pin "2") (pinfunction "2_2") (pintype "passive"))
      (node (ref "C380") (pin "1") (pinfunction "1_1") (pintype "passive"))
      (node (ref "C381") (pin "1") (pinfunction "1_1") (pintype "passive"))
      (node (ref "C382") (pin "1") (pinfunction "1_1") (pintype "passive"))
      (node (ref "C383") (pin "1") (pinfunction "1_1") (pintype "passive"))
      (node (ref "C384") (pin "1") (pinfunction "1_1") (pintype "passive"))
      (node (ref "C385") (pin "1") (pinfunction "1_1") (pintype "passive"))
      (node (ref "C386") (pin "1") (pinfunction "1_1") (pintype "passive"))
      (node (ref "C387") (pin "1") (pinfunction "1_1") (pintype "passive"))
      (node (ref "C388") (pin "1") (pinfunction "1_1") (pintype "passive"))
      (node (ref "C389") (pin "1") (pinfunction "1_1") (pintype "passive"))
      (node (ref "C390") (pin "1") (pinfunction "1_1") (pintype "passive"))
      (node (ref "C391") (pin "1") (pinfunction "1_1") (pintype "passive"))
      (node (ref "C392") (pin "1") (pinfunction "1_1") (pintype "passive"))
      (node (ref "C402") (pin "2") (pinfunction "2_2") (pintype "passive"))
      (node (ref "C403") (pin "2") (pinfunction "2_2") (pintype "passive"))
      (node (ref "C404") (pin "2") (pinfunction "2_2") (pintype "passive"))
      (node (ref "C405") (pin "2") (pinfunction "2_2") (pintype "passive"))
      (node (ref "C406") (pin "2") (pinfunction "2_2") (pintype "passive"))
      (node (ref "C407") (pin "2") (pinfunction "2_2") (pintype "passive"))
      (node (ref "C420") (pin "2") (pinfunction "2_2") (pintype "passive"))
      (node (ref "C421") (pin "2") (pinfunction "2_2") (pintype "passive"))
      (node (ref "C422") (pin "2") (pinfunction "2_2") (pintype "passive"))
      (node (ref "C423") (pin "2") (pinfunction "2_2") (pintype "passive"))
      (node (ref "C424") (pin "2") (pinfunction "2_2") (pintype "passive"))
      (node (ref "C425") (pin "2") (pinfunction "2_2") (pintype "passive"))
      (node (ref "C426") (pin "2") (pinfunction "2_2") (pintype "passive"))
      (node (ref "C427") (pin "2") (pinfunction "2_2") (pintype "passive"))
      (node (ref "C428") (pin "1") (pinfunction "1_1") (pintype "passive"))
      (node (ref "C429") (pin "1") (pinfunction "1_1") (pintype "passive"))
      (node (ref "C430") (pin "1") (pinfunction "1_1") (pintype "passive"))
      (node (ref "C431") (pin "1") (pinfunction "1_1") (pintype "passive"))
      (node (ref "C432") (pin "1") (pinfunction "1_1") (pintype "passive"))
      (node (ref "C433") (pin "1") (pinfunction "1_1") (pintype "passive"))
      (node (ref "C434") (pin "1") (pinfunction "1_1") (pintype "passive"))
      (node (ref "C435") (pin "1") (pinfunction "1_1") (pintype "passive"))
      (node (ref "C436") (pin "1") (pinfunction "1_1") (pintype "passive"))
      (node (ref "C437") (pin "1") (pinfunction "1_1") (pintype "passive"))
      (node (ref "C438") (pin "1") (pinfunction "1_1") (pintype "passive"))
      (node (ref "C439") (pin "1") (pinfunction "1_1") (pintype "passive"))
      (node (ref "C440") (pin "1") (pinfunction "1_1") (pintype "passive"))
      (node (ref "C441") (pin "1") (pinfunction "1_1") (pintype "passive"))
      (node (ref "C442") (pin "1") (pinfunction "1_1") (pintype "passive"))
      (node (ref "C443") (pin "1") (pinfunction "1_1") (pintype "passive"))
      (node (ref "C593") (pin "2") (pinfunction "2_2") (pintype "passive"))
      (node (ref "C596") (pin "2") (pinfunction "2_2") (pintype "passive"))
      (node (ref "C598") (pin "1") (pinfunction "1_1") (pintype "passive"))
      (node (ref "C599") (pin "2") (pinfunction "2_2") (pintype "passive"))
      (node (ref "C600") (pin "1") (pinfunction "1_1") (pintype "passive"))
      (node (ref "C602") (pin "2") (pinfunction "2_2") (pintype "passive"))
      (node (ref "C603") (pin "1") (pinfunction "1_1") (pintype "passive"))
      (node (ref "C605") (pin "2") (pinfunction "2_2") (pintype "passive"))
      (node (ref "C606") (pin "1") (pinfunction "1_1") (pintype "passive"))
      (node (ref "C64") (pin "2") (pinfunction "2_2") (pintype "passive"))
      (node (ref "C640") (pin "1") (pinfunction "1_1") (pintype "passive"))
      (node (ref "C642") (pin "1") (pinfunction "1_1") (pintype "passive"))
      (node (ref "C643") (pin "1") (pinfunction "1_1") (pintype "passive"))
      (node (ref "C645") (pin "1") (pinfunction "1_1") (pintype "passive"))
      (node (ref "C646") (pin "1") (pinfunction "1_1") (pintype "passive"))
      (node (ref "C65") (pin "2") (pinfunction "2_2") (pintype "passive"))
      (node (ref "C686") (pin "2") (pinfunction "2_2") (pintype "passive"))
      (node (ref "C688") (pin "1") (pinfunction "1_1") (pintype "passive"))
      (node (ref "C689") (pin "2") (pinfunction "2_2") (pintype "passive"))
      (node (ref "C69") (pin "2") (pinfunction "2_2") (pintype "passive"))
      (node (ref "C692") (pin "2") (pinfunction "2_2") (pintype "passive"))
      (node (ref "C695") (pin "2") (pinfunction "2_2") (pintype "passive"))
      (node (ref "C70") (pin "2") (pinfunction "2_2") (pintype "passive"))
      (node (ref "C711") (pin "1") (pinfunction "1_1") (pintype "passive"))
      (node (ref "C712") (pin "1") (pinfunction "1_1") (pintype "passive"))
      (node (ref "C714") (pin "1") (pinfunction "1_1") (pintype "passive"))
      (node (ref "C715") (pin "1") (pinfunction "1_1") (pintype "passive"))
      (node (ref "C717") (pin "1") (pinfunction "1_1") (pintype "passive"))
      (node (ref "C776") (pin "2") (pinfunction "2_2") (pintype "passive"))
      (node (ref "C779") (pin "2") (pinfunction "2_2") (pintype "passive"))
      (node (ref "C782") (pin "2") (pinfunction "2_2") (pintype "passive"))
      (node (ref "C785") (pin "2") (pinfunction "2_2") (pintype "passive"))
      (node (ref "C807") (pin "1") (pinfunction "1_1") (pintype "passive"))
      (node (ref "C808") (pin "1") (pinfunction "1_1") (pintype "passive"))
      (node (ref "C810") (pin "1") (pinfunction "1_1") (pintype "passive"))
      (node (ref "C811") (pin "1") (pinfunction "1_1") (pintype "passive"))
      (node (ref "C813") (pin "1") (pinfunction "1_1") (pintype "passive"))
      (node (ref "C814") (pin "1") (pinfunction "1_1") (pintype "passive"))
      (node (ref "C866") (pin "2") (pinfunction "2_2") (pintype "passive"))
      (node (ref "C868") (pin "1") (pinfunction "1_1") (pintype "passive"))
      (node (ref "C869") (pin "2") (pinfunction "2_2") (pintype "passive"))
      (node (ref "C872") (pin "2") (pinfunction "2_2") (pintype "passive"))
      (node (ref "C876") (pin "1") (pinfunction "1_1") (pintype "passive"))
      (node (ref "C877") (pin "1") (pinfunction "1_1") (pintype "passive"))
      (node (ref "C879") (pin "1") (pinfunction "1_1") (pintype "passive"))
      (node (ref "C880") (pin "1") (pinfunction "1_1") (pintype "passive"))
      (node (ref "C882") (pin "1") (pinfunction "1_1") (pintype "passive"))
      (node (ref "C913") (pin "1") (pinfunction "1_1") (pintype "passive"))
      (node (ref "C915") (pin "1") (pinfunction "1_1") (pintype "passive"))
      (node (ref "C916") (pin "1") (pinfunction "1_1") (pintype "passive"))
      (node (ref "C918") (pin "1") (pinfunction "1_1") (pintype "passive"))
      (node (ref "C919") (pin "1") (pinfunction "1_1") (pintype "passive"))
      (node (ref "C96") (pin "2") (pinfunction "2_2") (pintype "passive"))
      (node (ref "C97") (pin "2") (pinfunction "2_2") (pintype "passive"))
      (node (ref "Q1") (pin "5") (pinfunction "D_5") (pintype "passive"))
      (node (ref "Q1") (pin "6") (pinfunction "D_6") (pintype "passive"))
      (node (ref "Q1") (pin "7") (pinfunction "D_7") (pintype "passive"))
      (node (ref "Q1") (pin "8") (pinfunction "D_8") (pintype "passive"))
      (node (ref "Q13") (pin "5") (pinfunction "D_5") (pintype "passive"))
      (node (ref "Q13") (pin "6") (pinfunction "D_6") (pintype "passive"))
      (node (ref "Q13") (pin "7") (pinfunction "D_7") (pintype "passive"))
      (node (ref "Q13") (pin "8") (pinfunction "D_8") (pintype "passive"))
      (node (ref "Q14") (pin "5") (pinfunction "D_5") (pintype "passive"))
      (node (ref "Q14") (pin "6") (pinfunction "D_6") (pintype "passive"))
      (node (ref "Q14") (pin "7") (pinfunction "D_7") (pintype "passive"))
      (node (ref "Q14") (pin "8") (pinfunction "D_8") (pintype "passive"))
      (node (ref "Q2") (pin "5") (pinfunction "D_5") (pintype "passive"))
      (node (ref "Q2") (pin "6") (pinfunction "D_6") (pintype "passive"))
      (node (ref "Q2") (pin "7") (pinfunction "D_7") (pintype "passive"))
      (node (ref "Q2") (pin "8") (pinfunction "D_8") (pintype "passive"))
      (node (ref "Q25") (pin "5") (pinfunction "D_5") (pintype "passive"))
      (node (ref "Q25") (pin "6") (pinfunction "D_6") (pintype "passive"))
      (node (ref "Q25") (pin "7") (pinfunction "D_7") (pintype "passive"))
      (node (ref "Q25") (pin "8") (pinfunction "D_8") (pintype "passive"))
      (node (ref "Q26") (pin "5") (pinfunction "D_5") (pintype "passive"))
      (node (ref "Q26") (pin "6") (pinfunction "D_6") (pintype "passive"))
      (node (ref "Q26") (pin "7") (pinfunction "D_7") (pintype "passive"))
      (node (ref "Q26") (pin "8") (pinfunction "D_8") (pintype "passive"))
      (node (ref "Q37") (pin "5") (pinfunction "D_5") (pintype "passive"))
      (node (ref "Q37") (pin "6") (pinfunction "D_6") (pintype "passive"))
      (node (ref "Q37") (pin "7") (pinfunction "D_7") (pintype "passive"))
      (node (ref "Q37") (pin "8") (pinfunction "D_8") (pintype "passive"))
      (node (ref "Q38") (pin "5") (pinfunction "D_5") (pintype "passive"))
      (node (ref "Q38") (pin "6") (pinfunction "D_6") (pintype "passive"))
      (node (ref "Q38") (pin "7") (pinfunction "D_7") (pintype "passive"))
      (node (ref "Q38") (pin "8") (pinfunction "D_8") (pintype "passive"))
    )
    (net (code "5") (name "/BOOT1") (class "Default")
      (node (ref "C28") (pin "1") (pinfunction "1_1") (pintype "passive"))
      (node (ref "D10") (pin "1") (pinfunction "C_1") (pintype "passive"))
      (node (ref "U11") (pin "8") (pinfunction "BOOST_8") (pintype "passive"))
    )
    (net (code "6") (name "/BOOT2") (class "Default")
      (node (ref "C60") (pin "1") (pinfunction "1_1") (pintype "passive"))
      (node (ref "D14") (pin "1") (pinfunction "C_1") (pintype "passive"))
      (node (ref "U15") (pin "8") (pinfunction "BOOST_8") (pintype "passive"))
    )
    (net (code "7") (name "/BOOT3") (class "Default")
      (node (ref "C92") (pin "1") (pinfunction "1_1") (pintype "passive"))
      (node (ref "D18") (pin "1") (pinfunction "C_1") (pintype "passive"))
      (node (ref "U19") (pin "8") (pinfunction "BOOST_8") (pintype "passive"))
    )
    (net (code "8") (name "/BOOT4") (class "Default")
      (node (ref "C124") (pin "1") (pinfunction "1_1") (pintype "passive"))
      (node (ref "D22") (pin "1") (pinfunction "C_1") (pintype "passive"))
      (node (ref "U23") (pin "8") (pinfunction "BOOST_8") (pintype "passive"))
    )
    (net (code "9") (name "/BOOT5") (class "Default")
      (node (ref "C29") (pin "1") (pinfunction "1_1") (pintype "passive"))
      (node (ref "D11") (pin "1") (pinfunction "C_1") (pintype "passive"))
      (node (ref "U12") (pin "8") (pinfunction "BOOST_8") (pintype "passive"))
    )
    (net (code "10") (name "/BOOT6") (class "Default")
      (node (ref "C61") (pin "1") (pinfunction "1_1") (pintype "passive"))
      (node (ref "D15") (pin "1") (pinfunction "C_1") (pintype "passive"))
      (node (ref "U16") (pin "8") (pinfunction "BOOST_8") (pintype "passive"))
    )
    (net (code "11") (name "/BOOT7") (class "Default")
      (node (ref "C93") (pin "1") (pinfunction "1_1") (pintype "passive"))
      (node (ref "D19") (pin "1") (pinfunction "C_1") (pintype "passive"))
      (node (ref "U20") (pin "8") (pinfunction "BOOST_8") (pintype "passive"))
    )
    (net (code "12") (name "/BOOT8") (class "Default")
      (node (ref "C125") (pin "1") (pinfunction "1_1") (pintype "passive"))
      (node (ref "D23") (pin "1") (pinfunction "C_1") (pintype "passive"))
      (node (ref "U24") (pin "8") (pinfunction "BOOST_8") (pintype "passive"))
    )
    (net (code "13") (name "/HO1") (class "Default")
      (node (ref "Q1") (pin "4") (pinfunction "G_4") (pintype "passive"))
      (node (ref "U11") (pin "1") (pinfunction "TG_1") (pintype "passive"))
    )
    (net (code "14") (name "/HO2") (class "Default")
      (node (ref "Q13") (pin "4") (pinfunction "G_4") (pintype "passive"))
      (node (ref "U15") (pin "1") (pinfunction "TG_1") (pintype "passive"))
    )
    (net (code "15") (name "/HO3") (class "Default")
      (node (ref "Q25") (pin "4") (pinfunction "G_4") (pintype "passive"))
      (node (ref "U19") (pin "1") (pinfunction "TG_1") (pintype "passive"))
    )
    (net (code "16") (name "/HO4") (class "Default")
      (node (ref "Q37") (pin "4") (pinfunction "G_4") (pintype "passive"))
      (node (ref "U23") (pin "1") (pinfunction "TG_1") (pintype "passive"))
    )
    (net (code "17") (name "/HO5") (class "Default")
      (node (ref "Q2") (pin "4") (pinfunction "G_4") (pintype "passive"))
      (node (ref "U12") (pin "1") (pinfunction "TG_1") (pintype "passive"))
    )
    (net (code "18") (name "/HO6") (class "Default")
      (node (ref "Q14") (pin "4") (pinfunction "G_4") (pintype "passive"))
      (node (ref "U16") (pin "1") (pinfunction "TG_1") (pintype "passive"))
    )
    (net (code "19") (name "/HO7") (class "Default")
      (node (ref "Q26") (pin "4") (pinfunction "G_4") (pintype "passive"))
      (node (ref "U20") (pin "1") (pinfunction "TG_1") (pintype "passive"))
    )
    (net (code "20") (name "/HO8") (class "Default")
      (node (ref "Q38") (pin "4") (pinfunction "G_4") (pintype "passive"))
      (node (ref "U24") (pin "1") (pinfunction "TG_1") (pintype "passive"))
    )
    (net (code "21") (name "/LO1") (class "Default")
      (node (ref "Q5") (pin "4") (pinfunction "G_4") (pintype "passive"))
      (node (ref "Q6") (pin "4") (pinfunction "G_4") (pintype "passive"))
      (node (ref "U11") (pin "3") (pinfunction "BG_3") (pintype "passive"))
    )
    (net (code "22") (name "/LO2") (class "Default")
      (node (ref "Q17") (pin "4") (pinfunction "G_4") (pintype "passive"))
      (node (ref "Q18") (pin "4") (pinfunction "G_4") (pintype "passive"))
      (node (ref "U15") (pin "3") (pinfunction "BG_3") (pintype "passive"))
    )
    (net (code "23") (name "/LO3") (class "Default")
      (node (ref "Q29") (pin "4") (pinfunction "G_4") (pintype "passive"))
      (node (ref "Q30") (pin "4") (pinfunction "G_4") (pintype "passive"))
      (node (ref "U19") (pin "3") (pinfunction "BG_3") (pintype "passive"))
    )
    (net (code "24") (name "/LO4") (class "Default")
      (node (ref "Q41") (pin "4") (pinfunction "G_4") (pintype "passive"))
      (node (ref "Q42") (pin "4") (pinfunction "G_4") (pintype "passive"))
      (node (ref "U23") (pin "3") (pinfunction "BG_3") (pintype "passive"))
    )
    (net (code "25") (name "/LO5") (class "Default")
      (node (ref "Q7") (pin "4") (pinfunction "G_4") (pintype "passive"))
      (node (ref "Q8") (pin "4") (pinfunction "G_4") (pintype "passive"))
      (node (ref "U12") (pin "3") (pinfunction "BG_3") (pintype "passive"))
    )
    (net (code "26") (name "/LO6") (class "Default")
      (node (ref "Q19") (pin "4") (pinfunction "G_4") (pintype "passive"))
      (node (ref "Q20") (pin "4") (pinfunction "G_4") (pintype "passive"))
      (node (ref "U16") (pin "3") (pinfunction "BG_3") (pintype "passive"))
    )
    (net (code "27") (name "/LO7") (class "Default")
      (node (ref "Q31") (pin "4") (pinfunction "G_4") (pintype "passive"))
      (node (ref "Q32") (pin "4") (pinfunction "G_4") (pintype "passive"))
      (node (ref "U20") (pin "3") (pinfunction "BG_3") (pintype "passive"))
    )
    (net (code "28") (name "/LO8") (class "Default")
      (node (ref "Q43") (pin "4") (pinfunction "G_4") (pintype "passive"))
      (node (ref "Q44") (pin "4") (pinfunction "G_4") (pintype "passive"))
      (node (ref "U24") (pin "3") (pinfunction "BG_3") (pintype "passive"))
    )
    (net (code "29") (name "/PWM1H") (class "Default")
      (node (ref "U12") (pin "5") (pinfunction "IN_5") (pintype "passive"))
    )
    (net (code "30") (name "/PWM1L") (class "Default")
      (node (ref "U11") (pin "5") (pinfunction "IN_5") (pintype "passive"))
    )
    (net (code "31") (name "/PWM2H") (class "Default")
      (node (ref "U16") (pin "5") (pinfunction "IN_5") (pintype "passive"))
    )
    (net (code "32") (name "/PWM2L") (class "Default")
      (node (ref "U15") (pin "5") (pinfunction "IN_5") (pintype "passive"))
    )
    (net (code "33") (name "/PWM3H") (class "Default")
      (node (ref "U20") (pin "5") (pinfunction "IN_5") (pintype "passive"))
    )
    (net (code "34") (name "/PWM3L") (class "Default")
      (node (ref "U19") (pin "5") (pinfunction "IN_5") (pintype "passive"))
    )
    (net (code "35") (name "/PWM4H") (class "Default")
      (node (ref "U24") (pin "5") (pinfunction "IN_5") (pintype "passive"))
    )
    (net (code "36") (name "/PWM4L") (class "Default")
      (node (ref "U23") (pin "5") (pinfunction "IN_5") (pintype "passive"))
    )
    (net (code "37") (name "/SWN1") (class "Default")
      (node (ref "C28") (pin "2") (pinfunction "2_2") (pintype "passive"))
      (node (ref "L1") (pin "1") (pinfunction "1_1") (pintype "passive"))
      (node (ref "Q1") (pin "1") (pinfunction "S_1") (pintype "passive"))
      (node (ref "Q1") (pin "2") (pinfunction "S_2") (pintype "passive"))
      (node (ref "Q1") (pin "3") (pinfunction "S_3") (pintype "passive"))
      (node (ref "Q5") (pin "5") (pinfunction "D_5") (pintype "passive"))
      (node (ref "Q5") (pin "6") (pinfunction "D_6") (pintype "passive"))
      (node (ref "Q5") (pin "7") (pinfunction "D_7") (pintype "passive"))
      (node (ref "Q5") (pin "8") (pinfunction "D_8") (pintype "passive"))
      (node (ref "Q6") (pin "5") (pinfunction "D_5") (pintype "passive"))
      (node (ref "Q6") (pin "6") (pinfunction "D_6") (pintype "passive"))
      (node (ref "Q6") (pin "7") (pinfunction "D_7") (pintype "passive"))
      (node (ref "Q6") (pin "8") (pinfunction "D_8") (pintype "passive"))
      (node (ref "U11") (pin "2") (pinfunction "TS_2") (pintype "passive"))
    )
    (net (code "38") (name "/SWN2") (class "Default")
      (node (ref "C60") (pin "2") (pinfunction "2_2") (pintype "passive"))
      (node (ref "L5") (pin "1") (pinfunction "1_1") (pintype "passive"))
      (node (ref "Q13") (pin "1") (pinfunction "S_1") (pintype "passive"))
      (node (ref "Q13") (pin "2") (pinfunction "S_2") (pintype "passive"))
      (node (ref "Q13") (pin "3") (pinfunction "S_3") (pintype "passive"))
      (node (ref "Q17") (pin "5") (pinfunction "D_5") (pintype "passive"))
      (node (ref "Q17") (pin "6") (pinfunction "D_6") (pintype "passive"))
      (node (ref "Q17") (pin "7") (pinfunction "D_7") (pintype "passive"))
      (node (ref "Q17") (pin "8") (pinfunction "D_8") (pintype "passive"))
      (node (ref "Q18") (pin "5") (pinfunction "D_5") (pintype "passive"))
      (node (ref "Q18") (pin "6") (pinfunction "D_6") (pintype "passive"))
      (node (ref "Q18") (pin "7") (pinfunction "D_7") (pintype "passive"))
      (node (ref "Q18") (pin "8") (pinfunction "D_8") (pintype "passive"))
      (node (ref "U15") (pin "2") (pinfunction "TS_2") (pintype "passive"))
    )
    (net (code "39") (name "/SWN3") (class "Default")
      (node (ref "C92") (pin "2") (pinfunction "2_2") (pintype "passive"))
      (node (ref "L9") (pin "1") (pinfunction "1_1") (pintype "passive"))
      (node (ref "Q25") (pin "1") (pinfunction "S_1") (pintype "passive"))
      (node (ref "Q25") (pin "2") (pinfunction "S_2") (pintype "passive"))
      (node (ref "Q25") (pin "3") (pinfunction "S_3") (pintype "passive"))
      (node (ref "Q29") (pin "5") (pinfunction "D_5") (pintype "passive"))
      (node (ref "Q29") (pin "6") (pinfunction "D_6") (pintype "passive"))
      (node (ref "Q29") (pin "7") (pinfunction "D_7") (pintype "passive"))
      (node (ref "Q29") (pin "8") (pinfunction "D_8") (pintype "passive"))
      (node (ref "Q30") (pin "5") (pinfunction "D_5") (pintype "passive"))
      (node (ref "Q30") (pin "6") (pinfunction "D_6") (pintype "passive"))
      (node (ref "Q30") (pin "7") (pinfunction "D_7") (pintype "passive"))
      (node (ref "Q30") (pin "8") (pinfunction "D_8") (pintype "passive"))
      (node (ref "U19") (pin "2") (pinfunction "TS_2") (pintype "passive"))
    )
    (net (code "40") (name "/SWN4") (class "Default")
      (node (ref "C124") (pin "2") (pinfunction "2_2") (pintype "passive"))
      (node (ref "L13") (pin "1") (pinfunction "1_1") (pintype "passive"))
      (node (ref "Q37") (pin "1") (pinfunction "S_1") (pintype "passive"))
      (node (ref "Q37") (pin "2") (pinfunction "S_2") (pintype "passive"))
      (node (ref "Q37") (pin "3") (pinfunction "S_3") (pintype "passive"))
      (node (ref "Q41") (pin "5") (pinfunction "D_5") (pintype "passive"))
      (node (ref "Q41") (pin "6") (pinfunction "D_6") (pintype "passive"))
      (node (ref "Q41") (pin "7") (pinfunction "D_7") (pintype "passive"))
      (node (ref "Q41") (pin "8") (pinfunction "D_8") (pintype "passive"))
      (node (ref "Q42") (pin "5") (pinfunction "D_5") (pintype "passive"))
      (node (ref "Q42") (pin "6") (pinfunction "D_6") (pintype "passive"))
      (node (ref "Q42") (pin "7") (pinfunction "D_7") (pintype "passive"))
      (node (ref "Q42") (pin "8") (pinfunction "D_8") (pintype "passive"))
      (node (ref "U23") (pin "2") (pinfunction "TS_2") (pintype "passive"))
    )
    (net (code "41") (name "/SWN5") (class "Default")
      (node (ref "C29") (pin "2") (pinfunction "2_2") (pintype "passive"))
      (node (ref "L2") (pin "1") (pinfunction "1_1") (pintype "passive"))
      (node (ref "Q2") (pin "1") (pinfunction "S_1") (pintype "passive"))
      (node (ref "Q2") (pin "2") (pinfunction "S_2") (pintype "passive"))
      (node (ref "Q2") (pin "3") (pinfunction "S_3") (pintype "passive"))
      (node (ref "Q7") (pin "5") (pinfunction "D_5") (pintype "passive"))
      (node (ref "Q7") (pin "6") (pinfunction "D_6") (pintype "passive"))
      (node (ref "Q7") (pin "7") (pinfunction "D_7") (pintype "passive"))
      (node (ref "Q7") (pin "8") (pinfunction "D_8") (pintype "passive"))
      (node (ref "Q8") (pin "5") (pinfunction "D_5") (pintype "passive"))
      (node (ref "Q8") (pin "6") (pinfunction "D_6") (pintype "passive"))
      (node (ref "Q8") (pin "7") (pinfunction "D_7") (pintype "passive"))
      (node (ref "Q8") (pin "8") (pinfunction "D_8") (pintype "passive"))
      (node (ref "U12") (pin "2") (pinfunction "TS_2") (pintype "passive"))
    )
    (net (code "42") (name "/SWN6") (class "Default")
      (node (ref "C61") (pin "2") (pinfunction "2_2") (pintype "passive"))
      (node (ref "L6") (pin "1") (pinfunction "1_1") (pintype "passive"))
      (node (ref "Q14") (pin "1") (pinfunction "S_1") (pintype "passive"))
      (node (ref "Q14") (pin "2") (pinfunction "S_2") (pintype "passive"))
      (node (ref "Q14") (pin "3") (pinfunction "S_3") (pintype "passive"))
      (node (ref "Q19") (pin "5") (pinfunction "D_5") (pintype "passive"))
      (node (ref "Q19") (pin "6") (pinfunction "D_6") (pintype "passive"))
      (node (ref "Q19") (pin "7") (pinfunction "D_7") (pintype "passive"))
      (node (ref "Q19") (pin "8") (pinfunction "D_8") (pintype "passive"))
      (node (ref "Q20") (pin "5") (pinfunction "D_5") (pintype "passive"))
      (node (ref "Q20") (pin "6") (pinfunction "D_6") (pintype "passive"))
      (node (ref "Q20") (pin "7") (pinfunction "D_7") (pintype "passive"))
      (node (ref "Q20") (pin "8") (pinfunction "D_8") (pintype "passive"))
      (node (ref "U16") (pin "2") (pinfunction "TS_2") (pintype "passive"))
    )
    (net (code "43") (name "/SWN7") (class "Default")
      (node (ref "C93") (pin "2") (pinfunction "2_2") (pintype "passive"))
      (node (ref "L10") (pin "1") (pinfunction "1_1") (pintype "passive"))
      (node (ref "Q26") (pin "1") (pinfunction "S_1") (pintype "passive"))
      (node (ref "Q26") (pin "2") (pinfunction "S_2") (pintype "passive"))
      (node (ref "Q26") (pin "3") (pinfunction "S_3") (pintype "passive"))
      (node (ref "Q31") (pin "5") (pinfunction "D_5") (pintype "passive"))
      (node (ref "Q31") (pin "6") (pinfunction "D_6") (pintype "passive"))
      (node (ref "Q31") (pin "7") (pinfunction "D_7") (pintype "passive"))
      (node (ref "Q31") (pin "8") (pinfunction "D_8") (pintype "passive"))
      (node (ref "Q32") (pin "5") (pinfunction "D_5") (pintype "passive"))
      (node (ref "Q32") (pin "6") (pinfunction "D_6") (pintype "passive"))
      (node (ref "Q32") (pin "7") (pinfunction "D_7") (pintype "passive"))
      (node (ref "Q32") (pin "8") (pinfunction "D_8") (pintype "passive"))
      (node (ref "U20") (pin "2") (pinfunction "TS_2") (pintype "passive"))
    )
    (net (code "44") (name "/SWN8") (class "Default")
      (node (ref "C125") (pin "2") (pinfunction "2_2") (pintype "passive"))
      (node (ref "L14") (pin "1") (pinfunction "1_1") (pintype "passive"))
      (node (ref "Q38") (pin "1") (pinfunction "S_1") (pintype "passive"))
      (node (ref "Q38") (pin "2") (pinfunction "S_2") (pintype "passive"))
      (node (ref "Q38") (pin "3") (pinfunction "S_3") (pintype "passive"))
      (node (ref "Q43") (pin "5") (pinfunction "D_5") (pintype "passive"))
      (node (ref "Q43") (pin "6") (pinfunction "D_6") (pintype "passive"))
      (node (ref "Q43") (pin "7") (pinfunction "D_7") (pintype "passive"))
      (node (ref "Q43") (pin "8") (pinfunction "D_8") (pintype "passive"))
      (node (ref "Q44") (pin "5") (pinfunction "D_5") (pintype "passive"))
      (node (ref "Q44") (pin "6") (pinfunction "D_6") (pintype "passive"))
      (node (ref "Q44") (pin "7") (pinfunction "D_7") (pintype "passive"))
      (node (ref "Q44") (pin "8") (pinfunction "D_8") (pintype "passive"))
      (node (ref "U24") (pin "2") (pinfunction "TS_2") (pintype "passive"))
    )
    (net (code "45") (name "GND") (class "Default")
      (node (ref "C100") (pin "1") (pinfunction "1_1") (pintype "passive"))
      (node (ref "C1000") (pin "2") (pinfunction "2_2") (pintype "passive"))
      (node (ref "C1001") (pin "1") (pinfunction "1_1") (pintype "passive"))
      (node (ref "C1002") (pin "2") (pinfunction "2_2") (pintype "passive"))
      (node (ref "C1003") (pin "2") (pinfunction "2_2") (pintype "passive"))
      (node (ref "C1004") (pin "1") (pinfunction "1_1") (pintype "passive"))
      (node (ref "C1005") (pin "2") (pinfunction "2_2") (pintype "passive"))
      (node (ref "C1006") (pin "2") (pinfunction "2_2") (pintype "passive"))
      (node (ref "C1007") (pin "1") (pinfunction "1_1") (pintype "passive"))
      (node (ref "C1008") (pin "2") (pinfunction "2_2") (pintype "passive"))
      (node (ref "C1009") (pin "2") (pinfunction "2_2") (pintype "passive"))
      (node (ref "C101") (pin "1") (pinfunction "1_1") (pintype "passive"))
      (node (ref "C1010") (pin "1") (pinfunction "1_1") (pintype "passive"))
      (node (ref "C1011") (pin "2") (pinfunction "2_2") (pintype "passive"))
      (node (ref "C1012") (pin "2") (pinfunction "2_2") (pintype "passive"))
      (node (ref "C1013") (pin "1") (pinfunction "1_1") (pintype "passive"))
      (node (ref "C1014") (pin "2") (pinfunction "2_2") (pintype "passive"))
      (node (ref "C1015") (pin "2") (pinfunction "2_2") (pintype "passive"))
      (node (ref "C1016") (pin "1") (pinfunction "1_1") (pintype "passive"))
      (node (ref "C1017") (pin "2") (pinfunction "2_2") (pintype "passive"))
      (node (ref "C1018") (pin "2") (pinfunction "2_2") (pintype "passive"))
      (node (ref "C1019") (pin "1") (pinfunction "1_1") (pintype "passive"))
      (node (ref "C102") (pin "1") (pinfunction "1_1") (pintype "passive"))
      (node (ref "C1020") (pin "2") (pinfunction "2_2") (pintype "passive"))
      (node (ref "C1021") (pin "2") (pinfunction "2_2") (pintype "passive"))
      (node (ref "C1022") (pin "1") (pinfunction "1_1") (pintype "passive"))
      (node (ref "C1023") (pin "2") (pinfunction "2_2") (pintype "passive"))
      (node (ref "C1024") (pin "2") (pinfunction "2_2") (pintype "passive"))
      (node (ref "C1025") (pin "1") (pinfunction "1_1") (pintype "passive"))
      (node (ref "C1026") (pin "2") (pinfunction "2_2") (pintype "passive"))
      (node (ref "C1027") (pin "2") (pinfunction "2_2") (pintype "passive"))
      (node (ref "C1028") (pin "1") (pinfunction "1_1") (pintype "passive"))
      (node (ref "C1029") (pin "2") (pinfunction "2_2") (pintype "passive"))
      (node (ref "C103") (pin "1") (pinfunction "1_1") (pintype "passive"))
      (node (ref "C1030") (pin "2") (pinfunction "2_2") (pintype "passive"))
      (node (ref "C1031") (pin "1") (pinfunction "1_1") (pintype "passive"))
      (node (ref "C1032") (pin "2") (pinfunction "2_2") (pintype "passive"))
      (node (ref "C1033") (pin "2") (pinfunction "2_2") (pintype "passive"))
      (node (ref "C1034") (pin "1") (pinfunction "1_1") (pintype "passive"))
      (node (ref "C1035") (pin "2") (pinfunction "2_2") (pintype "passive"))
      (node (ref "C1036") (pin "2") (pinfunction "2_2") (pintype "passive"))
      (node (ref "C1037") (pin "1") (pinfunction "1_1") (pintype "passive"))
      (node (ref "C1038") (pin "2") (pinfunction "2_2") (pintype "passive"))
      (node (ref "C1039") (pin "2") (pinfunction "2_2") (pintype "passive"))
      (node (ref "C104") (pin "1") (pinfunction "1_1") (pintype "passive"))
      (node (ref "C1040") (pin "1") (pinfunction "1_1") (pintype "passive"))
      (node (ref "C1041") (pin "2") (pinfunction "2_2") (pintype "passive"))
      (node (ref "C1042") (pin "2") (pinfunction "2_2") (pintype "passive"))
      (node (ref "C1043") (pin "1") (pinfunction "1_1") (pintype "passive"))
      (node (ref "C1044") (pin "2") (pinfunction "2_2") (pintype "passive"))
      (node (ref "C1045") (pin "2") (pinfunction "2_2") (pintype "passive"))
      (node (ref "C1046") (pin "1") (pinfunction "1_1") (pintype "passive"))
      (node (ref "C1047") (pin "2") (pinfunction "2_2") (pintype "passive"))
      (node (ref "C1048") (pin "2") (pinfunction "2_2") (pintype "passive"))
      (node (ref "C1049") (pin "1") (pinfunction "1_1") (pintype "passive"))
      (node (ref "C105") (pin "1") (pinfunction "1_1") (pintype "passive"))
      (node (ref "C1050") (pin "2") (pinfunction "2_2") (pintype "passive"))
      (node (ref "C1051") (pin "2") (pinfunction "2_2") (pintype "passive"))
      (node (ref "C1052") (pin "1") (pinfunction "1_1") (pintype "passive"))
      (node (ref "C1053") (pin "2") (pinfunction "2_2") (pintype "passive"))
      (node (ref "C1054") (pin "2") (pinfunction "2_2") (pintype "passive"))
      (node (ref "C1055") (pin "1") (pinfunction "1_1") (pintype "passive"))
      (node (ref "C1056") (pin "2") (pinfunction "2_2") (pintype "passive"))
      (node (ref "C1057") (pin "2") (pinfunction "2_2") (pintype "passive"))
      (node (ref "C1058") (pin "1") (pinfunction "1_1") (pintype "passive"))
      (node (ref "C1059") (pin "2") (pinfunction "2_2") (pintype "passive"))
      (node (ref "C1060") (pin "2") (pinfunction "2_2") (pintype "passive"))
      (node (ref "C1061") (pin "1") (pinfunction "1_1") (pintype "passive"))
      (node (ref "C1062") (pin "2") (pinfunction "2_2") (pintype "passive"))
      (node (ref "C1063") (pin "2") (pinfunction "2_2") (pintype "passive"))
      (node (ref "C1064") (pin "1") (pinfunction "1_1") (pintype "passive"))
      (node (ref "C1065") (pin "2") (pinfunction "2_2") (pintype "passive"))
      (node (ref "C1066") (pin "2") (pinfunction "2_2") (pintype "passive"))
      (node (ref "C1067") (pin "1") (pinfunction "1_1") (pintype "passive"))
      (node (ref "C1068") (pin "2") (pinfunction "2_2") (pintype "passive"))
      (node (ref "C1069") (pin "2") (pinfunction "2_2") (pintype "passive"))
      (node (ref "C1070") (pin "1") (pinfunction "1_1") (pintype "passive"))
      (node (ref "C1071") (pin "2") (pinfunction "2_2") (pintype "passive"))
      (node (ref "C116") (pin "1") (pinfunction "1_1") (pintype "passive"))
      (node (ref "C117") (pin "1") (pinfunction "1_1") (pintype "passive"))
      (node (ref "C120") (pin "2") (pinfunction "2_2") (pintype "passive"))
      (node (ref "C121") (pin "2") (pinfunction "2_2") (pintype "passive"))
      (node (ref "C128") (pin "1") (pinfunction "1_1") (pintype "passive"))
      (node (ref "C129") (pin "1") (pinfunction "1_1") (pintype "passive"))
      (node (ref "C130") (pin "1") (pinfunction "1_1") (pintype "passive"))
      (node (ref "C131") (pin "1") (pinfunction "1_1") (pintype "passive"))
      (node (ref "C132") (pin "1") (pinfunction "1_1") (pintype "passive"))
      (node (ref "C133") (pin "1") (pinfunction "1_1") (pintype "passive"))
      (node (ref "C134") (pin "1") (pinfunction "1_1") (pintype "passive"))
      (node (ref "C135") (pin "1") (pinfunction "1_1") (pintype "passive"))
      (node (ref "C136") (pin "1") (pinfunction "1_1") (pintype "passive"))
      (node (ref "C137") (pin "1") (pinfunction "1_1") (pintype "passive"))
      (node (ref "C20") (pin "1") (pinfunction "1_1") (pintype "passive"))
      (node (ref "C21") (pin "1") (pinfunction "1_1") (pintype "passive"))
      (node (ref "C236") (pin "1") (pinfunction "1_1") (pintype "passive"))
      (node (ref "C24") (pin "2") (pinfunction "2_2") (pintype "passive"))
      (node (ref "C25") (pin "2") (pinfunction "2_2") (pintype "passive"))
      (node (ref "C32") (pin "1") (pinfunction "1_1") (pintype "passive"))
      (node (ref "C323") (pin "2") (pinfunction "2_2") (pintype "passive"))
      (node (ref "C324") (pin "2") (pinfunction "2_2") (pintype "passive"))
      (node (ref "C325") (pin "2") (pinfunction "2_2") (pintype "passive"))
      (node (ref "C326") (pin "2") (pinfunction "2_2") (pintype "passive"))
      (node (ref "C327") (pin "2") (pinfunction "2_2") (pintype "passive"))
      (node (ref "C328") (pin "2") (pinfunction "2_2") (pintype "passive"))
      (node (ref "C329") (pin "2") (pinfunction "2_2") (pintype "passive"))
      (node (ref "C33") (pin "1") (pinfunction "1_1") (pintype "passive"))
      (node (ref "C330") (pin "2") (pinfunction "2_2") (pintype "passive"))
      (node (ref "C331") (pin "2") (pinfunction "2_2") (pintype "passive"))
      (node (ref "C332") (pin "2") (pinfunction "2_2") (pintype "passive"))
      (node (ref "C333") (pin "2") (pinfunction "2_2") (pintype "passive"))
      (node (ref "C334") (pin "2") (pinfunction "2_2") (pintype "passive"))
      (node (ref "C335") (pin "2") (pinfunction "2_2") (pintype "passive"))
      (node (ref "C336") (pin "2") (pinfunction "2_2") (pintype "passive"))
      (node (ref "C337") (pin "2") (pinfunction "2_2") (pintype "passive"))
      (node (ref "C338") (pin "2") (pinfunction "2_2") (pintype "passive"))
      (node (ref "C339") (pin "2") (pinfunction "2_2") (pintype "passive"))
      (node (ref "C34") (pin "1") (pinfunction "1_1") (pintype "passive"))
      (node (ref "C340") (pin "2") (pinfunction "2_2") (pintype "passive"))
      (node (ref "C341") (pin "2") (pinfunction "2_2") (pintype "passive"))
      (node (ref "C342") (pin "2") (pinfunction "2_2") (pintype "passive"))
      (node (ref "C343") (pin "2") (pinfunction "2_2") (pintype "passive"))
      (node (ref "C344") (pin "2") (pinfunction "2_2") (pintype "passive"))
      (node (ref "C345") (pin "2") (pinfunction "2_2") (pintype "passive"))
      (node (ref "C346") (pin "2") (pinfunction "2_2") (pintype "passive"))
      (node (ref "C348") (pin "1") (pinfunction "1_1") (pintype "passive"))
      (node (ref "C349") (pin "1") (pinfunction "1_1") (pintype "passive"))
      (node (ref "C35") (pin "1") (pinfunction "1_1") (pintype "passive"))
      (node (ref "C350") (pin "1") (pinfunction "1_1") (pintype "passive"))
      (node (ref "C351") (pin "1") (pinfunction "1_1") (pintype "passive"))
      (node (ref "C352") (pin "1") (pinfunction "1_1") (pintype "passive"))
      (node (ref "C353") (pin "2") (pinfunction "2_2") (pintype "passive"))
      (node (ref "C354") (pin "2") (pinfunction "2_2") (pintype "passive"))
      (node (ref "C355") (pin "2") (pinfunction "2_2") (pintype "passive"))
      (node (ref "C356") (pin "2") (pinfunction "2_2") (pintype "passive"))
      (node (ref "C357") (pin "2") (pinfunction "2_2") (pintype "passive"))
      (node (ref "C358") (pin "2") (pinfunction "2_2") (pintype "passive"))
      (node (ref "C359") (pin "2") (pinfunction "2_2") (pintype "passive"))
      (node (ref "C360") (pin "2") (pinfunction "2_2") (pintype "passive"))
      (node (ref "C361") (pin "2") (pinfunction "2_2") (pintype "passive"))
      (node (ref "C362") (pin "2") (pinfunction "2_2") (pintype "passive"))
      (node (ref "C363") (pin "2") (pinfunction "2_2") (pintype "passive"))
      (node (ref "C364") (pin "2") (pinfunction "2_2") (pintype "passive"))
      (node (ref "C365") (pin "2") (pinfunction "2_2") (pintype "passive"))
      (node (ref "C366") (pin "2") (pinfunction "2_2") (pintype "passive"))
      (node (ref "C367") (pin "2") (pinfunction "2_2") (pintype "passive"))
      (node (ref "C368") (pin "2") (pinfunction "2_2") (pintype "passive"))
      (node (ref "C369") (pin "2") (pinfunction "2_2") (pintype "passive"))
      (node (ref "C37") (pin "1") (pinfunction "1_1") (pintype "passive"))
      (node (ref "C370") (pin "2") (pinfunction "2_2") (pintype "passive"))
      (node (ref "C371") (pin "2") (pinfunction "2_2") (pintype "passive"))
      (node (ref "C372") (pin "2") (pinfunction "2_2") (pintype "passive"))
      (node (ref "C373") (pin "2") (pinfunction "2_2") (pintype "passive"))
      (node (ref "C374") (pin "2") (pinfunction "2_2") (pintype "passive"))
      (node (ref "C375") (pin "2") (pinfunction "2_2") (pintype "passive"))
      (node (ref "C376") (pin "2") (pinfunction "2_2") (pintype "passive"))
      (node (ref "C377") (pin "2") (pinfunction "2_2") (pintype "passive"))
      (node (ref "C378") (pin "2") (pinfunction "2_2") (pintype "passive"))
      (node (ref "C379") (pin "2") (pinfunction "2_2") (pintype "passive"))
      (node (ref "C38") (pin "1") (pinfunction "1_1") (pintype "passive"))
      (node (ref "C380") (pin "2") (pinfunction "2_2") (pintype "passive"))
      (node (ref "C381") (pin "2") (pinfunction "2_2") (pintype "passive"))
      (node (ref "C382") (pin "2") (pinfunction "2_2") (pintype "passive"))
      (node (ref "C383") (pin "2") (pinfunction "2_2") (pintype "passive"))
      (node (ref "C384") (pin "2") (pinfunction "2_2") (pintype "passive"))
      (node (ref "C385") (pin "2") (pinfunction "2_2") (pintype "passive"))
      (node (ref "C386") (pin "2") (pinfunction "2_2") (pintype "passive"))
      (node (ref "C387") (pin "2") (pinfunction "2_2") (pintype "passive"))
      (node (ref "C388") (pin "2") (pinfunction "2_2") (pintype "passive"))
      (node (ref "C389") (pin "2") (pinfunction "2_2") (pintype "passive"))
      (node (ref "C39") (pin "1") (pinfunction "1_1") (pintype "passive"))
      (node (ref "C390") (pin "2") (pinfunction "2_2") (pintype "passive"))
      (node (ref "C391") (pin "2") (pinfunction "2_2") (pintype "passive"))
      (node (ref "C392") (pin "2") (pinfunction "2_2") (pintype "passive"))
      (node (ref "C393") (pin "1") (pinfunction "1_1") (pintype "passive"))
      (node (ref "C394") (pin "1") (pinfunction "1_1") (pintype "passive"))
      (node (ref "C395") (pin "1") (pinfunction "1_1") (pintype "passive"))
      (node (ref "C396") (pin "1") (pinfunction "1_1") (pintype "passive"))
      (node (ref "C397") (pin "1") (pinfunction "1_1") (pintype "passive"))
      (node (ref "C398") (pin "1") (pinfunction "1_1") (pintype "passive"))
      (node (ref "C399") (pin "1") (pinfunction "1_1") (pintype "passive"))
      (node (ref "C40") (pin "1") (pinfunction "1_1") (pintype "passive"))
      (node (ref "C400") (pin "1") (pinfunction "1_1") (pintype "passive"))
      (node (ref "C401") (pin "1") (pinfunction "1_1") (pintype "passive"))
      (node (ref "C402") (pin "1") (pinfunction "1_1") (pintype "passive"))
      (node (ref "C403") (pin "1") (pinfunction "1_1") (pintype "passive"))
      (node (ref "C404") (pin "1") (pinfunction "1_1") (pintype "passive"))
      (node (ref "C405") (pin "1") (pinfunction "1_1") (pintype "passive"))
      (node (ref "C406") (pin "1") (pinfunction "1_1") (pintype "passive"))
      (node (ref "C407") (pin "1") (pinfunction "1_1") (pintype "passive"))
      (node (ref "C408") (pin "1") (pinfunction "1_1") (pintype "passive"))
      (node (ref "C409") (pin "1") (pinfunction "1_1") (pintype "passive"))
      (node (ref "C41") (pin "1") (pinfunction "1_1") (pintype "passive"))
      (node (ref "C410") (pin "1") (pinfunction "1_1") (pintype "passive"))
      (node (ref "C411") (pin "1") (pinfunction "1_1") (pintype "passive"))
      (node (ref "C412") (pin "1") (pinfunction "1_1") (pintype "passive"))
      (node (ref "C413") (pin "1") (pinfunction "1_1") (pintype "passive"))
      (node (ref "C414") (pin "1") (pinfunction "1_1") (pintype "passive"))
      (node (ref "C415") (pin "1") (pinfunction "1_1") (pintype "passive"))
      (node (ref "C416") (pin "1") (pinfunction "1_1") (pintype "passive"))
      (node (ref "C417") (pin "1") (pinfunction "1_1") (pintype "passive"))
      (node (ref "C418") (pin "1") (pinfunction "1_1") (pintype "passive"))
      (node (ref "C419") (pin "1") (pinfunction "1_1") (pintype "passive"))
      (node (ref "C420") (pin "1") (pinfunction "1_1") (pintype "passive"))
      (node (ref "C421") (pin "1") (pinfunction "1_1") (pintype "passive"))
      (node (ref "C422") (pin "1") (pinfunction "1_1") (pintype "passive"))
      (node (ref "C423") (pin "1") (pinfunction "1_1") (pintype "passive"))
      (node (ref "C424") (pin "1") (pinfunction "1_1") (pintype "passive"))
      (node (ref "C425") (pin "1") (pinfunction "1_1") (pintype "passive"))
      (node (ref "C426") (pin "1") (pinfunction "1_1") (pintype "passive"))
      (node (ref "C427") (pin "1") (pinfunction "1_1") (pintype "passive"))
      (node (ref "C428") (pin "2") (pinfunction "2_2") (pintype "passive"))
      (node (ref "C429") (pin "2") (pinfunction "2_2") (pintype "passive"))
      (node (ref "C430") (pin "2") (pinfunction "2_2") (pintype "passive"))
      (node (ref "C431") (pin "2") (pinfunction "2_2") (pintype "passive"))
      (node (ref "C432") (pin "2") (pinfunction "2_2") (pintype "passive"))
      (node (ref "C433") (pin "2") (pinfunction "2_2") (pintype "passive"))
      (node (ref "C434") (pin "2") (pinfunction "2_2") (pintype "passive"))
      (node (ref "C435") (pin "2") (pinfunction "2_2") (pintype "passive"))
      (node (ref "C436") (pin "2") (pinfunction "2_2") (pintype "passive"))
      (node (ref "C437") (pin "2") (pinfunction "2_2") (pintype "passive"))
      (node (ref "C438") (pin "2") (pinfunction "2_2") (pintype "passive"))
      (node (ref "C439") (pin "2") (pinfunction "2_2") (pintype "passive"))
      (node (ref "C440") (pin "2") (pinfunction "2_2") (pintype "passive"))
      (node (ref "C441") (pin "2") (pinfunction "2_2") (pintype "passive"))
      (node (ref "C442") (pin "2") (pinfunction "2_2") (pintype "passive"))
      (node (ref "C443") (pin "2") (pinfunction "2_2") (pintype "passive"))
      (node (ref "C444") (pin "2") (pinfunction "2_2") (pintype "passive"))
      (node (ref "C445") (pin "2") (pinfunction "2_2") (pintype "passive"))
      (node (ref "C446") (pin "2") (pinfunction "2_2") (pintype "passive"))
      (node (ref "C447") (pin "2") (pinfunction "2_2") (pintype "passive"))
      (node (ref "C448") (pin "2") (pinfunction "2_2") (pintype "passive"))
      (node (ref "C449") (pin "2") (pinfunction "2_2") (pintype "passive"))
      (node (ref "C450") (pin "2") (pinfunction "2_2") (pintype "passive"))
      (node (ref "C451") (pin "2") (pinfunction "2_2") (pintype "passive"))
      (node (ref "C452") (pin "2") (pinfunction "2_2") (pintype "passive"))
      (node (ref "C453") (pin "2") (pinfunction "2_2") (pintype "passive"))
      (node (ref "C454") (pin "2") (pinfunction "2_2") (pintype "passive"))
      (node (ref "C455") (pin "2") (pinfunction "2_2") (pintype "passive"))
      (node (ref "C456") (pin "2") (pinfunction "2_2") (pintype "passive"))
      (node (ref "C457") (pin "2") (pinfunction "2_2") (pintype "passive"))
      (node (ref "C458") (pin "2") (pinfunction "2_2") (pintype "passive"))
      (node (ref "C459") (pin "2") (pinfunction "2_2") (pintype "passive"))
      (node (ref "C460") (pin "2") (pinfunction "2_2") (pintype "passive"))
      (node (ref "C461") (pin "2") (pinfunction "2_2") (pintype "passive"))
      (node (ref "C462") (pin "2") (pinfunction "2_2") (pintype "passive"))
      (node (ref "C463") (pin "2") (pinfunction "2_2") (pintype "passive"))
      (node (ref "C464") (pin "2") (pinfunction "2_2") (pintype "passive"))
      (node (ref "C465") (pin "2") (pinfunction "2_2") (pintype "passive"))
      (node (ref "C466") (pin "2") (pinfunction "2_2") (pintype "passive"))
      (node (ref "C467") (pin "2") (pinfunction "2_2") (pintype "passive"))
      (node (ref "C468") (pin "2") (pinfunction "2_2") (pintype "passive"))
      (node (ref "C469") (pin "2") (pinfunction "2_2") (pintype "passive"))
      (node (ref "C470") (pin "2") (pinfunction "2_2") (pintype "passive"))
      (node (ref "C471") (pin "2") (pinfunction "2_2") (pintype "passive"))
      (node (ref "C472") (pin "2") (pinfunction "2_2") (pintype "passive"))
      (node (ref "C473") (pin "2") (pinfunction "2_2") (pintype "passive"))
      (node (ref "C474") (pin "2") (pinfunction "2_2") (pintype "passive"))
      (node (ref "C475") (pin "2") (pinfunction "2_2") (pintype "passive"))
      (node (ref "C476") (pin "2") (pinfunction "2_2") (pintype "passive"))
      (node (ref "C477") (pin "2") (pinfunction "2_2") (pintype "passive"))
      (node (ref "C478") (pin "2") (pinfunction "2_2") (pintype "passive"))
      (node (ref "C479") (pin "2") (pinfunction "2_2") (pintype "passive"))
      (node (ref "C480") (pin "2") (pinfunction "2_2") (pintype "passive"))
      (node (ref "C481") (pin "2") (pinfunction "2_2") (pintype "passive"))
      (node (ref "C482") (pin "2") (pinfunction "2_2") (pintype "passive"))
      (node (ref "C483") (pin "2") (pinfunction "2_2") (pintype "passive"))
      (node (ref "C484") (pin "2") (pinfunction "2_2") (pintype "passive"))
      (node (ref "C485") (pin "2") (pinfunction "2_2") (pintype "passive"))
      (node (ref "C486") (pin "2") (pinfunction "2_2") (pintype "passive"))
      (node (ref "C487") (pin "2") (pinfunction "2_2") (pintype "passive"))
      (node (ref "C488") (pin "2") (pinfunction "2_2") (pintype "passive"))
      (node (ref "C489") (pin "2") (pinfunction "2_2") (pintype "passive"))
      (node (ref "C490") (pin "2") (pinfunction "2_2") (pintype "passive"))
      (node (ref "C491") (pin "2") (pinfunction "2_2") (pintype "passive"))
      (node (ref "C52") (pin "1") (pinfunction "1_1") (pintype "passive"))
      (node (ref "C53") (pin "1") (pinfunction "1_1") (pintype "passive"))
      (node (ref "C56") (pin "2") (pinfunction "2_2") (pintype "passive"))
      (node (ref "C57") (pin "2") (pinfunction "2_2") (pintype "passive"))
      (node (ref "C593") (pin "1") (pinfunction "1_1") (pintype "passive"))
      (node (ref "C596") (pin "1") (pinfunction "1_1") (pintype "passive"))
      (node (ref "C598") (pin "2") (pinfunction "2_2") (pintype "passive"))
      (node (ref "C599") (pin "1") (pinfunction "1_1") (pintype "passive"))
      (node (ref "C600") (pin "2") (pinfunction "2_2") (pintype "passive"))
      (node (ref "C602") (pin "1") (pinfunction "1_1") (pintype "passive"))
      (node (ref "C603") (pin "2") (pinfunction "2_2") (pintype "passive"))
      (node (ref "C605") (pin "1") (pinfunction "1_1") (pintype "passive"))
      (node (ref "C606") (pin "2") (pinfunction "2_2") (pintype "passive"))
      (node (ref "C64") (pin "1") (pinfunction "1_1") (pintype "passive"))
      (node (ref "C640") (pin "2") (pinfunction "2_2") (pintype "passive"))
      (node (ref "C642") (pin "2") (pinfunction "2_2") (pintype "passive"))
      (node (ref "C643") (pin "2") (pinfunction "2_2") (pintype "passive"))
      (node (ref "C645") (pin "2") (pinfunction "2_2") (pintype "passive"))
      (node (ref "C646") (pin "2") (pinfunction "2_2") (pintype "passive"))
      (node (ref "C65") (pin "1") (pinfunction "1_1") (pintype "passive"))
      (node (ref "C652") (pin "2") (pinfunction "2_2") (pintype "passive"))
      (node (ref "C653") (pin "1") (pinfunction "1_1") (pintype "passive"))
      (node (ref "C654") (pin "2") (pinfunction "2_2") (pintype "passive"))
      (node (ref "C655") (pin "2") (pinfunction "2_2") (pintype "passive"))
      (node (ref "C656") (pin "1") (pinfunction "1_1") (pintype "passive"))
      (node (ref "C657") (pin "2") (pinfunction "2_2") (pintype "passive"))
      (node (ref "C658") (pin "2") (pinfunction "2_2") (pintype "passive"))
      (node (ref "C659") (pin "1") (pinfunction "1_1") (pintype "passive"))
      (node (ref "C66") (pin "1") (pinfunction "1_1") (pintype "passive"))
      (node (ref "C660") (pin "2") (pinfunction "2_2") (pintype "passive"))
      (node (ref "C661") (pin "2") (pinfunction "2_2") (pintype "passive"))
      (node (ref "C662") (pin "1") (pinfunction "1_1") (pintype "passive"))
      (node (ref "C663") (pin "2") (pinfunction "2_2") (pintype "passive"))
      (node (ref "C664") (pin "2") (pinfunction "2_2") (pintype "passive"))
      (node (ref "C665") (pin "1") (pinfunction "1_1") (pintype "passive"))
      (node (ref "C666") (pin "2") (pinfunction "2_2") (pintype "passive"))
      (node (ref "C667") (pin "2") (pinfunction "2_2") (pintype "passive"))
      (node (ref "C668") (pin "1") (pinfunction "1_1") (pintype "passive"))
      (node (ref "C669") (pin "2") (pinfunction "2_2") (pintype "passive"))
      (node (ref "C67") (pin "1") (pinfunction "1_1") (pintype "passive"))
      (node (ref "C670") (pin "2") (pinfunction "2_2") (pintype "passive"))
      (node (ref "C671") (pin "1") (pinfunction "1_1") (pintype "passive"))
      (node (ref "C672") (pin "2") (pinfunction "2_2") (pintype "passive"))
      (node (ref "C673") (pin "2") (pinfunction "2_2") (pintype "passive"))
      (node (ref "C674") (pin "1") (pinfunction "1_1") (pintype "passive"))
      (node (ref "C675") (pin "2") (pinfunction "2_2") (pintype "passive"))
      (node (ref "C676") (pin "2") (pinfunction "2_2") (pintype "passive"))
      (node (ref "C677") (pin "1") (pinfunction "1_1") (pintype "passive"))
      (node (ref "C678") (pin "2") (pinfunction "2_2") (pintype "passive"))
      (node (ref "C679") (pin "2") (pinfunction "2_2") (pintype "passive"))
      (node (ref "C68") (pin "1") (pinfunction "1_1") (pintype "passive"))
      (node (ref "C680") (pin "1") (pinfunction "1_1") (pintype "passive"))
      (node (ref "C681") (pin "2") (pinfunction "2_2") (pintype "passive"))
      (node (ref "C686") (pin "1") (pinfunction "1_1") (pintype "passive"))
      (node (ref "C688") (pin "2") (pinfunction "2_2") (pintype "passive"))
      (node (ref "C689") (pin "1") (pinfunction "1_1") (pintype "passive"))
      (node (ref "C69") (pin "1") (pinfunction "1_1") (pintype "passive"))
      (node (ref "C692") (pin "1") (pinfunction "1_1") (pintype "passive"))
      (node (ref "C695") (pin "1") (pinfunction "1_1") (pintype "passive"))
      (node (ref "C70") (pin "1") (pinfunction "1_1") (pintype "passive"))
      (node (ref "C71") (pin "1") (pinfunction "1_1") (pintype "passive"))
      (node (ref "C711") (pin "2") (pinfunction "2_2") (pintype "passive"))
      (node (ref "C712") (pin "2") (pinfunction "2_2") (pintype "passive"))
      (node (ref "C714") (pin "2") (pinfunction "2_2") (pintype "passive"))
      (node (ref "C715") (pin "2") (pinfunction "2_2") (pintype "passive"))
      (node (ref "C717") (pin "2") (pinfunction "2_2") (pintype "passive"))
      (node (ref "C72") (pin "1") (pinfunction "1_1") (pintype "passive"))
      (node (ref "C73") (pin "1") (pinfunction "1_1") (pintype "passive"))
      (node (ref "C742") (pin "2") (pinfunction "2_2") (pintype "passive"))
      (node (ref "C743") (pin "1") (pinfunction "1_1") (pintype "passive"))
      (node (ref "C744") (pin "2") (pinfunction "2_2") (pintype "passive"))
      (node (ref "C745") (pin "2") (pinfunction "2_2") (pintype "passive"))
      (node (ref "C746") (pin "1") (pinfunction "1_1") (pintype "passive"))
      (node (ref "C747") (pin "2") (pinfunction "2_2") (pintype "passive"))
      (node (ref "C748") (pin "2") (pinfunction "2_2") (pintype "passive"))
      (node (ref "C749") (pin "1") (pinfunction "1_1") (pintype "passive"))
      (node (ref "C750") (pin "2") (pinfunction "2_2") (pintype "passive"))
      (node (ref "C751") (pin "2") (pinfunction "2_2") (pintype "passive"))
      (node (ref "C752") (pin "1") (pinfunction "1_1") (pintype "passive"))
      (node (ref "C753") (pin "2") (pinfunction "2_2") (pintype "passive"))
      (node (ref "C754") (pin "2") (pinfunction "2_2") (pintype "passive"))
      (node (ref "C755") (pin "1") (pinfunction "1_1") (pintype "passive"))
      (node (ref "C756") (pin "2") (pinfunction "2_2") (pintype "passive"))
      (node (ref "C757") (pin "2") (pinfunction "2_2") (pintype "passive"))
      (node (ref "C758") (pin "1") (pinfunction "1_1") (pintype "passive"))
      (node (ref "C759") (pin "2") (pinfunction "2_2") (pintype "passive"))
      (node (ref "C760") (pin "2") (pinfunction "2_2") (pintype "passive"))
      (node (ref "C761") (pin "1") (pinfunction "1_1") (pintype "passive"))
      (node (ref "C762") (pin "2") (pinfunction "2_2") (pintype "passive"))
      (node (ref "C763") (pin "2") (pinfunction "2_2") (pintype "passive"))
      (node (ref "C764") (pin "1") (pinfunction "1_1") (pintype "passive"))
      (node (ref "C765") (pin "2") (pinfunction "2_2") (pintype "passive"))
      (node (ref "C766") (pin "2") (pinfunction "2_2") (pintype "passive"))
      (node (ref "C767") (pin "1") (pinfunction "1_1") (pintype "passive"))
      (node (ref "C768") (pin "2") (pinfunction "2_2") (pintype "passive"))
      (node (ref "C769") (pin "2") (pinfunction "2_2") (pintype "passive"))
      (node (ref "C770") (pin "1") (pinfunction "1_1") (pintype "passive"))
      (node (ref "C771") (pin "2") (pinfunction "2_2") (pintype "passive"))
      (node (ref "C776") (pin "1") (pinfunction "1_1") (pintype "passive"))
      (node (ref "C779") (pin "1") (pinfunction "1_1") (pintype "passive"))
      (node (ref "C782") (pin "1") (pinfunction "1_1") (pintype "passive"))
      (node (ref "C785") (pin "1") (pinfunction "1_1") (pintype "passive"))
      (node (ref "C807") (pin "2") (pinfunction "2_2") (pintype "passive"))
      (node (ref "C808") (pin "2") (pinfunction "2_2") (pintype "passive"))
      (node (ref "C810") (pin "2") (pinfunction "2_2") (pintype "passive"))
      (node (ref "C811") (pin "2") (pinfunction "2_2") (pintype "passive"))
      (node (ref "C813") (pin "2") (pinfunction "2_2") (pintype "passive"))
      (node (ref "C814") (pin "2") (pinfunction "2_2") (pintype "passive"))
      (node (ref "C832") (pin "2") (pinfunction "2_2") (pintype "passive"))
      (node (ref "C833") (pin "1") (pinfunction "1_1") (pintype "passive"))
      (node (ref "C834") (pin "2") (pinfunction "2_2") (pintype "passive"))
      (node (ref "C835") (pin "2") (pinfunction "2_2") (pintype "passive"))
      (node (ref "C836") (pin "1") (pinfunction "1_1") (pintype "passive"))
      (node (ref "C837") (pin "2") (pinfunction "2_2") (pintype "passive"))
      (node (ref "C838") (pin "2") (pinfunction "2_2") (pintype "passive"))
      (node (ref "C839") (pin "1") (pinfunction "1_1") (pintype "passive"))
      (node (ref "C84") (pin "1") (pinfunction "1_1") (pintype "passive"))
      (node (ref "C840") (pin "2") (pinfunction "2_2") (pintype "passive"))
      (node (ref "C841") (pin "2") (pinfunction "2_2") (pintype "passive"))
      (node (ref "C842") (pin "1") (pinfunction "1_1") (pintype "passive"))
      (node (ref "C843") (pin "2") (pinfunction "2_2") (pintype "passive"))
      (node (ref "C844") (pin "2") (pinfunction "2_2") (pintype "passive"))
      (node (ref "C845") (pin "1") (pinfunction "1_1") (pintype "passive"))
      (node (ref "C846") (pin "2") (pinfunction "2_2") (pintype "passive"))
      (node (ref "C847") (pin "2") (pinfunction "2_2") (pintype "passive"))
      (node (ref "C848") (pin "1") (pinfunction "1_1") (pintype "passive"))
      (node (ref "C849") (pin "2") (pinfunction "2_2") (pintype "passive"))
      (node (ref "C85") (pin "1") (pinfunction "1_1") (pintype "passive"))
      (node (ref "C850") (pin "2") (pinfunction "2_2") (pintype "passive"))
      (node (ref "C851") (pin "1") (pinfunction "1_1") (pintype "passive"))
      (node (ref "C852") (pin "2") (pinfunction "2_2") (pintype "passive"))
      (node (ref "C853") (pin "2") (pinfunction "2_2") (pintype "passive"))
      (node (ref "C854") (pin "1") (pinfunction "1_1") (pintype "passive"))
      (node (ref "C855") (pin "2") (pinfunction "2_2") (pintype "passive"))
      (node (ref "C856") (pin "2") (pinfunction "2_2") (pintype "passive"))
      (node (ref "C857") (pin "1") (pinfunction "1_1") (pintype "passive"))
      (node (ref "C858") (pin "2") (pinfunction "2_2") (pintype "passive"))
      (node (ref "C859") (pin "2") (pinfunction "2_2") (pintype "passive"))
      (node (ref "C860") (pin "1") (pinfunction "1_1") (pintype "passive"))
      (node (ref "C861") (pin "2") (pinfunction "2_2") (pintype "passive"))
      (node (ref "C866") (pin "1") (pinfunction "1_1") (pintype "passive"))
      (node (ref "C868") (pin "2") (pinfunction "2_2") (pintype "passive"))
      (node (ref "C869") (pin "1") (pinfunction "1_1") (pintype "passive"))
      (node (ref "C872") (pin "1") (pinfunction "1_1") (pintype "passive"))
      (node (ref "C876") (pin "2") (pinfunction "2_2") (pintype "passive"))
      (node (ref "C877") (pin "2") (pinfunction "2_2") (pintype "passive"))
      (node (ref "C879") (pin "2") (pinfunction "2_2") (pintype "passive"))
      (node (ref "C88") (pin "2") (pinfunction "2_2") (pintype "passive"))
      (node (ref "C880") (pin "2") (pinfunction "2_2") (pintype "passive"))
      (node (ref "C882") (pin "2") (pinfunction "2_2") (pintype "passive"))
      (node (ref "C89") (pin "2") (pinfunction "2_2") (pintype "passive"))
      (node (ref "C913") (pin "2") (pinfunction "2_2") (pintype "passive"))
      (node (ref "C915") (pin "2") (pinfunction "2_2") (pintype "passive"))
      (node (ref "C916") (pin "2") (pinfunction "2_2") (pintype "passive"))
      (node (ref "C918") (pin "2") (pinfunction "2_2") (pintype "passive"))
      (node (ref "C919") (pin "2") (pinfunction "2_2") (pintype "passive"))
      (node (ref "C922") (pin "2") (pinfunction "2_2") (pintype "passive"))
      (node (ref "C923") (pin "1") (pinfunction "1_1") (pintype "passive"))
      (node (ref "C924") (pin "2") (pinfunction "2_2") (pintype "passive"))
      (node (ref "C925") (pin "2") (pinfunction "2_2") (pintype "passive"))
      (node (ref "C926") (pin "1") (pinfunction "1_1") (pintype "passive"))
      (node (ref "C927") (pin "2") (pinfunction "2_2") (pintype "passive"))
      (node (ref "C928") (pin "2") (pinfunction "2_2") (pintype "passive"))
      (node (ref "C929") (pin "1") (pinfunction "1_1") (pintype "passive"))
      (node (ref "C930") (pin "2") (pinfunction "2_2") (pintype "passive"))
      (node (ref "C931") (pin "2") (pinfunction "2_2") (pintype "passive"))
      (node (ref "C932") (pin "1") (pinfunction "1_1") (pintype "passive"))
      (node (ref "C933") (pin "2") (pinfunction "2_2") (pintype "passive"))
      (node (ref "C934") (pin "2") (pinfunction "2_2") (pintype "passive"))
      (node (ref "C935") (pin "1") (pinfunction "1_1") (pintype "passive"))
      (node (ref "C936") (pin "2") (pinfunction "2_2") (pintype "passive"))
      (node (ref "C937") (pin "2") (pinfunction "2_2") (pintype "passive"))
      (node (ref "C938") (pin "1") (pinfunction "1_1") (pintype "passive"))
      (node (ref "C939") (pin "2") (pinfunction "2_2") (pintype "passive"))
      (node (ref "C940") (pin "2") (pinfunction "2_2") (pintype "passive"))
      (node (ref "C941") (pin "1") (pinfunction "1_1") (pintype "passive"))
      (node (ref "C942") (pin "2") (pinfunction "2_2") (pintype "passive"))
      (node (ref "C943") (pin "2") (pinfunction "2_2") (pintype "passive"))
      (node (ref "C944") (pin "1") (pinfunction "1_1") (pintype "passive"))
      (node (ref "C945") (pin "2") (pinfunction "2_2") (pintype "passive"))
      (node (ref "C946") (pin "2") (pinfunction "2_2") (pintype "passive"))
      (node (ref "C947") (pin "1") (pinfunction "1_1") (pintype "passive"))
      (node (ref "C948") (pin "2") (pinfunction "2_2") (pintype "passive"))
      (node (ref "C949") (pin "2") (pinfunction "2_2") (pintype "passive"))
      (node (ref "C950") (pin "1") (pinfunction "1_1") (pintype "passive"))
      (node (ref "C951") (pin "2") (pinfunction "2_2") (pintype "passive"))
      (node (ref "C952") (pin "2") (pinfunction "2_2") (pintype "passive"))
      (node (ref "C953") (pin "1") (pinfunction "1_1") (pintype "passive"))
      (node (ref "C954") (pin "2") (pinfunction "2_2") (pintype "passive"))
      (node (ref "C955") (pin "2") (pinfunction "2_2") (pintype "passive"))
      (node (ref "C956") (pin "1") (pinfunction "1_1") (pintype "passive"))
      (node (ref "C957") (pin "2") (pinfunction "2_2") (pintype "passive"))
      (node (ref "C958") (pin "2") (pinfunction "2_2") (pintype "passive"))
      (node (ref "C959") (pin "1") (pinfunction "1_1") (pintype "passive"))
      (node (ref "C96") (pin "1") (pinfunction "1_1") (pintype "passive"))
      (node (ref "C960") (pin "2") (pinfunction "2_2") (pintype "passive"))
      (node (ref "C961") (pin "2") (pinfunction "2_2") (pintype "passive"))
      (node (ref "C962") (pin "1") (pinfunction "1_1") (pintype "passive"))
      (node (ref "C963") (pin "2") (pinfunction "2_2") (pintype "passive"))
      (node (ref "C964") (pin "2") (pinfunction "2_2") (pintype "passive"))
      (node (ref "C965") (pin "1") (pinfunction "1_1") (pintype "passive"))
      (node (ref "C966") (pin "2") (pinfunction "2_2") (pintype "passive"))
      (node (ref "C967") (pin "2") (pinfunction "2_2") (pintype "passive"))
      (node (ref "C968") (pin "1") (pinfunction "1_1") (pintype "passive"))
      (node (ref "C969") (pin "2") (pinfunction "2_2") (pintype "passive"))
      (node (ref "C97") (pin "1") (pinfunction "1_1") (pintype "passive"))
      (node (ref "C970") (pin "2") (pinfunction "2_2") (pintype "passive"))
      (node (ref "C971") (pin "1") (pinfunction "1_1") (pintype "passive"))
      (node (ref "C972") (pin "2") (pinfunction "2_2") (pintype "passive"))
      (node (ref "C973") (pin "2") (pinfunction "2_2") (pintype "passive"))
      (node (ref "C974") (pin "1") (pinfunction "1_1") (pintype "passive"))
      (node (ref "C975") (pin "2") (pinfunction "2_2") (pintype "passive"))
      (node (ref "C976") (pin "2") (pinfunction "2_2") (pintype "passive"))
      (node (ref "C977") (pin "1") (pinfunction "1_1") (pintype "passive"))
      (node (ref "C978") (pin "2") (pinfunction "2_2") (pintype "passive"))
      (node (ref "C979") (pin "2") (pinfunction "2_2") (pintype "passive"))
      (node (ref "C98") (pin "1") (pinfunction "1_1") (pintype "passive"))
      (node (ref "C980") (pin "1") (pinfunction "1_1") (pintype "passive"))
      (node (ref "C981") (pin "2") (pinfunction "2_2") (pintype "passive"))
      (node (ref "C982") (pin "2") (pinfunction "2_2") (pintype "passive"))
      (node (ref "C983") (pin "1") (pinfunction "1_1") (pintype "passive"))
      (node (ref "C984") (pin "2") (pinfunction "2_2") (pintype "passive"))
      (node (ref "C985") (pin "2") (pinfunction "2_2") (pintype "passive"))
      (node (ref "C986") (pin "1") (pinfunction "1_1") (pintype "passive"))
      (node (ref "C987") (pin "2") (pinfunction "2_2") (pintype "passive"))
      (node (ref "C988") (pin "2") (pinfunction "2_2") (pintype "passive"))
      (node (ref "C989") (pin "1") (pinfunction "1_1") (pintype "passive"))
      (node (ref "C99") (pin "1") (pinfunction "1_1") (pintype "passive"))
      (node (ref "C990") (pin "2") (pinfunction "2_2") (pintype "passive"))
      (node (ref "C991") (pin "2") (pinfunction "2_2") (pintype "passive"))
      (node (ref "C992") (pin "1") (pinfunction "1_1") (pintype "passive"))
      (node (ref "C993") (pin "2") (pinfunction "2_2") (pintype "passive"))
      (node (ref "C994") (pin "2") (pinfunction "2_2") (pintype "passive"))
      (node (ref "C995") (pin "1") (pinfunction "1_1") (pintype "passive"))
      (node (ref "C996") (pin "2") (pinfunction "2_2") (pintype "passive"))
      (node (ref "C997") (pin "2") (pinfunction "2_2") (pintype "passive"))
      (node (ref "C998") (pin "1") (pinfunction "1_1") (pintype "passive"))
      (node (ref "C999") (pin "2") (pinfunction "2_2") (pintype "passive"))
      (node (ref "Q17") (pin "1") (pinfunction "S_1") (pintype "passive"))
      (node (ref "Q17") (pin "2") (pinfunction "S_2") (pintype "passive"))
      (node (ref "Q17") (pin "3") (pinfunction "S_3") (pintype "passive"))
      (node (ref "Q18") (pin "1") (pinfunction "S_1") (pintype "passive"))
      (node (ref "Q18") (pin "2") (pinfunction "S_2") (pintype "passive"))
      (node (ref "Q18") (pin "3") (pinfunction "S_3") (pintype "passive"))
      (node (ref "Q19") (pin "1") (pinfunction "S_1") (pintype "passive"))
      (node (ref "Q19") (pin "2") (pinfunction "S_2") (pintype "passive"))
      (node (ref "Q19") (pin "3") (pinfunction "S_3") (pintype "passive"))
      (node (ref "Q20") (pin "1") (pinfunction "S_1") (pintype "passive"))
      (node (ref "Q20") (pin "2") (pinfunction "S_2") (pintype "passive"))
      (node (ref "Q20") (pin "3") (pinfunction "S_3") (pintype "passive"))
      (node (ref "Q29") (pin "1") (pinfunction "S_1") (pintype "passive"))
      (node (ref "Q29") (pin "2") (pinfunction "S_2") (pintype "passive"))
      (node (ref "Q29") (pin "3") (pinfunction "S_3") (pintype "passive"))
      (node (ref "Q30") (pin "1") (pinfunction "S_1") (pintype "passive"))
      (node (ref "Q30") (pin "2") (pinfunction "S_2") (pintype "passive"))
      (node (ref "Q30") (pin "3") (pinfunction "S_3") (pintype "passive"))
      (node (ref "Q31") (pin "1") (pinfunction "S_1") (pintype "passive"))
      (node (ref "Q31") (pin "2") (pinfunction "S_2") (pintype "passive"))
      (node (ref "Q31") (pin "3") (pinfunction "S_3") (pintype "passive"))
      (node (ref "Q32") (pin "1") (pinfunction "S_1") (pintype "passive"))
      (node (ref "Q32") (pin "2") (pinfunction "S_2") (pintype "passive"))
      (node (ref "Q32") (pin "3") (pinfunction "S_3") (pintype "passive"))
      (node (ref "Q41") (pin "1") (pinfunction "S_1") (pintype "passive"))
      (node (ref "Q41") (pin "2") (pinfunction "S_2") (pintype "passive"))
      (node (ref "Q41") (pin "3") (pinfunction "S_3") (pintype "passive"))
      (node (ref "Q42") (pin "1") (pinfunction "S_1") (pintype "passive"))
      (node (ref "Q42") (pin "2") (pinfunction "S_2") (pintype "passive"))
      (node (ref "Q42") (pin "3") (pinfunction "S_3") (pintype "passive"))
      (node (ref "Q43") (pin "1") (pinfunction "S_1") (pintype "passive"))
      (node (ref "Q43") (pin "2") (pinfunction "S_2") (pintype "passive"))
      (node (ref "Q43") (pin "3") (pinfunction "S_3") (pintype "passive"))
      (node (ref "Q44") (pin "1") (pinfunction "S_1") (pintype "passive"))
      (node (ref "Q44") (pin "2") (pinfunction "S_2") (pintype "passive"))
      (node (ref "Q44") (pin "3") (pinfunction "S_3") (pintype "passive"))
      (node (ref "Q5") (pin "1") (pinfunction "S_1") (pintype "passive"))
      (node (ref "Q5") (pin "2") (pinfunction "S_2") (pintype "passive"))
      (node (ref "Q5") (pin "3") (pinfunction "S_3") (pintype "passive"))
      (node (ref "Q6") (pin "1") (pinfunction "S_1") (pintype "passive"))
      (node (ref "Q6") (pin "2") (pinfunction "S_2") (pintype "passive"))
      (node (ref "Q6") (pin "3") (pinfunction "S_3") (pintype "passive"))
      (node (ref "Q7") (pin "1") (pinfunction "S_1") (pintype "passive"))
      (node (ref "Q7") (pin "2") (pinfunction "S_2") (pintype "passive"))
      (node (ref "Q7") (pin "3") (pinfunction "S_3") (pintype "passive"))
      (node (ref "Q8") (pin "1") (pinfunction "S_1") (pintype "passive"))
      (node (ref "Q8") (pin "2") (pinfunction "S_2") (pintype "passive"))
      (node (ref "Q8") (pin "3") (pinfunction "S_3") (pintype "passive"))
      (node (ref "U11") (pin "4") (pinfunction "GND_4") (pintype "passive"))
      (node (ref "U11") (pin "9") (pinfunction "EP_9") (pintype "passive"))
      (node (ref "U12") (pin "4") (pinfunction "GND_4") (pintype "passive"))
      (node (ref "U12") (pin "9") (pinfunction "EP_9") (pintype "passive"))
      (node (ref "U15") (pin "4") (pinfunction "GND_4") (pintype "passive"))
      (node (ref "U15") (pin "9") (pinfunction "EP_9") (pintype "passive"))
      (node (ref "U16") (pin "4") (pinfunction "GND_4") (pintype "passive"))
      (node (ref "U16") (pin "9") (pinfunction "EP_9") (pintype "passive"))
      (node (ref "U19") (pin "4") (pinfunction "GND_4") (pintype "passive"))
      (node (ref "U19") (pin "9") (pinfunction "EP_9") (pintype "passive"))
      (node (ref "U20") (pin "4") (pinfunction "GND_4") (pintype "passive"))
      (node (ref "U20") (pin "9") (pinfunction "EP_9") (pintype "passive"))
      (node (ref "U23") (pin "4") (pinfunction "GND_4") (pintype "passive"))
      (node (ref "U23") (pin "9") (pinfunction "EP_9") (pintype "passive"))
      (node (ref "U24") (pin "4") (pinfunction "GND_4") (pintype "passive"))
      (node (ref "U24") (pin "9") (pinfunction "EP_9") (pintype "passive"))
    )
  )
)
